# mt15_pla.net
KiCad netlist of a schematic drawn in EAGLE
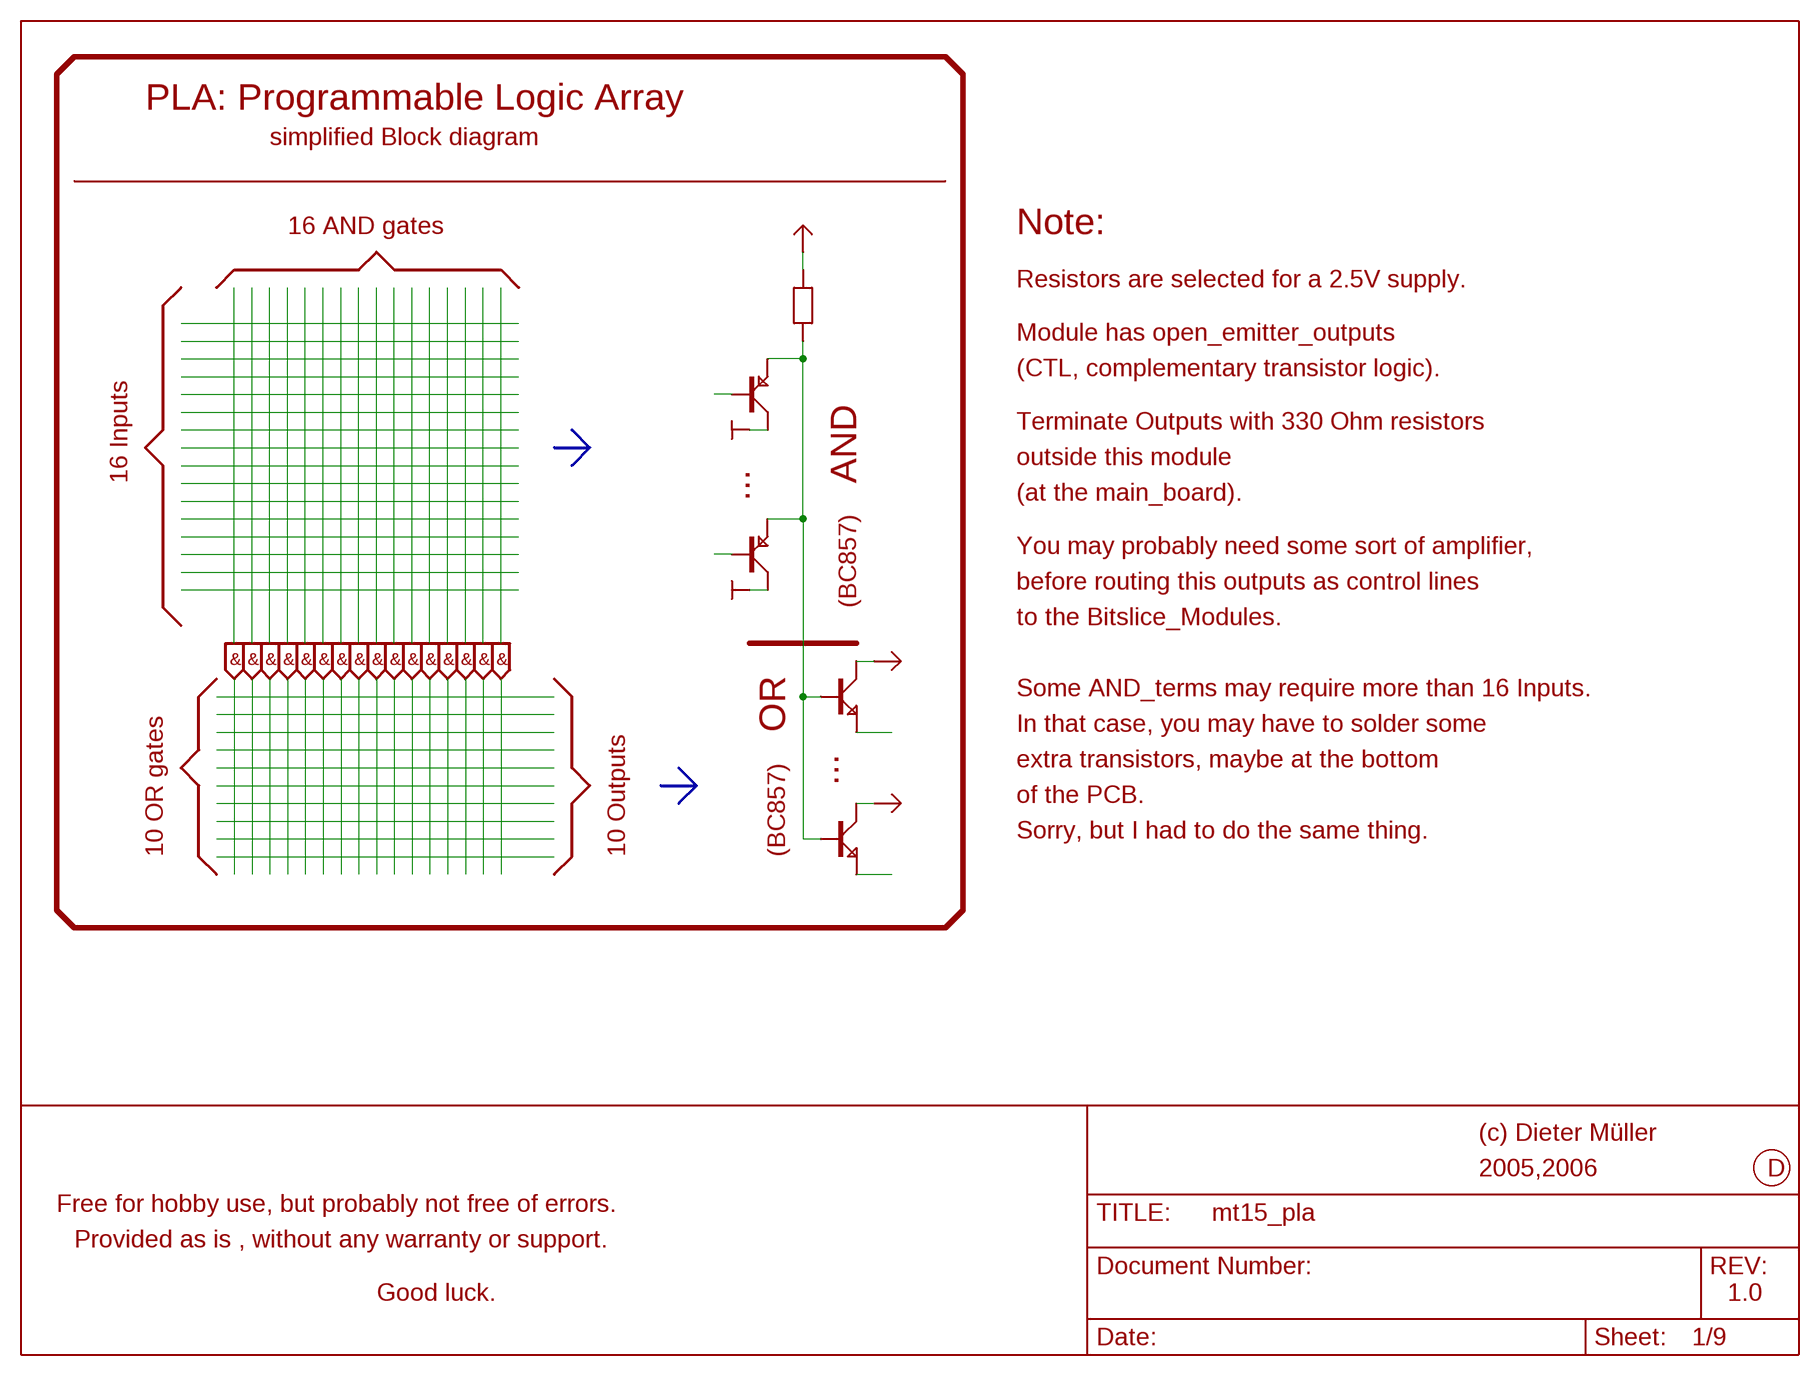
[diagram p0: schematic, sheet 1]
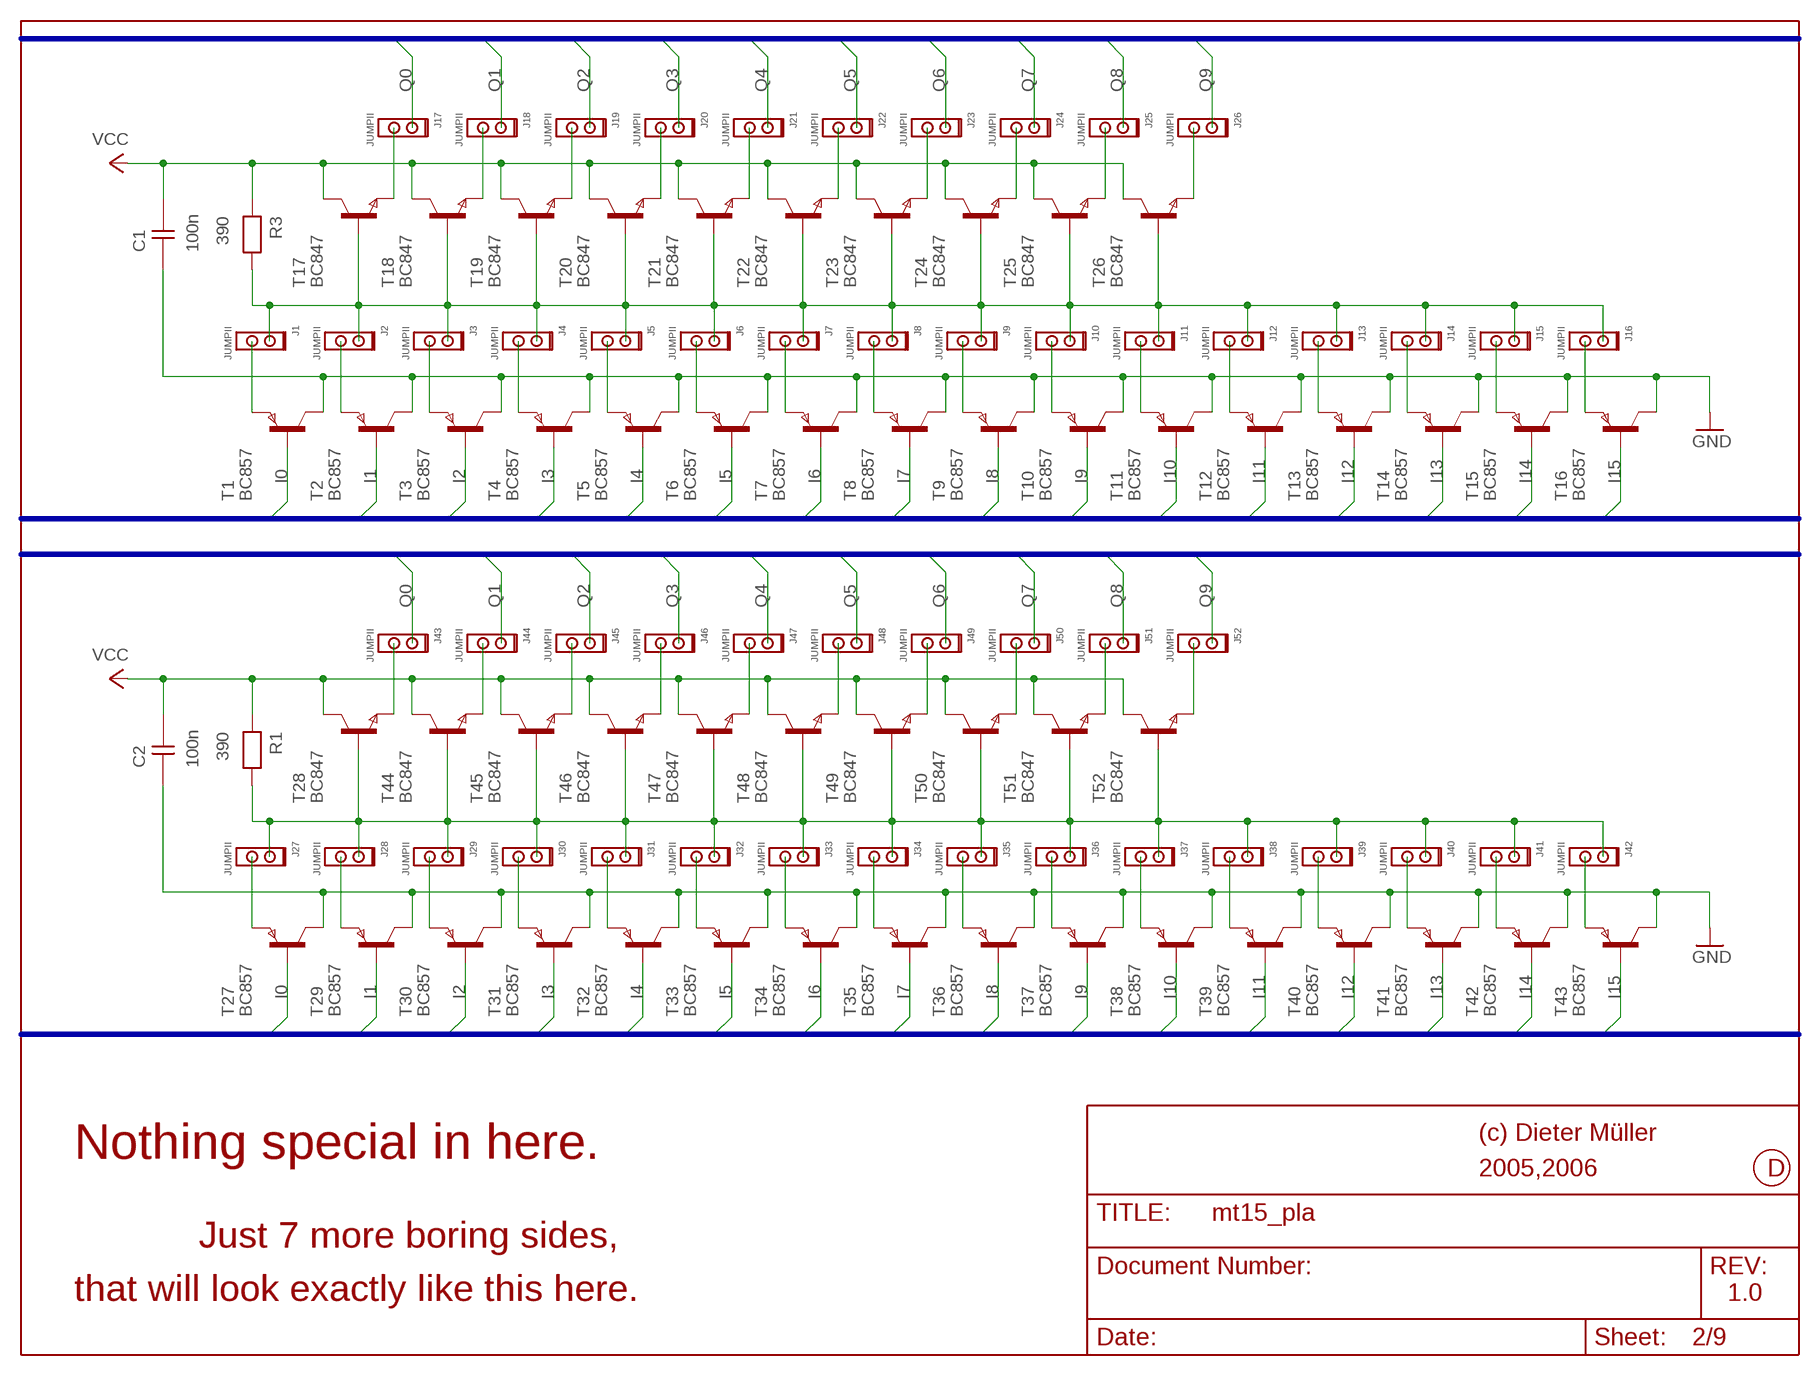
[diagram p1: schematic, sheet 2]
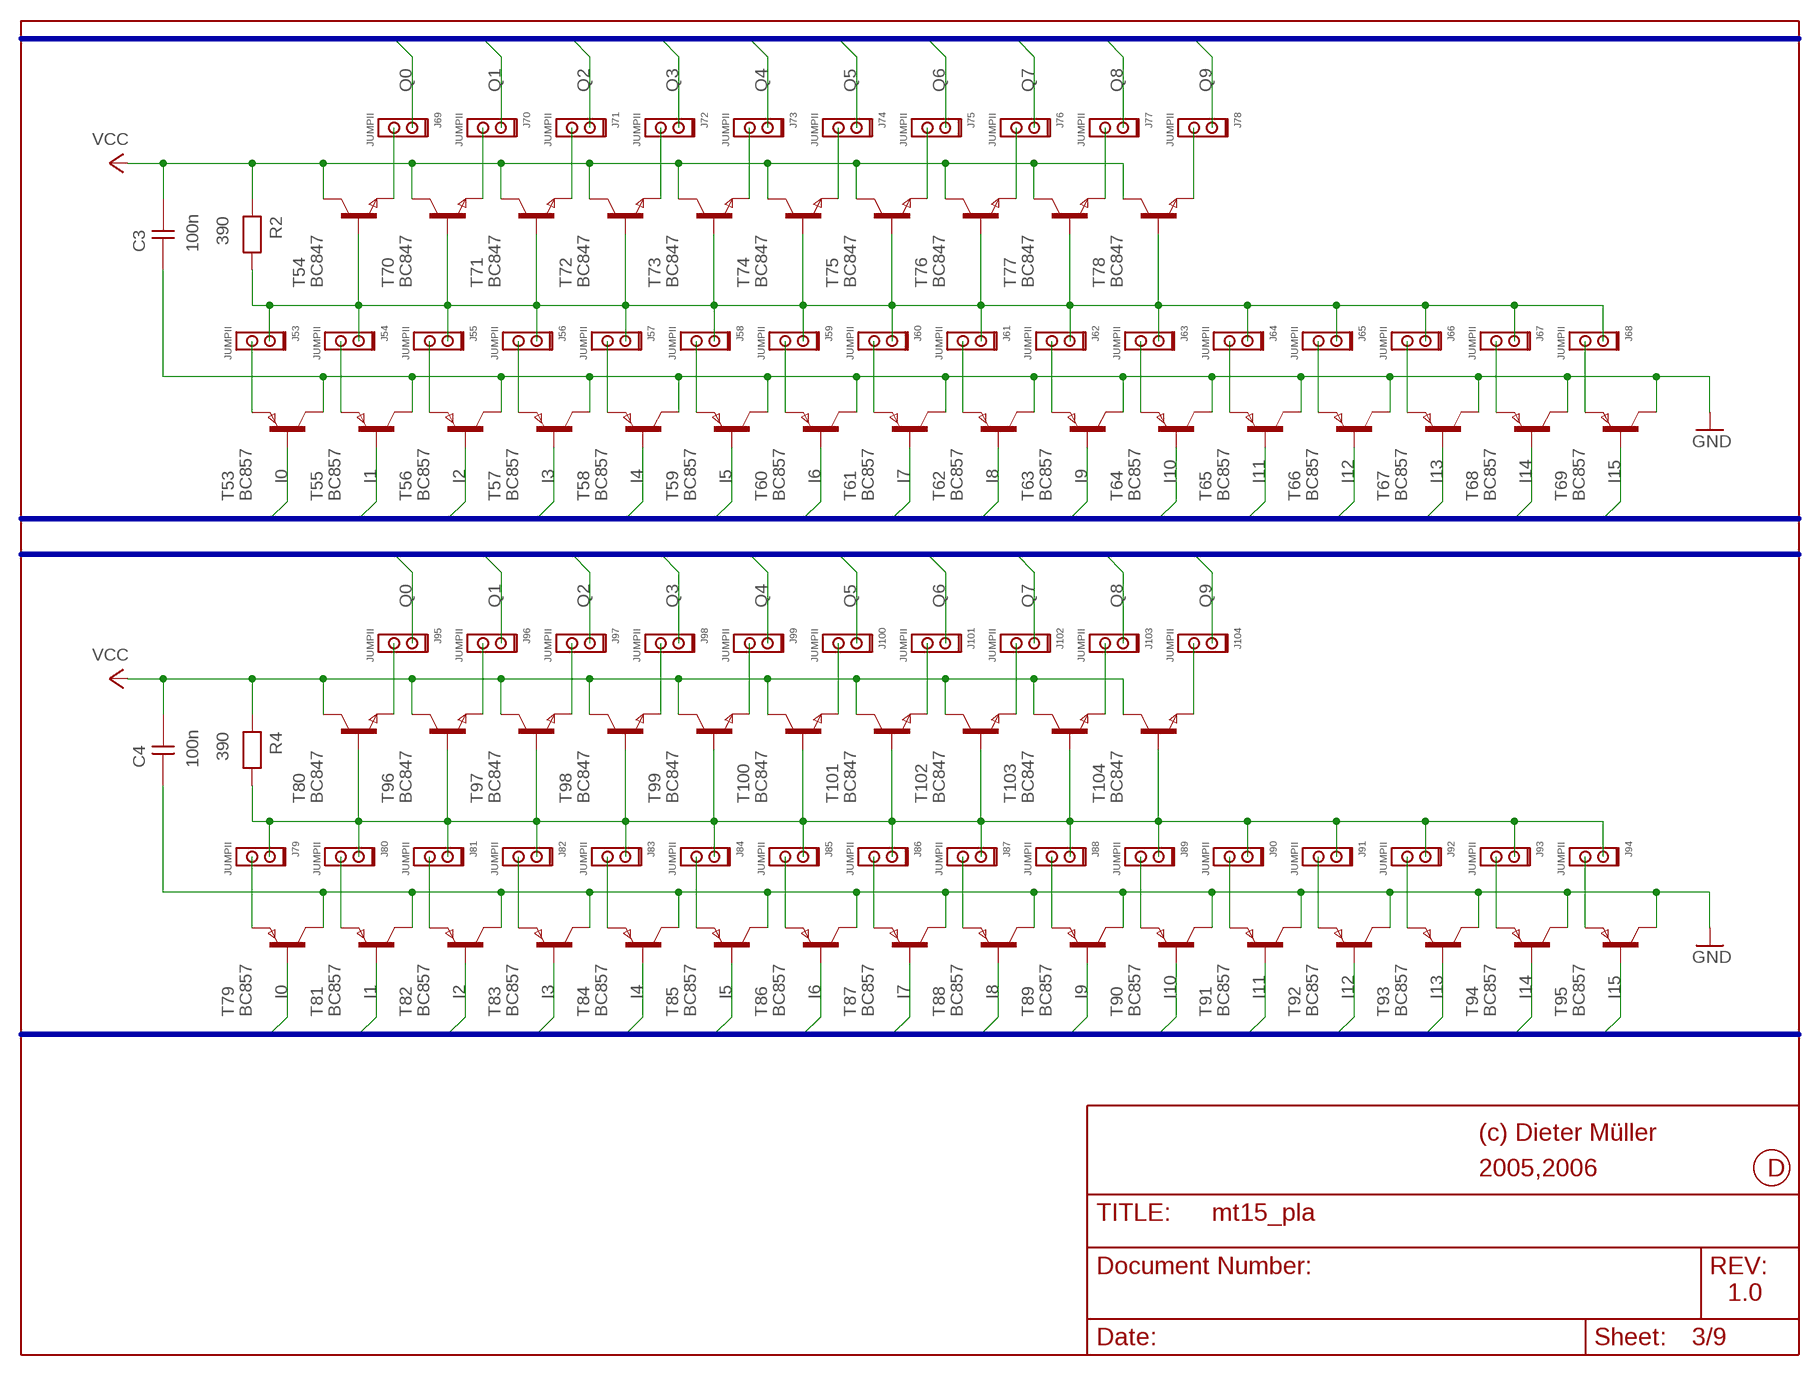
[diagram p2: schematic, sheet 3]
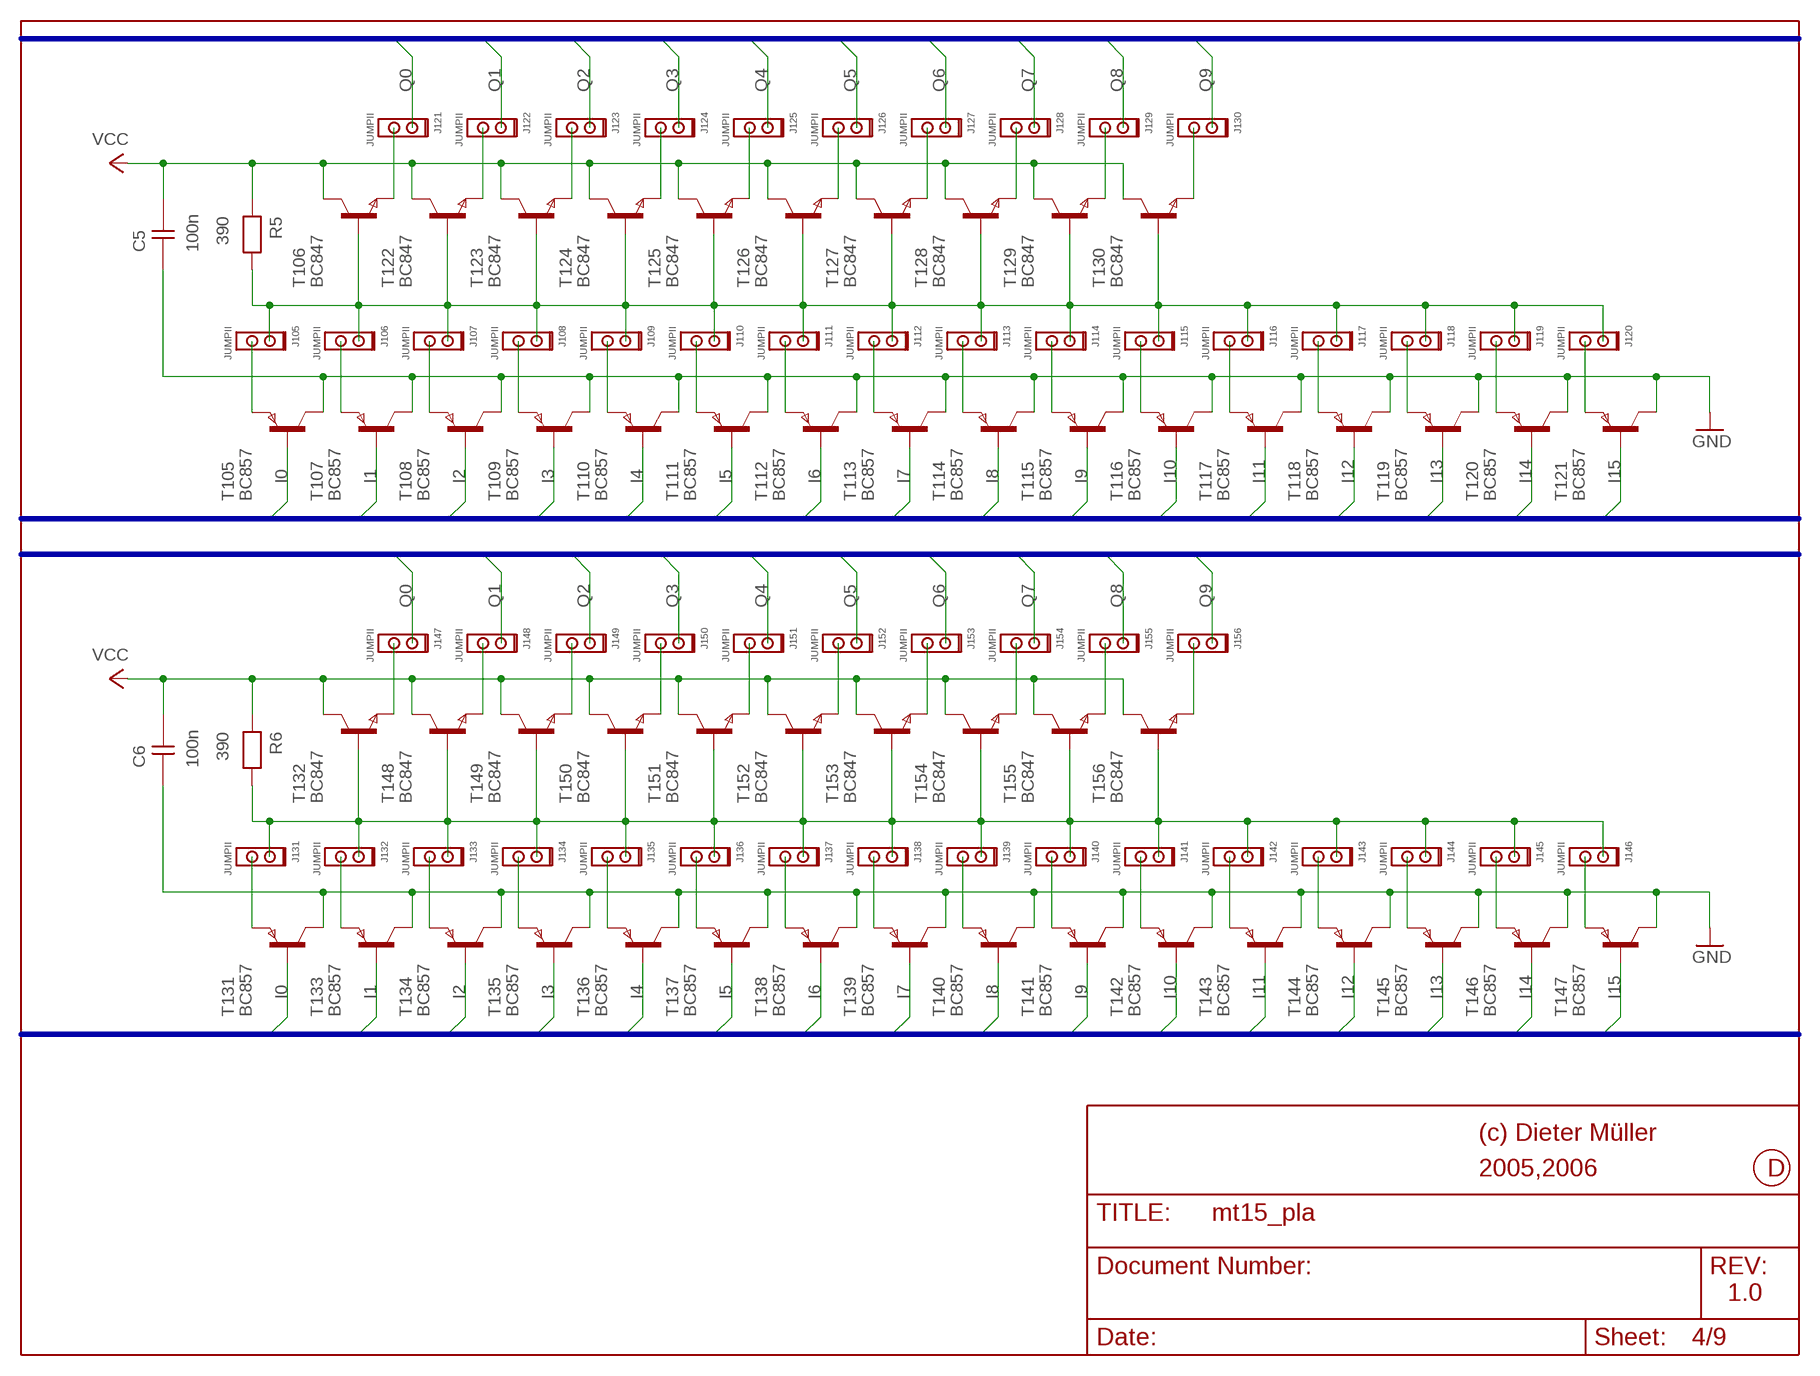
[diagram p3: schematic, sheet 4]
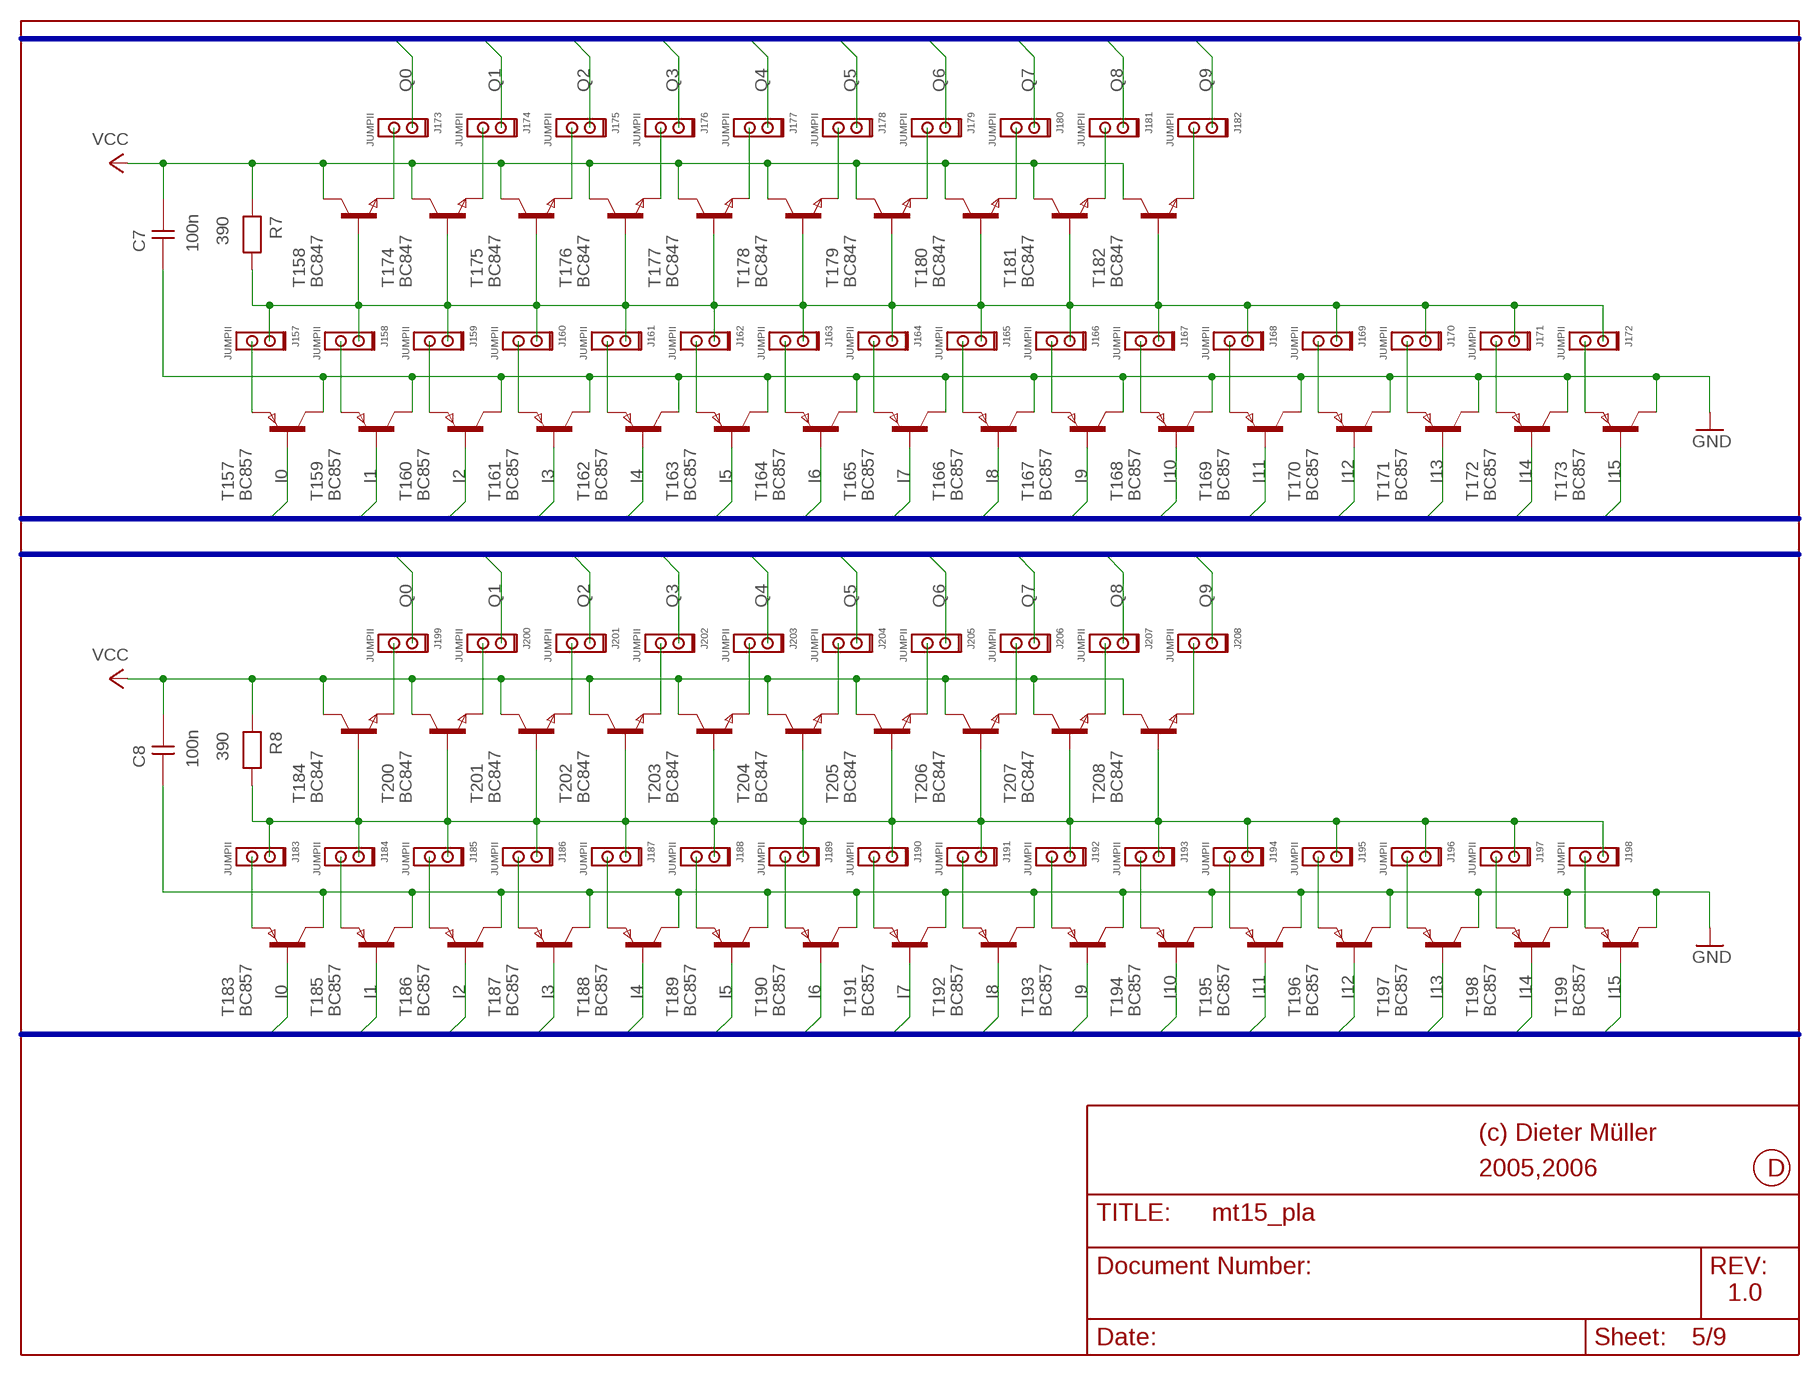
[diagram p4: schematic, sheet 5]
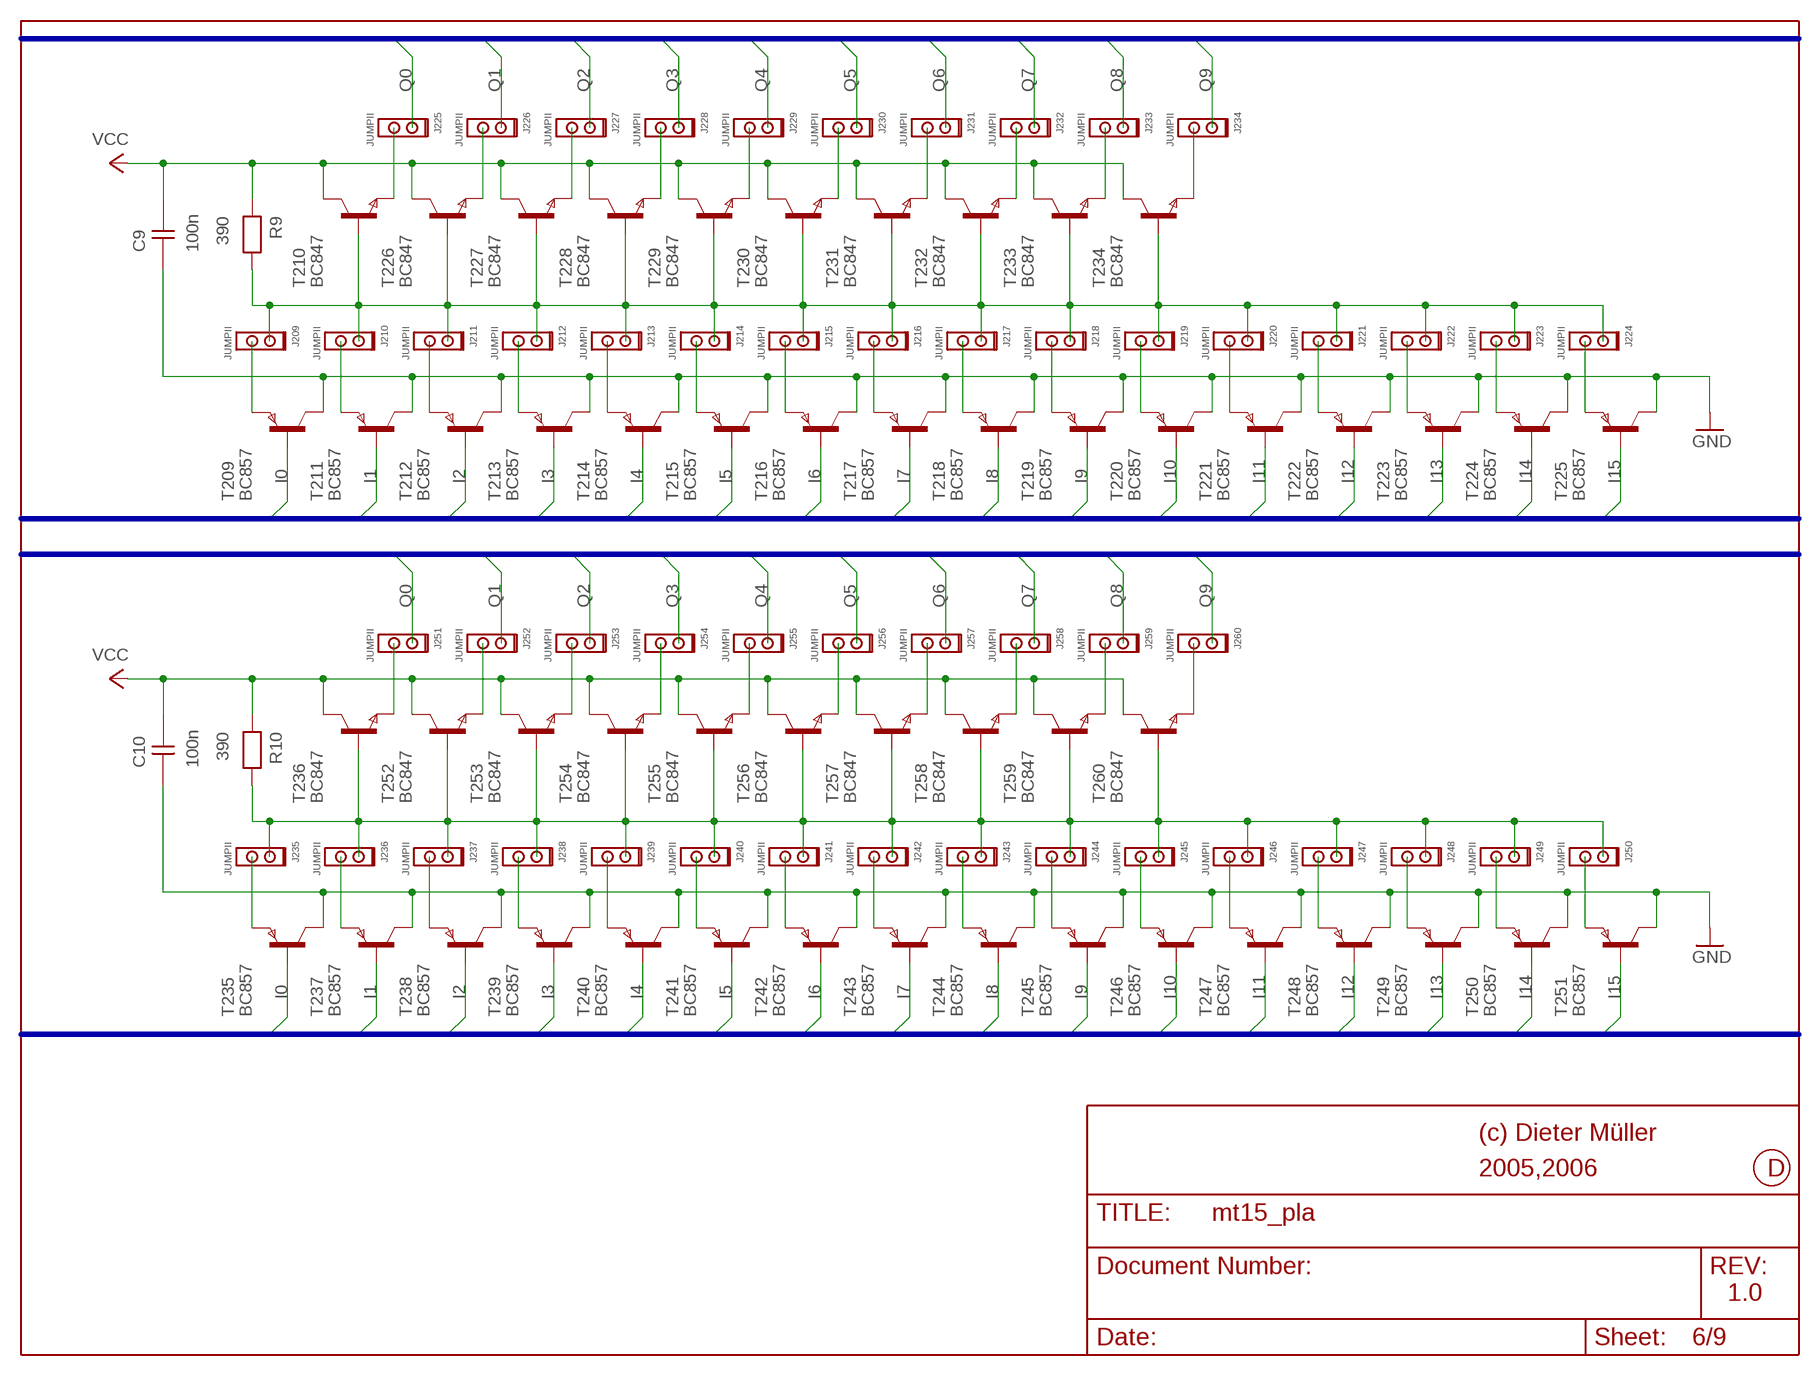
[diagram p5: schematic, sheet 6]
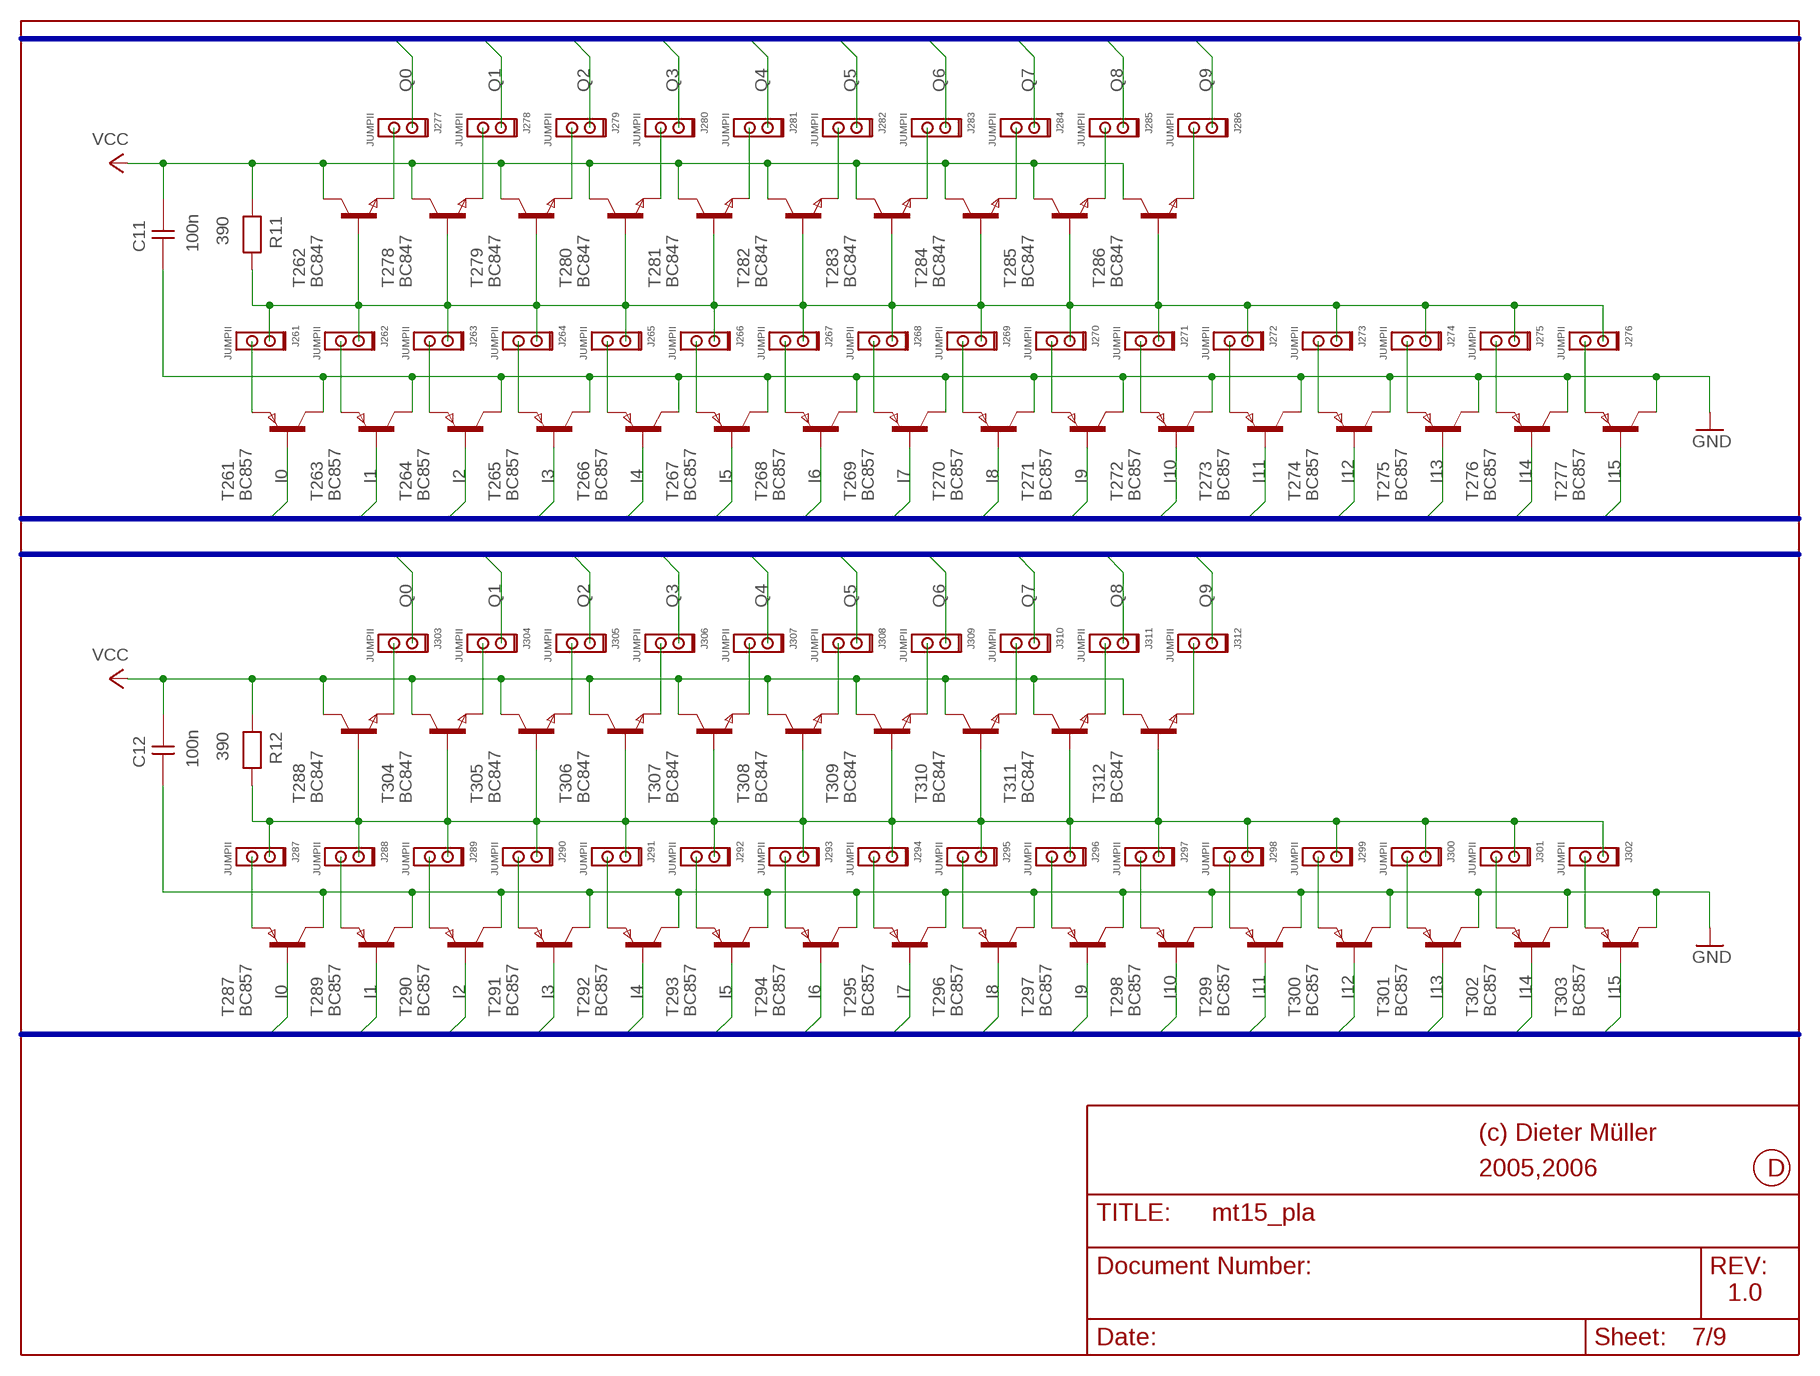
[diagram p6: schematic, sheet 7]
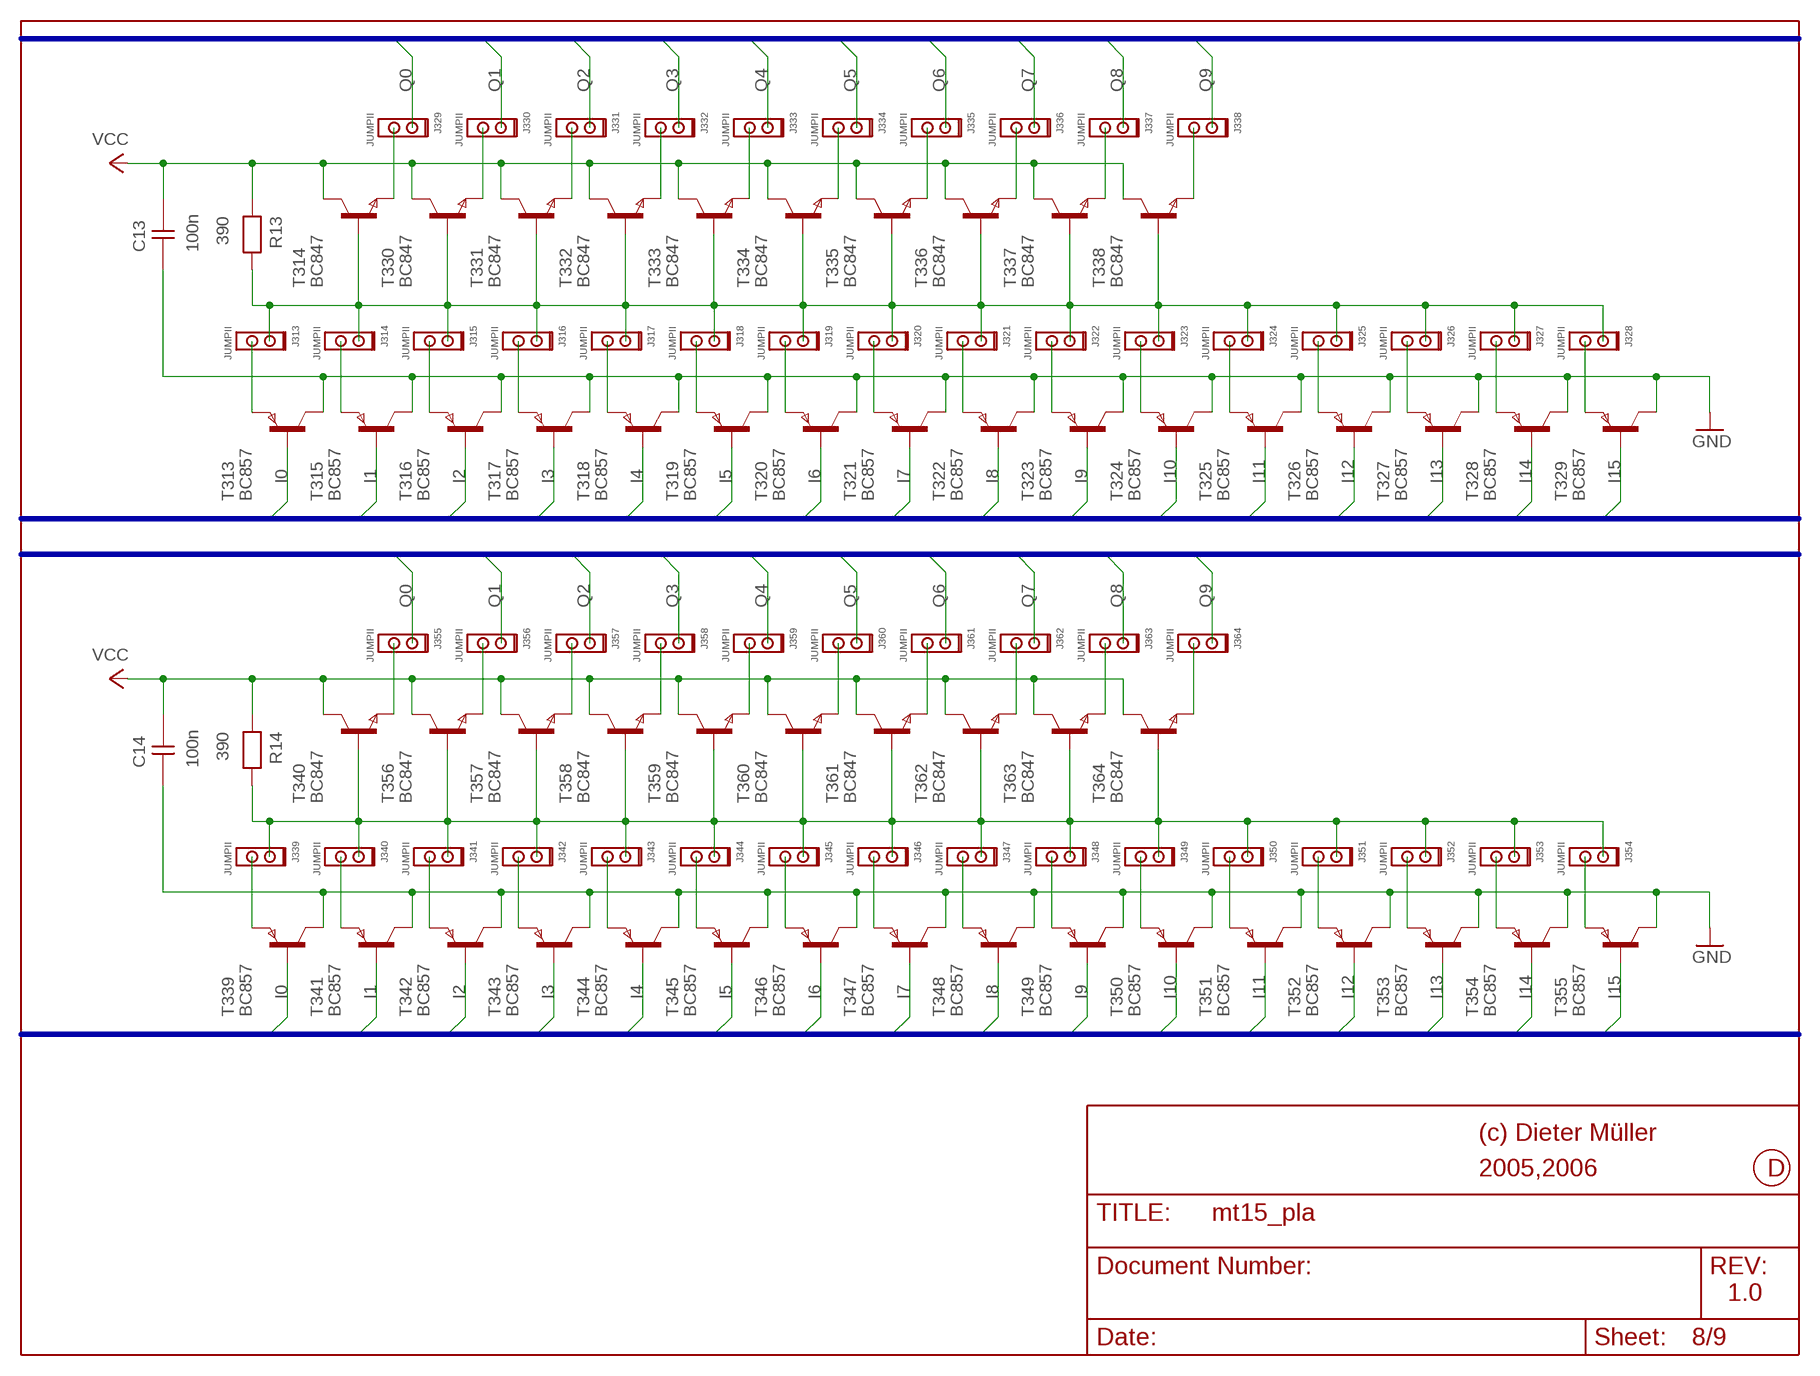
[diagram p7: schematic, sheet 8]
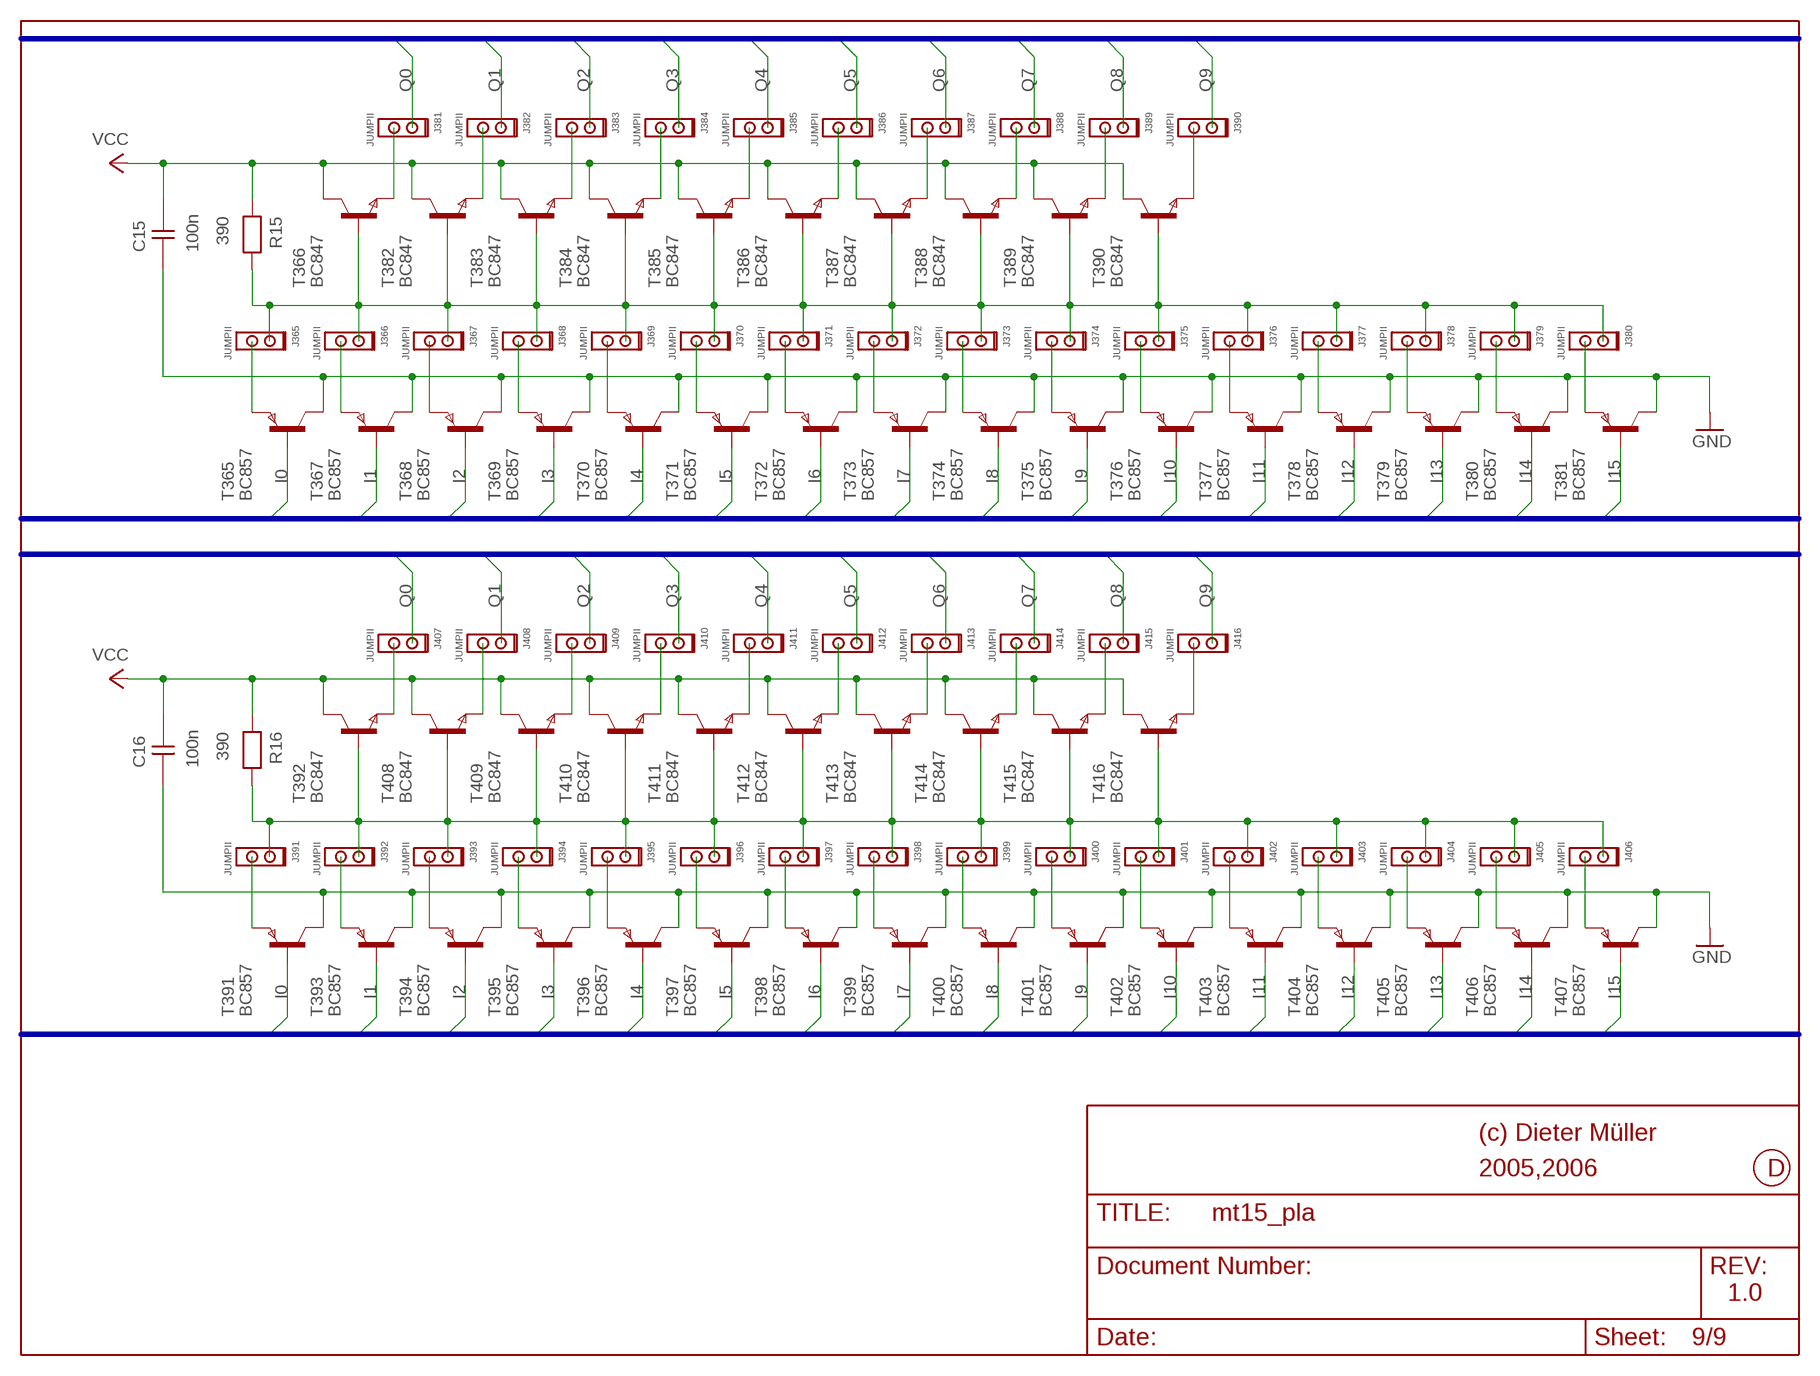
[diagram p8: schematic, sheet 9]

(export (version "E")
  (design (tool "Eeschema 10.0.6"))
  (components
    (comp (ref "C9")
      (value "100n")
      (footprint "eagle-import:0204")
      (libsource (lib "eagle-import") (part "CAPNP-5"))
    )
    (comp (ref "C10")
      (value "100n")
      (footprint "eagle-import:0204")
      (libsource (lib "eagle-import") (part "CAPNP-5"))
    )
    (comp (ref "J209")
      (value "JUMPII")
      (footprint "eagle-import:JUMPII")
      (libsource (lib "eagle-import") (part "JUMPII@2"))
    )
    (comp (ref "J210")
      (value "JUMPII")
      (footprint "eagle-import:JUMPII")
      (libsource (lib "eagle-import") (part "JUMPII@2"))
    )
    (comp (ref "J211")
      (value "JUMPII")
      (footprint "eagle-import:JUMPII")
      (libsource (lib "eagle-import") (part "JUMPII@2"))
    )
    (comp (ref "J212")
      (value "JUMPII")
      (footprint "eagle-import:JUMPII")
      (libsource (lib "eagle-import") (part "JUMPII@2"))
    )
    (comp (ref "J213")
      (value "JUMPII")
      (footprint "eagle-import:JUMPII")
      (libsource (lib "eagle-import") (part "JUMPII@2"))
    )
    (comp (ref "J214")
      (value "JUMPII")
      (footprint "eagle-import:JUMPII")
      (libsource (lib "eagle-import") (part "JUMPII@2"))
    )
    (comp (ref "J215")
      (value "JUMPII")
      (footprint "eagle-import:JUMPII")
      (libsource (lib "eagle-import") (part "JUMPII@2"))
    )
    (comp (ref "J216")
      (value "JUMPII")
      (footprint "eagle-import:JUMPII")
      (libsource (lib "eagle-import") (part "JUMPII@2"))
    )
    (comp (ref "J217")
      (value "JUMPII")
      (footprint "eagle-import:JUMPII")
      (libsource (lib "eagle-import") (part "JUMPII@2"))
    )
    (comp (ref "J218")
      (value "JUMPII")
      (footprint "eagle-import:JUMPII")
      (libsource (lib "eagle-import") (part "JUMPII@2"))
    )
    (comp (ref "J219")
      (value "JUMPII")
      (footprint "eagle-import:JUMPII")
      (libsource (lib "eagle-import") (part "JUMPII@2"))
    )
    (comp (ref "J220")
      (value "JUMPII")
      (footprint "eagle-import:JUMPII")
      (libsource (lib "eagle-import") (part "JUMPII@2"))
    )
    (comp (ref "J221")
      (value "JUMPII")
      (footprint "eagle-import:JUMPII")
      (libsource (lib "eagle-import") (part "JUMPII@2"))
    )
    (comp (ref "J222")
      (value "JUMPII")
      (footprint "eagle-import:JUMPII")
      (libsource (lib "eagle-import") (part "JUMPII@2"))
    )
    (comp (ref "J223")
      (value "JUMPII")
      (footprint "eagle-import:JUMPII")
      (libsource (lib "eagle-import") (part "JUMPII@2"))
    )
    (comp (ref "J224")
      (value "JUMPII")
      (footprint "eagle-import:JUMPII")
      (libsource (lib "eagle-import") (part "JUMPII@2"))
    )
    (comp (ref "J225")
      (value "JUMPII")
      (footprint "eagle-import:JUMPII")
      (libsource (lib "eagle-import") (part "JUMPII@2"))
    )
    (comp (ref "J226")
      (value "JUMPII")
      (footprint "eagle-import:JUMPII")
      (libsource (lib "eagle-import") (part "JUMPII@2"))
    )
    (comp (ref "J227")
      (value "JUMPII")
      (footprint "eagle-import:JUMPII")
      (libsource (lib "eagle-import") (part "JUMPII@2"))
    )
    (comp (ref "J228")
      (value "JUMPII")
      (footprint "eagle-import:JUMPII")
      (libsource (lib "eagle-import") (part "JUMPII@2"))
    )
    (comp (ref "J229")
      (value "JUMPII")
      (footprint "eagle-import:JUMPII")
      (libsource (lib "eagle-import") (part "JUMPII@2"))
    )
    (comp (ref "J230")
      (value "JUMPII")
      (footprint "eagle-import:JUMPII")
      (libsource (lib "eagle-import") (part "JUMPII@2"))
    )
    (comp (ref "J231")
      (value "JUMPII")
      (footprint "eagle-import:JUMPII")
      (libsource (lib "eagle-import") (part "JUMPII@2"))
    )
    (comp (ref "J232")
      (value "JUMPII")
      (footprint "eagle-import:JUMPII")
      (libsource (lib "eagle-import") (part "JUMPII@2"))
    )
    (comp (ref "J233")
      (value "JUMPII")
      (footprint "eagle-import:JUMPII")
      (libsource (lib "eagle-import") (part "JUMPII@2"))
    )
    (comp (ref "J234")
      (value "JUMPII")
      (footprint "eagle-import:JUMPII")
      (libsource (lib "eagle-import") (part "JUMPII@2"))
    )
    (comp (ref "J235")
      (value "JUMPII")
      (footprint "eagle-import:JUMPII")
      (libsource (lib "eagle-import") (part "JUMPII@2"))
    )
    (comp (ref "J236")
      (value "JUMPII")
      (footprint "eagle-import:JUMPII")
      (libsource (lib "eagle-import") (part "JUMPII@2"))
    )
    (comp (ref "J237")
      (value "JUMPII")
      (footprint "eagle-import:JUMPII")
      (libsource (lib "eagle-import") (part "JUMPII@2"))
    )
    (comp (ref "J238")
      (value "JUMPII")
      (footprint "eagle-import:JUMPII")
      (libsource (lib "eagle-import") (part "JUMPII@2"))
    )
    (comp (ref "J239")
      (value "JUMPII")
      (footprint "eagle-import:JUMPII")
      (libsource (lib "eagle-import") (part "JUMPII@2"))
    )
    (comp (ref "J240")
      (value "JUMPII")
      (footprint "eagle-import:JUMPII")
      (libsource (lib "eagle-import") (part "JUMPII@2"))
    )
    (comp (ref "J241")
      (value "JUMPII")
      (footprint "eagle-import:JUMPII")
      (libsource (lib "eagle-import") (part "JUMPII@2"))
    )
    (comp (ref "J242")
      (value "JUMPII")
      (footprint "eagle-import:JUMPII")
      (libsource (lib "eagle-import") (part "JUMPII@2"))
    )
    (comp (ref "J243")
      (value "JUMPII")
      (footprint "eagle-import:JUMPII")
      (libsource (lib "eagle-import") (part "JUMPII@2"))
    )
    (comp (ref "J244")
      (value "JUMPII")
      (footprint "eagle-import:JUMPII")
      (libsource (lib "eagle-import") (part "JUMPII@2"))
    )
    (comp (ref "J245")
      (value "JUMPII")
      (footprint "eagle-import:JUMPII")
      (libsource (lib "eagle-import") (part "JUMPII@2"))
    )
    (comp (ref "J246")
      (value "JUMPII")
      (footprint "eagle-import:JUMPII")
      (libsource (lib "eagle-import") (part "JUMPII@2"))
    )
    (comp (ref "J247")
      (value "JUMPII")
      (footprint "eagle-import:JUMPII")
      (libsource (lib "eagle-import") (part "JUMPII@2"))
    )
    (comp (ref "J248")
      (value "JUMPII")
      (footprint "eagle-import:JUMPII")
      (libsource (lib "eagle-import") (part "JUMPII@2"))
    )
    (comp (ref "J249")
      (value "JUMPII")
      (footprint "eagle-import:JUMPII")
      (libsource (lib "eagle-import") (part "JUMPII@2"))
    )
    (comp (ref "J250")
      (value "JUMPII")
      (footprint "eagle-import:JUMPII")
      (libsource (lib "eagle-import") (part "JUMPII@2"))
    )
    (comp (ref "J251")
      (value "JUMPII")
      (footprint "eagle-import:JUMPII")
      (libsource (lib "eagle-import") (part "JUMPII@2"))
    )
    (comp (ref "J252")
      (value "JUMPII")
      (footprint "eagle-import:JUMPII")
      (libsource (lib "eagle-import") (part "JUMPII@2"))
    )
    (comp (ref "J253")
      (value "JUMPII")
      (footprint "eagle-import:JUMPII")
      (libsource (lib "eagle-import") (part "JUMPII@2"))
    )
    (comp (ref "J254")
      (value "JUMPII")
      (footprint "eagle-import:JUMPII")
      (libsource (lib "eagle-import") (part "JUMPII@2"))
    )
    (comp (ref "J255")
      (value "JUMPII")
      (footprint "eagle-import:JUMPII")
      (libsource (lib "eagle-import") (part "JUMPII@2"))
    )
    (comp (ref "J256")
      (value "JUMPII")
      (footprint "eagle-import:JUMPII")
      (libsource (lib "eagle-import") (part "JUMPII@2"))
    )
    (comp (ref "J257")
      (value "JUMPII")
      (footprint "eagle-import:JUMPII")
      (libsource (lib "eagle-import") (part "JUMPII@2"))
    )
    (comp (ref "J258")
      (value "JUMPII")
      (footprint "eagle-import:JUMPII")
      (libsource (lib "eagle-import") (part "JUMPII@2"))
    )
    (comp (ref "J259")
      (value "JUMPII")
      (footprint "eagle-import:JUMPII")
      (libsource (lib "eagle-import") (part "JUMPII@2"))
    )
    (comp (ref "J260")
      (value "JUMPII")
      (footprint "eagle-import:JUMPII")
      (libsource (lib "eagle-import") (part "JUMPII@2"))
    )
    (comp (ref "R9")
      (value "390")
      (footprint "eagle-import:0204")
      (libsource (lib "eagle-import") (part "RESEU-7,5"))
    )
    (comp (ref "R10")
      (value "390")
      (footprint "eagle-import:0204")
      (libsource (lib "eagle-import") (part "RESEU-7,5"))
    )
    (comp (ref "T209")
      (value "BC857")
      (footprint "eagle-import:SOT-23")
      (libsource (lib "eagle-import") (part "BC557"))
    )
    (comp (ref "T210")
      (value "BC847")
      (footprint "eagle-import:SOT-23")
      (libsource (lib "eagle-import") (part "BC547"))
    )
    (comp (ref "T211")
      (value "BC857")
      (footprint "eagle-import:SOT-23")
      (libsource (lib "eagle-import") (part "BC557"))
    )
    (comp (ref "T212")
      (value "BC857")
      (footprint "eagle-import:SOT-23")
      (libsource (lib "eagle-import") (part "BC557"))
    )
    (comp (ref "T213")
      (value "BC857")
      (footprint "eagle-import:SOT-23")
      (libsource (lib "eagle-import") (part "BC557"))
    )
    (comp (ref "T214")
      (value "BC857")
      (footprint "eagle-import:SOT-23")
      (libsource (lib "eagle-import") (part "BC557"))
    )
    (comp (ref "T215")
      (value "BC857")
      (footprint "eagle-import:SOT-23")
      (libsource (lib "eagle-import") (part "BC557"))
    )
    (comp (ref "T216")
      (value "BC857")
      (footprint "eagle-import:SOT-23")
      (libsource (lib "eagle-import") (part "BC557"))
    )
    (comp (ref "T217")
      (value "BC857")
      (footprint "eagle-import:SOT-23")
      (libsource (lib "eagle-import") (part "BC557"))
    )
    (comp (ref "T218")
      (value "BC857")
      (footprint "eagle-import:SOT-23")
      (libsource (lib "eagle-import") (part "BC557"))
    )
    (comp (ref "T219")
      (value "BC857")
      (footprint "eagle-import:SOT-23")
      (libsource (lib "eagle-import") (part "BC557"))
    )
    (comp (ref "T220")
      (value "BC857")
      (footprint "eagle-import:SOT-23")
      (libsource (lib "eagle-import") (part "BC557"))
    )
    (comp (ref "T221")
      (value "BC857")
      (footprint "eagle-import:SOT-23")
      (libsource (lib "eagle-import") (part "BC557"))
    )
    (comp (ref "T222")
      (value "BC857")
      (footprint "eagle-import:SOT-23")
      (libsource (lib "eagle-import") (part "BC557"))
    )
    (comp (ref "T223")
      (value "BC857")
      (footprint "eagle-import:SOT-23")
      (libsource (lib "eagle-import") (part "BC557"))
    )
    (comp (ref "T224")
      (value "BC857")
      (footprint "eagle-import:SOT-23")
      (libsource (lib "eagle-import") (part "BC557"))
    )
    (comp (ref "T225")
      (value "BC857")
      (footprint "eagle-import:SOT-23")
      (libsource (lib "eagle-import") (part "BC557"))
    )
    (comp (ref "T226")
      (value "BC847")
      (footprint "eagle-import:SOT-23")
      (libsource (lib "eagle-import") (part "BC547"))
    )
    (comp (ref "T227")
      (value "BC847")
      (footprint "eagle-import:SOT-23")
      (libsource (lib "eagle-import") (part "BC547"))
    )
    (comp (ref "T228")
      (value "BC847")
      (footprint "eagle-import:SOT-23")
      (libsource (lib "eagle-import") (part "BC547"))
    )
    (comp (ref "T229")
      (value "BC847")
      (footprint "eagle-import:SOT-23")
      (libsource (lib "eagle-import") (part "BC547"))
    )
    (comp (ref "T230")
      (value "BC847")
      (footprint "eagle-import:SOT-23")
      (libsource (lib "eagle-import") (part "BC547"))
    )
    (comp (ref "T231")
      (value "BC847")
      (footprint "eagle-import:SOT-23")
      (libsource (lib "eagle-import") (part "BC547"))
    )
    (comp (ref "T232")
      (value "BC847")
      (footprint "eagle-import:SOT-23")
      (libsource (lib "eagle-import") (part "BC547"))
    )
    (comp (ref "T233")
      (value "BC847")
      (footprint "eagle-import:SOT-23")
      (libsource (lib "eagle-import") (part "BC547"))
    )
    (comp (ref "T234")
      (value "BC847")
      (footprint "eagle-import:SOT-23")
      (libsource (lib "eagle-import") (part "BC547"))
    )
    (comp (ref "T235")
      (value "BC857")
      (footprint "eagle-import:SOT-23")
      (libsource (lib "eagle-import") (part "BC557"))
    )
    (comp (ref "T236")
      (value "BC847")
      (footprint "eagle-import:SOT-23")
      (libsource (lib "eagle-import") (part "BC547"))
    )
    (comp (ref "T237")
      (value "BC857")
      (footprint "eagle-import:SOT-23")
      (libsource (lib "eagle-import") (part "BC557"))
    )
    (comp (ref "T238")
      (value "BC857")
      (footprint "eagle-import:SOT-23")
      (libsource (lib "eagle-import") (part "BC557"))
    )
    (comp (ref "T239")
      (value "BC857")
      (footprint "eagle-import:SOT-23")
      (libsource (lib "eagle-import") (part "BC557"))
    )
    (comp (ref "T240")
      (value "BC857")
      (footprint "eagle-import:SOT-23")
      (libsource (lib "eagle-import") (part "BC557"))
    )
    (comp (ref "T241")
      (value "BC857")
      (footprint "eagle-import:SOT-23")
      (libsource (lib "eagle-import") (part "BC557"))
    )
    (comp (ref "T242")
      (value "BC857")
      (footprint "eagle-import:SOT-23")
      (libsource (lib "eagle-import") (part "BC557"))
    )
    (comp (ref "T243")
      (value "BC857")
      (footprint "eagle-import:SOT-23")
      (libsource (lib "eagle-import") (part "BC557"))
    )
    (comp (ref "T244")
      (value "BC857")
      (footprint "eagle-import:SOT-23")
      (libsource (lib "eagle-import") (part "BC557"))
    )
    (comp (ref "T245")
      (value "BC857")
      (footprint "eagle-import:SOT-23")
      (libsource (lib "eagle-import") (part "BC557"))
    )
    (comp (ref "T246")
      (value "BC857")
      (footprint "eagle-import:SOT-23")
      (libsource (lib "eagle-import") (part "BC557"))
    )
    (comp (ref "T247")
      (value "BC857")
      (footprint "eagle-import:SOT-23")
      (libsource (lib "eagle-import") (part "BC557"))
    )
    (comp (ref "T248")
      (value "BC857")
      (footprint "eagle-import:SOT-23")
      (libsource (lib "eagle-import") (part "BC557"))
    )
    (comp (ref "T249")
      (value "BC857")
      (footprint "eagle-import:SOT-23")
      (libsource (lib "eagle-import") (part "BC557"))
    )
    (comp (ref "T250")
      (value "BC857")
      (footprint "eagle-import:SOT-23")
      (libsource (lib "eagle-import") (part "BC557"))
    )
    (comp (ref "T251")
      (value "BC857")
      (footprint "eagle-import:SOT-23")
      (libsource (lib "eagle-import") (part "BC557"))
    )
    (comp (ref "T252")
      (value "BC847")
      (footprint "eagle-import:SOT-23")
      (libsource (lib "eagle-import") (part "BC547"))
    )
    (comp (ref "T253")
      (value "BC847")
      (footprint "eagle-import:SOT-23")
      (libsource (lib "eagle-import") (part "BC547"))
    )
    (comp (ref "T254")
      (value "BC847")
      (footprint "eagle-import:SOT-23")
      (libsource (lib "eagle-import") (part "BC547"))
    )
    (comp (ref "T255")
      (value "BC847")
      (footprint "eagle-import:SOT-23")
      (libsource (lib "eagle-import") (part "BC547"))
    )
    (comp (ref "T256")
      (value "BC847")
      (footprint "eagle-import:SOT-23")
      (libsource (lib "eagle-import") (part "BC547"))
    )
    (comp (ref "T257")
      (value "BC847")
      (footprint "eagle-import:SOT-23")
      (libsource (lib "eagle-import") (part "BC547"))
    )
    (comp (ref "T258")
      (value "BC847")
      (footprint "eagle-import:SOT-23")
      (libsource (lib "eagle-import") (part "BC547"))
    )
    (comp (ref "T259")
      (value "BC847")
      (footprint "eagle-import:SOT-23")
      (libsource (lib "eagle-import") (part "BC547"))
    )
    (comp (ref "T260")
      (value "BC847")
      (footprint "eagle-import:SOT-23")
      (libsource (lib "eagle-import") (part "BC547"))
    )
    (comp (ref "C7")
      (value "100n")
      (footprint "eagle-import:0204")
      (libsource (lib "eagle-import") (part "CAPNP-5"))
    )
    (comp (ref "C8")
      (value "100n")
      (footprint "eagle-import:0204")
      (libsource (lib "eagle-import") (part "CAPNP-5"))
    )
    (comp (ref "J157")
      (value "JUMPII")
      (footprint "eagle-import:JUMPII")
      (libsource (lib "eagle-import") (part "JUMPII@2"))
    )
    (comp (ref "J158")
      (value "JUMPII")
      (footprint "eagle-import:JUMPII")
      (libsource (lib "eagle-import") (part "JUMPII@2"))
    )
    (comp (ref "J159")
      (value "JUMPII")
      (footprint "eagle-import:JUMPII")
      (libsource (lib "eagle-import") (part "JUMPII@2"))
    )
    (comp (ref "J160")
      (value "JUMPII")
      (footprint "eagle-import:JUMPII")
      (libsource (lib "eagle-import") (part "JUMPII@2"))
    )
    (comp (ref "J161")
      (value "JUMPII")
      (footprint "eagle-import:JUMPII")
      (libsource (lib "eagle-import") (part "JUMPII@2"))
    )
    (comp (ref "J162")
      (value "JUMPII")
      (footprint "eagle-import:JUMPII")
      (libsource (lib "eagle-import") (part "JUMPII@2"))
    )
    (comp (ref "J163")
      (value "JUMPII")
      (footprint "eagle-import:JUMPII")
      (libsource (lib "eagle-import") (part "JUMPII@2"))
    )
    (comp (ref "J164")
      (value "JUMPII")
      (footprint "eagle-import:JUMPII")
      (libsource (lib "eagle-import") (part "JUMPII@2"))
    )
    (comp (ref "J165")
      (value "JUMPII")
      (footprint "eagle-import:JUMPII")
      (libsource (lib "eagle-import") (part "JUMPII@2"))
    )
    (comp (ref "J166")
      (value "JUMPII")
      (footprint "eagle-import:JUMPII")
      (libsource (lib "eagle-import") (part "JUMPII@2"))
    )
    (comp (ref "J167")
      (value "JUMPII")
      (footprint "eagle-import:JUMPII")
      (libsource (lib "eagle-import") (part "JUMPII@2"))
    )
    (comp (ref "J168")
      (value "JUMPII")
      (footprint "eagle-import:JUMPII")
      (libsource (lib "eagle-import") (part "JUMPII@2"))
    )
    (comp (ref "J169")
      (value "JUMPII")
      (footprint "eagle-import:JUMPII")
      (libsource (lib "eagle-import") (part "JUMPII@2"))
    )
    (comp (ref "J170")
      (value "JUMPII")
      (footprint "eagle-import:JUMPII")
      (libsource (lib "eagle-import") (part "JUMPII@2"))
    )
    (comp (ref "J171")
      (value "JUMPII")
      (footprint "eagle-import:JUMPII")
      (libsource (lib "eagle-import") (part "JUMPII@2"))
    )
    (comp (ref "J172")
      (value "JUMPII")
      (footprint "eagle-import:JUMPII")
      (libsource (lib "eagle-import") (part "JUMPII@2"))
    )
    (comp (ref "J173")
      (value "JUMPII")
      (footprint "eagle-import:JUMPII")
      (libsource (lib "eagle-import") (part "JUMPII@2"))
    )
    (comp (ref "J174")
      (value "JUMPII")
      (footprint "eagle-import:JUMPII")
      (libsource (lib "eagle-import") (part "JUMPII@2"))
    )
    (comp (ref "J175")
      (value "JUMPII")
      (footprint "eagle-import:JUMPII")
      (libsource (lib "eagle-import") (part "JUMPII@2"))
    )
    (comp (ref "J176")
      (value "JUMPII")
      (footprint "eagle-import:JUMPII")
      (libsource (lib "eagle-import") (part "JUMPII@2"))
    )
    (comp (ref "J177")
      (value "JUMPII")
      (footprint "eagle-import:JUMPII")
      (libsource (lib "eagle-import") (part "JUMPII@2"))
    )
    (comp (ref "J178")
      (value "JUMPII")
      (footprint "eagle-import:JUMPII")
      (libsource (lib "eagle-import") (part "JUMPII@2"))
    )
    (comp (ref "J179")
      (value "JUMPII")
      (footprint "eagle-import:JUMPII")
      (libsource (lib "eagle-import") (part "JUMPII@2"))
    )
    (comp (ref "J180")
      (value "JUMPII")
      (footprint "eagle-import:JUMPII")
      (libsource (lib "eagle-import") (part "JUMPII@2"))
    )
    (comp (ref "J181")
      (value "JUMPII")
      (footprint "eagle-import:JUMPII")
      (libsource (lib "eagle-import") (part "JUMPII@2"))
    )
    (comp (ref "J182")
      (value "JUMPII")
      (footprint "eagle-import:JUMPII")
      (libsource (lib "eagle-import") (part "JUMPII@2"))
    )
    (comp (ref "J183")
      (value "JUMPII")
      (footprint "eagle-import:JUMPII")
      (libsource (lib "eagle-import") (part "JUMPII@2"))
    )
    (comp (ref "J184")
      (value "JUMPII")
      (footprint "eagle-import:JUMPII")
      (libsource (lib "eagle-import") (part "JUMPII@2"))
    )
    (comp (ref "J185")
      (value "JUMPII")
      (footprint "eagle-import:JUMPII")
      (libsource (lib "eagle-import") (part "JUMPII@2"))
    )
    (comp (ref "J186")
      (value "JUMPII")
      (footprint "eagle-import:JUMPII")
      (libsource (lib "eagle-import") (part "JUMPII@2"))
    )
    (comp (ref "J187")
      (value "JUMPII")
      (footprint "eagle-import:JUMPII")
      (libsource (lib "eagle-import") (part "JUMPII@2"))
    )
    (comp (ref "J188")
      (value "JUMPII")
      (footprint "eagle-import:JUMPII")
      (libsource (lib "eagle-import") (part "JUMPII@2"))
    )
    (comp (ref "J189")
      (value "JUMPII")
      (footprint "eagle-import:JUMPII")
      (libsource (lib "eagle-import") (part "JUMPII@2"))
    )
    (comp (ref "J190")
      (value "JUMPII")
      (footprint "eagle-import:JUMPII")
      (libsource (lib "eagle-import") (part "JUMPII@2"))
    )
    (comp (ref "J191")
      (value "JUMPII")
      (footprint "eagle-import:JUMPII")
      (libsource (lib "eagle-import") (part "JUMPII@2"))
    )
    (comp (ref "J192")
      (value "JUMPII")
      (footprint "eagle-import:JUMPII")
      (libsource (lib "eagle-import") (part "JUMPII@2"))
    )
    (comp (ref "J193")
      (value "JUMPII")
      (footprint "eagle-import:JUMPII")
      (libsource (lib "eagle-import") (part "JUMPII@2"))
    )
    (comp (ref "J194")
      (value "JUMPII")
      (footprint "eagle-import:JUMPII")
      (libsource (lib "eagle-import") (part "JUMPII@2"))
    )
    (comp (ref "J195")
      (value "JUMPII")
      (footprint "eagle-import:JUMPII")
      (libsource (lib "eagle-import") (part "JUMPII@2"))
    )
    (comp (ref "J196")
      (value "JUMPII")
      (footprint "eagle-import:JUMPII")
      (libsource (lib "eagle-import") (part "JUMPII@2"))
    )
    (comp (ref "J197")
      (value "JUMPII")
      (footprint "eagle-import:JUMPII")
      (libsource (lib "eagle-import") (part "JUMPII@2"))
    )
    (comp (ref "J198")
      (value "JUMPII")
      (footprint "eagle-import:JUMPII")
      (libsource (lib "eagle-import") (part "JUMPII@2"))
    )
    (comp (ref "J199")
      (value "JUMPII")
      (footprint "eagle-import:JUMPII")
      (libsource (lib "eagle-import") (part "JUMPII@2"))
    )
    (comp (ref "J200")
      (value "JUMPII")
      (footprint "eagle-import:JUMPII")
      (libsource (lib "eagle-import") (part "JUMPII@2"))
    )
    (comp (ref "J201")
      (value "JUMPII")
      (footprint "eagle-import:JUMPII")
      (libsource (lib "eagle-import") (part "JUMPII@2"))
    )
    (comp (ref "J202")
      (value "JUMPII")
      (footprint "eagle-import:JUMPII")
      (libsource (lib "eagle-import") (part "JUMPII@2"))
    )
    (comp (ref "J203")
      (value "JUMPII")
      (footprint "eagle-import:JUMPII")
      (libsource (lib "eagle-import") (part "JUMPII@2"))
    )
    (comp (ref "J204")
      (value "JUMPII")
      (footprint "eagle-import:JUMPII")
      (libsource (lib "eagle-import") (part "JUMPII@2"))
    )
    (comp (ref "J205")
      (value "JUMPII")
      (footprint "eagle-import:JUMPII")
      (libsource (lib "eagle-import") (part "JUMPII@2"))
    )
    (comp (ref "J206")
      (value "JUMPII")
      (footprint "eagle-import:JUMPII")
      (libsource (lib "eagle-import") (part "JUMPII@2"))
    )
    (comp (ref "J207")
      (value "JUMPII")
      (footprint "eagle-import:JUMPII")
      (libsource (lib "eagle-import") (part "JUMPII@2"))
    )
    (comp (ref "J208")
      (value "JUMPII")
      (footprint "eagle-import:JUMPII")
      (libsource (lib "eagle-import") (part "JUMPII@2"))
    )
    (comp (ref "R7")
      (value "390")
      (footprint "eagle-import:0204")
      (libsource (lib "eagle-import") (part "RESEU-7,5"))
    )
    (comp (ref "R8")
      (value "390")
      (footprint "eagle-import:0204")
      (libsource (lib "eagle-import") (part "RESEU-7,5"))
    )
    (comp (ref "T157")
      (value "BC857")
      (footprint "eagle-import:SOT-23")
      (libsource (lib "eagle-import") (part "BC557"))
    )
    (comp (ref "T158")
      (value "BC847")
      (footprint "eagle-import:SOT-23")
      (libsource (lib "eagle-import") (part "BC547"))
    )
    (comp (ref "T159")
      (value "BC857")
      (footprint "eagle-import:SOT-23")
      (libsource (lib "eagle-import") (part "BC557"))
    )
    (comp (ref "T160")
      (value "BC857")
      (footprint "eagle-import:SOT-23")
      (libsource (lib "eagle-import") (part "BC557"))
    )
    (comp (ref "T161")
      (value "BC857")
      (footprint "eagle-import:SOT-23")
      (libsource (lib "eagle-import") (part "BC557"))
    )
    (comp (ref "T162")
      (value "BC857")
      (footprint "eagle-import:SOT-23")
      (libsource (lib "eagle-import") (part "BC557"))
    )
    (comp (ref "T163")
      (value "BC857")
      (footprint "eagle-import:SOT-23")
      (libsource (lib "eagle-import") (part "BC557"))
    )
    (comp (ref "T164")
      (value "BC857")
      (footprint "eagle-import:SOT-23")
      (libsource (lib "eagle-import") (part "BC557"))
    )
    (comp (ref "T165")
      (value "BC857")
      (footprint "eagle-import:SOT-23")
      (libsource (lib "eagle-import") (part "BC557"))
    )
    (comp (ref "T166")
      (value "BC857")
      (footprint "eagle-import:SOT-23")
      (libsource (lib "eagle-import") (part "BC557"))
    )
    (comp (ref "T167")
      (value "BC857")
      (footprint "eagle-import:SOT-23")
      (libsource (lib "eagle-import") (part "BC557"))
    )
    (comp (ref "T168")
      (value "BC857")
      (footprint "eagle-import:SOT-23")
      (libsource (lib "eagle-import") (part "BC557"))
    )
    (comp (ref "T169")
      (value "BC857")
      (footprint "eagle-import:SOT-23")
      (libsource (lib "eagle-import") (part "BC557"))
    )
    (comp (ref "T170")
      (value "BC857")
      (footprint "eagle-import:SOT-23")
      (libsource (lib "eagle-import") (part "BC557"))
    )
    (comp (ref "T171")
      (value "BC857")
      (footprint "eagle-import:SOT-23")
      (libsource (lib "eagle-import") (part "BC557"))
    )
    (comp (ref "T172")
      (value "BC857")
      (footprint "eagle-import:SOT-23")
      (libsource (lib "eagle-import") (part "BC557"))
    )
    (comp (ref "T173")
      (value "BC857")
      (footprint "eagle-import:SOT-23")
      (libsource (lib "eagle-import") (part "BC557"))
    )
    (comp (ref "T174")
      (value "BC847")
      (footprint "eagle-import:SOT-23")
      (libsource (lib "eagle-import") (part "BC547"))
    )
    (comp (ref "T175")
      (value "BC847")
      (footprint "eagle-import:SOT-23")
      (libsource (lib "eagle-import") (part "BC547"))
    )
    (comp (ref "T176")
      (value "BC847")
      (footprint "eagle-import:SOT-23")
      (libsource (lib "eagle-import") (part "BC547"))
    )
    (comp (ref "T177")
      (value "BC847")
      (footprint "eagle-import:SOT-23")
      (libsource (lib "eagle-import") (part "BC547"))
    )
    (comp (ref "T178")
      (value "BC847")
      (footprint "eagle-import:SOT-23")
      (libsource (lib "eagle-import") (part "BC547"))
    )
    (comp (ref "T179")
      (value "BC847")
      (footprint "eagle-import:SOT-23")
      (libsource (lib "eagle-import") (part "BC547"))
    )
    (comp (ref "T180")
      (value "BC847")
      (footprint "eagle-import:SOT-23")
      (libsource (lib "eagle-import") (part "BC547"))
    )
    (comp (ref "T181")
      (value "BC847")
      (footprint "eagle-import:SOT-23")
      (libsource (lib "eagle-import") (part "BC547"))
    )
    (comp (ref "T182")
      (value "BC847")
      (footprint "eagle-import:SOT-23")
      (libsource (lib "eagle-import") (part "BC547"))
    )
    (comp (ref "T183")
      (value "BC857")
      (footprint "eagle-import:SOT-23")
      (libsource (lib "eagle-import") (part "BC557"))
    )
    (comp (ref "T184")
      (value "BC847")
      (footprint "eagle-import:SOT-23")
      (libsource (lib "eagle-import") (part "BC547"))
    )
    (comp (ref "T185")
      (value "BC857")
      (footprint "eagle-import:SOT-23")
      (libsource (lib "eagle-import") (part "BC557"))
    )
    (comp (ref "T186")
      (value "BC857")
      (footprint "eagle-import:SOT-23")
      (libsource (lib "eagle-import") (part "BC557"))
    )
    (comp (ref "T187")
      (value "BC857")
      (footprint "eagle-import:SOT-23")
      (libsource (lib "eagle-import") (part "BC557"))
    )
    (comp (ref "T188")
      (value "BC857")
      (footprint "eagle-import:SOT-23")
      (libsource (lib "eagle-import") (part "BC557"))
    )
    (comp (ref "T189")
      (value "BC857")
      (footprint "eagle-import:SOT-23")
      (libsource (lib "eagle-import") (part "BC557"))
    )
    (comp (ref "T190")
      (value "BC857")
      (footprint "eagle-import:SOT-23")
      (libsource (lib "eagle-import") (part "BC557"))
    )
    (comp (ref "T191")
      (value "BC857")
      (footprint "eagle-import:SOT-23")
      (libsource (lib "eagle-import") (part "BC557"))
    )
    (comp (ref "T192")
      (value "BC857")
      (footprint "eagle-import:SOT-23")
      (libsource (lib "eagle-import") (part "BC557"))
    )
    (comp (ref "T193")
      (value "BC857")
      (footprint "eagle-import:SOT-23")
      (libsource (lib "eagle-import") (part "BC557"))
    )
    (comp (ref "T194")
      (value "BC857")
      (footprint "eagle-import:SOT-23")
      (libsource (lib "eagle-import") (part "BC557"))
    )
    (comp (ref "T195")
      (value "BC857")
      (footprint "eagle-import:SOT-23")
      (libsource (lib "eagle-import") (part "BC557"))
    )
    (comp (ref "T196")
      (value "BC857")
      (footprint "eagle-import:SOT-23")
      (libsource (lib "eagle-import") (part "BC557"))
    )
    (comp (ref "T197")
      (value "BC857")
      (footprint "eagle-import:SOT-23")
      (libsource (lib "eagle-import") (part "BC557"))
    )
    (comp (ref "T198")
      (value "BC857")
      (footprint "eagle-import:SOT-23")
      (libsource (lib "eagle-import") (part "BC557"))
    )
    (comp (ref "T199")
      (value "BC857")
      (footprint "eagle-import:SOT-23")
      (libsource (lib "eagle-import") (part "BC557"))
    )
    (comp (ref "T200")
      (value "BC847")
      (footprint "eagle-import:SOT-23")
      (libsource (lib "eagle-import") (part "BC547"))
    )
    (comp (ref "T201")
      (value "BC847")
      (footprint "eagle-import:SOT-23")
      (libsource (lib "eagle-import") (part "BC547"))
    )
    (comp (ref "T202")
      (value "BC847")
      (footprint "eagle-import:SOT-23")
      (libsource (lib "eagle-import") (part "BC547"))
    )
    (comp (ref "T203")
      (value "BC847")
      (footprint "eagle-import:SOT-23")
      (libsource (lib "eagle-import") (part "BC547"))
    )
    (comp (ref "T204")
      (value "BC847")
      (footprint "eagle-import:SOT-23")
      (libsource (lib "eagle-import") (part "BC547"))
    )
    (comp (ref "T205")
      (value "BC847")
      (footprint "eagle-import:SOT-23")
      (libsource (lib "eagle-import") (part "BC547"))
    )
    (comp (ref "T206")
      (value "BC847")
      (footprint "eagle-import:SOT-23")
      (libsource (lib "eagle-import") (part "BC547"))
    )
    (comp (ref "T207")
      (value "BC847")
      (footprint "eagle-import:SOT-23")
      (libsource (lib "eagle-import") (part "BC547"))
    )
    (comp (ref "T208")
      (value "BC847")
      (footprint "eagle-import:SOT-23")
      (libsource (lib "eagle-import") (part "BC547"))
    )
    (comp (ref "C1")
      (value "100n")
      (footprint "eagle-import:0204")
      (libsource (lib "eagle-import") (part "CAPNP-5"))
    )
    (comp (ref "C2")
      (value "100n")
      (footprint "eagle-import:0204")
      (libsource (lib "eagle-import") (part "CAPNP-5"))
    )
    (comp (ref "J1")
      (value "JUMPII")
      (footprint "eagle-import:JUMPII")
      (libsource (lib "eagle-import") (part "JUMPII@2"))
    )
    (comp (ref "J2")
      (value "JUMPII")
      (footprint "eagle-import:JUMPII")
      (libsource (lib "eagle-import") (part "JUMPII@2"))
    )
    (comp (ref "J3")
      (value "JUMPII")
      (footprint "eagle-import:JUMPII")
      (libsource (lib "eagle-import") (part "JUMPII@2"))
    )
    (comp (ref "J4")
      (value "JUMPII")
      (footprint "eagle-import:JUMPII")
      (libsource (lib "eagle-import") (part "JUMPII@2"))
    )
    (comp (ref "J5")
      (value "JUMPII")
      (footprint "eagle-import:JUMPII")
      (libsource (lib "eagle-import") (part "JUMPII@2"))
    )
    (comp (ref "J6")
      (value "JUMPII")
      (footprint "eagle-import:JUMPII")
      (libsource (lib "eagle-import") (part "JUMPII@2"))
    )
    (comp (ref "J7")
      (value "JUMPII")
      (footprint "eagle-import:JUMPII")
      (libsource (lib "eagle-import") (part "JUMPII@2"))
    )
    (comp (ref "J8")
      (value "JUMPII")
      (footprint "eagle-import:JUMPII")
      (libsource (lib "eagle-import") (part "JUMPII@2"))
    )
    (comp (ref "J9")
      (value "JUMPII")
      (footprint "eagle-import:JUMPII")
      (libsource (lib "eagle-import") (part "JUMPII@2"))
    )
    (comp (ref "J10")
      (value "JUMPII")
      (footprint "eagle-import:JUMPII")
      (libsource (lib "eagle-import") (part "JUMPII@2"))
    )
    (comp (ref "J11")
      (value "JUMPII")
      (footprint "eagle-import:JUMPII")
      (libsource (lib "eagle-import") (part "JUMPII@2"))
    )
    (comp (ref "J12")
      (value "JUMPII")
      (footprint "eagle-import:JUMPII")
      (libsource (lib "eagle-import") (part "JUMPII@2"))
    )
    (comp (ref "J13")
      (value "JUMPII")
      (footprint "eagle-import:JUMPII")
      (libsource (lib "eagle-import") (part "JUMPII@2"))
    )
    (comp (ref "J14")
      (value "JUMPII")
      (footprint "eagle-import:JUMPII")
      (libsource (lib "eagle-import") (part "JUMPII@2"))
    )
    (comp (ref "J15")
      (value "JUMPII")
      (footprint "eagle-import:JUMPII")
      (libsource (lib "eagle-import") (part "JUMPII@2"))
    )
    (comp (ref "J16")
      (value "JUMPII")
      (footprint "eagle-import:JUMPII")
      (libsource (lib "eagle-import") (part "JUMPII@2"))
    )
    (comp (ref "J17")
      (value "JUMPII")
      (footprint "eagle-import:JUMPII")
      (libsource (lib "eagle-import") (part "JUMPII@2"))
    )
    (comp (ref "J18")
      (value "JUMPII")
      (footprint "eagle-import:JUMPII")
      (libsource (lib "eagle-import") (part "JUMPII@2"))
    )
    (comp (ref "J19")
      (value "JUMPII")
      (footprint "eagle-import:JUMPII")
      (libsource (lib "eagle-import") (part "JUMPII@2"))
    )
    (comp (ref "J20")
      (value "JUMPII")
      (footprint "eagle-import:JUMPII")
      (libsource (lib "eagle-import") (part "JUMPII@2"))
    )
    (comp (ref "J21")
      (value "JUMPII")
      (footprint "eagle-import:JUMPII")
      (libsource (lib "eagle-import") (part "JUMPII@2"))
    )
    (comp (ref "J22")
      (value "JUMPII")
      (footprint "eagle-import:JUMPII")
      (libsource (lib "eagle-import") (part "JUMPII@2"))
    )
    (comp (ref "J23")
      (value "JUMPII")
      (footprint "eagle-import:JUMPII")
      (libsource (lib "eagle-import") (part "JUMPII@2"))
    )
    (comp (ref "J24")
      (value "JUMPII")
      (footprint "eagle-import:JUMPII")
      (libsource (lib "eagle-import") (part "JUMPII@2"))
    )
    (comp (ref "J25")
      (value "JUMPII")
      (footprint "eagle-import:JUMPII")
      (libsource (lib "eagle-import") (part "JUMPII@2"))
    )
    (comp (ref "J26")
      (value "JUMPII")
      (footprint "eagle-import:JUMPII")
      (libsource (lib "eagle-import") (part "JUMPII@2"))
    )
    (comp (ref "J27")
      (value "JUMPII")
      (footprint "eagle-import:JUMPII")
      (libsource (lib "eagle-import") (part "JUMPII@2"))
    )
    (comp (ref "J28")
      (value "JUMPII")
      (footprint "eagle-import:JUMPII")
      (libsource (lib "eagle-import") (part "JUMPII@2"))
    )
    (comp (ref "J29")
      (value "JUMPII")
      (footprint "eagle-import:JUMPII")
      (libsource (lib "eagle-import") (part "JUMPII@2"))
    )
    (comp (ref "J30")
      (value "JUMPII")
      (footprint "eagle-import:JUMPII")
      (libsource (lib "eagle-import") (part "JUMPII@2"))
    )
    (comp (ref "J31")
      (value "JUMPII")
      (footprint "eagle-import:JUMPII")
      (libsource (lib "eagle-import") (part "JUMPII@2"))
    )
    (comp (ref "J32")
      (value "JUMPII")
      (footprint "eagle-import:JUMPII")
      (libsource (lib "eagle-import") (part "JUMPII@2"))
    )
    (comp (ref "J33")
      (value "JUMPII")
      (footprint "eagle-import:JUMPII")
      (libsource (lib "eagle-import") (part "JUMPII@2"))
    )
    (comp (ref "J34")
      (value "JUMPII")
      (footprint "eagle-import:JUMPII")
      (libsource (lib "eagle-import") (part "JUMPII@2"))
    )
    (comp (ref "J35")
      (value "JUMPII")
      (footprint "eagle-import:JUMPII")
      (libsource (lib "eagle-import") (part "JUMPII@2"))
    )
    (comp (ref "J36")
      (value "JUMPII")
      (footprint "eagle-import:JUMPII")
      (libsource (lib "eagle-import") (part "JUMPII@2"))
    )
    (comp (ref "J37")
      (value "JUMPII")
      (footprint "eagle-import:JUMPII")
      (libsource (lib "eagle-import") (part "JUMPII@2"))
    )
    (comp (ref "J38")
      (value "JUMPII")
      (footprint "eagle-import:JUMPII")
      (libsource (lib "eagle-import") (part "JUMPII@2"))
    )
    (comp (ref "J39")
      (value "JUMPII")
      (footprint "eagle-import:JUMPII")
      (libsource (lib "eagle-import") (part "JUMPII@2"))
    )
    (comp (ref "J40")
      (value "JUMPII")
      (footprint "eagle-import:JUMPII")
      (libsource (lib "eagle-import") (part "JUMPII@2"))
    )
    (comp (ref "J41")
      (value "JUMPII")
      (footprint "eagle-import:JUMPII")
      (libsource (lib "eagle-import") (part "JUMPII@2"))
    )
    (comp (ref "J42")
      (value "JUMPII")
      (footprint "eagle-import:JUMPII")
      (libsource (lib "eagle-import") (part "JUMPII@2"))
    )
    (comp (ref "J43")
      (value "JUMPII")
      (footprint "eagle-import:JUMPII")
      (libsource (lib "eagle-import") (part "JUMPII@2"))
    )
    (comp (ref "J44")
      (value "JUMPII")
      (footprint "eagle-import:JUMPII")
      (libsource (lib "eagle-import") (part "JUMPII@2"))
    )
    (comp (ref "J45")
      (value "JUMPII")
      (footprint "eagle-import:JUMPII")
      (libsource (lib "eagle-import") (part "JUMPII@2"))
    )
    (comp (ref "J46")
      (value "JUMPII")
      (footprint "eagle-import:JUMPII")
      (libsource (lib "eagle-import") (part "JUMPII@2"))
    )
    (comp (ref "J47")
      (value "JUMPII")
      (footprint "eagle-import:JUMPII")
      (libsource (lib "eagle-import") (part "JUMPII@2"))
    )
    (comp (ref "J48")
      (value "JUMPII")
      (footprint "eagle-import:JUMPII")
      (libsource (lib "eagle-import") (part "JUMPII@2"))
    )
    (comp (ref "J49")
      (value "JUMPII")
      (footprint "eagle-import:JUMPII")
      (libsource (lib "eagle-import") (part "JUMPII@2"))
    )
    (comp (ref "J50")
      (value "JUMPII")
      (footprint "eagle-import:JUMPII")
      (libsource (lib "eagle-import") (part "JUMPII@2"))
    )
    (comp (ref "J51")
      (value "JUMPII")
      (footprint "eagle-import:JUMPII")
      (libsource (lib "eagle-import") (part "JUMPII@2"))
    )
    (comp (ref "J52")
      (value "JUMPII")
      (footprint "eagle-import:JUMPII")
      (libsource (lib "eagle-import") (part "JUMPII@2"))
    )
    (comp (ref "R1")
      (value "390")
      (footprint "eagle-import:0204")
      (libsource (lib "eagle-import") (part "RESEU-7,5"))
    )
    (comp (ref "R3")
      (value "390")
      (footprint "eagle-import:0204")
      (libsource (lib "eagle-import") (part "RESEU-7,5"))
    )
    (comp (ref "T1")
      (value "BC857")
      (footprint "eagle-import:SOT-23")
      (libsource (lib "eagle-import") (part "BC557"))
    )
    (comp (ref "T2")
      (value "BC857")
      (footprint "eagle-import:SOT-23")
      (libsource (lib "eagle-import") (part "BC557"))
    )
    (comp (ref "T3")
      (value "BC857")
      (footprint "eagle-import:SOT-23")
      (libsource (lib "eagle-import") (part "BC557"))
    )
    (comp (ref "T4")
      (value "BC857")
      (footprint "eagle-import:SOT-23")
      (libsource (lib "eagle-import") (part "BC557"))
    )
    (comp (ref "T5")
      (value "BC857")
      (footprint "eagle-import:SOT-23")
      (libsource (lib "eagle-import") (part "BC557"))
    )
    (comp (ref "T6")
      (value "BC857")
      (footprint "eagle-import:SOT-23")
      (libsource (lib "eagle-import") (part "BC557"))
    )
    (comp (ref "T7")
      (value "BC857")
      (footprint "eagle-import:SOT-23")
      (libsource (lib "eagle-import") (part "BC557"))
    )
    (comp (ref "T8")
      (value "BC857")
      (footprint "eagle-import:SOT-23")
      (libsource (lib "eagle-import") (part "BC557"))
    )
    (comp (ref "T9")
      (value "BC857")
      (footprint "eagle-import:SOT-23")
      (libsource (lib "eagle-import") (part "BC557"))
    )
    (comp (ref "T10")
      (value "BC857")
      (footprint "eagle-import:SOT-23")
      (libsource (lib "eagle-import") (part "BC557"))
    )
    (comp (ref "T11")
      (value "BC857")
      (footprint "eagle-import:SOT-23")
      (libsource (lib "eagle-import") (part "BC557"))
    )
    (comp (ref "T12")
      (value "BC857")
      (footprint "eagle-import:SOT-23")
      (libsource (lib "eagle-import") (part "BC557"))
    )
    (comp (ref "T13")
      (value "BC857")
      (footprint "eagle-import:SOT-23")
      (libsource (lib "eagle-import") (part "BC557"))
    )
    (comp (ref "T14")
      (value "BC857")
      (footprint "eagle-import:SOT-23")
      (libsource (lib "eagle-import") (part "BC557"))
    )
    (comp (ref "T15")
      (value "BC857")
      (footprint "eagle-import:SOT-23")
      (libsource (lib "eagle-import") (part "BC557"))
    )
    (comp (ref "T16")
      (value "BC857")
      (footprint "eagle-import:SOT-23")
      (libsource (lib "eagle-import") (part "BC557"))
    )
    (comp (ref "T17")
      (value "BC847")
      (footprint "eagle-import:SOT-23")
      (libsource (lib "eagle-import") (part "BC547"))
    )
    (comp (ref "T18")
      (value "BC847")
      (footprint "eagle-import:SOT-23")
      (libsource (lib "eagle-import") (part "BC547"))
    )
    (comp (ref "T19")
      (value "BC847")
      (footprint "eagle-import:SOT-23")
      (libsource (lib "eagle-import") (part "BC547"))
    )
    (comp (ref "T20")
      (value "BC847")
      (footprint "eagle-import:SOT-23")
      (libsource (lib "eagle-import") (part "BC547"))
    )
    (comp (ref "T21")
      (value "BC847")
      (footprint "eagle-import:SOT-23")
      (libsource (lib "eagle-import") (part "BC547"))
    )
    (comp (ref "T22")
      (value "BC847")
      (footprint "eagle-import:SOT-23")
      (libsource (lib "eagle-import") (part "BC547"))
    )
    (comp (ref "T23")
      (value "BC847")
      (footprint "eagle-import:SOT-23")
      (libsource (lib "eagle-import") (part "BC547"))
    )
    (comp (ref "T24")
      (value "BC847")
      (footprint "eagle-import:SOT-23")
      (libsource (lib "eagle-import") (part "BC547"))
    )
    (comp (ref "T25")
      (value "BC847")
      (footprint "eagle-import:SOT-23")
      (libsource (lib "eagle-import") (part "BC547"))
    )
    (comp (ref "T26")
      (value "BC847")
      (footprint "eagle-import:SOT-23")
      (libsource (lib "eagle-import") (part "BC547"))
    )
    (comp (ref "T27")
      (value "BC857")
      (footprint "eagle-import:SOT-23")
      (libsource (lib "eagle-import") (part "BC557"))
    )
    (comp (ref "T28")
      (value "BC847")
      (footprint "eagle-import:SOT-23")
      (libsource (lib "eagle-import") (part "BC547"))
    )
    (comp (ref "T29")
      (value "BC857")
      (footprint "eagle-import:SOT-23")
      (libsource (lib "eagle-import") (part "BC557"))
    )
    (comp (ref "T30")
      (value "BC857")
      (footprint "eagle-import:SOT-23")
      (libsource (lib "eagle-import") (part "BC557"))
    )
    (comp (ref "T31")
      (value "BC857")
      (footprint "eagle-import:SOT-23")
      (libsource (lib "eagle-import") (part "BC557"))
    )
    (comp (ref "T32")
      (value "BC857")
      (footprint "eagle-import:SOT-23")
      (libsource (lib "eagle-import") (part "BC557"))
    )
    (comp (ref "T33")
      (value "BC857")
      (footprint "eagle-import:SOT-23")
      (libsource (lib "eagle-import") (part "BC557"))
    )
    (comp (ref "T34")
      (value "BC857")
      (footprint "eagle-import:SOT-23")
      (libsource (lib "eagle-import") (part "BC557"))
    )
    (comp (ref "T35")
      (value "BC857")
      (footprint "eagle-import:SOT-23")
      (libsource (lib "eagle-import") (part "BC557"))
    )
    (comp (ref "T36")
      (value "BC857")
      (footprint "eagle-import:SOT-23")
      (libsource (lib "eagle-import") (part "BC557"))
    )
    (comp (ref "T37")
      (value "BC857")
      (footprint "eagle-import:SOT-23")
      (libsource (lib "eagle-import") (part "BC557"))
    )
    (comp (ref "T38")
      (value "BC857")
      (footprint "eagle-import:SOT-23")
      (libsource (lib "eagle-import") (part "BC557"))
    )
    (comp (ref "T39")
      (value "BC857")
      (footprint "eagle-import:SOT-23")
      (libsource (lib "eagle-import") (part "BC557"))
    )
    (comp (ref "T40")
      (value "BC857")
      (footprint "eagle-import:SOT-23")
      (libsource (lib "eagle-import") (part "BC557"))
    )
    (comp (ref "T41")
      (value "BC857")
      (footprint "eagle-import:SOT-23")
      (libsource (lib "eagle-import") (part "BC557"))
    )
    (comp (ref "T42")
      (value "BC857")
      (footprint "eagle-import:SOT-23")
      (libsource (lib "eagle-import") (part "BC557"))
    )
    (comp (ref "T43")
      (value "BC857")
      (footprint "eagle-import:SOT-23")
      (libsource (lib "eagle-import") (part "BC557"))
    )
    (comp (ref "T44")
      (value "BC847")
      (footprint "eagle-import:SOT-23")
      (libsource (lib "eagle-import") (part "BC547"))
    )
    (comp (ref "T45")
      (value "BC847")
      (footprint "eagle-import:SOT-23")
      (libsource (lib "eagle-import") (part "BC547"))
    )
    (comp (ref "T46")
      (value "BC847")
      (footprint "eagle-import:SOT-23")
      (libsource (lib "eagle-import") (part "BC547"))
    )
    (comp (ref "T47")
      (value "BC847")
      (footprint "eagle-import:SOT-23")
      (libsource (lib "eagle-import") (part "BC547"))
    )
    (comp (ref "T48")
      (value "BC847")
      (footprint "eagle-import:SOT-23")
      (libsource (lib "eagle-import") (part "BC547"))
    )
    (comp (ref "T49")
      (value "BC847")
      (footprint "eagle-import:SOT-23")
      (libsource (lib "eagle-import") (part "BC547"))
    )
    (comp (ref "T50")
      (value "BC847")
      (footprint "eagle-import:SOT-23")
      (libsource (lib "eagle-import") (part "BC547"))
    )
    (comp (ref "T51")
      (value "BC847")
      (footprint "eagle-import:SOT-23")
      (libsource (lib "eagle-import") (part "BC547"))
    )
    (comp (ref "T52")
      (value "BC847")
      (footprint "eagle-import:SOT-23")
      (libsource (lib "eagle-import") (part "BC547"))
    )
    (comp (ref "C15")
      (value "100n")
      (footprint "eagle-import:0204")
      (libsource (lib "eagle-import") (part "CAPNP-5"))
    )
    (comp (ref "C16")
      (value "100n")
      (footprint "eagle-import:0204")
      (libsource (lib "eagle-import") (part "CAPNP-5"))
    )
    (comp (ref "J365")
      (value "JUMPII")
      (footprint "eagle-import:JUMPII")
      (libsource (lib "eagle-import") (part "JUMPII@2"))
    )
    (comp (ref "J366")
      (value "JUMPII")
      (footprint "eagle-import:JUMPII")
      (libsource (lib "eagle-import") (part "JUMPII@2"))
    )
    (comp (ref "J367")
      (value "JUMPII")
      (footprint "eagle-import:JUMPII")
      (libsource (lib "eagle-import") (part "JUMPII@2"))
    )
    (comp (ref "J368")
      (value "JUMPII")
      (footprint "eagle-import:JUMPII")
      (libsource (lib "eagle-import") (part "JUMPII@2"))
    )
    (comp (ref "J369")
      (value "JUMPII")
      (footprint "eagle-import:JUMPII")
      (libsource (lib "eagle-import") (part "JUMPII@2"))
    )
    (comp (ref "J370")
      (value "JUMPII")
      (footprint "eagle-import:JUMPII")
      (libsource (lib "eagle-import") (part "JUMPII@2"))
    )
    (comp (ref "J371")
      (value "JUMPII")
      (footprint "eagle-import:JUMPII")
      (libsource (lib "eagle-import") (part "JUMPII@2"))
    )
    (comp (ref "J372")
      (value "JUMPII")
      (footprint "eagle-import:JUMPII")
      (libsource (lib "eagle-import") (part "JUMPII@2"))
    )
    (comp (ref "J373")
      (value "JUMPII")
      (footprint "eagle-import:JUMPII")
      (libsource (lib "eagle-import") (part "JUMPII@2"))
    )
    (comp (ref "J374")
      (value "JUMPII")
      (footprint "eagle-import:JUMPII")
      (libsource (lib "eagle-import") (part "JUMPII@2"))
    )
    (comp (ref "J375")
      (value "JUMPII")
      (footprint "eagle-import:JUMPII")
      (libsource (lib "eagle-import") (part "JUMPII@2"))
    )
    (comp (ref "J376")
      (value "JUMPII")
      (footprint "eagle-import:JUMPII")
      (libsource (lib "eagle-import") (part "JUMPII@2"))
    )
    (comp (ref "J377")
      (value "JUMPII")
      (footprint "eagle-import:JUMPII")
      (libsource (lib "eagle-import") (part "JUMPII@2"))
    )
    (comp (ref "J378")
      (value "JUMPII")
      (footprint "eagle-import:JUMPII")
      (libsource (lib "eagle-import") (part "JUMPII@2"))
    )
    (comp (ref "J379")
      (value "JUMPII")
      (footprint "eagle-import:JUMPII")
      (libsource (lib "eagle-import") (part "JUMPII@2"))
    )
    (comp (ref "J380")
      (value "JUMPII")
      (footprint "eagle-import:JUMPII")
      (libsource (lib "eagle-import") (part "JUMPII@2"))
    )
    (comp (ref "J381")
      (value "JUMPII")
      (footprint "eagle-import:JUMPII")
      (libsource (lib "eagle-import") (part "JUMPII@2"))
    )
    (comp (ref "J382")
      (value "JUMPII")
      (footprint "eagle-import:JUMPII")
      (libsource (lib "eagle-import") (part "JUMPII@2"))
    )
    (comp (ref "J383")
      (value "JUMPII")
      (footprint "eagle-import:JUMPII")
      (libsource (lib "eagle-import") (part "JUMPII@2"))
    )
    (comp (ref "J384")
      (value "JUMPII")
      (footprint "eagle-import:JUMPII")
      (libsource (lib "eagle-import") (part "JUMPII@2"))
    )
    (comp (ref "J385")
      (value "JUMPII")
      (footprint "eagle-import:JUMPII")
      (libsource (lib "eagle-import") (part "JUMPII@2"))
    )
    (comp (ref "J386")
      (value "JUMPII")
      (footprint "eagle-import:JUMPII")
      (libsource (lib "eagle-import") (part "JUMPII@2"))
    )
    (comp (ref "J387")
      (value "JUMPII")
      (footprint "eagle-import:JUMPII")
      (libsource (lib "eagle-import") (part "JUMPII@2"))
    )
    (comp (ref "J388")
      (value "JUMPII")
      (footprint "eagle-import:JUMPII")
      (libsource (lib "eagle-import") (part "JUMPII@2"))
    )
    (comp (ref "J389")
      (value "JUMPII")
      (footprint "eagle-import:JUMPII")
      (libsource (lib "eagle-import") (part "JUMPII@2"))
    )
    (comp (ref "J390")
      (value "JUMPII")
      (footprint "eagle-import:JUMPII")
      (libsource (lib "eagle-import") (part "JUMPII@2"))
    )
    (comp (ref "J391")
      (value "JUMPII")
      (footprint "eagle-import:JUMPII")
      (libsource (lib "eagle-import") (part "JUMPII@2"))
    )
    (comp (ref "J392")
      (value "JUMPII")
      (footprint "eagle-import:JUMPII")
      (libsource (lib "eagle-import") (part "JUMPII@2"))
    )
    (comp (ref "J393")
      (value "JUMPII")
      (footprint "eagle-import:JUMPII")
      (libsource (lib "eagle-import") (part "JUMPII@2"))
    )
    (comp (ref "J394")
      (value "JUMPII")
      (footprint "eagle-import:JUMPII")
      (libsource (lib "eagle-import") (part "JUMPII@2"))
    )
    (comp (ref "J395")
      (value "JUMPII")
      (footprint "eagle-import:JUMPII")
      (libsource (lib "eagle-import") (part "JUMPII@2"))
    )
    (comp (ref "J396")
      (value "JUMPII")
      (footprint "eagle-import:JUMPII")
      (libsource (lib "eagle-import") (part "JUMPII@2"))
    )
    (comp (ref "J397")
      (value "JUMPII")
      (footprint "eagle-import:JUMPII")
      (libsource (lib "eagle-import") (part "JUMPII@2"))
    )
    (comp (ref "J398")
      (value "JUMPII")
      (footprint "eagle-import:JUMPII")
      (libsource (lib "eagle-import") (part "JUMPII@2"))
    )
    (comp (ref "J399")
      (value "JUMPII")
      (footprint "eagle-import:JUMPII")
      (libsource (lib "eagle-import") (part "JUMPII@2"))
    )
    (comp (ref "J400")
      (value "JUMPII")
      (footprint "eagle-import:JUMPII")
      (libsource (lib "eagle-import") (part "JUMPII@2"))
    )
    (comp (ref "J401")
      (value "JUMPII")
      (footprint "eagle-import:JUMPII")
      (libsource (lib "eagle-import") (part "JUMPII@2"))
    )
    (comp (ref "J402")
      (value "JUMPII")
      (footprint "eagle-import:JUMPII")
      (libsource (lib "eagle-import") (part "JUMPII@2"))
    )
    (comp (ref "J403")
      (value "JUMPII")
      (footprint "eagle-import:JUMPII")
      (libsource (lib "eagle-import") (part "JUMPII@2"))
    )
    (comp (ref "J404")
      (value "JUMPII")
      (footprint "eagle-import:JUMPII")
      (libsource (lib "eagle-import") (part "JUMPII@2"))
    )
    (comp (ref "J405")
      (value "JUMPII")
      (footprint "eagle-import:JUMPII")
      (libsource (lib "eagle-import") (part "JUMPII@2"))
    )
    (comp (ref "J406")
      (value "JUMPII")
      (footprint "eagle-import:JUMPII")
      (libsource (lib "eagle-import") (part "JUMPII@2"))
    )
    (comp (ref "J407")
      (value "JUMPII")
      (footprint "eagle-import:JUMPII")
      (libsource (lib "eagle-import") (part "JUMPII@2"))
    )
    (comp (ref "J408")
      (value "JUMPII")
      (footprint "eagle-import:JUMPII")
      (libsource (lib "eagle-import") (part "JUMPII@2"))
    )
    (comp (ref "J409")
      (value "JUMPII")
      (footprint "eagle-import:JUMPII")
      (libsource (lib "eagle-import") (part "JUMPII@2"))
    )
    (comp (ref "J410")
      (value "JUMPII")
      (footprint "eagle-import:JUMPII")
      (libsource (lib "eagle-import") (part "JUMPII@2"))
    )
    (comp (ref "J411")
      (value "JUMPII")
      (footprint "eagle-import:JUMPII")
      (libsource (lib "eagle-import") (part "JUMPII@2"))
    )
    (comp (ref "J412")
      (value "JUMPII")
      (footprint "eagle-import:JUMPII")
      (libsource (lib "eagle-import") (part "JUMPII@2"))
    )
    (comp (ref "J413")
      (value "JUMPII")
      (footprint "eagle-import:JUMPII")
      (libsource (lib "eagle-import") (part "JUMPII@2"))
    )
    (comp (ref "J414")
      (value "JUMPII")
      (footprint "eagle-import:JUMPII")
      (libsource (lib "eagle-import") (part "JUMPII@2"))
    )
    (comp (ref "J415")
      (value "JUMPII")
      (footprint "eagle-import:JUMPII")
      (libsource (lib "eagle-import") (part "JUMPII@2"))
    )
    (comp (ref "J416")
      (value "JUMPII")
      (footprint "eagle-import:JUMPII")
      (libsource (lib "eagle-import") (part "JUMPII@2"))
    )
    (comp (ref "R15")
      (value "390")
      (footprint "eagle-import:0204")
      (libsource (lib "eagle-import") (part "RESEU-7,5"))
    )
    (comp (ref "R16")
      (value "390")
      (footprint "eagle-import:0204")
      (libsource (lib "eagle-import") (part "RESEU-7,5"))
    )
    (comp (ref "T365")
      (value "BC857")
      (footprint "eagle-import:SOT-23")
      (libsource (lib "eagle-import") (part "BC557"))
    )
    (comp (ref "T366")
      (value "BC847")
      (footprint "eagle-import:SOT-23")
      (libsource (lib "eagle-import") (part "BC547"))
    )
    (comp (ref "T367")
      (value "BC857")
      (footprint "eagle-import:SOT-23")
      (libsource (lib "eagle-import") (part "BC557"))
    )
    (comp (ref "T368")
      (value "BC857")
      (footprint "eagle-import:SOT-23")
      (libsource (lib "eagle-import") (part "BC557"))
    )
    (comp (ref "T369")
      (value "BC857")
      (footprint "eagle-import:SOT-23")
      (libsource (lib "eagle-import") (part "BC557"))
    )
    (comp (ref "T370")
      (value "BC857")
      (footprint "eagle-import:SOT-23")
      (libsource (lib "eagle-import") (part "BC557"))
    )
    (comp (ref "T371")
      (value "BC857")
      (footprint "eagle-import:SOT-23")
      (libsource (lib "eagle-import") (part "BC557"))
    )
    (comp (ref "T372")
      (value "BC857")
      (footprint "eagle-import:SOT-23")
      (libsource (lib "eagle-import") (part "BC557"))
    )
    (comp (ref "T373")
      (value "BC857")
      (footprint "eagle-import:SOT-23")
      (libsource (lib "eagle-import") (part "BC557"))
    )
    (comp (ref "T374")
      (value "BC857")
      (footprint "eagle-import:SOT-23")
      (libsource (lib "eagle-import") (part "BC557"))
    )
    (comp (ref "T375")
      (value "BC857")
      (footprint "eagle-import:SOT-23")
      (libsource (lib "eagle-import") (part "BC557"))
    )
    (comp (ref "T376")
      (value "BC857")
      (footprint "eagle-import:SOT-23")
      (libsource (lib "eagle-import") (part "BC557"))
    )
    (comp (ref "T377")
      (value "BC857")
      (footprint "eagle-import:SOT-23")
      (libsource (lib "eagle-import") (part "BC557"))
    )
    (comp (ref "T378")
      (value "BC857")
      (footprint "eagle-import:SOT-23")
      (libsource (lib "eagle-import") (part "BC557"))
    )
    (comp (ref "T379")
      (value "BC857")
      (footprint "eagle-import:SOT-23")
      (libsource (lib "eagle-import") (part "BC557"))
    )
    (comp (ref "T380")
      (value "BC857")
      (footprint "eagle-import:SOT-23")
      (libsource (lib "eagle-import") (part "BC557"))
    )
    (comp (ref "T381")
      (value "BC857")
      (footprint "eagle-import:SOT-23")
      (libsource (lib "eagle-import") (part "BC557"))
    )
    (comp (ref "T382")
      (value "BC847")
      (footprint "eagle-import:SOT-23")
      (libsource (lib "eagle-import") (part "BC547"))
    )
    (comp (ref "T383")
      (value "BC847")
      (footprint "eagle-import:SOT-23")
      (libsource (lib "eagle-import") (part "BC547"))
    )
    (comp (ref "T384")
      (value "BC847")
      (footprint "eagle-import:SOT-23")
      (libsource (lib "eagle-import") (part "BC547"))
    )
    (comp (ref "T385")
      (value "BC847")
      (footprint "eagle-import:SOT-23")
      (libsource (lib "eagle-import") (part "BC547"))
    )
    (comp (ref "T386")
      (value "BC847")
      (footprint "eagle-import:SOT-23")
      (libsource (lib "eagle-import") (part "BC547"))
    )
    (comp (ref "T387")
      (value "BC847")
      (footprint "eagle-import:SOT-23")
      (libsource (lib "eagle-import") (part "BC547"))
    )
    (comp (ref "T388")
      (value "BC847")
      (footprint "eagle-import:SOT-23")
      (libsource (lib "eagle-import") (part "BC547"))
    )
    (comp (ref "T389")
      (value "BC847")
      (footprint "eagle-import:SOT-23")
      (libsource (lib "eagle-import") (part "BC547"))
    )
    (comp (ref "T390")
      (value "BC847")
      (footprint "eagle-import:SOT-23")
      (libsource (lib "eagle-import") (part "BC547"))
    )
    (comp (ref "T391")
      (value "BC857")
      (footprint "eagle-import:SOT-23")
      (libsource (lib "eagle-import") (part "BC557"))
    )
    (comp (ref "T392")
      (value "BC847")
      (footprint "eagle-import:SOT-23")
      (libsource (lib "eagle-import") (part "BC547"))
    )
    (comp (ref "T393")
      (value "BC857")
      (footprint "eagle-import:SOT-23")
      (libsource (lib "eagle-import") (part "BC557"))
    )
    (comp (ref "T394")
      (value "BC857")
      (footprint "eagle-import:SOT-23")
      (libsource (lib "eagle-import") (part "BC557"))
    )
    (comp (ref "T395")
      (value "BC857")
      (footprint "eagle-import:SOT-23")
      (libsource (lib "eagle-import") (part "BC557"))
    )
    (comp (ref "T396")
      (value "BC857")
      (footprint "eagle-import:SOT-23")
      (libsource (lib "eagle-import") (part "BC557"))
    )
    (comp (ref "T397")
      (value "BC857")
      (footprint "eagle-import:SOT-23")
      (libsource (lib "eagle-import") (part "BC557"))
    )
    (comp (ref "T398")
      (value "BC857")
      (footprint "eagle-import:SOT-23")
      (libsource (lib "eagle-import") (part "BC557"))
    )
    (comp (ref "T399")
      (value "BC857")
      (footprint "eagle-import:SOT-23")
      (libsource (lib "eagle-import") (part "BC557"))
    )
    (comp (ref "T400")
      (value "BC857")
      (footprint "eagle-import:SOT-23")
      (libsource (lib "eagle-import") (part "BC557"))
    )
    (comp (ref "T401")
      (value "BC857")
      (footprint "eagle-import:SOT-23")
      (libsource (lib "eagle-import") (part "BC557"))
    )
    (comp (ref "T402")
      (value "BC857")
      (footprint "eagle-import:SOT-23")
      (libsource (lib "eagle-import") (part "BC557"))
    )
    (comp (ref "T403")
      (value "BC857")
      (footprint "eagle-import:SOT-23")
      (libsource (lib "eagle-import") (part "BC557"))
    )
    (comp (ref "T404")
      (value "BC857")
      (footprint "eagle-import:SOT-23")
      (libsource (lib "eagle-import") (part "BC557"))
    )
    (comp (ref "T405")
      (value "BC857")
      (footprint "eagle-import:SOT-23")
      (libsource (lib "eagle-import") (part "BC557"))
    )
    (comp (ref "T406")
      (value "BC857")
      (footprint "eagle-import:SOT-23")
      (libsource (lib "eagle-import") (part "BC557"))
    )
    (comp (ref "T407")
      (value "BC857")
      (footprint "eagle-import:SOT-23")
      (libsource (lib "eagle-import") (part "BC557"))
    )
    (comp (ref "T408")
      (value "BC847")
      (footprint "eagle-import:SOT-23")
      (libsource (lib "eagle-import") (part "BC547"))
    )
    (comp (ref "T409")
      (value "BC847")
      (footprint "eagle-import:SOT-23")
      (libsource (lib "eagle-import") (part "BC547"))
    )
    (comp (ref "T410")
      (value "BC847")
      (footprint "eagle-import:SOT-23")
      (libsource (lib "eagle-import") (part "BC547"))
    )
    (comp (ref "T411")
      (value "BC847")
      (footprint "eagle-import:SOT-23")
      (libsource (lib "eagle-import") (part "BC547"))
    )
    (comp (ref "T412")
      (value "BC847")
      (footprint "eagle-import:SOT-23")
      (libsource (lib "eagle-import") (part "BC547"))
    )
    (comp (ref "T413")
      (value "BC847")
      (footprint "eagle-import:SOT-23")
      (libsource (lib "eagle-import") (part "BC547"))
    )
    (comp (ref "T414")
      (value "BC847")
      (footprint "eagle-import:SOT-23")
      (libsource (lib "eagle-import") (part "BC547"))
    )
    (comp (ref "T415")
      (value "BC847")
      (footprint "eagle-import:SOT-23")
      (libsource (lib "eagle-import") (part "BC547"))
    )
    (comp (ref "T416")
      (value "BC847")
      (footprint "eagle-import:SOT-23")
      (libsource (lib "eagle-import") (part "BC547"))
    )
    (comp (ref "C13")
      (value "100n")
      (footprint "eagle-import:0204")
      (libsource (lib "eagle-import") (part "CAPNP-5"))
    )
    (comp (ref "C14")
      (value "100n")
      (footprint "eagle-import:0204")
      (libsource (lib "eagle-import") (part "CAPNP-5"))
    )
    (comp (ref "J313")
      (value "JUMPII")
      (footprint "eagle-import:JUMPII")
      (libsource (lib "eagle-import") (part "JUMPII@2"))
    )
    (comp (ref "J314")
      (value "JUMPII")
      (footprint "eagle-import:JUMPII")
      (libsource (lib "eagle-import") (part "JUMPII@2"))
    )
    (comp (ref "J315")
      (value "JUMPII")
      (footprint "eagle-import:JUMPII")
      (libsource (lib "eagle-import") (part "JUMPII@2"))
    )
    (comp (ref "J316")
      (value "JUMPII")
      (footprint "eagle-import:JUMPII")
      (libsource (lib "eagle-import") (part "JUMPII@2"))
    )
    (comp (ref "J317")
      (value "JUMPII")
      (footprint "eagle-import:JUMPII")
      (libsource (lib "eagle-import") (part "JUMPII@2"))
    )
    (comp (ref "J318")
      (value "JUMPII")
      (footprint "eagle-import:JUMPII")
      (libsource (lib "eagle-import") (part "JUMPII@2"))
    )
    (comp (ref "J319")
      (value "JUMPII")
      (footprint "eagle-import:JUMPII")
      (libsource (lib "eagle-import") (part "JUMPII@2"))
    )
    (comp (ref "J320")
      (value "JUMPII")
      (footprint "eagle-import:JUMPII")
      (libsource (lib "eagle-import") (part "JUMPII@2"))
    )
    (comp (ref "J321")
      (value "JUMPII")
      (footprint "eagle-import:JUMPII")
      (libsource (lib "eagle-import") (part "JUMPII@2"))
    )
    (comp (ref "J322")
      (value "JUMPII")
      (footprint "eagle-import:JUMPII")
      (libsource (lib "eagle-import") (part "JUMPII@2"))
    )
    (comp (ref "J323")
      (value "JUMPII")
      (footprint "eagle-import:JUMPII")
      (libsource (lib "eagle-import") (part "JUMPII@2"))
    )
    (comp (ref "J324")
      (value "JUMPII")
      (footprint "eagle-import:JUMPII")
      (libsource (lib "eagle-import") (part "JUMPII@2"))
    )
    (comp (ref "J325")
      (value "JUMPII")
      (footprint "eagle-import:JUMPII")
      (libsource (lib "eagle-import") (part "JUMPII@2"))
    )
    (comp (ref "J326")
      (value "JUMPII")
      (footprint "eagle-import:JUMPII")
      (libsource (lib "eagle-import") (part "JUMPII@2"))
    )
    (comp (ref "J327")
      (value "JUMPII")
      (footprint "eagle-import:JUMPII")
      (libsource (lib "eagle-import") (part "JUMPII@2"))
    )
    (comp (ref "J328")
      (value "JUMPII")
      (footprint "eagle-import:JUMPII")
      (libsource (lib "eagle-import") (part "JUMPII@2"))
    )
    (comp (ref "J329")
      (value "JUMPII")
      (footprint "eagle-import:JUMPII")
      (libsource (lib "eagle-import") (part "JUMPII@2"))
    )
    (comp (ref "J330")
      (value "JUMPII")
      (footprint "eagle-import:JUMPII")
      (libsource (lib "eagle-import") (part "JUMPII@2"))
    )
    (comp (ref "J331")
      (value "JUMPII")
      (footprint "eagle-import:JUMPII")
      (libsource (lib "eagle-import") (part "JUMPII@2"))
    )
    (comp (ref "J332")
      (value "JUMPII")
      (footprint "eagle-import:JUMPII")
      (libsource (lib "eagle-import") (part "JUMPII@2"))
    )
    (comp (ref "J333")
      (value "JUMPII")
      (footprint "eagle-import:JUMPII")
      (libsource (lib "eagle-import") (part "JUMPII@2"))
    )
    (comp (ref "J334")
      (value "JUMPII")
      (footprint "eagle-import:JUMPII")
      (libsource (lib "eagle-import") (part "JUMPII@2"))
    )
    (comp (ref "J335")
      (value "JUMPII")
      (footprint "eagle-import:JUMPII")
      (libsource (lib "eagle-import") (part "JUMPII@2"))
    )
    (comp (ref "J336")
      (value "JUMPII")
      (footprint "eagle-import:JUMPII")
      (libsource (lib "eagle-import") (part "JUMPII@2"))
    )
    (comp (ref "J337")
      (value "JUMPII")
      (footprint "eagle-import:JUMPII")
      (libsource (lib "eagle-import") (part "JUMPII@2"))
    )
    (comp (ref "J338")
      (value "JUMPII")
      (footprint "eagle-import:JUMPII")
      (libsource (lib "eagle-import") (part "JUMPII@2"))
    )
    (comp (ref "J339")
      (value "JUMPII")
      (footprint "eagle-import:JUMPII")
      (libsource (lib "eagle-import") (part "JUMPII@2"))
    )
    (comp (ref "J340")
      (value "JUMPII")
      (footprint "eagle-import:JUMPII")
      (libsource (lib "eagle-import") (part "JUMPII@2"))
    )
    (comp (ref "J341")
      (value "JUMPII")
      (footprint "eagle-import:JUMPII")
      (libsource (lib "eagle-import") (part "JUMPII@2"))
    )
    (comp (ref "J342")
      (value "JUMPII")
      (footprint "eagle-import:JUMPII")
      (libsource (lib "eagle-import") (part "JUMPII@2"))
    )
    (comp (ref "J343")
      (value "JUMPII")
      (footprint "eagle-import:JUMPII")
      (libsource (lib "eagle-import") (part "JUMPII@2"))
    )
    (comp (ref "J344")
      (value "JUMPII")
      (footprint "eagle-import:JUMPII")
      (libsource (lib "eagle-import") (part "JUMPII@2"))
    )
    (comp (ref "J345")
      (value "JUMPII")
      (footprint "eagle-import:JUMPII")
      (libsource (lib "eagle-import") (part "JUMPII@2"))
    )
    (comp (ref "J346")
      (value "JUMPII")
      (footprint "eagle-import:JUMPII")
      (libsource (lib "eagle-import") (part "JUMPII@2"))
    )
    (comp (ref "J347")
      (value "JUMPII")
      (footprint "eagle-import:JUMPII")
      (libsource (lib "eagle-import") (part "JUMPII@2"))
    )
    (comp (ref "J348")
      (value "JUMPII")
      (footprint "eagle-import:JUMPII")
      (libsource (lib "eagle-import") (part "JUMPII@2"))
    )
    (comp (ref "J349")
      (value "JUMPII")
      (footprint "eagle-import:JUMPII")
      (libsource (lib "eagle-import") (part "JUMPII@2"))
    )
    (comp (ref "J350")
      (value "JUMPII")
      (footprint "eagle-import:JUMPII")
      (libsource (lib "eagle-import") (part "JUMPII@2"))
    )
    (comp (ref "J351")
      (value "JUMPII")
      (footprint "eagle-import:JUMPII")
      (libsource (lib "eagle-import") (part "JUMPII@2"))
    )
    (comp (ref "J352")
      (value "JUMPII")
      (footprint "eagle-import:JUMPII")
      (libsource (lib "eagle-import") (part "JUMPII@2"))
    )
    (comp (ref "J353")
      (value "JUMPII")
      (footprint "eagle-import:JUMPII")
      (libsource (lib "eagle-import") (part "JUMPII@2"))
    )
    (comp (ref "J354")
      (value "JUMPII")
      (footprint "eagle-import:JUMPII")
      (libsource (lib "eagle-import") (part "JUMPII@2"))
    )
    (comp (ref "J355")
      (value "JUMPII")
      (footprint "eagle-import:JUMPII")
      (libsource (lib "eagle-import") (part "JUMPII@2"))
    )
    (comp (ref "J356")
      (value "JUMPII")
      (footprint "eagle-import:JUMPII")
      (libsource (lib "eagle-import") (part "JUMPII@2"))
    )
    (comp (ref "J357")
      (value "JUMPII")
      (footprint "eagle-import:JUMPII")
      (libsource (lib "eagle-import") (part "JUMPII@2"))
    )
    (comp (ref "J358")
      (value "JUMPII")
      (footprint "eagle-import:JUMPII")
      (libsource (lib "eagle-import") (part "JUMPII@2"))
    )
    (comp (ref "J359")
      (value "JUMPII")
      (footprint "eagle-import:JUMPII")
      (libsource (lib "eagle-import") (part "JUMPII@2"))
    )
    (comp (ref "J360")
      (value "JUMPII")
      (footprint "eagle-import:JUMPII")
      (libsource (lib "eagle-import") (part "JUMPII@2"))
    )
    (comp (ref "J361")
      (value "JUMPII")
      (footprint "eagle-import:JUMPII")
      (libsource (lib "eagle-import") (part "JUMPII@2"))
    )
    (comp (ref "J362")
      (value "JUMPII")
      (footprint "eagle-import:JUMPII")
      (libsource (lib "eagle-import") (part "JUMPII@2"))
    )
    (comp (ref "J363")
      (value "JUMPII")
      (footprint "eagle-import:JUMPII")
      (libsource (lib "eagle-import") (part "JUMPII@2"))
    )
    (comp (ref "J364")
      (value "JUMPII")
      (footprint "eagle-import:JUMPII")
      (libsource (lib "eagle-import") (part "JUMPII@2"))
    )
    (comp (ref "R13")
      (value "390")
      (footprint "eagle-import:0204")
      (libsource (lib "eagle-import") (part "RESEU-7,5"))
    )
    (comp (ref "R14")
      (value "390")
      (footprint "eagle-import:0204")
      (libsource (lib "eagle-import") (part "RESEU-7,5"))
    )
    (comp (ref "T313")
      (value "BC857")
      (footprint "eagle-import:SOT-23")
      (libsource (lib "eagle-import") (part "BC557"))
    )
    (comp (ref "T314")
      (value "BC847")
      (footprint "eagle-import:SOT-23")
      (libsource (lib "eagle-import") (part "BC547"))
    )
    (comp (ref "T315")
      (value "BC857")
      (footprint "eagle-import:SOT-23")
      (libsource (lib "eagle-import") (part "BC557"))
    )
    (comp (ref "T316")
      (value "BC857")
      (footprint "eagle-import:SOT-23")
      (libsource (lib "eagle-import") (part "BC557"))
    )
    (comp (ref "T317")
      (value "BC857")
      (footprint "eagle-import:SOT-23")
      (libsource (lib "eagle-import") (part "BC557"))
    )
    (comp (ref "T318")
      (value "BC857")
      (footprint "eagle-import:SOT-23")
      (libsource (lib "eagle-import") (part "BC557"))
    )
    (comp (ref "T319")
      (value "BC857")
      (footprint "eagle-import:SOT-23")
      (libsource (lib "eagle-import") (part "BC557"))
    )
    (comp (ref "T320")
      (value "BC857")
      (footprint "eagle-import:SOT-23")
      (libsource (lib "eagle-import") (part "BC557"))
    )
    (comp (ref "T321")
      (value "BC857")
      (footprint "eagle-import:SOT-23")
      (libsource (lib "eagle-import") (part "BC557"))
    )
    (comp (ref "T322")
      (value "BC857")
      (footprint "eagle-import:SOT-23")
      (libsource (lib "eagle-import") (part "BC557"))
    )
    (comp (ref "T323")
      (value "BC857")
      (footprint "eagle-import:SOT-23")
      (libsource (lib "eagle-import") (part "BC557"))
    )
    (comp (ref "T324")
      (value "BC857")
      (footprint "eagle-import:SOT-23")
      (libsource (lib "eagle-import") (part "BC557"))
    )
    (comp (ref "T325")
      (value "BC857")
      (footprint "eagle-import:SOT-23")
      (libsource (lib "eagle-import") (part "BC557"))
    )
    (comp (ref "T326")
      (value "BC857")
      (footprint "eagle-import:SOT-23")
      (libsource (lib "eagle-import") (part "BC557"))
    )
    (comp (ref "T327")
      (value "BC857")
      (footprint "eagle-import:SOT-23")
      (libsource (lib "eagle-import") (part "BC557"))
    )
    (comp (ref "T328")
      (value "BC857")
      (footprint "eagle-import:SOT-23")
      (libsource (lib "eagle-import") (part "BC557"))
    )
    (comp (ref "T329")
      (value "BC857")
      (footprint "eagle-import:SOT-23")
      (libsource (lib "eagle-import") (part "BC557"))
    )
    (comp (ref "T330")
      (value "BC847")
      (footprint "eagle-import:SOT-23")
      (libsource (lib "eagle-import") (part "BC547"))
    )
    (comp (ref "T331")
      (value "BC847")
      (footprint "eagle-import:SOT-23")
      (libsource (lib "eagle-import") (part "BC547"))
    )
    (comp (ref "T332")
      (value "BC847")
      (footprint "eagle-import:SOT-23")
      (libsource (lib "eagle-import") (part "BC547"))
    )
    (comp (ref "T333")
      (value "BC847")
      (footprint "eagle-import:SOT-23")
      (libsource (lib "eagle-import") (part "BC547"))
    )
    (comp (ref "T334")
      (value "BC847")
      (footprint "eagle-import:SOT-23")
      (libsource (lib "eagle-import") (part "BC547"))
    )
    (comp (ref "T335")
      (value "BC847")
      (footprint "eagle-import:SOT-23")
      (libsource (lib "eagle-import") (part "BC547"))
    )
    (comp (ref "T336")
      (value "BC847")
      (footprint "eagle-import:SOT-23")
      (libsource (lib "eagle-import") (part "BC547"))
    )
    (comp (ref "T337")
      (value "BC847")
      (footprint "eagle-import:SOT-23")
      (libsource (lib "eagle-import") (part "BC547"))
    )
    (comp (ref "T338")
      (value "BC847")
      (footprint "eagle-import:SOT-23")
      (libsource (lib "eagle-import") (part "BC547"))
    )
    (comp (ref "T339")
      (value "BC857")
      (footprint "eagle-import:SOT-23")
      (libsource (lib "eagle-import") (part "BC557"))
    )
    (comp (ref "T340")
      (value "BC847")
      (footprint "eagle-import:SOT-23")
      (libsource (lib "eagle-import") (part "BC547"))
    )
    (comp (ref "T341")
      (value "BC857")
      (footprint "eagle-import:SOT-23")
      (libsource (lib "eagle-import") (part "BC557"))
    )
    (comp (ref "T342")
      (value "BC857")
      (footprint "eagle-import:SOT-23")
      (libsource (lib "eagle-import") (part "BC557"))
    )
    (comp (ref "T343")
      (value "BC857")
      (footprint "eagle-import:SOT-23")
      (libsource (lib "eagle-import") (part "BC557"))
    )
    (comp (ref "T344")
      (value "BC857")
      (footprint "eagle-import:SOT-23")
      (libsource (lib "eagle-import") (part "BC557"))
    )
    (comp (ref "T345")
      (value "BC857")
      (footprint "eagle-import:SOT-23")
      (libsource (lib "eagle-import") (part "BC557"))
    )
    (comp (ref "T346")
      (value "BC857")
      (footprint "eagle-import:SOT-23")
      (libsource (lib "eagle-import") (part "BC557"))
    )
    (comp (ref "T347")
      (value "BC857")
      (footprint "eagle-import:SOT-23")
      (libsource (lib "eagle-import") (part "BC557"))
    )
    (comp (ref "T348")
      (value "BC857")
      (footprint "eagle-import:SOT-23")
      (libsource (lib "eagle-import") (part "BC557"))
    )
    (comp (ref "T349")
      (value "BC857")
      (footprint "eagle-import:SOT-23")
      (libsource (lib "eagle-import") (part "BC557"))
    )
    (comp (ref "T350")
      (value "BC857")
      (footprint "eagle-import:SOT-23")
      (libsource (lib "eagle-import") (part "BC557"))
    )
    (comp (ref "T351")
      (value "BC857")
      (footprint "eagle-import:SOT-23")
      (libsource (lib "eagle-import") (part "BC557"))
    )
    (comp (ref "T352")
      (value "BC857")
      (footprint "eagle-import:SOT-23")
      (libsource (lib "eagle-import") (part "BC557"))
    )
    (comp (ref "T353")
      (value "BC857")
      (footprint "eagle-import:SOT-23")
      (libsource (lib "eagle-import") (part "BC557"))
    )
    (comp (ref "T354")
      (value "BC857")
      (footprint "eagle-import:SOT-23")
      (libsource (lib "eagle-import") (part "BC557"))
    )
    (comp (ref "T355")
      (value "BC857")
      (footprint "eagle-import:SOT-23")
      (libsource (lib "eagle-import") (part "BC557"))
    )
    (comp (ref "T356")
      (value "BC847")
      (footprint "eagle-import:SOT-23")
      (libsource (lib "eagle-import") (part "BC547"))
    )
    (comp (ref "T357")
      (value "BC847")
      (footprint "eagle-import:SOT-23")
      (libsource (lib "eagle-import") (part "BC547"))
    )
    (comp (ref "T358")
      (value "BC847")
      (footprint "eagle-import:SOT-23")
      (libsource (lib "eagle-import") (part "BC547"))
    )
    (comp (ref "T359")
      (value "BC847")
      (footprint "eagle-import:SOT-23")
      (libsource (lib "eagle-import") (part "BC547"))
    )
    (comp (ref "T360")
      (value "BC847")
      (footprint "eagle-import:SOT-23")
      (libsource (lib "eagle-import") (part "BC547"))
    )
    (comp (ref "T361")
      (value "BC847")
      (footprint "eagle-import:SOT-23")
      (libsource (lib "eagle-import") (part "BC547"))
    )
    (comp (ref "T362")
      (value "BC847")
      (footprint "eagle-import:SOT-23")
      (libsource (lib "eagle-import") (part "BC547"))
    )
    (comp (ref "T363")
      (value "BC847")
      (footprint "eagle-import:SOT-23")
      (libsource (lib "eagle-import") (part "BC547"))
    )
    (comp (ref "T364")
      (value "BC847")
      (footprint "eagle-import:SOT-23")
      (libsource (lib "eagle-import") (part "BC547"))
    )
    (comp (ref "C11")
      (value "100n")
      (footprint "eagle-import:0204")
      (libsource (lib "eagle-import") (part "CAPNP-5"))
    )
    (comp (ref "C12")
      (value "100n")
      (footprint "eagle-import:0204")
      (libsource (lib "eagle-import") (part "CAPNP-5"))
    )
    (comp (ref "J261")
      (value "JUMPII")
      (footprint "eagle-import:JUMPII")
      (libsource (lib "eagle-import") (part "JUMPII@2"))
    )
    (comp (ref "J262")
      (value "JUMPII")
      (footprint "eagle-import:JUMPII")
      (libsource (lib "eagle-import") (part "JUMPII@2"))
    )
    (comp (ref "J263")
      (value "JUMPII")
      (footprint "eagle-import:JUMPII")
      (libsource (lib "eagle-import") (part "JUMPII@2"))
    )
    (comp (ref "J264")
      (value "JUMPII")
      (footprint "eagle-import:JUMPII")
      (libsource (lib "eagle-import") (part "JUMPII@2"))
    )
    (comp (ref "J265")
      (value "JUMPII")
      (footprint "eagle-import:JUMPII")
      (libsource (lib "eagle-import") (part "JUMPII@2"))
    )
    (comp (ref "J266")
      (value "JUMPII")
      (footprint "eagle-import:JUMPII")
      (libsource (lib "eagle-import") (part "JUMPII@2"))
    )
    (comp (ref "J267")
      (value "JUMPII")
      (footprint "eagle-import:JUMPII")
      (libsource (lib "eagle-import") (part "JUMPII@2"))
    )
    (comp (ref "J268")
      (value "JUMPII")
      (footprint "eagle-import:JUMPII")
      (libsource (lib "eagle-import") (part "JUMPII@2"))
    )
    (comp (ref "J269")
      (value "JUMPII")
      (footprint "eagle-import:JUMPII")
      (libsource (lib "eagle-import") (part "JUMPII@2"))
    )
    (comp (ref "J270")
      (value "JUMPII")
      (footprint "eagle-import:JUMPII")
      (libsource (lib "eagle-import") (part "JUMPII@2"))
    )
    (comp (ref "J271")
      (value "JUMPII")
      (footprint "eagle-import:JUMPII")
      (libsource (lib "eagle-import") (part "JUMPII@2"))
    )
    (comp (ref "J272")
      (value "JUMPII")
      (footprint "eagle-import:JUMPII")
      (libsource (lib "eagle-import") (part "JUMPII@2"))
    )
    (comp (ref "J273")
      (value "JUMPII")
      (footprint "eagle-import:JUMPII")
      (libsource (lib "eagle-import") (part "JUMPII@2"))
    )
    (comp (ref "J274")
      (value "JUMPII")
      (footprint "eagle-import:JUMPII")
      (libsource (lib "eagle-import") (part "JUMPII@2"))
    )
    (comp (ref "J275")
      (value "JUMPII")
      (footprint "eagle-import:JUMPII")
      (libsource (lib "eagle-import") (part "JUMPII@2"))
    )
    (comp (ref "J276")
      (value "JUMPII")
      (footprint "eagle-import:JUMPII")
      (libsource (lib "eagle-import") (part "JUMPII@2"))
    )
    (comp (ref "J277")
      (value "JUMPII")
      (footprint "eagle-import:JUMPII")
      (libsource (lib "eagle-import") (part "JUMPII@2"))
    )
    (comp (ref "J278")
      (value "JUMPII")
      (footprint "eagle-import:JUMPII")
      (libsource (lib "eagle-import") (part "JUMPII@2"))
    )
    (comp (ref "J279")
      (value "JUMPII")
      (footprint "eagle-import:JUMPII")
      (libsource (lib "eagle-import") (part "JUMPII@2"))
    )
    (comp (ref "J280")
      (value "JUMPII")
      (footprint "eagle-import:JUMPII")
      (libsource (lib "eagle-import") (part "JUMPII@2"))
    )
    (comp (ref "J281")
      (value "JUMPII")
      (footprint "eagle-import:JUMPII")
      (libsource (lib "eagle-import") (part "JUMPII@2"))
    )
    (comp (ref "J282")
      (value "JUMPII")
      (footprint "eagle-import:JUMPII")
      (libsource (lib "eagle-import") (part "JUMPII@2"))
    )
    (comp (ref "J283")
      (value "JUMPII")
      (footprint "eagle-import:JUMPII")
      (libsource (lib "eagle-import") (part "JUMPII@2"))
    )
    (comp (ref "J284")
      (value "JUMPII")
      (footprint "eagle-import:JUMPII")
      (libsource (lib "eagle-import") (part "JUMPII@2"))
    )
    (comp (ref "J285")
      (value "JUMPII")
      (footprint "eagle-import:JUMPII")
      (libsource (lib "eagle-import") (part "JUMPII@2"))
    )
    (comp (ref "J286")
      (value "JUMPII")
      (footprint "eagle-import:JUMPII")
      (libsource (lib "eagle-import") (part "JUMPII@2"))
    )
    (comp (ref "J287")
      (value "JUMPII")
      (footprint "eagle-import:JUMPII")
      (libsource (lib "eagle-import") (part "JUMPII@2"))
    )
    (comp (ref "J288")
      (value "JUMPII")
      (footprint "eagle-import:JUMPII")
      (libsource (lib "eagle-import") (part "JUMPII@2"))
    )
    (comp (ref "J289")
      (value "JUMPII")
      (footprint "eagle-import:JUMPII")
      (libsource (lib "eagle-import") (part "JUMPII@2"))
    )
    (comp (ref "J290")
      (value "JUMPII")
      (footprint "eagle-import:JUMPII")
      (libsource (lib "eagle-import") (part "JUMPII@2"))
    )
    (comp (ref "J291")
      (value "JUMPII")
      (footprint "eagle-import:JUMPII")
      (libsource (lib "eagle-import") (part "JUMPII@2"))
    )
    (comp (ref "J292")
      (value "JUMPII")
      (footprint "eagle-import:JUMPII")
      (libsource (lib "eagle-import") (part "JUMPII@2"))
    )
    (comp (ref "J293")
      (value "JUMPII")
      (footprint "eagle-import:JUMPII")
      (libsource (lib "eagle-import") (part "JUMPII@2"))
    )
    (comp (ref "J294")
      (value "JUMPII")
      (footprint "eagle-import:JUMPII")
      (libsource (lib "eagle-import") (part "JUMPII@2"))
    )
    (comp (ref "J295")
      (value "JUMPII")
      (footprint "eagle-import:JUMPII")
      (libsource (lib "eagle-import") (part "JUMPII@2"))
    )
    (comp (ref "J296")
      (value "JUMPII")
      (footprint "eagle-import:JUMPII")
      (libsource (lib "eagle-import") (part "JUMPII@2"))
    )
    (comp (ref "J297")
      (value "JUMPII")
      (footprint "eagle-import:JUMPII")
      (libsource (lib "eagle-import") (part "JUMPII@2"))
    )
    (comp (ref "J298")
      (value "JUMPII")
      (footprint "eagle-import:JUMPII")
      (libsource (lib "eagle-import") (part "JUMPII@2"))
    )
    (comp (ref "J299")
      (value "JUMPII")
      (footprint "eagle-import:JUMPII")
      (libsource (lib "eagle-import") (part "JUMPII@2"))
    )
    (comp (ref "J300")
      (value "JUMPII")
      (footprint "eagle-import:JUMPII")
      (libsource (lib "eagle-import") (part "JUMPII@2"))
    )
    (comp (ref "J301")
      (value "JUMPII")
      (footprint "eagle-import:JUMPII")
      (libsource (lib "eagle-import") (part "JUMPII@2"))
    )
    (comp (ref "J302")
      (value "JUMPII")
      (footprint "eagle-import:JUMPII")
      (libsource (lib "eagle-import") (part "JUMPII@2"))
    )
    (comp (ref "J303")
      (value "JUMPII")
      (footprint "eagle-import:JUMPII")
      (libsource (lib "eagle-import") (part "JUMPII@2"))
    )
    (comp (ref "J304")
      (value "JUMPII")
      (footprint "eagle-import:JUMPII")
      (libsource (lib "eagle-import") (part "JUMPII@2"))
    )
    (comp (ref "J305")
      (value "JUMPII")
      (footprint "eagle-import:JUMPII")
      (libsource (lib "eagle-import") (part "JUMPII@2"))
    )
    (comp (ref "J306")
      (value "JUMPII")
      (footprint "eagle-import:JUMPII")
      (libsource (lib "eagle-import") (part "JUMPII@2"))
    )
    (comp (ref "J307")
      (value "JUMPII")
      (footprint "eagle-import:JUMPII")
      (libsource (lib "eagle-import") (part "JUMPII@2"))
    )
    (comp (ref "J308")
      (value "JUMPII")
      (footprint "eagle-import:JUMPII")
      (libsource (lib "eagle-import") (part "JUMPII@2"))
    )
    (comp (ref "J309")
      (value "JUMPII")
      (footprint "eagle-import:JUMPII")
      (libsource (lib "eagle-import") (part "JUMPII@2"))
    )
    (comp (ref "J310")
      (value "JUMPII")
      (footprint "eagle-import:JUMPII")
      (libsource (lib "eagle-import") (part "JUMPII@2"))
    )
    (comp (ref "J311")
      (value "JUMPII")
      (footprint "eagle-import:JUMPII")
      (libsource (lib "eagle-import") (part "JUMPII@2"))
    )
    (comp (ref "J312")
      (value "JUMPII")
      (footprint "eagle-import:JUMPII")
      (libsource (lib "eagle-import") (part "JUMPII@2"))
    )
    (comp (ref "R11")
      (value "390")
      (footprint "eagle-import:0204")
      (libsource (lib "eagle-import") (part "RESEU-7,5"))
    )
    (comp (ref "R12")
      (value "390")
      (footprint "eagle-import:0204")
      (libsource (lib "eagle-import") (part "RESEU-7,5"))
    )
    (comp (ref "T261")
      (value "BC857")
      (footprint "eagle-import:SOT-23")
      (libsource (lib "eagle-import") (part "BC557"))
    )
    (comp (ref "T262")
      (value "BC847")
      (footprint "eagle-import:SOT-23")
      (libsource (lib "eagle-import") (part "BC547"))
    )
    (comp (ref "T263")
      (value "BC857")
      (footprint "eagle-import:SOT-23")
      (libsource (lib "eagle-import") (part "BC557"))
    )
    (comp (ref "T264")
      (value "BC857")
      (footprint "eagle-import:SOT-23")
      (libsource (lib "eagle-import") (part "BC557"))
    )
    (comp (ref "T265")
      (value "BC857")
      (footprint "eagle-import:SOT-23")
      (libsource (lib "eagle-import") (part "BC557"))
    )
    (comp (ref "T266")
      (value "BC857")
      (footprint "eagle-import:SOT-23")
      (libsource (lib "eagle-import") (part "BC557"))
    )
    (comp (ref "T267")
      (value "BC857")
      (footprint "eagle-import:SOT-23")
      (libsource (lib "eagle-import") (part "BC557"))
    )
    (comp (ref "T268")
      (value "BC857")
      (footprint "eagle-import:SOT-23")
      (libsource (lib "eagle-import") (part "BC557"))
    )
    (comp (ref "T269")
      (value "BC857")
      (footprint "eagle-import:SOT-23")
      (libsource (lib "eagle-import") (part "BC557"))
    )
    (comp (ref "T270")
      (value "BC857")
      (footprint "eagle-import:SOT-23")
      (libsource (lib "eagle-import") (part "BC557"))
    )
    (comp (ref "T271")
      (value "BC857")
      (footprint "eagle-import:SOT-23")
      (libsource (lib "eagle-import") (part "BC557"))
    )
    (comp (ref "T272")
      (value "BC857")
      (footprint "eagle-import:SOT-23")
      (libsource (lib "eagle-import") (part "BC557"))
    )
    (comp (ref "T273")
      (value "BC857")
      (footprint "eagle-import:SOT-23")
      (libsource (lib "eagle-import") (part "BC557"))
    )
    (comp (ref "T274")
      (value "BC857")
      (footprint "eagle-import:SOT-23")
      (libsource (lib "eagle-import") (part "BC557"))
    )
    (comp (ref "T275")
      (value "BC857")
      (footprint "eagle-import:SOT-23")
      (libsource (lib "eagle-import") (part "BC557"))
    )
    (comp (ref "T276")
      (value "BC857")
      (footprint "eagle-import:SOT-23")
      (libsource (lib "eagle-import") (part "BC557"))
    )
    (comp (ref "T277")
      (value "BC857")
      (footprint "eagle-import:SOT-23")
      (libsource (lib "eagle-import") (part "BC557"))
    )
    (comp (ref "T278")
      (value "BC847")
      (footprint "eagle-import:SOT-23")
      (libsource (lib "eagle-import") (part "BC547"))
    )
    (comp (ref "T279")
      (value "BC847")
      (footprint "eagle-import:SOT-23")
      (libsource (lib "eagle-import") (part "BC547"))
    )
    (comp (ref "T280")
      (value "BC847")
      (footprint "eagle-import:SOT-23")
      (libsource (lib "eagle-import") (part "BC547"))
    )
    (comp (ref "T281")
      (value "BC847")
      (footprint "eagle-import:SOT-23")
      (libsource (lib "eagle-import") (part "BC547"))
    )
    (comp (ref "T282")
      (value "BC847")
      (footprint "eagle-import:SOT-23")
      (libsource (lib "eagle-import") (part "BC547"))
    )
    (comp (ref "T283")
      (value "BC847")
      (footprint "eagle-import:SOT-23")
      (libsource (lib "eagle-import") (part "BC547"))
    )
    (comp (ref "T284")
      (value "BC847")
      (footprint "eagle-import:SOT-23")
      (libsource (lib "eagle-import") (part "BC547"))
    )
    (comp (ref "T285")
      (value "BC847")
      (footprint "eagle-import:SOT-23")
      (libsource (lib "eagle-import") (part "BC547"))
    )
    (comp (ref "T286")
      (value "BC847")
      (footprint "eagle-import:SOT-23")
      (libsource (lib "eagle-import") (part "BC547"))
    )
    (comp (ref "T287")
      (value "BC857")
      (footprint "eagle-import:SOT-23")
      (libsource (lib "eagle-import") (part "BC557"))
    )
    (comp (ref "T288")
      (value "BC847")
      (footprint "eagle-import:SOT-23")
      (libsource (lib "eagle-import") (part "BC547"))
    )
    (comp (ref "T289")
      (value "BC857")
      (footprint "eagle-import:SOT-23")
      (libsource (lib "eagle-import") (part "BC557"))
    )
    (comp (ref "T290")
      (value "BC857")
      (footprint "eagle-import:SOT-23")
      (libsource (lib "eagle-import") (part "BC557"))
    )
    (comp (ref "T291")
      (value "BC857")
      (footprint "eagle-import:SOT-23")
      (libsource (lib "eagle-import") (part "BC557"))
    )
    (comp (ref "T292")
      (value "BC857")
      (footprint "eagle-import:SOT-23")
      (libsource (lib "eagle-import") (part "BC557"))
    )
    (comp (ref "T293")
      (value "BC857")
      (footprint "eagle-import:SOT-23")
      (libsource (lib "eagle-import") (part "BC557"))
    )
    (comp (ref "T294")
      (value "BC857")
      (footprint "eagle-import:SOT-23")
      (libsource (lib "eagle-import") (part "BC557"))
    )
    (comp (ref "T295")
      (value "BC857")
      (footprint "eagle-import:SOT-23")
      (libsource (lib "eagle-import") (part "BC557"))
    )
    (comp (ref "T296")
      (value "BC857")
      (footprint "eagle-import:SOT-23")
      (libsource (lib "eagle-import") (part "BC557"))
    )
    (comp (ref "T297")
      (value "BC857")
      (footprint "eagle-import:SOT-23")
      (libsource (lib "eagle-import") (part "BC557"))
    )
    (comp (ref "T298")
      (value "BC857")
      (footprint "eagle-import:SOT-23")
      (libsource (lib "eagle-import") (part "BC557"))
    )
    (comp (ref "T299")
      (value "BC857")
      (footprint "eagle-import:SOT-23")
      (libsource (lib "eagle-import") (part "BC557"))
    )
    (comp (ref "T300")
      (value "BC857")
      (footprint "eagle-import:SOT-23")
      (libsource (lib "eagle-import") (part "BC557"))
    )
    (comp (ref "T301")
      (value "BC857")
      (footprint "eagle-import:SOT-23")
      (libsource (lib "eagle-import") (part "BC557"))
    )
    (comp (ref "T302")
      (value "BC857")
      (footprint "eagle-import:SOT-23")
      (libsource (lib "eagle-import") (part "BC557"))
    )
    (comp (ref "T303")
      (value "BC857")
      (footprint "eagle-import:SOT-23")
      (libsource (lib "eagle-import") (part "BC557"))
    )
    (comp (ref "T304")
      (value "BC847")
      (footprint "eagle-import:SOT-23")
      (libsource (lib "eagle-import") (part "BC547"))
    )
    (comp (ref "T305")
      (value "BC847")
      (footprint "eagle-import:SOT-23")
      (libsource (lib "eagle-import") (part "BC547"))
    )
    (comp (ref "T306")
      (value "BC847")
      (footprint "eagle-import:SOT-23")
      (libsource (lib "eagle-import") (part "BC547"))
    )
    (comp (ref "T307")
      (value "BC847")
      (footprint "eagle-import:SOT-23")
      (libsource (lib "eagle-import") (part "BC547"))
    )
    (comp (ref "T308")
      (value "BC847")
      (footprint "eagle-import:SOT-23")
      (libsource (lib "eagle-import") (part "BC547"))
    )
    (comp (ref "T309")
      (value "BC847")
      (footprint "eagle-import:SOT-23")
      (libsource (lib "eagle-import") (part "BC547"))
    )
    (comp (ref "T310")
      (value "BC847")
      (footprint "eagle-import:SOT-23")
      (libsource (lib "eagle-import") (part "BC547"))
    )
    (comp (ref "T311")
      (value "BC847")
      (footprint "eagle-import:SOT-23")
      (libsource (lib "eagle-import") (part "BC547"))
    )
    (comp (ref "T312")
      (value "BC847")
      (footprint "eagle-import:SOT-23")
      (libsource (lib "eagle-import") (part "BC547"))
    )
    (comp (ref "C5")
      (value "100n")
      (footprint "eagle-import:0204")
      (libsource (lib "eagle-import") (part "CAPNP-5"))
    )
    (comp (ref "C6")
      (value "100n")
      (footprint "eagle-import:0204")
      (libsource (lib "eagle-import") (part "CAPNP-5"))
    )
    (comp (ref "J105")
      (value "JUMPII")
      (footprint "eagle-import:JUMPII")
      (libsource (lib "eagle-import") (part "JUMPII@2"))
    )
    (comp (ref "J106")
      (value "JUMPII")
      (footprint "eagle-import:JUMPII")
      (libsource (lib "eagle-import") (part "JUMPII@2"))
    )
    (comp (ref "J107")
      (value "JUMPII")
      (footprint "eagle-import:JUMPII")
      (libsource (lib "eagle-import") (part "JUMPII@2"))
    )
    (comp (ref "J108")
      (value "JUMPII")
      (footprint "eagle-import:JUMPII")
      (libsource (lib "eagle-import") (part "JUMPII@2"))
    )
    (comp (ref "J109")
      (value "JUMPII")
      (footprint "eagle-import:JUMPII")
      (libsource (lib "eagle-import") (part "JUMPII@2"))
    )
    (comp (ref "J110")
      (value "JUMPII")
      (footprint "eagle-import:JUMPII")
      (libsource (lib "eagle-import") (part "JUMPII@2"))
    )
    (comp (ref "J111")
      (value "JUMPII")
      (footprint "eagle-import:JUMPII")
      (libsource (lib "eagle-import") (part "JUMPII@2"))
    )
    (comp (ref "J112")
      (value "JUMPII")
      (footprint "eagle-import:JUMPII")
      (libsource (lib "eagle-import") (part "JUMPII@2"))
    )
    (comp (ref "J113")
      (value "JUMPII")
      (footprint "eagle-import:JUMPII")
      (libsource (lib "eagle-import") (part "JUMPII@2"))
    )
    (comp (ref "J114")
      (value "JUMPII")
      (footprint "eagle-import:JUMPII")
      (libsource (lib "eagle-import") (part "JUMPII@2"))
    )
    (comp (ref "J115")
      (value "JUMPII")
      (footprint "eagle-import:JUMPII")
      (libsource (lib "eagle-import") (part "JUMPII@2"))
    )
    (comp (ref "J116")
      (value "JUMPII")
      (footprint "eagle-import:JUMPII")
      (libsource (lib "eagle-import") (part "JUMPII@2"))
    )
    (comp (ref "J117")
      (value "JUMPII")
      (footprint "eagle-import:JUMPII")
      (libsource (lib "eagle-import") (part "JUMPII@2"))
    )
    (comp (ref "J118")
      (value "JUMPII")
      (footprint "eagle-import:JUMPII")
      (libsource (lib "eagle-import") (part "JUMPII@2"))
    )
    (comp (ref "J119")
      (value "JUMPII")
      (footprint "eagle-import:JUMPII")
      (libsource (lib "eagle-import") (part "JUMPII@2"))
    )
    (comp (ref "J120")
      (value "JUMPII")
      (footprint "eagle-import:JUMPII")
      (libsource (lib "eagle-import") (part "JUMPII@2"))
    )
    (comp (ref "J121")
      (value "JUMPII")
      (footprint "eagle-import:JUMPII")
      (libsource (lib "eagle-import") (part "JUMPII@2"))
    )
    (comp (ref "J122")
      (value "JUMPII")
      (footprint "eagle-import:JUMPII")
      (libsource (lib "eagle-import") (part "JUMPII@2"))
    )
    (comp (ref "J123")
      (value "JUMPII")
      (footprint "eagle-import:JUMPII")
      (libsource (lib "eagle-import") (part "JUMPII@2"))
    )
    (comp (ref "J124")
      (value "JUMPII")
      (footprint "eagle-import:JUMPII")
      (libsource (lib "eagle-import") (part "JUMPII@2"))
    )
    (comp (ref "J125")
      (value "JUMPII")
      (footprint "eagle-import:JUMPII")
      (libsource (lib "eagle-import") (part "JUMPII@2"))
    )
    (comp (ref "J126")
      (value "JUMPII")
      (footprint "eagle-import:JUMPII")
      (libsource (lib "eagle-import") (part "JUMPII@2"))
    )
    (comp (ref "J127")
      (value "JUMPII")
      (footprint "eagle-import:JUMPII")
      (libsource (lib "eagle-import") (part "JUMPII@2"))
    )
    (comp (ref "J128")
      (value "JUMPII")
      (footprint "eagle-import:JUMPII")
      (libsource (lib "eagle-import") (part "JUMPII@2"))
    )
    (comp (ref "J129")
      (value "JUMPII")
      (footprint "eagle-import:JUMPII")
      (libsource (lib "eagle-import") (part "JUMPII@2"))
    )
    (comp (ref "J130")
      (value "JUMPII")
      (footprint "eagle-import:JUMPII")
      (libsource (lib "eagle-import") (part "JUMPII@2"))
    )
    (comp (ref "J131")
      (value "JUMPII")
      (footprint "eagle-import:JUMPII")
      (libsource (lib "eagle-import") (part "JUMPII@2"))
    )
    (comp (ref "J132")
      (value "JUMPII")
      (footprint "eagle-import:JUMPII")
      (libsource (lib "eagle-import") (part "JUMPII@2"))
    )
    (comp (ref "J133")
      (value "JUMPII")
      (footprint "eagle-import:JUMPII")
      (libsource (lib "eagle-import") (part "JUMPII@2"))
    )
    (comp (ref "J134")
      (value "JUMPII")
      (footprint "eagle-import:JUMPII")
      (libsource (lib "eagle-import") (part "JUMPII@2"))
    )
    (comp (ref "J135")
      (value "JUMPII")
      (footprint "eagle-import:JUMPII")
      (libsource (lib "eagle-import") (part "JUMPII@2"))
    )
    (comp (ref "J136")
      (value "JUMPII")
      (footprint "eagle-import:JUMPII")
      (libsource (lib "eagle-import") (part "JUMPII@2"))
    )
    (comp (ref "J137")
      (value "JUMPII")
      (footprint "eagle-import:JUMPII")
      (libsource (lib "eagle-import") (part "JUMPII@2"))
    )
    (comp (ref "J138")
      (value "JUMPII")
      (footprint "eagle-import:JUMPII")
      (libsource (lib "eagle-import") (part "JUMPII@2"))
    )
    (comp (ref "J139")
      (value "JUMPII")
      (footprint "eagle-import:JUMPII")
      (libsource (lib "eagle-import") (part "JUMPII@2"))
    )
    (comp (ref "J140")
      (value "JUMPII")
      (footprint "eagle-import:JUMPII")
      (libsource (lib "eagle-import") (part "JUMPII@2"))
    )
    (comp (ref "J141")
      (value "JUMPII")
      (footprint "eagle-import:JUMPII")
      (libsource (lib "eagle-import") (part "JUMPII@2"))
    )
    (comp (ref "J142")
      (value "JUMPII")
      (footprint "eagle-import:JUMPII")
      (libsource (lib "eagle-import") (part "JUMPII@2"))
    )
    (comp (ref "J143")
      (value "JUMPII")
      (footprint "eagle-import:JUMPII")
      (libsource (lib "eagle-import") (part "JUMPII@2"))
    )
    (comp (ref "J144")
      (value "JUMPII")
      (footprint "eagle-import:JUMPII")
      (libsource (lib "eagle-import") (part "JUMPII@2"))
    )
    (comp (ref "J145")
      (value "JUMPII")
      (footprint "eagle-import:JUMPII")
      (libsource (lib "eagle-import") (part "JUMPII@2"))
    )
    (comp (ref "J146")
      (value "JUMPII")
      (footprint "eagle-import:JUMPII")
      (libsource (lib "eagle-import") (part "JUMPII@2"))
    )
    (comp (ref "J147")
      (value "JUMPII")
      (footprint "eagle-import:JUMPII")
      (libsource (lib "eagle-import") (part "JUMPII@2"))
    )
    (comp (ref "J148")
      (value "JUMPII")
      (footprint "eagle-import:JUMPII")
      (libsource (lib "eagle-import") (part "JUMPII@2"))
    )
    (comp (ref "J149")
      (value "JUMPII")
      (footprint "eagle-import:JUMPII")
      (libsource (lib "eagle-import") (part "JUMPII@2"))
    )
    (comp (ref "J150")
      (value "JUMPII")
      (footprint "eagle-import:JUMPII")
      (libsource (lib "eagle-import") (part "JUMPII@2"))
    )
    (comp (ref "J151")
      (value "JUMPII")
      (footprint "eagle-import:JUMPII")
      (libsource (lib "eagle-import") (part "JUMPII@2"))
    )
    (comp (ref "J152")
      (value "JUMPII")
      (footprint "eagle-import:JUMPII")
      (libsource (lib "eagle-import") (part "JUMPII@2"))
    )
    (comp (ref "J153")
      (value "JUMPII")
      (footprint "eagle-import:JUMPII")
      (libsource (lib "eagle-import") (part "JUMPII@2"))
    )
    (comp (ref "J154")
      (value "JUMPII")
      (footprint "eagle-import:JUMPII")
      (libsource (lib "eagle-import") (part "JUMPII@2"))
    )
    (comp (ref "J155")
      (value "JUMPII")
      (footprint "eagle-import:JUMPII")
      (libsource (lib "eagle-import") (part "JUMPII@2"))
    )
    (comp (ref "J156")
      (value "JUMPII")
      (footprint "eagle-import:JUMPII")
      (libsource (lib "eagle-import") (part "JUMPII@2"))
    )
    (comp (ref "R5")
      (value "390")
      (footprint "eagle-import:0204")
      (libsource (lib "eagle-import") (part "RESEU-7,5"))
    )
    (comp (ref "R6")
      (value "390")
      (footprint "eagle-import:0204")
      (libsource (lib "eagle-import") (part "RESEU-7,5"))
    )
    (comp (ref "T105")
      (value "BC857")
      (footprint "eagle-import:SOT-23")
      (libsource (lib "eagle-import") (part "BC557"))
    )
    (comp (ref "T106")
      (value "BC847")
      (footprint "eagle-import:SOT-23")
      (libsource (lib "eagle-import") (part "BC547"))
    )
    (comp (ref "T107")
      (value "BC857")
      (footprint "eagle-import:SOT-23")
      (libsource (lib "eagle-import") (part "BC557"))
    )
    (comp (ref "T108")
      (value "BC857")
      (footprint "eagle-import:SOT-23")
      (libsource (lib "eagle-import") (part "BC557"))
    )
    (comp (ref "T109")
      (value "BC857")
      (footprint "eagle-import:SOT-23")
      (libsource (lib "eagle-import") (part "BC557"))
    )
    (comp (ref "T110")
      (value "BC857")
      (footprint "eagle-import:SOT-23")
      (libsource (lib "eagle-import") (part "BC557"))
    )
    (comp (ref "T111")
      (value "BC857")
      (footprint "eagle-import:SOT-23")
      (libsource (lib "eagle-import") (part "BC557"))
    )
    (comp (ref "T112")
      (value "BC857")
      (footprint "eagle-import:SOT-23")
      (libsource (lib "eagle-import") (part "BC557"))
    )
    (comp (ref "T113")
      (value "BC857")
      (footprint "eagle-import:SOT-23")
      (libsource (lib "eagle-import") (part "BC557"))
    )
    (comp (ref "T114")
      (value "BC857")
      (footprint "eagle-import:SOT-23")
      (libsource (lib "eagle-import") (part "BC557"))
    )
    (comp (ref "T115")
      (value "BC857")
      (footprint "eagle-import:SOT-23")
      (libsource (lib "eagle-import") (part "BC557"))
    )
    (comp (ref "T116")
      (value "BC857")
      (footprint "eagle-import:SOT-23")
      (libsource (lib "eagle-import") (part "BC557"))
    )
    (comp (ref "T117")
      (value "BC857")
      (footprint "eagle-import:SOT-23")
      (libsource (lib "eagle-import") (part "BC557"))
    )
    (comp (ref "T118")
      (value "BC857")
      (footprint "eagle-import:SOT-23")
      (libsource (lib "eagle-import") (part "BC557"))
    )
    (comp (ref "T119")
      (value "BC857")
      (footprint "eagle-import:SOT-23")
      (libsource (lib "eagle-import") (part "BC557"))
    )
    (comp (ref "T120")
      (value "BC857")
      (footprint "eagle-import:SOT-23")
      (libsource (lib "eagle-import") (part "BC557"))
    )
    (comp (ref "T121")
      (value "BC857")
      (footprint "eagle-import:SOT-23")
      (libsource (lib "eagle-import") (part "BC557"))
    )
    (comp (ref "T122")
      (value "BC847")
      (footprint "eagle-import:SOT-23")
      (libsource (lib "eagle-import") (part "BC547"))
    )
    (comp (ref "T123")
      (value "BC847")
      (footprint "eagle-import:SOT-23")
      (libsource (lib "eagle-import") (part "BC547"))
    )
    (comp (ref "T124")
      (value "BC847")
      (footprint "eagle-import:SOT-23")
      (libsource (lib "eagle-import") (part "BC547"))
    )
    (comp (ref "T125")
      (value "BC847")
      (footprint "eagle-import:SOT-23")
      (libsource (lib "eagle-import") (part "BC547"))
    )
    (comp (ref "T126")
      (value "BC847")
      (footprint "eagle-import:SOT-23")
      (libsource (lib "eagle-import") (part "BC547"))
    )
    (comp (ref "T127")
      (value "BC847")
      (footprint "eagle-import:SOT-23")
      (libsource (lib "eagle-import") (part "BC547"))
    )
    (comp (ref "T128")
      (value "BC847")
      (footprint "eagle-import:SOT-23")
      (libsource (lib "eagle-import") (part "BC547"))
    )
    (comp (ref "T129")
      (value "BC847")
      (footprint "eagle-import:SOT-23")
      (libsource (lib "eagle-import") (part "BC547"))
    )
    (comp (ref "T130")
      (value "BC847")
      (footprint "eagle-import:SOT-23")
      (libsource (lib "eagle-import") (part "BC547"))
    )
    (comp (ref "T131")
      (value "BC857")
      (footprint "eagle-import:SOT-23")
      (libsource (lib "eagle-import") (part "BC557"))
    )
    (comp (ref "T132")
      (value "BC847")
      (footprint "eagle-import:SOT-23")
      (libsource (lib "eagle-import") (part "BC547"))
    )
    (comp (ref "T133")
      (value "BC857")
      (footprint "eagle-import:SOT-23")
      (libsource (lib "eagle-import") (part "BC557"))
    )
    (comp (ref "T134")
      (value "BC857")
      (footprint "eagle-import:SOT-23")
      (libsource (lib "eagle-import") (part "BC557"))
    )
    (comp (ref "T135")
      (value "BC857")
      (footprint "eagle-import:SOT-23")
      (libsource (lib "eagle-import") (part "BC557"))
    )
    (comp (ref "T136")
      (value "BC857")
      (footprint "eagle-import:SOT-23")
      (libsource (lib "eagle-import") (part "BC557"))
    )
    (comp (ref "T137")
      (value "BC857")
      (footprint "eagle-import:SOT-23")
      (libsource (lib "eagle-import") (part "BC557"))
    )
    (comp (ref "T138")
      (value "BC857")
      (footprint "eagle-import:SOT-23")
      (libsource (lib "eagle-import") (part "BC557"))
    )
    (comp (ref "T139")
      (value "BC857")
      (footprint "eagle-import:SOT-23")
      (libsource (lib "eagle-import") (part "BC557"))
    )
    (comp (ref "T140")
      (value "BC857")
      (footprint "eagle-import:SOT-23")
      (libsource (lib "eagle-import") (part "BC557"))
    )
    (comp (ref "T141")
      (value "BC857")
      (footprint "eagle-import:SOT-23")
      (libsource (lib "eagle-import") (part "BC557"))
    )
    (comp (ref "T142")
      (value "BC857")
      (footprint "eagle-import:SOT-23")
      (libsource (lib "eagle-import") (part "BC557"))
    )
    (comp (ref "T143")
      (value "BC857")
      (footprint "eagle-import:SOT-23")
      (libsource (lib "eagle-import") (part "BC557"))
    )
    (comp (ref "T144")
      (value "BC857")
      (footprint "eagle-import:SOT-23")
      (libsource (lib "eagle-import") (part "BC557"))
    )
    (comp (ref "T145")
      (value "BC857")
      (footprint "eagle-import:SOT-23")
      (libsource (lib "eagle-import") (part "BC557"))
    )
    (comp (ref "T146")
      (value "BC857")
      (footprint "eagle-import:SOT-23")
      (libsource (lib "eagle-import") (part "BC557"))
    )
    (comp (ref "T147")
      (value "BC857")
      (footprint "eagle-import:SOT-23")
      (libsource (lib "eagle-import") (part "BC557"))
    )
    (comp (ref "T148")
      (value "BC847")
      (footprint "eagle-import:SOT-23")
      (libsource (lib "eagle-import") (part "BC547"))
    )
    (comp (ref "T149")
      (value "BC847")
      (footprint "eagle-import:SOT-23")
      (libsource (lib "eagle-import") (part "BC547"))
    )
    (comp (ref "T150")
      (value "BC847")
      (footprint "eagle-import:SOT-23")
      (libsource (lib "eagle-import") (part "BC547"))
    )
    (comp (ref "T151")
      (value "BC847")
      (footprint "eagle-import:SOT-23")
      (libsource (lib "eagle-import") (part "BC547"))
    )
    (comp (ref "T152")
      (value "BC847")
      (footprint "eagle-import:SOT-23")
      (libsource (lib "eagle-import") (part "BC547"))
    )
    (comp (ref "T153")
      (value "BC847")
      (footprint "eagle-import:SOT-23")
      (libsource (lib "eagle-import") (part "BC547"))
    )
    (comp (ref "T154")
      (value "BC847")
      (footprint "eagle-import:SOT-23")
      (libsource (lib "eagle-import") (part "BC547"))
    )
    (comp (ref "T155")
      (value "BC847")
      (footprint "eagle-import:SOT-23")
      (libsource (lib "eagle-import") (part "BC547"))
    )
    (comp (ref "T156")
      (value "BC847")
      (footprint "eagle-import:SOT-23")
      (libsource (lib "eagle-import") (part "BC547"))
    )
    (comp (ref "C3")
      (value "100n")
      (footprint "eagle-import:0204")
      (libsource (lib "eagle-import") (part "CAPNP-5"))
    )
    (comp (ref "C4")
      (value "100n")
      (footprint "eagle-import:0204")
      (libsource (lib "eagle-import") (part "CAPNP-5"))
    )
    (comp (ref "J53")
      (value "JUMPII")
      (footprint "eagle-import:JUMPII")
      (libsource (lib "eagle-import") (part "JUMPII@2"))
    )
    (comp (ref "J54")
      (value "JUMPII")
      (footprint "eagle-import:JUMPII")
      (libsource (lib "eagle-import") (part "JUMPII@2"))
    )
    (comp (ref "J55")
      (value "JUMPII")
      (footprint "eagle-import:JUMPII")
      (libsource (lib "eagle-import") (part "JUMPII@2"))
    )
    (comp (ref "J56")
      (value "JUMPII")
      (footprint "eagle-import:JUMPII")
      (libsource (lib "eagle-import") (part "JUMPII@2"))
    )
    (comp (ref "J57")
      (value "JUMPII")
      (footprint "eagle-import:JUMPII")
      (libsource (lib "eagle-import") (part "JUMPII@2"))
    )
    (comp (ref "J58")
      (value "JUMPII")
      (footprint "eagle-import:JUMPII")
      (libsource (lib "eagle-import") (part "JUMPII@2"))
    )
    (comp (ref "J59")
      (value "JUMPII")
      (footprint "eagle-import:JUMPII")
      (libsource (lib "eagle-import") (part "JUMPII@2"))
    )
    (comp (ref "J60")
      (value "JUMPII")
      (footprint "eagle-import:JUMPII")
      (libsource (lib "eagle-import") (part "JUMPII@2"))
    )
    (comp (ref "J61")
      (value "JUMPII")
      (footprint "eagle-import:JUMPII")
      (libsource (lib "eagle-import") (part "JUMPII@2"))
    )
    (comp (ref "J62")
      (value "JUMPII")
      (footprint "eagle-import:JUMPII")
      (libsource (lib "eagle-import") (part "JUMPII@2"))
    )
    (comp (ref "J63")
      (value "JUMPII")
      (footprint "eagle-import:JUMPII")
      (libsource (lib "eagle-import") (part "JUMPII@2"))
    )
    (comp (ref "J64")
      (value "JUMPII")
      (footprint "eagle-import:JUMPII")
      (libsource (lib "eagle-import") (part "JUMPII@2"))
    )
    (comp (ref "J65")
      (value "JUMPII")
      (footprint "eagle-import:JUMPII")
      (libsource (lib "eagle-import") (part "JUMPII@2"))
    )
    (comp (ref "J66")
      (value "JUMPII")
      (footprint "eagle-import:JUMPII")
      (libsource (lib "eagle-import") (part "JUMPII@2"))
    )
    (comp (ref "J67")
      (value "JUMPII")
      (footprint "eagle-import:JUMPII")
      (libsource (lib "eagle-import") (part "JUMPII@2"))
    )
    (comp (ref "J68")
      (value "JUMPII")
      (footprint "eagle-import:JUMPII")
      (libsource (lib "eagle-import") (part "JUMPII@2"))
    )
    (comp (ref "J69")
      (value "JUMPII")
      (footprint "eagle-import:JUMPII")
      (libsource (lib "eagle-import") (part "JUMPII@2"))
    )
    (comp (ref "J70")
      (value "JUMPII")
      (footprint "eagle-import:JUMPII")
      (libsource (lib "eagle-import") (part "JUMPII@2"))
    )
    (comp (ref "J71")
      (value "JUMPII")
      (footprint "eagle-import:JUMPII")
      (libsource (lib "eagle-import") (part "JUMPII@2"))
    )
    (comp (ref "J72")
      (value "JUMPII")
      (footprint "eagle-import:JUMPII")
      (libsource (lib "eagle-import") (part "JUMPII@2"))
    )
    (comp (ref "J73")
      (value "JUMPII")
      (footprint "eagle-import:JUMPII")
      (libsource (lib "eagle-import") (part "JUMPII@2"))
    )
    (comp (ref "J74")
      (value "JUMPII")
      (footprint "eagle-import:JUMPII")
      (libsource (lib "eagle-import") (part "JUMPII@2"))
    )
    (comp (ref "J75")
      (value "JUMPII")
      (footprint "eagle-import:JUMPII")
      (libsource (lib "eagle-import") (part "JUMPII@2"))
    )
    (comp (ref "J76")
      (value "JUMPII")
      (footprint "eagle-import:JUMPII")
      (libsource (lib "eagle-import") (part "JUMPII@2"))
    )
    (comp (ref "J77")
      (value "JUMPII")
      (footprint "eagle-import:JUMPII")
      (libsource (lib "eagle-import") (part "JUMPII@2"))
    )
    (comp (ref "J78")
      (value "JUMPII")
      (footprint "eagle-import:JUMPII")
      (libsource (lib "eagle-import") (part "JUMPII@2"))
    )
    (comp (ref "J79")
      (value "JUMPII")
      (footprint "eagle-import:JUMPII")
      (libsource (lib "eagle-import") (part "JUMPII@2"))
    )
    (comp (ref "J80")
      (value "JUMPII")
      (footprint "eagle-import:JUMPII")
      (libsource (lib "eagle-import") (part "JUMPII@2"))
    )
    (comp (ref "J81")
      (value "JUMPII")
      (footprint "eagle-import:JUMPII")
      (libsource (lib "eagle-import") (part "JUMPII@2"))
    )
    (comp (ref "J82")
      (value "JUMPII")
      (footprint "eagle-import:JUMPII")
      (libsource (lib "eagle-import") (part "JUMPII@2"))
    )
    (comp (ref "J83")
      (value "JUMPII")
      (footprint "eagle-import:JUMPII")
      (libsource (lib "eagle-import") (part "JUMPII@2"))
    )
    (comp (ref "J84")
      (value "JUMPII")
      (footprint "eagle-import:JUMPII")
      (libsource (lib "eagle-import") (part "JUMPII@2"))
    )
    (comp (ref "J85")
      (value "JUMPII")
      (footprint "eagle-import:JUMPII")
      (libsource (lib "eagle-import") (part "JUMPII@2"))
    )
    (comp (ref "J86")
      (value "JUMPII")
      (footprint "eagle-import:JUMPII")
      (libsource (lib "eagle-import") (part "JUMPII@2"))
    )
    (comp (ref "J87")
      (value "JUMPII")
      (footprint "eagle-import:JUMPII")
      (libsource (lib "eagle-import") (part "JUMPII@2"))
    )
    (comp (ref "J88")
      (value "JUMPII")
      (footprint "eagle-import:JUMPII")
      (libsource (lib "eagle-import") (part "JUMPII@2"))
    )
    (comp (ref "J89")
      (value "JUMPII")
      (footprint "eagle-import:JUMPII")
      (libsource (lib "eagle-import") (part "JUMPII@2"))
    )
    (comp (ref "J90")
      (value "JUMPII")
      (footprint "eagle-import:JUMPII")
      (libsource (lib "eagle-import") (part "JUMPII@2"))
    )
    (comp (ref "J91")
      (value "JUMPII")
      (footprint "eagle-import:JUMPII")
      (libsource (lib "eagle-import") (part "JUMPII@2"))
    )
    (comp (ref "J92")
      (value "JUMPII")
      (footprint "eagle-import:JUMPII")
      (libsource (lib "eagle-import") (part "JUMPII@2"))
    )
    (comp (ref "J93")
      (value "JUMPII")
      (footprint "eagle-import:JUMPII")
      (libsource (lib "eagle-import") (part "JUMPII@2"))
    )
    (comp (ref "J94")
      (value "JUMPII")
      (footprint "eagle-import:JUMPII")
      (libsource (lib "eagle-import") (part "JUMPII@2"))
    )
    (comp (ref "J95")
      (value "JUMPII")
      (footprint "eagle-import:JUMPII")
      (libsource (lib "eagle-import") (part "JUMPII@2"))
    )
    (comp (ref "J96")
      (value "JUMPII")
      (footprint "eagle-import:JUMPII")
      (libsource (lib "eagle-import") (part "JUMPII@2"))
    )
    (comp (ref "J97")
      (value "JUMPII")
      (footprint "eagle-import:JUMPII")
      (libsource (lib "eagle-import") (part "JUMPII@2"))
    )
    (comp (ref "J98")
      (value "JUMPII")
      (footprint "eagle-import:JUMPII")
      (libsource (lib "eagle-import") (part "JUMPII@2"))
    )
    (comp (ref "J99")
      (value "JUMPII")
      (footprint "eagle-import:JUMPII")
      (libsource (lib "eagle-import") (part "JUMPII@2"))
    )
    (comp (ref "J100")
      (value "JUMPII")
      (footprint "eagle-import:JUMPII")
      (libsource (lib "eagle-import") (part "JUMPII@2"))
    )
    (comp (ref "J101")
      (value "JUMPII")
      (footprint "eagle-import:JUMPII")
      (libsource (lib "eagle-import") (part "JUMPII@2"))
    )
    (comp (ref "J102")
      (value "JUMPII")
      (footprint "eagle-import:JUMPII")
      (libsource (lib "eagle-import") (part "JUMPII@2"))
    )
    (comp (ref "J103")
      (value "JUMPII")
      (footprint "eagle-import:JUMPII")
      (libsource (lib "eagle-import") (part "JUMPII@2"))
    )
    (comp (ref "J104")
      (value "JUMPII")
      (footprint "eagle-import:JUMPII")
      (libsource (lib "eagle-import") (part "JUMPII@2"))
    )
    (comp (ref "R2")
      (value "390")
      (footprint "eagle-import:0204")
      (libsource (lib "eagle-import") (part "RESEU-7,5"))
    )
    (comp (ref "R4")
      (value "390")
      (footprint "eagle-import:0204")
      (libsource (lib "eagle-import") (part "RESEU-7,5"))
    )
    (comp (ref "T53")
      (value "BC857")
      (footprint "eagle-import:SOT-23")
      (libsource (lib "eagle-import") (part "BC557"))
    )
    (comp (ref "T54")
      (value "BC847")
      (footprint "eagle-import:SOT-23")
      (libsource (lib "eagle-import") (part "BC547"))
    )
    (comp (ref "T55")
      (value "BC857")
      (footprint "eagle-import:SOT-23")
      (libsource (lib "eagle-import") (part "BC557"))
    )
    (comp (ref "T56")
      (value "BC857")
      (footprint "eagle-import:SOT-23")
      (libsource (lib "eagle-import") (part "BC557"))
    )
    (comp (ref "T57")
      (value "BC857")
      (footprint "eagle-import:SOT-23")
      (libsource (lib "eagle-import") (part "BC557"))
    )
    (comp (ref "T58")
      (value "BC857")
      (footprint "eagle-import:SOT-23")
      (libsource (lib "eagle-import") (part "BC557"))
    )
    (comp (ref "T59")
      (value "BC857")
      (footprint "eagle-import:SOT-23")
      (libsource (lib "eagle-import") (part "BC557"))
    )
    (comp (ref "T60")
      (value "BC857")
      (footprint "eagle-import:SOT-23")
      (libsource (lib "eagle-import") (part "BC557"))
    )
    (comp (ref "T61")
      (value "BC857")
      (footprint "eagle-import:SOT-23")
      (libsource (lib "eagle-import") (part "BC557"))
    )
    (comp (ref "T62")
      (value "BC857")
      (footprint "eagle-import:SOT-23")
      (libsource (lib "eagle-import") (part "BC557"))
    )
    (comp (ref "T63")
      (value "BC857")
      (footprint "eagle-import:SOT-23")
      (libsource (lib "eagle-import") (part "BC557"))
    )
    (comp (ref "T64")
      (value "BC857")
      (footprint "eagle-import:SOT-23")
      (libsource (lib "eagle-import") (part "BC557"))
    )
    (comp (ref "T65")
      (value "BC857")
      (footprint "eagle-import:SOT-23")
      (libsource (lib "eagle-import") (part "BC557"))
    )
    (comp (ref "T66")
      (value "BC857")
      (footprint "eagle-import:SOT-23")
      (libsource (lib "eagle-import") (part "BC557"))
    )
    (comp (ref "T67")
      (value "BC857")
      (footprint "eagle-import:SOT-23")
      (libsource (lib "eagle-import") (part "BC557"))
    )
    (comp (ref "T68")
      (value "BC857")
      (footprint "eagle-import:SOT-23")
      (libsource (lib "eagle-import") (part "BC557"))
    )
    (comp (ref "T69")
      (value "BC857")
      (footprint "eagle-import:SOT-23")
      (libsource (lib "eagle-import") (part "BC557"))
    )
    (comp (ref "T70")
      (value "BC847")
      (footprint "eagle-import:SOT-23")
      (libsource (lib "eagle-import") (part "BC547"))
    )
    (comp (ref "T71")
      (value "BC847")
      (footprint "eagle-import:SOT-23")
      (libsource (lib "eagle-import") (part "BC547"))
    )
    (comp (ref "T72")
      (value "BC847")
      (footprint "eagle-import:SOT-23")
      (libsource (lib "eagle-import") (part "BC547"))
    )
    (comp (ref "T73")
      (value "BC847")
      (footprint "eagle-import:SOT-23")
      (libsource (lib "eagle-import") (part "BC547"))
    )
    (comp (ref "T74")
      (value "BC847")
      (footprint "eagle-import:SOT-23")
      (libsource (lib "eagle-import") (part "BC547"))
    )
    (comp (ref "T75")
      (value "BC847")
      (footprint "eagle-import:SOT-23")
      (libsource (lib "eagle-import") (part "BC547"))
    )
    (comp (ref "T76")
      (value "BC847")
      (footprint "eagle-import:SOT-23")
      (libsource (lib "eagle-import") (part "BC547"))
    )
    (comp (ref "T77")
      (value "BC847")
      (footprint "eagle-import:SOT-23")
      (libsource (lib "eagle-import") (part "BC547"))
    )
    (comp (ref "T78")
      (value "BC847")
      (footprint "eagle-import:SOT-23")
      (libsource (lib "eagle-import") (part "BC547"))
    )
    (comp (ref "T79")
      (value "BC857")
      (footprint "eagle-import:SOT-23")
      (libsource (lib "eagle-import") (part "BC557"))
    )
    (comp (ref "T80")
      (value "BC847")
      (footprint "eagle-import:SOT-23")
      (libsource (lib "eagle-import") (part "BC547"))
    )
    (comp (ref "T81")
      (value "BC857")
      (footprint "eagle-import:SOT-23")
      (libsource (lib "eagle-import") (part "BC557"))
    )
    (comp (ref "T82")
      (value "BC857")
      (footprint "eagle-import:SOT-23")
      (libsource (lib "eagle-import") (part "BC557"))
    )
    (comp (ref "T83")
      (value "BC857")
      (footprint "eagle-import:SOT-23")
      (libsource (lib "eagle-import") (part "BC557"))
    )
    (comp (ref "T84")
      (value "BC857")
      (footprint "eagle-import:SOT-23")
      (libsource (lib "eagle-import") (part "BC557"))
    )
    (comp (ref "T85")
      (value "BC857")
      (footprint "eagle-import:SOT-23")
      (libsource (lib "eagle-import") (part "BC557"))
    )
    (comp (ref "T86")
      (value "BC857")
      (footprint "eagle-import:SOT-23")
      (libsource (lib "eagle-import") (part "BC557"))
    )
    (comp (ref "T87")
      (value "BC857")
      (footprint "eagle-import:SOT-23")
      (libsource (lib "eagle-import") (part "BC557"))
    )
    (comp (ref "T88")
      (value "BC857")
      (footprint "eagle-import:SOT-23")
      (libsource (lib "eagle-import") (part "BC557"))
    )
    (comp (ref "T89")
      (value "BC857")
      (footprint "eagle-import:SOT-23")
      (libsource (lib "eagle-import") (part "BC557"))
    )
    (comp (ref "T90")
      (value "BC857")
      (footprint "eagle-import:SOT-23")
      (libsource (lib "eagle-import") (part "BC557"))
    )
    (comp (ref "T91")
      (value "BC857")
      (footprint "eagle-import:SOT-23")
      (libsource (lib "eagle-import") (part "BC557"))
    )
    (comp (ref "T92")
      (value "BC857")
      (footprint "eagle-import:SOT-23")
      (libsource (lib "eagle-import") (part "BC557"))
    )
    (comp (ref "T93")
      (value "BC857")
      (footprint "eagle-import:SOT-23")
      (libsource (lib "eagle-import") (part "BC557"))
    )
    (comp (ref "T94")
      (value "BC857")
      (footprint "eagle-import:SOT-23")
      (libsource (lib "eagle-import") (part "BC557"))
    )
    (comp (ref "T95")
      (value "BC857")
      (footprint "eagle-import:SOT-23")
      (libsource (lib "eagle-import") (part "BC557"))
    )
    (comp (ref "T96")
      (value "BC847")
      (footprint "eagle-import:SOT-23")
      (libsource (lib "eagle-import") (part "BC547"))
    )
    (comp (ref "T97")
      (value "BC847")
      (footprint "eagle-import:SOT-23")
      (libsource (lib "eagle-import") (part "BC547"))
    )
    (comp (ref "T98")
      (value "BC847")
      (footprint "eagle-import:SOT-23")
      (libsource (lib "eagle-import") (part "BC547"))
    )
    (comp (ref "T99")
      (value "BC847")
      (footprint "eagle-import:SOT-23")
      (libsource (lib "eagle-import") (part "BC547"))
    )
    (comp (ref "T100")
      (value "BC847")
      (footprint "eagle-import:SOT-23")
      (libsource (lib "eagle-import") (part "BC547"))
    )
    (comp (ref "T101")
      (value "BC847")
      (footprint "eagle-import:SOT-23")
      (libsource (lib "eagle-import") (part "BC547"))
    )
    (comp (ref "T102")
      (value "BC847")
      (footprint "eagle-import:SOT-23")
      (libsource (lib "eagle-import") (part "BC547"))
    )
    (comp (ref "T103")
      (value "BC847")
      (footprint "eagle-import:SOT-23")
      (libsource (lib "eagle-import") (part "BC547"))
    )
    (comp (ref "T104")
      (value "BC847")
      (footprint "eagle-import:SOT-23")
      (libsource (lib "eagle-import") (part "BC547"))
    )
  )
  (nets
    (net (code "33") (name "GND") (class "Default")
      (node (ref "C1") (pin "1") (pinfunction "1_1") (pintype "passive"))
      (node (ref "C10") (pin "1") (pinfunction "1_1") (pintype "passive"))
      (node (ref "C11") (pin "1") (pinfunction "1_1") (pintype "passive"))
      (node (ref "C12") (pin "1") (pinfunction "1_1") (pintype "passive"))
      (node (ref "C13") (pin "1") (pinfunction "1_1") (pintype "passive"))
      (node (ref "C14") (pin "1") (pinfunction "1_1") (pintype "passive"))
      (node (ref "C15") (pin "1") (pinfunction "1_1") (pintype "passive"))
      (node (ref "C16") (pin "1") (pinfunction "1_1") (pintype "passive"))
      (node (ref "C2") (pin "1") (pinfunction "1_1") (pintype "passive"))
      (node (ref "C3") (pin "1") (pinfunction "1_1") (pintype "passive"))
      (node (ref "C4") (pin "1") (pinfunction "1_1") (pintype "passive"))
      (node (ref "C5") (pin "1") (pinfunction "1_1") (pintype "passive"))
      (node (ref "C6") (pin "1") (pinfunction "1_1") (pintype "passive"))
      (node (ref "C7") (pin "1") (pinfunction "1_1") (pintype "passive"))
      (node (ref "C8") (pin "1") (pinfunction "1_1") (pintype "passive"))
      (node (ref "C9") (pin "1") (pinfunction "1_1") (pintype "passive"))
      (node (ref "T1") (pin "3") (pinfunction "C_3") (pintype "passive"))
      (node (ref "T10") (pin "3") (pinfunction "C_3") (pintype "passive"))
      (node (ref "T105") (pin "3") (pinfunction "C_3") (pintype "passive"))
      (node (ref "T107") (pin "3") (pinfunction "C_3") (pintype "passive"))
      (node (ref "T108") (pin "3") (pinfunction "C_3") (pintype "passive"))
      (node (ref "T109") (pin "3") (pinfunction "C_3") (pintype "passive"))
      (node (ref "T11") (pin "3") (pinfunction "C_3") (pintype "passive"))
      (node (ref "T110") (pin "3") (pinfunction "C_3") (pintype "passive"))
      (node (ref "T111") (pin "3") (pinfunction "C_3") (pintype "passive"))
      (node (ref "T112") (pin "3") (pinfunction "C_3") (pintype "passive"))
      (node (ref "T113") (pin "3") (pinfunction "C_3") (pintype "passive"))
      (node (ref "T114") (pin "3") (pinfunction "C_3") (pintype "passive"))
      (node (ref "T115") (pin "3") (pinfunction "C_3") (pintype "passive"))
      (node (ref "T116") (pin "3") (pinfunction "C_3") (pintype "passive"))
      (node (ref "T117") (pin "3") (pinfunction "C_3") (pintype "passive"))
      (node (ref "T118") (pin "3") (pinfunction "C_3") (pintype "passive"))
      (node (ref "T119") (pin "3") (pinfunction "C_3") (pintype "passive"))
      (node (ref "T12") (pin "3") (pinfunction "C_3") (pintype "passive"))
      (node (ref "T120") (pin "3") (pinfunction "C_3") (pintype "passive"))
      (node (ref "T121") (pin "3") (pinfunction "C_3") (pintype "passive"))
      (node (ref "T13") (pin "3") (pinfunction "C_3") (pintype "passive"))
      (node (ref "T131") (pin "3") (pinfunction "C_3") (pintype "passive"))
      (node (ref "T133") (pin "3") (pinfunction "C_3") (pintype "passive"))
      (node (ref "T134") (pin "3") (pinfunction "C_3") (pintype "passive"))
      (node (ref "T135") (pin "3") (pinfunction "C_3") (pintype "passive"))
      (node (ref "T136") (pin "3") (pinfunction "C_3") (pintype "passive"))
      (node (ref "T137") (pin "3") (pinfunction "C_3") (pintype "passive"))
      (node (ref "T138") (pin "3") (pinfunction "C_3") (pintype "passive"))
      (node (ref "T139") (pin "3") (pinfunction "C_3") (pintype "passive"))
      (node (ref "T14") (pin "3") (pinfunction "C_3") (pintype "passive"))
      (node (ref "T140") (pin "3") (pinfunction "C_3") (pintype "passive"))
      (node (ref "T141") (pin "3") (pinfunction "C_3") (pintype "passive"))
      (node (ref "T142") (pin "3") (pinfunction "C_3") (pintype "passive"))
      (node (ref "T143") (pin "3") (pinfunction "C_3") (pintype "passive"))
      (node (ref "T144") (pin "3") (pinfunction "C_3") (pintype "passive"))
      (node (ref "T145") (pin "3") (pinfunction "C_3") (pintype "passive"))
      (node (ref "T146") (pin "3") (pinfunction "C_3") (pintype "passive"))
      (node (ref "T147") (pin "3") (pinfunction "C_3") (pintype "passive"))
      (node (ref "T15") (pin "3") (pinfunction "C_3") (pintype "passive"))
      (node (ref "T157") (pin "3") (pinfunction "C_3") (pintype "passive"))
      (node (ref "T159") (pin "3") (pinfunction "C_3") (pintype "passive"))
      (node (ref "T16") (pin "3") (pinfunction "C_3") (pintype "passive"))
      (node (ref "T160") (pin "3") (pinfunction "C_3") (pintype "passive"))
      (node (ref "T161") (pin "3") (pinfunction "C_3") (pintype "passive"))
      (node (ref "T162") (pin "3") (pinfunction "C_3") (pintype "passive"))
      (node (ref "T163") (pin "3") (pinfunction "C_3") (pintype "passive"))
      (node (ref "T164") (pin "3") (pinfunction "C_3") (pintype "passive"))
      (node (ref "T165") (pin "3") (pinfunction "C_3") (pintype "passive"))
      (node (ref "T166") (pin "3") (pinfunction "C_3") (pintype "passive"))
      (node (ref "T167") (pin "3") (pinfunction "C_3") (pintype "passive"))
      (node (ref "T168") (pin "3") (pinfunction "C_3") (pintype "passive"))
      (node (ref "T169") (pin "3") (pinfunction "C_3") (pintype "passive"))
      (node (ref "T170") (pin "3") (pinfunction "C_3") (pintype "passive"))
      (node (ref "T171") (pin "3") (pinfunction "C_3") (pintype "passive"))
      (node (ref "T172") (pin "3") (pinfunction "C_3") (pintype "passive"))
      (node (ref "T173") (pin "3") (pinfunction "C_3") (pintype "passive"))
      (node (ref "T183") (pin "3") (pinfunction "C_3") (pintype "passive"))
      (node (ref "T185") (pin "3") (pinfunction "C_3") (pintype "passive"))
      (node (ref "T186") (pin "3") (pinfunction "C_3") (pintype "passive"))
      (node (ref "T187") (pin "3") (pinfunction "C_3") (pintype "passive"))
      (node (ref "T188") (pin "3") (pinfunction "C_3") (pintype "passive"))
      (node (ref "T189") (pin "3") (pinfunction "C_3") (pintype "passive"))
      (node (ref "T190") (pin "3") (pinfunction "C_3") (pintype "passive"))
      (node (ref "T191") (pin "3") (pinfunction "C_3") (pintype "passive"))
      (node (ref "T192") (pin "3") (pinfunction "C_3") (pintype "passive"))
      (node (ref "T193") (pin "3") (pinfunction "C_3") (pintype "passive"))
      (node (ref "T194") (pin "3") (pinfunction "C_3") (pintype "passive"))
      (node (ref "T195") (pin "3") (pinfunction "C_3") (pintype "passive"))
      (node (ref "T196") (pin "3") (pinfunction "C_3") (pintype "passive"))
      (node (ref "T197") (pin "3") (pinfunction "C_3") (pintype "passive"))
      (node (ref "T198") (pin "3") (pinfunction "C_3") (pintype "passive"))
      (node (ref "T199") (pin "3") (pinfunction "C_3") (pintype "passive"))
      (node (ref "T2") (pin "3") (pinfunction "C_3") (pintype "passive"))
      (node (ref "T209") (pin "3") (pinfunction "C_3") (pintype "passive"))
      (node (ref "T211") (pin "3") (pinfunction "C_3") (pintype "passive"))
      (node (ref "T212") (pin "3") (pinfunction "C_3") (pintype "passive"))
      (node (ref "T213") (pin "3") (pinfunction "C_3") (pintype "passive"))
      (node (ref "T214") (pin "3") (pinfunction "C_3") (pintype "passive"))
      (node (ref "T215") (pin "3") (pinfunction "C_3") (pintype "passive"))
      (node (ref "T216") (pin "3") (pinfunction "C_3") (pintype "passive"))
      (node (ref "T217") (pin "3") (pinfunction "C_3") (pintype "passive"))
      (node (ref "T218") (pin "3") (pinfunction "C_3") (pintype "passive"))
      (node (ref "T219") (pin "3") (pinfunction "C_3") (pintype "passive"))
      (node (ref "T220") (pin "3") (pinfunction "C_3") (pintype "passive"))
      (node (ref "T221") (pin "3") (pinfunction "C_3") (pintype "passive"))
      (node (ref "T222") (pin "3") (pinfunction "C_3") (pintype "passive"))
      (node (ref "T223") (pin "3") (pinfunction "C_3") (pintype "passive"))
      (node (ref "T224") (pin "3") (pinfunction "C_3") (pintype "passive"))
      (node (ref "T225") (pin "3") (pinfunction "C_3") (pintype "passive"))
      (node (ref "T235") (pin "3") (pinfunction "C_3") (pintype "passive"))
      (node (ref "T237") (pin "3") (pinfunction "C_3") (pintype "passive"))
      (node (ref "T238") (pin "3") (pinfunction "C_3") (pintype "passive"))
      (node (ref "T239") (pin "3") (pinfunction "C_3") (pintype "passive"))
      (node (ref "T240") (pin "3") (pinfunction "C_3") (pintype "passive"))
      (node (ref "T241") (pin "3") (pinfunction "C_3") (pintype "passive"))
      (node (ref "T242") (pin "3") (pinfunction "C_3") (pintype "passive"))
      (node (ref "T243") (pin "3") (pinfunction "C_3") (pintype "passive"))
      (node (ref "T244") (pin "3") (pinfunction "C_3") (pintype "passive"))
      (node (ref "T245") (pin "3") (pinfunction "C_3") (pintype "passive"))
      (node (ref "T246") (pin "3") (pinfunction "C_3") (pintype "passive"))
      (node (ref "T247") (pin "3") (pinfunction "C_3") (pintype "passive"))
      (node (ref "T248") (pin "3") (pinfunction "C_3") (pintype "passive"))
      (node (ref "T249") (pin "3") (pinfunction "C_3") (pintype "passive"))
      (node (ref "T250") (pin "3") (pinfunction "C_3") (pintype "passive"))
      (node (ref "T251") (pin "3") (pinfunction "C_3") (pintype "passive"))
      (node (ref "T261") (pin "3") (pinfunction "C_3") (pintype "passive"))
      (node (ref "T263") (pin "3") (pinfunction "C_3") (pintype "passive"))
      (node (ref "T264") (pin "3") (pinfunction "C_3") (pintype "passive"))
      (node (ref "T265") (pin "3") (pinfunction "C_3") (pintype "passive"))
      (node (ref "T266") (pin "3") (pinfunction "C_3") (pintype "passive"))
      (node (ref "T267") (pin "3") (pinfunction "C_3") (pintype "passive"))
      (node (ref "T268") (pin "3") (pinfunction "C_3") (pintype "passive"))
      (node (ref "T269") (pin "3") (pinfunction "C_3") (pintype "passive"))
      (node (ref "T27") (pin "3") (pinfunction "C_3") (pintype "passive"))
      (node (ref "T270") (pin "3") (pinfunction "C_3") (pintype "passive"))
      (node (ref "T271") (pin "3") (pinfunction "C_3") (pintype "passive"))
      (node (ref "T272") (pin "3") (pinfunction "C_3") (pintype "passive"))
      (node (ref "T273") (pin "3") (pinfunction "C_3") (pintype "passive"))
      (node (ref "T274") (pin "3") (pinfunction "C_3") (pintype "passive"))
      (node (ref "T275") (pin "3") (pinfunction "C_3") (pintype "passive"))
      (node (ref "T276") (pin "3") (pinfunction "C_3") (pintype "passive"))
      (node (ref "T277") (pin "3") (pinfunction "C_3") (pintype "passive"))
      (node (ref "T287") (pin "3") (pinfunction "C_3") (pintype "passive"))
      (node (ref "T289") (pin "3") (pinfunction "C_3") (pintype "passive"))
      (node (ref "T29") (pin "3") (pinfunction "C_3") (pintype "passive"))
      (node (ref "T290") (pin "3") (pinfunction "C_3") (pintype "passive"))
      (node (ref "T291") (pin "3") (pinfunction "C_3") (pintype "passive"))
      (node (ref "T292") (pin "3") (pinfunction "C_3") (pintype "passive"))
      (node (ref "T293") (pin "3") (pinfunction "C_3") (pintype "passive"))
      (node (ref "T294") (pin "3") (pinfunction "C_3") (pintype "passive"))
      (node (ref "T295") (pin "3") (pinfunction "C_3") (pintype "passive"))
      (node (ref "T296") (pin "3") (pinfunction "C_3") (pintype "passive"))
      (node (ref "T297") (pin "3") (pinfunction "C_3") (pintype "passive"))
      (node (ref "T298") (pin "3") (pinfunction "C_3") (pintype "passive"))
      (node (ref "T299") (pin "3") (pinfunction "C_3") (pintype "passive"))
      (node (ref "T3") (pin "3") (pinfunction "C_3") (pintype "passive"))
      (node (ref "T30") (pin "3") (pinfunction "C_3") (pintype "passive"))
      (node (ref "T300") (pin "3") (pinfunction "C_3") (pintype "passive"))
      (node (ref "T301") (pin "3") (pinfunction "C_3") (pintype "passive"))
      (node (ref "T302") (pin "3") (pinfunction "C_3") (pintype "passive"))
      (node (ref "T303") (pin "3") (pinfunction "C_3") (pintype "passive"))
      (node (ref "T31") (pin "3") (pinfunction "C_3") (pintype "passive"))
      (node (ref "T313") (pin "3") (pinfunction "C_3") (pintype "passive"))
      (node (ref "T315") (pin "3") (pinfunction "C_3") (pintype "passive"))
      (node (ref "T316") (pin "3") (pinfunction "C_3") (pintype "passive"))
      (node (ref "T317") (pin "3") (pinfunction "C_3") (pintype "passive"))
      (node (ref "T318") (pin "3") (pinfunction "C_3") (pintype "passive"))
      (node (ref "T319") (pin "3") (pinfunction "C_3") (pintype "passive"))
      (node (ref "T32") (pin "3") (pinfunction "C_3") (pintype "passive"))
      (node (ref "T320") (pin "3") (pinfunction "C_3") (pintype "passive"))
      (node (ref "T321") (pin "3") (pinfunction "C_3") (pintype "passive"))
      (node (ref "T322") (pin "3") (pinfunction "C_3") (pintype "passive"))
      (node (ref "T323") (pin "3") (pinfunction "C_3") (pintype "passive"))
      (node (ref "T324") (pin "3") (pinfunction "C_3") (pintype "passive"))
      (node (ref "T325") (pin "3") (pinfunction "C_3") (pintype "passive"))
      (node (ref "T326") (pin "3") (pinfunction "C_3") (pintype "passive"))
      (node (ref "T327") (pin "3") (pinfunction "C_3") (pintype "passive"))
      (node (ref "T328") (pin "3") (pinfunction "C_3") (pintype "passive"))
      (node (ref "T329") (pin "3") (pinfunction "C_3") (pintype "passive"))
      (node (ref "T33") (pin "3") (pinfunction "C_3") (pintype "passive"))
      (node (ref "T339") (pin "3") (pinfunction "C_3") (pintype "passive"))
      (node (ref "T34") (pin "3") (pinfunction "C_3") (pintype "passive"))
      (node (ref "T341") (pin "3") (pinfunction "C_3") (pintype "passive"))
      (node (ref "T342") (pin "3") (pinfunction "C_3") (pintype "passive"))
      (node (ref "T343") (pin "3") (pinfunction "C_3") (pintype "passive"))
      (node (ref "T344") (pin "3") (pinfunction "C_3") (pintype "passive"))
      (node (ref "T345") (pin "3") (pinfunction "C_3") (pintype "passive"))
      (node (ref "T346") (pin "3") (pinfunction "C_3") (pintype "passive"))
      (node (ref "T347") (pin "3") (pinfunction "C_3") (pintype "passive"))
      (node (ref "T348") (pin "3") (pinfunction "C_3") (pintype "passive"))
      (node (ref "T349") (pin "3") (pinfunction "C_3") (pintype "passive"))
      (node (ref "T35") (pin "3") (pinfunction "C_3") (pintype "passive"))
      (node (ref "T350") (pin "3") (pinfunction "C_3") (pintype "passive"))
      (node (ref "T351") (pin "3") (pinfunction "C_3") (pintype "passive"))
      (node (ref "T352") (pin "3") (pinfunction "C_3") (pintype "passive"))
      (node (ref "T353") (pin "3") (pinfunction "C_3") (pintype "passive"))
      (node (ref "T354") (pin "3") (pinfunction "C_3") (pintype "passive"))
      (node (ref "T355") (pin "3") (pinfunction "C_3") (pintype "passive"))
      (node (ref "T36") (pin "3") (pinfunction "C_3") (pintype "passive"))
      (node (ref "T365") (pin "3") (pinfunction "C_3") (pintype "passive"))
      (node (ref "T367") (pin "3") (pinfunction "C_3") (pintype "passive"))
      (node (ref "T368") (pin "3") (pinfunction "C_3") (pintype "passive"))
      (node (ref "T369") (pin "3") (pinfunction "C_3") (pintype "passive"))
      (node (ref "T37") (pin "3") (pinfunction "C_3") (pintype "passive"))
      (node (ref "T370") (pin "3") (pinfunction "C_3") (pintype "passive"))
      (node (ref "T371") (pin "3") (pinfunction "C_3") (pintype "passive"))
      (node (ref "T372") (pin "3") (pinfunction "C_3") (pintype "passive"))
      (node (ref "T373") (pin "3") (pinfunction "C_3") (pintype "passive"))
      (node (ref "T374") (pin "3") (pinfunction "C_3") (pintype "passive"))
      (node (ref "T375") (pin "3") (pinfunction "C_3") (pintype "passive"))
      (node (ref "T376") (pin "3") (pinfunction "C_3") (pintype "passive"))
      (node (ref "T377") (pin "3") (pinfunction "C_3") (pintype "passive"))
      (node (ref "T378") (pin "3") (pinfunction "C_3") (pintype "passive"))
      (node (ref "T379") (pin "3") (pinfunction "C_3") (pintype "passive"))
      (node (ref "T38") (pin "3") (pinfunction "C_3") (pintype "passive"))
      (node (ref "T380") (pin "3") (pinfunction "C_3") (pintype "passive"))
      (node (ref "T381") (pin "3") (pinfunction "C_3") (pintype "passive"))
      (node (ref "T39") (pin "3") (pinfunction "C_3") (pintype "passive"))
      (node (ref "T391") (pin "3") (pinfunction "C_3") (pintype "passive"))
      (node (ref "T393") (pin "3") (pinfunction "C_3") (pintype "passive"))
      (node (ref "T394") (pin "3") (pinfunction "C_3") (pintype "passive"))
      (node (ref "T395") (pin "3") (pinfunction "C_3") (pintype "passive"))
      (node (ref "T396") (pin "3") (pinfunction "C_3") (pintype "passive"))
      (node (ref "T397") (pin "3") (pinfunction "C_3") (pintype "passive"))
      (node (ref "T398") (pin "3") (pinfunction "C_3") (pintype "passive"))
      (node (ref "T399") (pin "3") (pinfunction "C_3") (pintype "passive"))
      (node (ref "T4") (pin "3") (pinfunction "C_3") (pintype "passive"))
      (node (ref "T40") (pin "3") (pinfunction "C_3") (pintype "passive"))
      (node (ref "T400") (pin "3") (pinfunction "C_3") (pintype "passive"))
      (node (ref "T401") (pin "3") (pinfunction "C_3") (pintype "passive"))
      (node (ref "T402") (pin "3") (pinfunction "C_3") (pintype "passive"))
      (node (ref "T403") (pin "3") (pinfunction "C_3") (pintype "passive"))
      (node (ref "T404") (pin "3") (pinfunction "C_3") (pintype "passive"))
      (node (ref "T405") (pin "3") (pinfunction "C_3") (pintype "passive"))
      (node (ref "T406") (pin "3") (pinfunction "C_3") (pintype "passive"))
      (node (ref "T407") (pin "3") (pinfunction "C_3") (pintype "passive"))
      (node (ref "T41") (pin "3") (pinfunction "C_3") (pintype "passive"))
      (node (ref "T42") (pin "3") (pinfunction "C_3") (pintype "passive"))
      (node (ref "T43") (pin "3") (pinfunction "C_3") (pintype "passive"))
      (node (ref "T5") (pin "3") (pinfunction "C_3") (pintype "passive"))
      (node (ref "T53") (pin "3") (pinfunction "C_3") (pintype "passive"))
      (node (ref "T55") (pin "3") (pinfunction "C_3") (pintype "passive"))
      (node (ref "T56") (pin "3") (pinfunction "C_3") (pintype "passive"))
      (node (ref "T57") (pin "3") (pinfunction "C_3") (pintype "passive"))
      (node (ref "T58") (pin "3") (pinfunction "C_3") (pintype "passive"))
      (node (ref "T59") (pin "3") (pinfunction "C_3") (pintype "passive"))
      (node (ref "T6") (pin "3") (pinfunction "C_3") (pintype "passive"))
      (node (ref "T60") (pin "3") (pinfunction "C_3") (pintype "passive"))
      (node (ref "T61") (pin "3") (pinfunction "C_3") (pintype "passive"))
      (node (ref "T62") (pin "3") (pinfunction "C_3") (pintype "passive"))
      (node (ref "T63") (pin "3") (pinfunction "C_3") (pintype "passive"))
      (node (ref "T64") (pin "3") (pinfunction "C_3") (pintype "passive"))
      (node (ref "T65") (pin "3") (pinfunction "C_3") (pintype "passive"))
      (node (ref "T66") (pin "3") (pinfunction "C_3") (pintype "passive"))
      (node (ref "T67") (pin "3") (pinfunction "C_3") (pintype "passive"))
      (node (ref "T68") (pin "3") (pinfunction "C_3") (pintype "passive"))
      (node (ref "T69") (pin "3") (pinfunction "C_3") (pintype "passive"))
      (node (ref "T7") (pin "3") (pinfunction "C_3") (pintype "passive"))
      (node (ref "T79") (pin "3") (pinfunction "C_3") (pintype "passive"))
      (node (ref "T8") (pin "3") (pinfunction "C_3") (pintype "passive"))
      (node (ref "T81") (pin "3") (pinfunction "C_3") (pintype "passive"))
      (node (ref "T82") (pin "3") (pinfunction "C_3") (pintype "passive"))
      (node (ref "T83") (pin "3") (pinfunction "C_3") (pintype "passive"))
      (node (ref "T84") (pin "3") (pinfunction "C_3") (pintype "passive"))
      (node (ref "T85") (pin "3") (pinfunction "C_3") (pintype "passive"))
      (node (ref "T86") (pin "3") (pinfunction "C_3") (pintype "passive"))
      (node (ref "T87") (pin "3") (pinfunction "C_3") (pintype "passive"))
      (node (ref "T88") (pin "3") (pinfunction "C_3") (pintype "passive"))
      (node (ref "T89") (pin "3") (pinfunction "C_3") (pintype "passive"))
      (node (ref "T9") (pin "3") (pinfunction "C_3") (pintype "passive"))
      (node (ref "T90") (pin "3") (pinfunction "C_3") (pintype "passive"))
      (node (ref "T91") (pin "3") (pinfunction "C_3") (pintype "passive"))
      (node (ref "T92") (pin "3") (pinfunction "C_3") (pintype "passive"))
      (node (ref "T93") (pin "3") (pinfunction "C_3") (pintype "passive"))
      (node (ref "T94") (pin "3") (pinfunction "C_3") (pintype "passive"))
      (node (ref "T95") (pin "3") (pinfunction "C_3") (pintype "passive"))
    )
    (net (code "34") (name "I0") (class "Default")
      (node (ref "T1") (pin "2") (pinfunction "B_2") (pintype "passive"))
      (node (ref "T105") (pin "2") (pinfunction "B_2") (pintype "passive"))
      (node (ref "T131") (pin "2") (pinfunction "B_2") (pintype "passive"))
      (node (ref "T157") (pin "2") (pinfunction "B_2") (pintype "passive"))
      (node (ref "T183") (pin "2") (pinfunction "B_2") (pintype "passive"))
      (node (ref "T209") (pin "2") (pinfunction "B_2") (pintype "passive"))
      (node (ref "T235") (pin "2") (pinfunction "B_2") (pintype "passive"))
      (node (ref "T261") (pin "2") (pinfunction "B_2") (pintype "passive"))
      (node (ref "T27") (pin "2") (pinfunction "B_2") (pintype "passive"))
      (node (ref "T287") (pin "2") (pinfunction "B_2") (pintype "passive"))
      (node (ref "T313") (pin "2") (pinfunction "B_2") (pintype "passive"))
      (node (ref "T339") (pin "2") (pinfunction "B_2") (pintype "passive"))
      (node (ref "T365") (pin "2") (pinfunction "B_2") (pintype "passive"))
      (node (ref "T391") (pin "2") (pinfunction "B_2") (pintype "passive"))
      (node (ref "T53") (pin "2") (pinfunction "B_2") (pintype "passive"))
      (node (ref "T79") (pin "2") (pinfunction "B_2") (pintype "passive"))
    )
    (net (code "35") (name "I1") (class "Default")
      (node (ref "T107") (pin "2") (pinfunction "B_2") (pintype "passive"))
      (node (ref "T133") (pin "2") (pinfunction "B_2") (pintype "passive"))
      (node (ref "T159") (pin "2") (pinfunction "B_2") (pintype "passive"))
      (node (ref "T185") (pin "2") (pinfunction "B_2") (pintype "passive"))
      (node (ref "T2") (pin "2") (pinfunction "B_2") (pintype "passive"))
      (node (ref "T211") (pin "2") (pinfunction "B_2") (pintype "passive"))
      (node (ref "T237") (pin "2") (pinfunction "B_2") (pintype "passive"))
      (node (ref "T263") (pin "2") (pinfunction "B_2") (pintype "passive"))
      (node (ref "T289") (pin "2") (pinfunction "B_2") (pintype "passive"))
      (node (ref "T29") (pin "2") (pinfunction "B_2") (pintype "passive"))
      (node (ref "T315") (pin "2") (pinfunction "B_2") (pintype "passive"))
      (node (ref "T341") (pin "2") (pinfunction "B_2") (pintype "passive"))
      (node (ref "T367") (pin "2") (pinfunction "B_2") (pintype "passive"))
      (node (ref "T393") (pin "2") (pinfunction "B_2") (pintype "passive"))
      (node (ref "T55") (pin "2") (pinfunction "B_2") (pintype "passive"))
      (node (ref "T81") (pin "2") (pinfunction "B_2") (pintype "passive"))
    )
    (net (code "36") (name "I2") (class "Default")
      (node (ref "T108") (pin "2") (pinfunction "B_2") (pintype "passive"))
      (node (ref "T134") (pin "2") (pinfunction "B_2") (pintype "passive"))
      (node (ref "T160") (pin "2") (pinfunction "B_2") (pintype "passive"))
      (node (ref "T186") (pin "2") (pinfunction "B_2") (pintype "passive"))
      (node (ref "T212") (pin "2") (pinfunction "B_2") (pintype "passive"))
      (node (ref "T238") (pin "2") (pinfunction "B_2") (pintype "passive"))
      (node (ref "T264") (pin "2") (pinfunction "B_2") (pintype "passive"))
      (node (ref "T290") (pin "2") (pinfunction "B_2") (pintype "passive"))
      (node (ref "T3") (pin "2") (pinfunction "B_2") (pintype "passive"))
      (node (ref "T30") (pin "2") (pinfunction "B_2") (pintype "passive"))
      (node (ref "T316") (pin "2") (pinfunction "B_2") (pintype "passive"))
      (node (ref "T342") (pin "2") (pinfunction "B_2") (pintype "passive"))
      (node (ref "T368") (pin "2") (pinfunction "B_2") (pintype "passive"))
      (node (ref "T394") (pin "2") (pinfunction "B_2") (pintype "passive"))
      (node (ref "T56") (pin "2") (pinfunction "B_2") (pintype "passive"))
      (node (ref "T82") (pin "2") (pinfunction "B_2") (pintype "passive"))
    )
    (net (code "37") (name "I3") (class "Default")
      (node (ref "T109") (pin "2") (pinfunction "B_2") (pintype "passive"))
      (node (ref "T135") (pin "2") (pinfunction "B_2") (pintype "passive"))
      (node (ref "T161") (pin "2") (pinfunction "B_2") (pintype "passive"))
      (node (ref "T187") (pin "2") (pinfunction "B_2") (pintype "passive"))
      (node (ref "T213") (pin "2") (pinfunction "B_2") (pintype "passive"))
      (node (ref "T239") (pin "2") (pinfunction "B_2") (pintype "passive"))
      (node (ref "T265") (pin "2") (pinfunction "B_2") (pintype "passive"))
      (node (ref "T291") (pin "2") (pinfunction "B_2") (pintype "passive"))
      (node (ref "T31") (pin "2") (pinfunction "B_2") (pintype "passive"))
      (node (ref "T317") (pin "2") (pinfunction "B_2") (pintype "passive"))
      (node (ref "T343") (pin "2") (pinfunction "B_2") (pintype "passive"))
      (node (ref "T369") (pin "2") (pinfunction "B_2") (pintype "passive"))
      (node (ref "T395") (pin "2") (pinfunction "B_2") (pintype "passive"))
      (node (ref "T4") (pin "2") (pinfunction "B_2") (pintype "passive"))
      (node (ref "T57") (pin "2") (pinfunction "B_2") (pintype "passive"))
      (node (ref "T83") (pin "2") (pinfunction "B_2") (pintype "passive"))
    )
    (net (code "38") (name "I4") (class "Default")
      (node (ref "T110") (pin "2") (pinfunction "B_2") (pintype "passive"))
      (node (ref "T136") (pin "2") (pinfunction "B_2") (pintype "passive"))
      (node (ref "T162") (pin "2") (pinfunction "B_2") (pintype "passive"))
      (node (ref "T188") (pin "2") (pinfunction "B_2") (pintype "passive"))
      (node (ref "T214") (pin "2") (pinfunction "B_2") (pintype "passive"))
      (node (ref "T240") (pin "2") (pinfunction "B_2") (pintype "passive"))
      (node (ref "T266") (pin "2") (pinfunction "B_2") (pintype "passive"))
      (node (ref "T292") (pin "2") (pinfunction "B_2") (pintype "passive"))
      (node (ref "T318") (pin "2") (pinfunction "B_2") (pintype "passive"))
      (node (ref "T32") (pin "2") (pinfunction "B_2") (pintype "passive"))
      (node (ref "T344") (pin "2") (pinfunction "B_2") (pintype "passive"))
      (node (ref "T370") (pin "2") (pinfunction "B_2") (pintype "passive"))
      (node (ref "T396") (pin "2") (pinfunction "B_2") (pintype "passive"))
      (node (ref "T5") (pin "2") (pinfunction "B_2") (pintype "passive"))
      (node (ref "T58") (pin "2") (pinfunction "B_2") (pintype "passive"))
      (node (ref "T84") (pin "2") (pinfunction "B_2") (pintype "passive"))
    )
    (net (code "39") (name "I5") (class "Default")
      (node (ref "T111") (pin "2") (pinfunction "B_2") (pintype "passive"))
      (node (ref "T137") (pin "2") (pinfunction "B_2") (pintype "passive"))
      (node (ref "T163") (pin "2") (pinfunction "B_2") (pintype "passive"))
      (node (ref "T189") (pin "2") (pinfunction "B_2") (pintype "passive"))
      (node (ref "T215") (pin "2") (pinfunction "B_2") (pintype "passive"))
      (node (ref "T241") (pin "2") (pinfunction "B_2") (pintype "passive"))
      (node (ref "T267") (pin "2") (pinfunction "B_2") (pintype "passive"))
      (node (ref "T293") (pin "2") (pinfunction "B_2") (pintype "passive"))
      (node (ref "T319") (pin "2") (pinfunction "B_2") (pintype "passive"))
      (node (ref "T33") (pin "2") (pinfunction "B_2") (pintype "passive"))
      (node (ref "T345") (pin "2") (pinfunction "B_2") (pintype "passive"))
      (node (ref "T371") (pin "2") (pinfunction "B_2") (pintype "passive"))
      (node (ref "T397") (pin "2") (pinfunction "B_2") (pintype "passive"))
      (node (ref "T59") (pin "2") (pinfunction "B_2") (pintype "passive"))
      (node (ref "T6") (pin "2") (pinfunction "B_2") (pintype "passive"))
      (node (ref "T85") (pin "2") (pinfunction "B_2") (pintype "passive"))
    )
    (net (code "40") (name "I6") (class "Default")
      (node (ref "T112") (pin "2") (pinfunction "B_2") (pintype "passive"))
      (node (ref "T138") (pin "2") (pinfunction "B_2") (pintype "passive"))
      (node (ref "T164") (pin "2") (pinfunction "B_2") (pintype "passive"))
      (node (ref "T190") (pin "2") (pinfunction "B_2") (pintype "passive"))
      (node (ref "T216") (pin "2") (pinfunction "B_2") (pintype "passive"))
      (node (ref "T242") (pin "2") (pinfunction "B_2") (pintype "passive"))
      (node (ref "T268") (pin "2") (pinfunction "B_2") (pintype "passive"))
      (node (ref "T294") (pin "2") (pinfunction "B_2") (pintype "passive"))
      (node (ref "T320") (pin "2") (pinfunction "B_2") (pintype "passive"))
      (node (ref "T34") (pin "2") (pinfunction "B_2") (pintype "passive"))
      (node (ref "T346") (pin "2") (pinfunction "B_2") (pintype "passive"))
      (node (ref "T372") (pin "2") (pinfunction "B_2") (pintype "passive"))
      (node (ref "T398") (pin "2") (pinfunction "B_2") (pintype "passive"))
      (node (ref "T60") (pin "2") (pinfunction "B_2") (pintype "passive"))
      (node (ref "T7") (pin "2") (pinfunction "B_2") (pintype "passive"))
      (node (ref "T86") (pin "2") (pinfunction "B_2") (pintype "passive"))
    )
    (net (code "41") (name "I7") (class "Default")
      (node (ref "T113") (pin "2") (pinfunction "B_2") (pintype "passive"))
      (node (ref "T139") (pin "2") (pinfunction "B_2") (pintype "passive"))
      (node (ref "T165") (pin "2") (pinfunction "B_2") (pintype "passive"))
      (node (ref "T191") (pin "2") (pinfunction "B_2") (pintype "passive"))
      (node (ref "T217") (pin "2") (pinfunction "B_2") (pintype "passive"))
      (node (ref "T243") (pin "2") (pinfunction "B_2") (pintype "passive"))
      (node (ref "T269") (pin "2") (pinfunction "B_2") (pintype "passive"))
      (node (ref "T295") (pin "2") (pinfunction "B_2") (pintype "passive"))
      (node (ref "T321") (pin "2") (pinfunction "B_2") (pintype "passive"))
      (node (ref "T347") (pin "2") (pinfunction "B_2") (pintype "passive"))
      (node (ref "T35") (pin "2") (pinfunction "B_2") (pintype "passive"))
      (node (ref "T373") (pin "2") (pinfunction "B_2") (pintype "passive"))
      (node (ref "T399") (pin "2") (pinfunction "B_2") (pintype "passive"))
      (node (ref "T61") (pin "2") (pinfunction "B_2") (pintype "passive"))
      (node (ref "T8") (pin "2") (pinfunction "B_2") (pintype "passive"))
      (node (ref "T87") (pin "2") (pinfunction "B_2") (pintype "passive"))
    )
    (net (code "42") (name "I8") (class "Default")
      (node (ref "T114") (pin "2") (pinfunction "B_2") (pintype "passive"))
      (node (ref "T140") (pin "2") (pinfunction "B_2") (pintype "passive"))
      (node (ref "T166") (pin "2") (pinfunction "B_2") (pintype "passive"))
      (node (ref "T192") (pin "2") (pinfunction "B_2") (pintype "passive"))
      (node (ref "T218") (pin "2") (pinfunction "B_2") (pintype "passive"))
      (node (ref "T244") (pin "2") (pinfunction "B_2") (pintype "passive"))
      (node (ref "T270") (pin "2") (pinfunction "B_2") (pintype "passive"))
      (node (ref "T296") (pin "2") (pinfunction "B_2") (pintype "passive"))
      (node (ref "T322") (pin "2") (pinfunction "B_2") (pintype "passive"))
      (node (ref "T348") (pin "2") (pinfunction "B_2") (pintype "passive"))
      (node (ref "T36") (pin "2") (pinfunction "B_2") (pintype "passive"))
      (node (ref "T374") (pin "2") (pinfunction "B_2") (pintype "passive"))
      (node (ref "T400") (pin "2") (pinfunction "B_2") (pintype "passive"))
      (node (ref "T62") (pin "2") (pinfunction "B_2") (pintype "passive"))
      (node (ref "T88") (pin "2") (pinfunction "B_2") (pintype "passive"))
      (node (ref "T9") (pin "2") (pinfunction "B_2") (pintype "passive"))
    )
    (net (code "43") (name "I9") (class "Default")
      (node (ref "T10") (pin "2") (pinfunction "B_2") (pintype "passive"))
      (node (ref "T115") (pin "2") (pinfunction "B_2") (pintype "passive"))
      (node (ref "T141") (pin "2") (pinfunction "B_2") (pintype "passive"))
      (node (ref "T167") (pin "2") (pinfunction "B_2") (pintype "passive"))
      (node (ref "T193") (pin "2") (pinfunction "B_2") (pintype "passive"))
      (node (ref "T219") (pin "2") (pinfunction "B_2") (pintype "passive"))
      (node (ref "T245") (pin "2") (pinfunction "B_2") (pintype "passive"))
      (node (ref "T271") (pin "2") (pinfunction "B_2") (pintype "passive"))
      (node (ref "T297") (pin "2") (pinfunction "B_2") (pintype "passive"))
      (node (ref "T323") (pin "2") (pinfunction "B_2") (pintype "passive"))
      (node (ref "T349") (pin "2") (pinfunction "B_2") (pintype "passive"))
      (node (ref "T37") (pin "2") (pinfunction "B_2") (pintype "passive"))
      (node (ref "T375") (pin "2") (pinfunction "B_2") (pintype "passive"))
      (node (ref "T401") (pin "2") (pinfunction "B_2") (pintype "passive"))
      (node (ref "T63") (pin "2") (pinfunction "B_2") (pintype "passive"))
      (node (ref "T89") (pin "2") (pinfunction "B_2") (pintype "passive"))
    )
    (net (code "44") (name "I10") (class "Default")
      (node (ref "T11") (pin "2") (pinfunction "B_2") (pintype "passive"))
      (node (ref "T116") (pin "2") (pinfunction "B_2") (pintype "passive"))
      (node (ref "T142") (pin "2") (pinfunction "B_2") (pintype "passive"))
      (node (ref "T168") (pin "2") (pinfunction "B_2") (pintype "passive"))
      (node (ref "T194") (pin "2") (pinfunction "B_2") (pintype "passive"))
      (node (ref "T220") (pin "2") (pinfunction "B_2") (pintype "passive"))
      (node (ref "T246") (pin "2") (pinfunction "B_2") (pintype "passive"))
      (node (ref "T272") (pin "2") (pinfunction "B_2") (pintype "passive"))
      (node (ref "T298") (pin "2") (pinfunction "B_2") (pintype "passive"))
      (node (ref "T324") (pin "2") (pinfunction "B_2") (pintype "passive"))
      (node (ref "T350") (pin "2") (pinfunction "B_2") (pintype "passive"))
      (node (ref "T376") (pin "2") (pinfunction "B_2") (pintype "passive"))
      (node (ref "T38") (pin "2") (pinfunction "B_2") (pintype "passive"))
      (node (ref "T402") (pin "2") (pinfunction "B_2") (pintype "passive"))
      (node (ref "T64") (pin "2") (pinfunction "B_2") (pintype "passive"))
      (node (ref "T90") (pin "2") (pinfunction "B_2") (pintype "passive"))
    )
    (net (code "45") (name "I11") (class "Default")
      (node (ref "T117") (pin "2") (pinfunction "B_2") (pintype "passive"))
      (node (ref "T12") (pin "2") (pinfunction "B_2") (pintype "passive"))
      (node (ref "T143") (pin "2") (pinfunction "B_2") (pintype "passive"))
      (node (ref "T169") (pin "2") (pinfunction "B_2") (pintype "passive"))
      (node (ref "T195") (pin "2") (pinfunction "B_2") (pintype "passive"))
      (node (ref "T221") (pin "2") (pinfunction "B_2") (pintype "passive"))
      (node (ref "T247") (pin "2") (pinfunction "B_2") (pintype "passive"))
      (node (ref "T273") (pin "2") (pinfunction "B_2") (pintype "passive"))
      (node (ref "T299") (pin "2") (pinfunction "B_2") (pintype "passive"))
      (node (ref "T325") (pin "2") (pinfunction "B_2") (pintype "passive"))
      (node (ref "T351") (pin "2") (pinfunction "B_2") (pintype "passive"))
      (node (ref "T377") (pin "2") (pinfunction "B_2") (pintype "passive"))
      (node (ref "T39") (pin "2") (pinfunction "B_2") (pintype "passive"))
      (node (ref "T403") (pin "2") (pinfunction "B_2") (pintype "passive"))
      (node (ref "T65") (pin "2") (pinfunction "B_2") (pintype "passive"))
      (node (ref "T91") (pin "2") (pinfunction "B_2") (pintype "passive"))
    )
    (net (code "46") (name "I12") (class "Default")
      (node (ref "T118") (pin "2") (pinfunction "B_2") (pintype "passive"))
      (node (ref "T13") (pin "2") (pinfunction "B_2") (pintype "passive"))
      (node (ref "T144") (pin "2") (pinfunction "B_2") (pintype "passive"))
      (node (ref "T170") (pin "2") (pinfunction "B_2") (pintype "passive"))
      (node (ref "T196") (pin "2") (pinfunction "B_2") (pintype "passive"))
      (node (ref "T222") (pin "2") (pinfunction "B_2") (pintype "passive"))
      (node (ref "T248") (pin "2") (pinfunction "B_2") (pintype "passive"))
      (node (ref "T274") (pin "2") (pinfunction "B_2") (pintype "passive"))
      (node (ref "T300") (pin "2") (pinfunction "B_2") (pintype "passive"))
      (node (ref "T326") (pin "2") (pinfunction "B_2") (pintype "passive"))
      (node (ref "T352") (pin "2") (pinfunction "B_2") (pintype "passive"))
      (node (ref "T378") (pin "2") (pinfunction "B_2") (pintype "passive"))
      (node (ref "T40") (pin "2") (pinfunction "B_2") (pintype "passive"))
      (node (ref "T404") (pin "2") (pinfunction "B_2") (pintype "passive"))
      (node (ref "T66") (pin "2") (pinfunction "B_2") (pintype "passive"))
      (node (ref "T92") (pin "2") (pinfunction "B_2") (pintype "passive"))
    )
    (net (code "47") (name "I13") (class "Default")
      (node (ref "T119") (pin "2") (pinfunction "B_2") (pintype "passive"))
      (node (ref "T14") (pin "2") (pinfunction "B_2") (pintype "passive"))
      (node (ref "T145") (pin "2") (pinfunction "B_2") (pintype "passive"))
      (node (ref "T171") (pin "2") (pinfunction "B_2") (pintype "passive"))
      (node (ref "T197") (pin "2") (pinfunction "B_2") (pintype "passive"))
      (node (ref "T223") (pin "2") (pinfunction "B_2") (pintype "passive"))
      (node (ref "T249") (pin "2") (pinfunction "B_2") (pintype "passive"))
      (node (ref "T275") (pin "2") (pinfunction "B_2") (pintype "passive"))
      (node (ref "T301") (pin "2") (pinfunction "B_2") (pintype "passive"))
      (node (ref "T327") (pin "2") (pinfunction "B_2") (pintype "passive"))
      (node (ref "T353") (pin "2") (pinfunction "B_2") (pintype "passive"))
      (node (ref "T379") (pin "2") (pinfunction "B_2") (pintype "passive"))
      (node (ref "T405") (pin "2") (pinfunction "B_2") (pintype "passive"))
      (node (ref "T41") (pin "2") (pinfunction "B_2") (pintype "passive"))
      (node (ref "T67") (pin "2") (pinfunction "B_2") (pintype "passive"))
      (node (ref "T93") (pin "2") (pinfunction "B_2") (pintype "passive"))
    )
    (net (code "48") (name "I14") (class "Default")
      (node (ref "T120") (pin "2") (pinfunction "B_2") (pintype "passive"))
      (node (ref "T146") (pin "2") (pinfunction "B_2") (pintype "passive"))
      (node (ref "T15") (pin "2") (pinfunction "B_2") (pintype "passive"))
      (node (ref "T172") (pin "2") (pinfunction "B_2") (pintype "passive"))
      (node (ref "T198") (pin "2") (pinfunction "B_2") (pintype "passive"))
      (node (ref "T224") (pin "2") (pinfunction "B_2") (pintype "passive"))
      (node (ref "T250") (pin "2") (pinfunction "B_2") (pintype "passive"))
      (node (ref "T276") (pin "2") (pinfunction "B_2") (pintype "passive"))
      (node (ref "T302") (pin "2") (pinfunction "B_2") (pintype "passive"))
      (node (ref "T328") (pin "2") (pinfunction "B_2") (pintype "passive"))
      (node (ref "T354") (pin "2") (pinfunction "B_2") (pintype "passive"))
      (node (ref "T380") (pin "2") (pinfunction "B_2") (pintype "passive"))
      (node (ref "T406") (pin "2") (pinfunction "B_2") (pintype "passive"))
      (node (ref "T42") (pin "2") (pinfunction "B_2") (pintype "passive"))
      (node (ref "T68") (pin "2") (pinfunction "B_2") (pintype "passive"))
      (node (ref "T94") (pin "2") (pinfunction "B_2") (pintype "passive"))
    )
    (net (code "49") (name "I15") (class "Default")
      (node (ref "T121") (pin "2") (pinfunction "B_2") (pintype "passive"))
      (node (ref "T147") (pin "2") (pinfunction "B_2") (pintype "passive"))
      (node (ref "T16") (pin "2") (pinfunction "B_2") (pintype "passive"))
      (node (ref "T173") (pin "2") (pinfunction "B_2") (pintype "passive"))
      (node (ref "T199") (pin "2") (pinfunction "B_2") (pintype "passive"))
      (node (ref "T225") (pin "2") (pinfunction "B_2") (pintype "passive"))
      (node (ref "T251") (pin "2") (pinfunction "B_2") (pintype "passive"))
      (node (ref "T277") (pin "2") (pinfunction "B_2") (pintype "passive"))
      (node (ref "T303") (pin "2") (pinfunction "B_2") (pintype "passive"))
      (node (ref "T329") (pin "2") (pinfunction "B_2") (pintype "passive"))
      (node (ref "T355") (pin "2") (pinfunction "B_2") (pintype "passive"))
      (node (ref "T381") (pin "2") (pinfunction "B_2") (pintype "passive"))
      (node (ref "T407") (pin "2") (pinfunction "B_2") (pintype "passive"))
      (node (ref "T43") (pin "2") (pinfunction "B_2") (pintype "passive"))
      (node (ref "T69") (pin "2") (pinfunction "B_2") (pintype "passive"))
      (node (ref "T95") (pin "2") (pinfunction "B_2") (pintype "passive"))
    )
    (net (code "50") (name "Net-(T1-E)") (class "Default")
      (node (ref "J1") (pin "2") (pinfunction "2_2") (pintype "passive"))
      (node (ref "T1") (pin "1") (pinfunction "E_1") (pintype "passive"))
    )
    (net (code "51") (name "Net-(T2-E)") (class "Default")
      (node (ref "J2") (pin "2") (pinfunction "2_2") (pintype "passive"))
      (node (ref "T2") (pin "1") (pinfunction "E_1") (pintype "passive"))
    )
    (net (code "52") (name "Net-(T3-E)") (class "Default")
      (node (ref "J3") (pin "2") (pinfunction "2_2") (pintype "passive"))
      (node (ref "T3") (pin "1") (pinfunction "E_1") (pintype "passive"))
    )
    (net (code "53") (name "Net-(T4-E)") (class "Default")
      (node (ref "J4") (pin "2") (pinfunction "2_2") (pintype "passive"))
      (node (ref "T4") (pin "1") (pinfunction "E_1") (pintype "passive"))
    )
    (net (code "54") (name "Net-(T5-E)") (class "Default")
      (node (ref "J5") (pin "2") (pinfunction "2_2") (pintype "passive"))
      (node (ref "T5") (pin "1") (pinfunction "E_1") (pintype "passive"))
    )
    (net (code "55") (name "Net-(T6-E)") (class "Default")
      (node (ref "J6") (pin "2") (pinfunction "2_2") (pintype "passive"))
      (node (ref "T6") (pin "1") (pinfunction "E_1") (pintype "passive"))
    )
    (net (code "56") (name "Net-(T7-E)") (class "Default")
      (node (ref "J7") (pin "2") (pinfunction "2_2") (pintype "passive"))
      (node (ref "T7") (pin "1") (pinfunction "E_1") (pintype "passive"))
    )
    (net (code "57") (name "Net-(T8-E)") (class "Default")
      (node (ref "J8") (pin "2") (pinfunction "2_2") (pintype "passive"))
      (node (ref "T8") (pin "1") (pinfunction "E_1") (pintype "passive"))
    )
    (net (code "58") (name "Net-(T9-E)") (class "Default")
      (node (ref "J9") (pin "2") (pinfunction "2_2") (pintype "passive"))
      (node (ref "T9") (pin "1") (pinfunction "E_1") (pintype "passive"))
    )
    (net (code "59") (name "Net-(T10-E)") (class "Default")
      (node (ref "J10") (pin "2") (pinfunction "2_2") (pintype "passive"))
      (node (ref "T10") (pin "1") (pinfunction "E_1") (pintype "passive"))
    )
    (net (code "60") (name "Net-(T11-E)") (class "Default")
      (node (ref "J11") (pin "2") (pinfunction "2_2") (pintype "passive"))
      (node (ref "T11") (pin "1") (pinfunction "E_1") (pintype "passive"))
    )
    (net (code "61") (name "Net-(T12-E)") (class "Default")
      (node (ref "J12") (pin "2") (pinfunction "2_2") (pintype "passive"))
      (node (ref "T12") (pin "1") (pinfunction "E_1") (pintype "passive"))
    )
    (net (code "62") (name "Net-(T13-E)") (class "Default")
      (node (ref "J13") (pin "2") (pinfunction "2_2") (pintype "passive"))
      (node (ref "T13") (pin "1") (pinfunction "E_1") (pintype "passive"))
    )
    (net (code "63") (name "Net-(T14-E)") (class "Default")
      (node (ref "J14") (pin "2") (pinfunction "2_2") (pintype "passive"))
      (node (ref "T14") (pin "1") (pinfunction "E_1") (pintype "passive"))
    )
    (net (code "64") (name "Net-(T15-E)") (class "Default")
      (node (ref "J15") (pin "2") (pinfunction "2_2") (pintype "passive"))
      (node (ref "T15") (pin "1") (pinfunction "E_1") (pintype "passive"))
    )
    (net (code "65") (name "Net-(T16-E)") (class "Default")
      (node (ref "J16") (pin "2") (pinfunction "2_2") (pintype "passive"))
      (node (ref "T16") (pin "1") (pinfunction "E_1") (pintype "passive"))
    )
    (net (code "66") (name "Net-(T17-B)") (class "Default")
      (node (ref "J1") (pin "1") (pinfunction "1_1") (pintype "passive"))
      (node (ref "J10") (pin "1") (pinfunction "1_1") (pintype "passive"))
      (node (ref "J11") (pin "1") (pinfunction "1_1") (pintype "passive"))
      (node (ref "J12") (pin "1") (pinfunction "1_1") (pintype "passive"))
      (node (ref "J13") (pin "1") (pinfunction "1_1") (pintype "passive"))
      (node (ref "J14") (pin "1") (pinfunction "1_1") (pintype "passive"))
      (node (ref "J15") (pin "1") (pinfunction "1_1") (pintype "passive"))
      (node (ref "J16") (pin "1") (pinfunction "1_1") (pintype "passive"))
      (node (ref "J2") (pin "1") (pinfunction "1_1") (pintype "passive"))
      (node (ref "J3") (pin "1") (pinfunction "1_1") (pintype "passive"))
      (node (ref "J4") (pin "1") (pinfunction "1_1") (pintype "passive"))
      (node (ref "J5") (pin "1") (pinfunction "1_1") (pintype "passive"))
      (node (ref "J6") (pin "1") (pinfunction "1_1") (pintype "passive"))
      (node (ref "J7") (pin "1") (pinfunction "1_1") (pintype "passive"))
      (node (ref "J8") (pin "1") (pinfunction "1_1") (pintype "passive"))
      (node (ref "J9") (pin "1") (pinfunction "1_1") (pintype "passive"))
      (node (ref "R3") (pin "2") (pinfunction "2_2") (pintype "passive"))
      (node (ref "T17") (pin "2") (pinfunction "B_2") (pintype "passive"))
      (node (ref "T18") (pin "2") (pinfunction "B_2") (pintype "passive"))
      (node (ref "T19") (pin "2") (pinfunction "B_2") (pintype "passive"))
      (node (ref "T20") (pin "2") (pinfunction "B_2") (pintype "passive"))
      (node (ref "T21") (pin "2") (pinfunction "B_2") (pintype "passive"))
      (node (ref "T22") (pin "2") (pinfunction "B_2") (pintype "passive"))
      (node (ref "T23") (pin "2") (pinfunction "B_2") (pintype "passive"))
      (node (ref "T24") (pin "2") (pinfunction "B_2") (pintype "passive"))
      (node (ref "T25") (pin "2") (pinfunction "B_2") (pintype "passive"))
      (node (ref "T26") (pin "2") (pinfunction "B_2") (pintype "passive"))
    )
    (net (code "67") (name "Net-(T17-E)") (class "Default")
      (node (ref "J17") (pin "2") (pinfunction "2_2") (pintype "passive"))
      (node (ref "T17") (pin "1") (pinfunction "E_1") (pintype "passive"))
    )
    (net (code "68") (name "Net-(T18-E)") (class "Default")
      (node (ref "J18") (pin "2") (pinfunction "2_2") (pintype "passive"))
      (node (ref "T18") (pin "1") (pinfunction "E_1") (pintype "passive"))
    )
    (net (code "69") (name "Net-(T19-E)") (class "Default")
      (node (ref "J19") (pin "2") (pinfunction "2_2") (pintype "passive"))
      (node (ref "T19") (pin "1") (pinfunction "E_1") (pintype "passive"))
    )
    (net (code "70") (name "Net-(T20-E)") (class "Default")
      (node (ref "J20") (pin "2") (pinfunction "2_2") (pintype "passive"))
      (node (ref "T20") (pin "1") (pinfunction "E_1") (pintype "passive"))
    )
    (net (code "71") (name "Net-(T21-E)") (class "Default")
      (node (ref "J21") (pin "2") (pinfunction "2_2") (pintype "passive"))
      (node (ref "T21") (pin "1") (pinfunction "E_1") (pintype "passive"))
    )
    (net (code "72") (name "Net-(T22-E)") (class "Default")
      (node (ref "J22") (pin "2") (pinfunction "2_2") (pintype "passive"))
      (node (ref "T22") (pin "1") (pinfunction "E_1") (pintype "passive"))
    )
    (net (code "73") (name "Net-(T23-E)") (class "Default")
      (node (ref "J23") (pin "2") (pinfunction "2_2") (pintype "passive"))
      (node (ref "T23") (pin "1") (pinfunction "E_1") (pintype "passive"))
    )
    (net (code "74") (name "Net-(T24-E)") (class "Default")
      (node (ref "J24") (pin "2") (pinfunction "2_2") (pintype "passive"))
      (node (ref "T24") (pin "1") (pinfunction "E_1") (pintype "passive"))
    )
    (net (code "75") (name "Net-(T25-E)") (class "Default")
      (node (ref "J25") (pin "2") (pinfunction "2_2") (pintype "passive"))
      (node (ref "T25") (pin "1") (pinfunction "E_1") (pintype "passive"))
    )
    (net (code "76") (name "Net-(T26-E)") (class "Default")
      (node (ref "J26") (pin "2") (pinfunction "2_2") (pintype "passive"))
      (node (ref "T26") (pin "1") (pinfunction "E_1") (pintype "passive"))
    )
    (net (code "77") (name "Net-(T27-E)") (class "Default")
      (node (ref "J27") (pin "2") (pinfunction "2_2") (pintype "passive"))
      (node (ref "T27") (pin "1") (pinfunction "E_1") (pintype "passive"))
    )
    (net (code "78") (name "Net-(T28-B)") (class "Default")
      (node (ref "J27") (pin "1") (pinfunction "1_1") (pintype "passive"))
      (node (ref "J28") (pin "1") (pinfunction "1_1") (pintype "passive"))
      (node (ref "J29") (pin "1") (pinfunction "1_1") (pintype "passive"))
      (node (ref "J30") (pin "1") (pinfunction "1_1") (pintype "passive"))
      (node (ref "J31") (pin "1") (pinfunction "1_1") (pintype "passive"))
      (node (ref "J32") (pin "1") (pinfunction "1_1") (pintype "passive"))
      (node (ref "J33") (pin "1") (pinfunction "1_1") (pintype "passive"))
      (node (ref "J34") (pin "1") (pinfunction "1_1") (pintype "passive"))
      (node (ref "J35") (pin "1") (pinfunction "1_1") (pintype "passive"))
      (node (ref "J36") (pin "1") (pinfunction "1_1") (pintype "passive"))
      (node (ref "J37") (pin "1") (pinfunction "1_1") (pintype "passive"))
      (node (ref "J38") (pin "1") (pinfunction "1_1") (pintype "passive"))
      (node (ref "J39") (pin "1") (pinfunction "1_1") (pintype "passive"))
      (node (ref "J40") (pin "1") (pinfunction "1_1") (pintype "passive"))
      (node (ref "J41") (pin "1") (pinfunction "1_1") (pintype "passive"))
      (node (ref "J42") (pin "1") (pinfunction "1_1") (pintype "passive"))
      (node (ref "R1") (pin "2") (pinfunction "2_2") (pintype "passive"))
      (node (ref "T28") (pin "2") (pinfunction "B_2") (pintype "passive"))
      (node (ref "T44") (pin "2") (pinfunction "B_2") (pintype "passive"))
      (node (ref "T45") (pin "2") (pinfunction "B_2") (pintype "passive"))
      (node (ref "T46") (pin "2") (pinfunction "B_2") (pintype "passive"))
      (node (ref "T47") (pin "2") (pinfunction "B_2") (pintype "passive"))
      (node (ref "T48") (pin "2") (pinfunction "B_2") (pintype "passive"))
      (node (ref "T49") (pin "2") (pinfunction "B_2") (pintype "passive"))
      (node (ref "T50") (pin "2") (pinfunction "B_2") (pintype "passive"))
      (node (ref "T51") (pin "2") (pinfunction "B_2") (pintype "passive"))
      (node (ref "T52") (pin "2") (pinfunction "B_2") (pintype "passive"))
    )
    (net (code "79") (name "Net-(T28-E)") (class "Default")
      (node (ref "J43") (pin "2") (pinfunction "2_2") (pintype "passive"))
      (node (ref "T28") (pin "1") (pinfunction "E_1") (pintype "passive"))
    )
    (net (code "80") (name "Net-(T29-E)") (class "Default")
      (node (ref "J28") (pin "2") (pinfunction "2_2") (pintype "passive"))
      (node (ref "T29") (pin "1") (pinfunction "E_1") (pintype "passive"))
    )
    (net (code "81") (name "Net-(T30-E)") (class "Default")
      (node (ref "J29") (pin "2") (pinfunction "2_2") (pintype "passive"))
      (node (ref "T30") (pin "1") (pinfunction "E_1") (pintype "passive"))
    )
    (net (code "82") (name "Net-(T31-E)") (class "Default")
      (node (ref "J30") (pin "2") (pinfunction "2_2") (pintype "passive"))
      (node (ref "T31") (pin "1") (pinfunction "E_1") (pintype "passive"))
    )
    (net (code "83") (name "Net-(T32-E)") (class "Default")
      (node (ref "J31") (pin "2") (pinfunction "2_2") (pintype "passive"))
      (node (ref "T32") (pin "1") (pinfunction "E_1") (pintype "passive"))
    )
    (net (code "84") (name "Net-(T33-E)") (class "Default")
      (node (ref "J32") (pin "2") (pinfunction "2_2") (pintype "passive"))
      (node (ref "T33") (pin "1") (pinfunction "E_1") (pintype "passive"))
    )
    (net (code "85") (name "Net-(T34-E)") (class "Default")
      (node (ref "J33") (pin "2") (pinfunction "2_2") (pintype "passive"))
      (node (ref "T34") (pin "1") (pinfunction "E_1") (pintype "passive"))
    )
    (net (code "86") (name "Net-(T35-E)") (class "Default")
      (node (ref "J34") (pin "2") (pinfunction "2_2") (pintype "passive"))
      (node (ref "T35") (pin "1") (pinfunction "E_1") (pintype "passive"))
    )
    (net (code "87") (name "Net-(T36-E)") (class "Default")
      (node (ref "J35") (pin "2") (pinfunction "2_2") (pintype "passive"))
      (node (ref "T36") (pin "1") (pinfunction "E_1") (pintype "passive"))
    )
    (net (code "88") (name "Net-(T37-E)") (class "Default")
      (node (ref "J36") (pin "2") (pinfunction "2_2") (pintype "passive"))
      (node (ref "T37") (pin "1") (pinfunction "E_1") (pintype "passive"))
    )
    (net (code "89") (name "Net-(T38-E)") (class "Default")
      (node (ref "J37") (pin "2") (pinfunction "2_2") (pintype "passive"))
      (node (ref "T38") (pin "1") (pinfunction "E_1") (pintype "passive"))
    )
    (net (code "90") (name "Net-(T39-E)") (class "Default")
      (node (ref "J38") (pin "2") (pinfunction "2_2") (pintype "passive"))
      (node (ref "T39") (pin "1") (pinfunction "E_1") (pintype "passive"))
    )
    (net (code "91") (name "Net-(T40-E)") (class "Default")
      (node (ref "J39") (pin "2") (pinfunction "2_2") (pintype "passive"))
      (node (ref "T40") (pin "1") (pinfunction "E_1") (pintype "passive"))
    )
    (net (code "92") (name "Net-(T41-E)") (class "Default")
      (node (ref "J40") (pin "2") (pinfunction "2_2") (pintype "passive"))
      (node (ref "T41") (pin "1") (pinfunction "E_1") (pintype "passive"))
    )
    (net (code "93") (name "Net-(T42-E)") (class "Default")
      (node (ref "J41") (pin "2") (pinfunction "2_2") (pintype "passive"))
      (node (ref "T42") (pin "1") (pinfunction "E_1") (pintype "passive"))
    )
    (net (code "94") (name "Net-(T43-E)") (class "Default")
      (node (ref "J42") (pin "2") (pinfunction "2_2") (pintype "passive"))
      (node (ref "T43") (pin "1") (pinfunction "E_1") (pintype "passive"))
    )
    (net (code "95") (name "Net-(T44-E)") (class "Default")
      (node (ref "J44") (pin "2") (pinfunction "2_2") (pintype "passive"))
      (node (ref "T44") (pin "1") (pinfunction "E_1") (pintype "passive"))
    )
    (net (code "96") (name "Net-(T45-E)") (class "Default")
      (node (ref "J45") (pin "2") (pinfunction "2_2") (pintype "passive"))
      (node (ref "T45") (pin "1") (pinfunction "E_1") (pintype "passive"))
    )
    (net (code "97") (name "Net-(T46-E)") (class "Default")
      (node (ref "J46") (pin "2") (pinfunction "2_2") (pintype "passive"))
      (node (ref "T46") (pin "1") (pinfunction "E_1") (pintype "passive"))
    )
    (net (code "98") (name "Net-(T47-E)") (class "Default")
      (node (ref "J47") (pin "2") (pinfunction "2_2") (pintype "passive"))
      (node (ref "T47") (pin "1") (pinfunction "E_1") (pintype "passive"))
    )
    (net (code "99") (name "Net-(T48-E)") (class "Default")
      (node (ref "J48") (pin "2") (pinfunction "2_2") (pintype "passive"))
      (node (ref "T48") (pin "1") (pinfunction "E_1") (pintype "passive"))
    )
    (net (code "100") (name "Net-(T49-E)") (class "Default")
      (node (ref "J49") (pin "2") (pinfunction "2_2") (pintype "passive"))
      (node (ref "T49") (pin "1") (pinfunction "E_1") (pintype "passive"))
    )
    (net (code "101") (name "Net-(T50-E)") (class "Default")
      (node (ref "J50") (pin "2") (pinfunction "2_2") (pintype "passive"))
      (node (ref "T50") (pin "1") (pinfunction "E_1") (pintype "passive"))
    )
    (net (code "102") (name "Net-(T51-E)") (class "Default")
      (node (ref "J51") (pin "2") (pinfunction "2_2") (pintype "passive"))
      (node (ref "T51") (pin "1") (pinfunction "E_1") (pintype "passive"))
    )
    (net (code "103") (name "Net-(T52-E)") (class "Default")
      (node (ref "J52") (pin "2") (pinfunction "2_2") (pintype "passive"))
      (node (ref "T52") (pin "1") (pinfunction "E_1") (pintype "passive"))
    )
    (net (code "104") (name "Net-(T53-E)") (class "Default")
      (node (ref "J53") (pin "2") (pinfunction "2_2") (pintype "passive"))
      (node (ref "T53") (pin "1") (pinfunction "E_1") (pintype "passive"))
    )
    (net (code "105") (name "Net-(T54-B)") (class "Default")
      (node (ref "J53") (pin "1") (pinfunction "1_1") (pintype "passive"))
      (node (ref "J54") (pin "1") (pinfunction "1_1") (pintype "passive"))
      (node (ref "J55") (pin "1") (pinfunction "1_1") (pintype "passive"))
      (node (ref "J56") (pin "1") (pinfunction "1_1") (pintype "passive"))
      (node (ref "J57") (pin "1") (pinfunction "1_1") (pintype "passive"))
      (node (ref "J58") (pin "1") (pinfunction "1_1") (pintype "passive"))
      (node (ref "J59") (pin "1") (pinfunction "1_1") (pintype "passive"))
      (node (ref "J60") (pin "1") (pinfunction "1_1") (pintype "passive"))
      (node (ref "J61") (pin "1") (pinfunction "1_1") (pintype "passive"))
      (node (ref "J62") (pin "1") (pinfunction "1_1") (pintype "passive"))
      (node (ref "J63") (pin "1") (pinfunction "1_1") (pintype "passive"))
      (node (ref "J64") (pin "1") (pinfunction "1_1") (pintype "passive"))
      (node (ref "J65") (pin "1") (pinfunction "1_1") (pintype "passive"))
      (node (ref "J66") (pin "1") (pinfunction "1_1") (pintype "passive"))
      (node (ref "J67") (pin "1") (pinfunction "1_1") (pintype "passive"))
      (node (ref "J68") (pin "1") (pinfunction "1_1") (pintype "passive"))
      (node (ref "R2") (pin "2") (pinfunction "2_2") (pintype "passive"))
      (node (ref "T54") (pin "2") (pinfunction "B_2") (pintype "passive"))
      (node (ref "T70") (pin "2") (pinfunction "B_2") (pintype "passive"))
      (node (ref "T71") (pin "2") (pinfunction "B_2") (pintype "passive"))
      (node (ref "T72") (pin "2") (pinfunction "B_2") (pintype "passive"))
      (node (ref "T73") (pin "2") (pinfunction "B_2") (pintype "passive"))
      (node (ref "T74") (pin "2") (pinfunction "B_2") (pintype "passive"))
      (node (ref "T75") (pin "2") (pinfunction "B_2") (pintype "passive"))
      (node (ref "T76") (pin "2") (pinfunction "B_2") (pintype "passive"))
      (node (ref "T77") (pin "2") (pinfunction "B_2") (pintype "passive"))
      (node (ref "T78") (pin "2") (pinfunction "B_2") (pintype "passive"))
    )
    (net (code "106") (name "Net-(T54-E)") (class "Default")
      (node (ref "J69") (pin "2") (pinfunction "2_2") (pintype "passive"))
      (node (ref "T54") (pin "1") (pinfunction "E_1") (pintype "passive"))
    )
    (net (code "107") (name "Net-(T55-E)") (class "Default")
      (node (ref "J54") (pin "2") (pinfunction "2_2") (pintype "passive"))
      (node (ref "T55") (pin "1") (pinfunction "E_1") (pintype "passive"))
    )
    (net (code "108") (name "Net-(T56-E)") (class "Default")
      (node (ref "J55") (pin "2") (pinfunction "2_2") (pintype "passive"))
      (node (ref "T56") (pin "1") (pinfunction "E_1") (pintype "passive"))
    )
    (net (code "109") (name "Net-(T57-E)") (class "Default")
      (node (ref "J56") (pin "2") (pinfunction "2_2") (pintype "passive"))
      (node (ref "T57") (pin "1") (pinfunction "E_1") (pintype "passive"))
    )
    (net (code "110") (name "Net-(T58-E)") (class "Default")
      (node (ref "J57") (pin "2") (pinfunction "2_2") (pintype "passive"))
      (node (ref "T58") (pin "1") (pinfunction "E_1") (pintype "passive"))
    )
    (net (code "111") (name "Net-(T59-E)") (class "Default")
      (node (ref "J58") (pin "2") (pinfunction "2_2") (pintype "passive"))
      (node (ref "T59") (pin "1") (pinfunction "E_1") (pintype "passive"))
    )
    (net (code "112") (name "Net-(T60-E)") (class "Default")
      (node (ref "J59") (pin "2") (pinfunction "2_2") (pintype "passive"))
      (node (ref "T60") (pin "1") (pinfunction "E_1") (pintype "passive"))
    )
    (net (code "113") (name "Net-(T61-E)") (class "Default")
      (node (ref "J60") (pin "2") (pinfunction "2_2") (pintype "passive"))
      (node (ref "T61") (pin "1") (pinfunction "E_1") (pintype "passive"))
    )
    (net (code "114") (name "Net-(T62-E)") (class "Default")
      (node (ref "J61") (pin "2") (pinfunction "2_2") (pintype "passive"))
      (node (ref "T62") (pin "1") (pinfunction "E_1") (pintype "passive"))
    )
    (net (code "115") (name "Net-(T63-E)") (class "Default")
      (node (ref "J62") (pin "2") (pinfunction "2_2") (pintype "passive"))
      (node (ref "T63") (pin "1") (pinfunction "E_1") (pintype "passive"))
    )
    (net (code "116") (name "Net-(T64-E)") (class "Default")
      (node (ref "J63") (pin "2") (pinfunction "2_2") (pintype "passive"))
      (node (ref "T64") (pin "1") (pinfunction "E_1") (pintype "passive"))
    )
    (net (code "117") (name "Net-(T65-E)") (class "Default")
      (node (ref "J64") (pin "2") (pinfunction "2_2") (pintype "passive"))
      (node (ref "T65") (pin "1") (pinfunction "E_1") (pintype "passive"))
    )
    (net (code "118") (name "Net-(T66-E)") (class "Default")
      (node (ref "J65") (pin "2") (pinfunction "2_2") (pintype "passive"))
      (node (ref "T66") (pin "1") (pinfunction "E_1") (pintype "passive"))
    )
    (net (code "119") (name "Net-(T67-E)") (class "Default")
      (node (ref "J66") (pin "2") (pinfunction "2_2") (pintype "passive"))
      (node (ref "T67") (pin "1") (pinfunction "E_1") (pintype "passive"))
    )
    (net (code "120") (name "Net-(T68-E)") (class "Default")
      (node (ref "J67") (pin "2") (pinfunction "2_2") (pintype "passive"))
      (node (ref "T68") (pin "1") (pinfunction "E_1") (pintype "passive"))
    )
    (net (code "121") (name "Net-(T69-E)") (class "Default")
      (node (ref "J68") (pin "2") (pinfunction "2_2") (pintype "passive"))
      (node (ref "T69") (pin "1") (pinfunction "E_1") (pintype "passive"))
    )
    (net (code "122") (name "Net-(T70-E)") (class "Default")
      (node (ref "J70") (pin "2") (pinfunction "2_2") (pintype "passive"))
      (node (ref "T70") (pin "1") (pinfunction "E_1") (pintype "passive"))
    )
    (net (code "123") (name "Net-(T71-E)") (class "Default")
      (node (ref "J71") (pin "2") (pinfunction "2_2") (pintype "passive"))
      (node (ref "T71") (pin "1") (pinfunction "E_1") (pintype "passive"))
    )
    (net (code "124") (name "Net-(T72-E)") (class "Default")
      (node (ref "J72") (pin "2") (pinfunction "2_2") (pintype "passive"))
      (node (ref "T72") (pin "1") (pinfunction "E_1") (pintype "passive"))
    )
    (net (code "125") (name "Net-(T73-E)") (class "Default")
      (node (ref "J73") (pin "2") (pinfunction "2_2") (pintype "passive"))
      (node (ref "T73") (pin "1") (pinfunction "E_1") (pintype "passive"))
    )
    (net (code "126") (name "Net-(T74-E)") (class "Default")
      (node (ref "J74") (pin "2") (pinfunction "2_2") (pintype "passive"))
      (node (ref "T74") (pin "1") (pinfunction "E_1") (pintype "passive"))
    )
    (net (code "127") (name "Net-(T75-E)") (class "Default")
      (node (ref "J75") (pin "2") (pinfunction "2_2") (pintype "passive"))
      (node (ref "T75") (pin "1") (pinfunction "E_1") (pintype "passive"))
    )
    (net (code "128") (name "Net-(T76-E)") (class "Default")
      (node (ref "J76") (pin "2") (pinfunction "2_2") (pintype "passive"))
      (node (ref "T76") (pin "1") (pinfunction "E_1") (pintype "passive"))
    )
    (net (code "129") (name "Net-(T77-E)") (class "Default")
      (node (ref "J77") (pin "2") (pinfunction "2_2") (pintype "passive"))
      (node (ref "T77") (pin "1") (pinfunction "E_1") (pintype "passive"))
    )
    (net (code "130") (name "Net-(T78-E)") (class "Default")
      (node (ref "J78") (pin "2") (pinfunction "2_2") (pintype "passive"))
      (node (ref "T78") (pin "1") (pinfunction "E_1") (pintype "passive"))
    )
    (net (code "131") (name "Net-(T79-E)") (class "Default")
      (node (ref "J79") (pin "2") (pinfunction "2_2") (pintype "passive"))
      (node (ref "T79") (pin "1") (pinfunction "E_1") (pintype "passive"))
    )
    (net (code "132") (name "Net-(T80-E)") (class "Default")
      (node (ref "J95") (pin "2") (pinfunction "2_2") (pintype "passive"))
      (node (ref "T80") (pin "1") (pinfunction "E_1") (pintype "passive"))
    )
    (net (code "133") (name "Net-(T81-E)") (class "Default")
      (node (ref "J80") (pin "2") (pinfunction "2_2") (pintype "passive"))
      (node (ref "T81") (pin "1") (pinfunction "E_1") (pintype "passive"))
    )
    (net (code "134") (name "Net-(T82-E)") (class "Default")
      (node (ref "J81") (pin "2") (pinfunction "2_2") (pintype "passive"))
      (node (ref "T82") (pin "1") (pinfunction "E_1") (pintype "passive"))
    )
    (net (code "135") (name "Net-(T83-E)") (class "Default")
      (node (ref "J82") (pin "2") (pinfunction "2_2") (pintype "passive"))
      (node (ref "T83") (pin "1") (pinfunction "E_1") (pintype "passive"))
    )
    (net (code "136") (name "Net-(T84-E)") (class "Default")
      (node (ref "J83") (pin "2") (pinfunction "2_2") (pintype "passive"))
      (node (ref "T84") (pin "1") (pinfunction "E_1") (pintype "passive"))
    )
    (net (code "137") (name "Net-(T85-E)") (class "Default")
      (node (ref "J84") (pin "2") (pinfunction "2_2") (pintype "passive"))
      (node (ref "T85") (pin "1") (pinfunction "E_1") (pintype "passive"))
    )
    (net (code "138") (name "Net-(T86-E)") (class "Default")
      (node (ref "J85") (pin "2") (pinfunction "2_2") (pintype "passive"))
      (node (ref "T86") (pin "1") (pinfunction "E_1") (pintype "passive"))
    )
    (net (code "139") (name "Net-(T87-E)") (class "Default")
      (node (ref "J86") (pin "2") (pinfunction "2_2") (pintype "passive"))
      (node (ref "T87") (pin "1") (pinfunction "E_1") (pintype "passive"))
    )
    (net (code "140") (name "Net-(T88-E)") (class "Default")
      (node (ref "J87") (pin "2") (pinfunction "2_2") (pintype "passive"))
      (node (ref "T88") (pin "1") (pinfunction "E_1") (pintype "passive"))
    )
    (net (code "141") (name "Net-(T89-E)") (class "Default")
      (node (ref "J88") (pin "2") (pinfunction "2_2") (pintype "passive"))
      (node (ref "T89") (pin "1") (pinfunction "E_1") (pintype "passive"))
    )
    (net (code "142") (name "Net-(T90-E)") (class "Default")
      (node (ref "J89") (pin "2") (pinfunction "2_2") (pintype "passive"))
      (node (ref "T90") (pin "1") (pinfunction "E_1") (pintype "passive"))
    )
    (net (code "143") (name "Net-(T91-E)") (class "Default")
      (node (ref "J90") (pin "2") (pinfunction "2_2") (pintype "passive"))
      (node (ref "T91") (pin "1") (pinfunction "E_1") (pintype "passive"))
    )
    (net (code "144") (name "Net-(T92-E)") (class "Default")
      (node (ref "J91") (pin "2") (pinfunction "2_2") (pintype "passive"))
      (node (ref "T92") (pin "1") (pinfunction "E_1") (pintype "passive"))
    )
    (net (code "145") (name "Net-(T93-E)") (class "Default")
      (node (ref "J92") (pin "2") (pinfunction "2_2") (pintype "passive"))
      (node (ref "T93") (pin "1") (pinfunction "E_1") (pintype "passive"))
    )
    (net (code "146") (name "Net-(T94-E)") (class "Default")
      (node (ref "J93") (pin "2") (pinfunction "2_2") (pintype "passive"))
      (node (ref "T94") (pin "1") (pinfunction "E_1") (pintype "passive"))
    )
    (net (code "147") (name "Net-(T95-E)") (class "Default")
      (node (ref "J94") (pin "2") (pinfunction "2_2") (pintype "passive"))
      (node (ref "T95") (pin "1") (pinfunction "E_1") (pintype "passive"))
    )
    (net (code "148") (name "Net-(T96-E)") (class "Default")
      (node (ref "J96") (pin "2") (pinfunction "2_2") (pintype "passive"))
      (node (ref "T96") (pin "1") (pinfunction "E_1") (pintype "passive"))
    )
    (net (code "149") (name "Net-(T97-E)") (class "Default")
      (node (ref "J97") (pin "2") (pinfunction "2_2") (pintype "passive"))
      (node (ref "T97") (pin "1") (pinfunction "E_1") (pintype "passive"))
    )
    (net (code "150") (name "Net-(T98-E)") (class "Default")
      (node (ref "J98") (pin "2") (pinfunction "2_2") (pintype "passive"))
      (node (ref "T98") (pin "1") (pinfunction "E_1") (pintype "passive"))
    )
    (net (code "151") (name "Net-(T99-E)") (class "Default")
      (node (ref "J99") (pin "2") (pinfunction "2_2") (pintype "passive"))
      (node (ref "T99") (pin "1") (pinfunction "E_1") (pintype "passive"))
    )
    (net (code "152") (name "Net-(T100-B)") (class "Default")
      (node (ref "J79") (pin "1") (pinfunction "1_1") (pintype "passive"))
      (node (ref "J80") (pin "1") (pinfunction "1_1") (pintype "passive"))
      (node (ref "J81") (pin "1") (pinfunction "1_1") (pintype "passive"))
      (node (ref "J82") (pin "1") (pinfunction "1_1") (pintype "passive"))
      (node (ref "J83") (pin "1") (pinfunction "1_1") (pintype "passive"))
      (node (ref "J84") (pin "1") (pinfunction "1_1") (pintype "passive"))
      (node (ref "J85") (pin "1") (pinfunction "1_1") (pintype "passive"))
      (node (ref "J86") (pin "1") (pinfunction "1_1") (pintype "passive"))
      (node (ref "J87") (pin "1") (pinfunction "1_1") (pintype "passive"))
      (node (ref "J88") (pin "1") (pinfunction "1_1") (pintype "passive"))
      (node (ref "J89") (pin "1") (pinfunction "1_1") (pintype "passive"))
      (node (ref "J90") (pin "1") (pinfunction "1_1") (pintype "passive"))
      (node (ref "J91") (pin "1") (pinfunction "1_1") (pintype "passive"))
      (node (ref "J92") (pin "1") (pinfunction "1_1") (pintype "passive"))
      (node (ref "J93") (pin "1") (pinfunction "1_1") (pintype "passive"))
      (node (ref "J94") (pin "1") (pinfunction "1_1") (pintype "passive"))
      (node (ref "R4") (pin "2") (pinfunction "2_2") (pintype "passive"))
      (node (ref "T100") (pin "2") (pinfunction "B_2") (pintype "passive"))
      (node (ref "T101") (pin "2") (pinfunction "B_2") (pintype "passive"))
      (node (ref "T102") (pin "2") (pinfunction "B_2") (pintype "passive"))
      (node (ref "T103") (pin "2") (pinfunction "B_2") (pintype "passive"))
      (node (ref "T104") (pin "2") (pinfunction "B_2") (pintype "passive"))
      (node (ref "T80") (pin "2") (pinfunction "B_2") (pintype "passive"))
      (node (ref "T96") (pin "2") (pinfunction "B_2") (pintype "passive"))
      (node (ref "T97") (pin "2") (pinfunction "B_2") (pintype "passive"))
      (node (ref "T98") (pin "2") (pinfunction "B_2") (pintype "passive"))
      (node (ref "T99") (pin "2") (pinfunction "B_2") (pintype "passive"))
    )
    (net (code "153") (name "Net-(T100-E)") (class "Default")
      (node (ref "J100") (pin "2") (pinfunction "2_2") (pintype "passive"))
      (node (ref "T100") (pin "1") (pinfunction "E_1") (pintype "passive"))
    )
    (net (code "154") (name "Net-(T101-E)") (class "Default")
      (node (ref "J101") (pin "2") (pinfunction "2_2") (pintype "passive"))
      (node (ref "T101") (pin "1") (pinfunction "E_1") (pintype "passive"))
    )
    (net (code "155") (name "Net-(T102-E)") (class "Default")
      (node (ref "J102") (pin "2") (pinfunction "2_2") (pintype "passive"))
      (node (ref "T102") (pin "1") (pinfunction "E_1") (pintype "passive"))
    )
    (net (code "156") (name "Net-(T103-E)") (class "Default")
      (node (ref "J103") (pin "2") (pinfunction "2_2") (pintype "passive"))
      (node (ref "T103") (pin "1") (pinfunction "E_1") (pintype "passive"))
    )
    (net (code "157") (name "Net-(T104-E)") (class "Default")
      (node (ref "J104") (pin "2") (pinfunction "2_2") (pintype "passive"))
      (node (ref "T104") (pin "1") (pinfunction "E_1") (pintype "passive"))
    )
    (net (code "158") (name "Net-(T105-E)") (class "Default")
      (node (ref "J105") (pin "2") (pinfunction "2_2") (pintype "passive"))
      (node (ref "T105") (pin "1") (pinfunction "E_1") (pintype "passive"))
    )
    (net (code "159") (name "Net-(T106-B)") (class "Default")
      (node (ref "J105") (pin "1") (pinfunction "1_1") (pintype "passive"))
      (node (ref "J106") (pin "1") (pinfunction "1_1") (pintype "passive"))
      (node (ref "J107") (pin "1") (pinfunction "1_1") (pintype "passive"))
      (node (ref "J108") (pin "1") (pinfunction "1_1") (pintype "passive"))
      (node (ref "J109") (pin "1") (pinfunction "1_1") (pintype "passive"))
      (node (ref "J110") (pin "1") (pinfunction "1_1") (pintype "passive"))
      (node (ref "J111") (pin "1") (pinfunction "1_1") (pintype "passive"))
      (node (ref "J112") (pin "1") (pinfunction "1_1") (pintype "passive"))
      (node (ref "J113") (pin "1") (pinfunction "1_1") (pintype "passive"))
      (node (ref "J114") (pin "1") (pinfunction "1_1") (pintype "passive"))
      (node (ref "J115") (pin "1") (pinfunction "1_1") (pintype "passive"))
      (node (ref "J116") (pin "1") (pinfunction "1_1") (pintype "passive"))
      (node (ref "J117") (pin "1") (pinfunction "1_1") (pintype "passive"))
      (node (ref "J118") (pin "1") (pinfunction "1_1") (pintype "passive"))
      (node (ref "J119") (pin "1") (pinfunction "1_1") (pintype "passive"))
      (node (ref "J120") (pin "1") (pinfunction "1_1") (pintype "passive"))
      (node (ref "R5") (pin "2") (pinfunction "2_2") (pintype "passive"))
      (node (ref "T106") (pin "2") (pinfunction "B_2") (pintype "passive"))
      (node (ref "T122") (pin "2") (pinfunction "B_2") (pintype "passive"))
      (node (ref "T123") (pin "2") (pinfunction "B_2") (pintype "passive"))
      (node (ref "T124") (pin "2") (pinfunction "B_2") (pintype "passive"))
      (node (ref "T125") (pin "2") (pinfunction "B_2") (pintype "passive"))
      (node (ref "T126") (pin "2") (pinfunction "B_2") (pintype "passive"))
      (node (ref "T127") (pin "2") (pinfunction "B_2") (pintype "passive"))
      (node (ref "T128") (pin "2") (pinfunction "B_2") (pintype "passive"))
      (node (ref "T129") (pin "2") (pinfunction "B_2") (pintype "passive"))
      (node (ref "T130") (pin "2") (pinfunction "B_2") (pintype "passive"))
    )
    (net (code "160") (name "Net-(T106-E)") (class "Default")
      (node (ref "J121") (pin "2") (pinfunction "2_2") (pintype "passive"))
      (node (ref "T106") (pin "1") (pinfunction "E_1") (pintype "passive"))
    )
    (net (code "161") (name "Net-(T107-E)") (class "Default")
      (node (ref "J106") (pin "2") (pinfunction "2_2") (pintype "passive"))
      (node (ref "T107") (pin "1") (pinfunction "E_1") (pintype "passive"))
    )
    (net (code "162") (name "Net-(T108-E)") (class "Default")
      (node (ref "J107") (pin "2") (pinfunction "2_2") (pintype "passive"))
      (node (ref "T108") (pin "1") (pinfunction "E_1") (pintype "passive"))
    )
    (net (code "163") (name "Net-(T109-E)") (class "Default")
      (node (ref "J108") (pin "2") (pinfunction "2_2") (pintype "passive"))
      (node (ref "T109") (pin "1") (pinfunction "E_1") (pintype "passive"))
    )
    (net (code "164") (name "Net-(T110-E)") (class "Default")
      (node (ref "J109") (pin "2") (pinfunction "2_2") (pintype "passive"))
      (node (ref "T110") (pin "1") (pinfunction "E_1") (pintype "passive"))
    )
    (net (code "165") (name "Net-(T111-E)") (class "Default")
      (node (ref "J110") (pin "2") (pinfunction "2_2") (pintype "passive"))
      (node (ref "T111") (pin "1") (pinfunction "E_1") (pintype "passive"))
    )
    (net (code "166") (name "Net-(T112-E)") (class "Default")
      (node (ref "J111") (pin "2") (pinfunction "2_2") (pintype "passive"))
      (node (ref "T112") (pin "1") (pinfunction "E_1") (pintype "passive"))
    )
    (net (code "167") (name "Net-(T113-E)") (class "Default")
      (node (ref "J112") (pin "2") (pinfunction "2_2") (pintype "passive"))
      (node (ref "T113") (pin "1") (pinfunction "E_1") (pintype "passive"))
    )
    (net (code "168") (name "Net-(T114-E)") (class "Default")
      (node (ref "J113") (pin "2") (pinfunction "2_2") (pintype "passive"))
      (node (ref "T114") (pin "1") (pinfunction "E_1") (pintype "passive"))
    )
    (net (code "169") (name "Net-(T115-E)") (class "Default")
      (node (ref "J114") (pin "2") (pinfunction "2_2") (pintype "passive"))
      (node (ref "T115") (pin "1") (pinfunction "E_1") (pintype "passive"))
    )
    (net (code "170") (name "Net-(T116-E)") (class "Default")
      (node (ref "J115") (pin "2") (pinfunction "2_2") (pintype "passive"))
      (node (ref "T116") (pin "1") (pinfunction "E_1") (pintype "passive"))
    )
    (net (code "171") (name "Net-(T117-E)") (class "Default")
      (node (ref "J116") (pin "2") (pinfunction "2_2") (pintype "passive"))
      (node (ref "T117") (pin "1") (pinfunction "E_1") (pintype "passive"))
    )
    (net (code "172") (name "Net-(T118-E)") (class "Default")
      (node (ref "J117") (pin "2") (pinfunction "2_2") (pintype "passive"))
      (node (ref "T118") (pin "1") (pinfunction "E_1") (pintype "passive"))
    )
    (net (code "173") (name "Net-(T119-E)") (class "Default")
      (node (ref "J118") (pin "2") (pinfunction "2_2") (pintype "passive"))
      (node (ref "T119") (pin "1") (pinfunction "E_1") (pintype "passive"))
    )
    (net (code "174") (name "Net-(T120-E)") (class "Default")
      (node (ref "J119") (pin "2") (pinfunction "2_2") (pintype "passive"))
      (node (ref "T120") (pin "1") (pinfunction "E_1") (pintype "passive"))
    )
    (net (code "175") (name "Net-(T121-E)") (class "Default")
      (node (ref "J120") (pin "2") (pinfunction "2_2") (pintype "passive"))
      (node (ref "T121") (pin "1") (pinfunction "E_1") (pintype "passive"))
    )
    (net (code "176") (name "Net-(T122-E)") (class "Default")
      (node (ref "J122") (pin "2") (pinfunction "2_2") (pintype "passive"))
      (node (ref "T122") (pin "1") (pinfunction "E_1") (pintype "passive"))
    )
    (net (code "177") (name "Net-(T123-E)") (class "Default")
      (node (ref "J123") (pin "2") (pinfunction "2_2") (pintype "passive"))
      (node (ref "T123") (pin "1") (pinfunction "E_1") (pintype "passive"))
    )
    (net (code "178") (name "Net-(T124-E)") (class "Default")
      (node (ref "J124") (pin "2") (pinfunction "2_2") (pintype "passive"))
      (node (ref "T124") (pin "1") (pinfunction "E_1") (pintype "passive"))
    )
    (net (code "179") (name "Net-(T125-E)") (class "Default")
      (node (ref "J125") (pin "2") (pinfunction "2_2") (pintype "passive"))
      (node (ref "T125") (pin "1") (pinfunction "E_1") (pintype "passive"))
    )
    (net (code "180") (name "Net-(T126-E)") (class "Default")
      (node (ref "J126") (pin "2") (pinfunction "2_2") (pintype "passive"))
      (node (ref "T126") (pin "1") (pinfunction "E_1") (pintype "passive"))
    )
    (net (code "181") (name "Net-(T127-E)") (class "Default")
      (node (ref "J127") (pin "2") (pinfunction "2_2") (pintype "passive"))
      (node (ref "T127") (pin "1") (pinfunction "E_1") (pintype "passive"))
    )
    (net (code "182") (name "Net-(T128-E)") (class "Default")
      (node (ref "J128") (pin "2") (pinfunction "2_2") (pintype "passive"))
      (node (ref "T128") (pin "1") (pinfunction "E_1") (pintype "passive"))
    )
    (net (code "183") (name "Net-(T129-E)") (class "Default")
      (node (ref "J129") (pin "2") (pinfunction "2_2") (pintype "passive"))
      (node (ref "T129") (pin "1") (pinfunction "E_1") (pintype "passive"))
    )
    (net (code "184") (name "Net-(T130-E)") (class "Default")
      (node (ref "J130") (pin "2") (pinfunction "2_2") (pintype "passive"))
      (node (ref "T130") (pin "1") (pinfunction "E_1") (pintype "passive"))
    )
    (net (code "185") (name "Net-(T131-E)") (class "Default")
      (node (ref "J131") (pin "2") (pinfunction "2_2") (pintype "passive"))
      (node (ref "T131") (pin "1") (pinfunction "E_1") (pintype "passive"))
    )
    (net (code "186") (name "Net-(T132-B)") (class "Default")
      (node (ref "J131") (pin "1") (pinfunction "1_1") (pintype "passive"))
      (node (ref "J132") (pin "1") (pinfunction "1_1") (pintype "passive"))
      (node (ref "J133") (pin "1") (pinfunction "1_1") (pintype "passive"))
      (node (ref "J134") (pin "1") (pinfunction "1_1") (pintype "passive"))
      (node (ref "J135") (pin "1") (pinfunction "1_1") (pintype "passive"))
      (node (ref "J136") (pin "1") (pinfunction "1_1") (pintype "passive"))
      (node (ref "J137") (pin "1") (pinfunction "1_1") (pintype "passive"))
      (node (ref "J138") (pin "1") (pinfunction "1_1") (pintype "passive"))
      (node (ref "J139") (pin "1") (pinfunction "1_1") (pintype "passive"))
      (node (ref "J140") (pin "1") (pinfunction "1_1") (pintype "passive"))
      (node (ref "J141") (pin "1") (pinfunction "1_1") (pintype "passive"))
      (node (ref "J142") (pin "1") (pinfunction "1_1") (pintype "passive"))
      (node (ref "J143") (pin "1") (pinfunction "1_1") (pintype "passive"))
      (node (ref "J144") (pin "1") (pinfunction "1_1") (pintype "passive"))
      (node (ref "J145") (pin "1") (pinfunction "1_1") (pintype "passive"))
      (node (ref "J146") (pin "1") (pinfunction "1_1") (pintype "passive"))
      (node (ref "R6") (pin "2") (pinfunction "2_2") (pintype "passive"))
      (node (ref "T132") (pin "2") (pinfunction "B_2") (pintype "passive"))
      (node (ref "T148") (pin "2") (pinfunction "B_2") (pintype "passive"))
      (node (ref "T149") (pin "2") (pinfunction "B_2") (pintype "passive"))
      (node (ref "T150") (pin "2") (pinfunction "B_2") (pintype "passive"))
      (node (ref "T151") (pin "2") (pinfunction "B_2") (pintype "passive"))
      (node (ref "T152") (pin "2") (pinfunction "B_2") (pintype "passive"))
      (node (ref "T153") (pin "2") (pinfunction "B_2") (pintype "passive"))
      (node (ref "T154") (pin "2") (pinfunction "B_2") (pintype "passive"))
      (node (ref "T155") (pin "2") (pinfunction "B_2") (pintype "passive"))
      (node (ref "T156") (pin "2") (pinfunction "B_2") (pintype "passive"))
    )
    (net (code "187") (name "Net-(T132-E)") (class "Default")
      (node (ref "J147") (pin "2") (pinfunction "2_2") (pintype "passive"))
      (node (ref "T132") (pin "1") (pinfunction "E_1") (pintype "passive"))
    )
    (net (code "188") (name "Net-(T133-E)") (class "Default")
      (node (ref "J132") (pin "2") (pinfunction "2_2") (pintype "passive"))
      (node (ref "T133") (pin "1") (pinfunction "E_1") (pintype "passive"))
    )
    (net (code "189") (name "Net-(T134-E)") (class "Default")
      (node (ref "J133") (pin "2") (pinfunction "2_2") (pintype "passive"))
      (node (ref "T134") (pin "1") (pinfunction "E_1") (pintype "passive"))
    )
    (net (code "190") (name "Net-(T135-E)") (class "Default")
      (node (ref "J134") (pin "2") (pinfunction "2_2") (pintype "passive"))
      (node (ref "T135") (pin "1") (pinfunction "E_1") (pintype "passive"))
    )
    (net (code "191") (name "Net-(T136-E)") (class "Default")
      (node (ref "J135") (pin "2") (pinfunction "2_2") (pintype "passive"))
      (node (ref "T136") (pin "1") (pinfunction "E_1") (pintype "passive"))
    )
    (net (code "192") (name "Net-(T137-E)") (class "Default")
      (node (ref "J136") (pin "2") (pinfunction "2_2") (pintype "passive"))
      (node (ref "T137") (pin "1") (pinfunction "E_1") (pintype "passive"))
    )
    (net (code "193") (name "Net-(T138-E)") (class "Default")
      (node (ref "J137") (pin "2") (pinfunction "2_2") (pintype "passive"))
      (node (ref "T138") (pin "1") (pinfunction "E_1") (pintype "passive"))
    )
    (net (code "194") (name "Net-(T139-E)") (class "Default")
      (node (ref "J138") (pin "2") (pinfunction "2_2") (pintype "passive"))
      (node (ref "T139") (pin "1") (pinfunction "E_1") (pintype "passive"))
    )
    (net (code "195") (name "Net-(T140-E)") (class "Default")
      (node (ref "J139") (pin "2") (pinfunction "2_2") (pintype "passive"))
      (node (ref "T140") (pin "1") (pinfunction "E_1") (pintype "passive"))
    )
    (net (code "196") (name "Net-(T141-E)") (class "Default")
      (node (ref "J140") (pin "2") (pinfunction "2_2") (pintype "passive"))
      (node (ref "T141") (pin "1") (pinfunction "E_1") (pintype "passive"))
    )
    (net (code "197") (name "Net-(T142-E)") (class "Default")
      (node (ref "J141") (pin "2") (pinfunction "2_2") (pintype "passive"))
      (node (ref "T142") (pin "1") (pinfunction "E_1") (pintype "passive"))
    )
    (net (code "198") (name "Net-(T143-E)") (class "Default")
      (node (ref "J142") (pin "2") (pinfunction "2_2") (pintype "passive"))
      (node (ref "T143") (pin "1") (pinfunction "E_1") (pintype "passive"))
    )
    (net (code "199") (name "Net-(T144-E)") (class "Default")
      (node (ref "J143") (pin "2") (pinfunction "2_2") (pintype "passive"))
      (node (ref "T144") (pin "1") (pinfunction "E_1") (pintype "passive"))
    )
    (net (code "200") (name "Net-(T145-E)") (class "Default")
      (node (ref "J144") (pin "2") (pinfunction "2_2") (pintype "passive"))
      (node (ref "T145") (pin "1") (pinfunction "E_1") (pintype "passive"))
    )
    (net (code "201") (name "Net-(T146-E)") (class "Default")
      (node (ref "J145") (pin "2") (pinfunction "2_2") (pintype "passive"))
      (node (ref "T146") (pin "1") (pinfunction "E_1") (pintype "passive"))
    )
    (net (code "202") (name "Net-(T147-E)") (class "Default")
      (node (ref "J146") (pin "2") (pinfunction "2_2") (pintype "passive"))
      (node (ref "T147") (pin "1") (pinfunction "E_1") (pintype "passive"))
    )
    (net (code "203") (name "Net-(T148-E)") (class "Default")
      (node (ref "J148") (pin "2") (pinfunction "2_2") (pintype "passive"))
      (node (ref "T148") (pin "1") (pinfunction "E_1") (pintype "passive"))
    )
    (net (code "204") (name "Net-(T149-E)") (class "Default")
      (node (ref "J149") (pin "2") (pinfunction "2_2") (pintype "passive"))
      (node (ref "T149") (pin "1") (pinfunction "E_1") (pintype "passive"))
    )
    (net (code "205") (name "Net-(T150-E)") (class "Default")
      (node (ref "J150") (pin "2") (pinfunction "2_2") (pintype "passive"))
      (node (ref "T150") (pin "1") (pinfunction "E_1") (pintype "passive"))
    )
    (net (code "206") (name "Net-(T151-E)") (class "Default")
      (node (ref "J151") (pin "2") (pinfunction "2_2") (pintype "passive"))
      (node (ref "T151") (pin "1") (pinfunction "E_1") (pintype "passive"))
    )
    (net (code "207") (name "Net-(T152-E)") (class "Default")
      (node (ref "J152") (pin "2") (pinfunction "2_2") (pintype "passive"))
      (node (ref "T152") (pin "1") (pinfunction "E_1") (pintype "passive"))
    )
    (net (code "208") (name "Net-(T153-E)") (class "Default")
      (node (ref "J153") (pin "2") (pinfunction "2_2") (pintype "passive"))
      (node (ref "T153") (pin "1") (pinfunction "E_1") (pintype "passive"))
    )
    (net (code "209") (name "Net-(T154-E)") (class "Default")
      (node (ref "J154") (pin "2") (pinfunction "2_2") (pintype "passive"))
      (node (ref "T154") (pin "1") (pinfunction "E_1") (pintype "passive"))
    )
    (net (code "210") (name "Net-(T155-E)") (class "Default")
      (node (ref "J155") (pin "2") (pinfunction "2_2") (pintype "passive"))
      (node (ref "T155") (pin "1") (pinfunction "E_1") (pintype "passive"))
    )
    (net (code "211") (name "Net-(T156-E)") (class "Default")
      (node (ref "J156") (pin "2") (pinfunction "2_2") (pintype "passive"))
      (node (ref "T156") (pin "1") (pinfunction "E_1") (pintype "passive"))
    )
    (net (code "212") (name "Net-(T157-E)") (class "Default")
      (node (ref "J157") (pin "2") (pinfunction "2_2") (pintype "passive"))
      (node (ref "T157") (pin "1") (pinfunction "E_1") (pintype "passive"))
    )
    (net (code "213") (name "Net-(T158-B)") (class "Default")
      (node (ref "J157") (pin "1") (pinfunction "1_1") (pintype "passive"))
      (node (ref "J158") (pin "1") (pinfunction "1_1") (pintype "passive"))
      (node (ref "J159") (pin "1") (pinfunction "1_1") (pintype "passive"))
      (node (ref "J160") (pin "1") (pinfunction "1_1") (pintype "passive"))
      (node (ref "J161") (pin "1") (pinfunction "1_1") (pintype "passive"))
      (node (ref "J162") (pin "1") (pinfunction "1_1") (pintype "passive"))
      (node (ref "J163") (pin "1") (pinfunction "1_1") (pintype "passive"))
      (node (ref "J164") (pin "1") (pinfunction "1_1") (pintype "passive"))
      (node (ref "J165") (pin "1") (pinfunction "1_1") (pintype "passive"))
      (node (ref "J166") (pin "1") (pinfunction "1_1") (pintype "passive"))
      (node (ref "J167") (pin "1") (pinfunction "1_1") (pintype "passive"))
      (node (ref "J168") (pin "1") (pinfunction "1_1") (pintype "passive"))
      (node (ref "J169") (pin "1") (pinfunction "1_1") (pintype "passive"))
      (node (ref "J170") (pin "1") (pinfunction "1_1") (pintype "passive"))
      (node (ref "J171") (pin "1") (pinfunction "1_1") (pintype "passive"))
      (node (ref "J172") (pin "1") (pinfunction "1_1") (pintype "passive"))
      (node (ref "R7") (pin "2") (pinfunction "2_2") (pintype "passive"))
      (node (ref "T158") (pin "2") (pinfunction "B_2") (pintype "passive"))
      (node (ref "T174") (pin "2") (pinfunction "B_2") (pintype "passive"))
      (node (ref "T175") (pin "2") (pinfunction "B_2") (pintype "passive"))
      (node (ref "T176") (pin "2") (pinfunction "B_2") (pintype "passive"))
      (node (ref "T177") (pin "2") (pinfunction "B_2") (pintype "passive"))
      (node (ref "T178") (pin "2") (pinfunction "B_2") (pintype "passive"))
      (node (ref "T179") (pin "2") (pinfunction "B_2") (pintype "passive"))
      (node (ref "T180") (pin "2") (pinfunction "B_2") (pintype "passive"))
      (node (ref "T181") (pin "2") (pinfunction "B_2") (pintype "passive"))
      (node (ref "T182") (pin "2") (pinfunction "B_2") (pintype "passive"))
    )
    (net (code "214") (name "Net-(T158-E)") (class "Default")
      (node (ref "J173") (pin "2") (pinfunction "2_2") (pintype "passive"))
      (node (ref "T158") (pin "1") (pinfunction "E_1") (pintype "passive"))
    )
    (net (code "215") (name "Net-(T159-E)") (class "Default")
      (node (ref "J158") (pin "2") (pinfunction "2_2") (pintype "passive"))
      (node (ref "T159") (pin "1") (pinfunction "E_1") (pintype "passive"))
    )
    (net (code "216") (name "Net-(T160-E)") (class "Default")
      (node (ref "J159") (pin "2") (pinfunction "2_2") (pintype "passive"))
      (node (ref "T160") (pin "1") (pinfunction "E_1") (pintype "passive"))
    )
    (net (code "217") (name "Net-(T161-E)") (class "Default")
      (node (ref "J160") (pin "2") (pinfunction "2_2") (pintype "passive"))
      (node (ref "T161") (pin "1") (pinfunction "E_1") (pintype "passive"))
    )
    (net (code "218") (name "Net-(T162-E)") (class "Default")
      (node (ref "J161") (pin "2") (pinfunction "2_2") (pintype "passive"))
      (node (ref "T162") (pin "1") (pinfunction "E_1") (pintype "passive"))
    )
    (net (code "219") (name "Net-(T163-E)") (class "Default")
      (node (ref "J162") (pin "2") (pinfunction "2_2") (pintype "passive"))
      (node (ref "T163") (pin "1") (pinfunction "E_1") (pintype "passive"))
    )
    (net (code "220") (name "Net-(T164-E)") (class "Default")
      (node (ref "J163") (pin "2") (pinfunction "2_2") (pintype "passive"))
      (node (ref "T164") (pin "1") (pinfunction "E_1") (pintype "passive"))
    )
    (net (code "221") (name "Net-(T165-E)") (class "Default")
      (node (ref "J164") (pin "2") (pinfunction "2_2") (pintype "passive"))
      (node (ref "T165") (pin "1") (pinfunction "E_1") (pintype "passive"))
    )
    (net (code "222") (name "Net-(T166-E)") (class "Default")
      (node (ref "J165") (pin "2") (pinfunction "2_2") (pintype "passive"))
      (node (ref "T166") (pin "1") (pinfunction "E_1") (pintype "passive"))
    )
    (net (code "223") (name "Net-(T167-E)") (class "Default")
      (node (ref "J166") (pin "2") (pinfunction "2_2") (pintype "passive"))
      (node (ref "T167") (pin "1") (pinfunction "E_1") (pintype "passive"))
    )
    (net (code "224") (name "Net-(T168-E)") (class "Default")
      (node (ref "J167") (pin "2") (pinfunction "2_2") (pintype "passive"))
      (node (ref "T168") (pin "1") (pinfunction "E_1") (pintype "passive"))
    )
    (net (code "225") (name "Net-(T169-E)") (class "Default")
      (node (ref "J168") (pin "2") (pinfunction "2_2") (pintype "passive"))
      (node (ref "T169") (pin "1") (pinfunction "E_1") (pintype "passive"))
    )
    (net (code "226") (name "Net-(T170-E)") (class "Default")
      (node (ref "J169") (pin "2") (pinfunction "2_2") (pintype "passive"))
      (node (ref "T170") (pin "1") (pinfunction "E_1") (pintype "passive"))
    )
    (net (code "227") (name "Net-(T171-E)") (class "Default")
      (node (ref "J170") (pin "2") (pinfunction "2_2") (pintype "passive"))
      (node (ref "T171") (pin "1") (pinfunction "E_1") (pintype "passive"))
    )
    (net (code "228") (name "Net-(T172-E)") (class "Default")
      (node (ref "J171") (pin "2") (pinfunction "2_2") (pintype "passive"))
      (node (ref "T172") (pin "1") (pinfunction "E_1") (pintype "passive"))
    )
    (net (code "229") (name "Net-(T173-E)") (class "Default")
      (node (ref "J172") (pin "2") (pinfunction "2_2") (pintype "passive"))
      (node (ref "T173") (pin "1") (pinfunction "E_1") (pintype "passive"))
    )
    (net (code "230") (name "Net-(T174-E)") (class "Default")
      (node (ref "J174") (pin "2") (pinfunction "2_2") (pintype "passive"))
      (node (ref "T174") (pin "1") (pinfunction "E_1") (pintype "passive"))
    )
    (net (code "231") (name "Net-(T175-E)") (class "Default")
      (node (ref "J175") (pin "2") (pinfunction "2_2") (pintype "passive"))
      (node (ref "T175") (pin "1") (pinfunction "E_1") (pintype "passive"))
    )
    (net (code "232") (name "Net-(T176-E)") (class "Default")
      (node (ref "J176") (pin "2") (pinfunction "2_2") (pintype "passive"))
      (node (ref "T176") (pin "1") (pinfunction "E_1") (pintype "passive"))
    )
    (net (code "233") (name "Net-(T177-E)") (class "Default")
      (node (ref "J177") (pin "2") (pinfunction "2_2") (pintype "passive"))
      (node (ref "T177") (pin "1") (pinfunction "E_1") (pintype "passive"))
    )
    (net (code "234") (name "Net-(T178-E)") (class "Default")
      (node (ref "J178") (pin "2") (pinfunction "2_2") (pintype "passive"))
      (node (ref "T178") (pin "1") (pinfunction "E_1") (pintype "passive"))
    )
    (net (code "235") (name "Net-(T179-E)") (class "Default")
      (node (ref "J179") (pin "2") (pinfunction "2_2") (pintype "passive"))
      (node (ref "T179") (pin "1") (pinfunction "E_1") (pintype "passive"))
    )
    (net (code "236") (name "Net-(T180-E)") (class "Default")
      (node (ref "J180") (pin "2") (pinfunction "2_2") (pintype "passive"))
      (node (ref "T180") (pin "1") (pinfunction "E_1") (pintype "passive"))
    )
    (net (code "237") (name "Net-(T181-E)") (class "Default")
      (node (ref "J181") (pin "2") (pinfunction "2_2") (pintype "passive"))
      (node (ref "T181") (pin "1") (pinfunction "E_1") (pintype "passive"))
    )
    (net (code "238") (name "Net-(T182-E)") (class "Default")
      (node (ref "J182") (pin "2") (pinfunction "2_2") (pintype "passive"))
      (node (ref "T182") (pin "1") (pinfunction "E_1") (pintype "passive"))
    )
    (net (code "239") (name "Net-(T183-E)") (class "Default")
      (node (ref "J183") (pin "2") (pinfunction "2_2") (pintype "passive"))
      (node (ref "T183") (pin "1") (pinfunction "E_1") (pintype "passive"))
    )
    (net (code "240") (name "Net-(T184-B)") (class "Default")
      (node (ref "J183") (pin "1") (pinfunction "1_1") (pintype "passive"))
      (node (ref "J184") (pin "1") (pinfunction "1_1") (pintype "passive"))
      (node (ref "J185") (pin "1") (pinfunction "1_1") (pintype "passive"))
      (node (ref "J186") (pin "1") (pinfunction "1_1") (pintype "passive"))
      (node (ref "J187") (pin "1") (pinfunction "1_1") (pintype "passive"))
      (node (ref "J188") (pin "1") (pinfunction "1_1") (pintype "passive"))
      (node (ref "J189") (pin "1") (pinfunction "1_1") (pintype "passive"))
      (node (ref "J190") (pin "1") (pinfunction "1_1") (pintype "passive"))
      (node (ref "J191") (pin "1") (pinfunction "1_1") (pintype "passive"))
      (node (ref "J192") (pin "1") (pinfunction "1_1") (pintype "passive"))
      (node (ref "J193") (pin "1") (pinfunction "1_1") (pintype "passive"))
      (node (ref "J194") (pin "1") (pinfunction "1_1") (pintype "passive"))
      (node (ref "J195") (pin "1") (pinfunction "1_1") (pintype "passive"))
      (node (ref "J196") (pin "1") (pinfunction "1_1") (pintype "passive"))
      (node (ref "J197") (pin "1") (pinfunction "1_1") (pintype "passive"))
      (node (ref "J198") (pin "1") (pinfunction "1_1") (pintype "passive"))
      (node (ref "R8") (pin "2") (pinfunction "2_2") (pintype "passive"))
      (node (ref "T184") (pin "2") (pinfunction "B_2") (pintype "passive"))
      (node (ref "T200") (pin "2") (pinfunction "B_2") (pintype "passive"))
      (node (ref "T201") (pin "2") (pinfunction "B_2") (pintype "passive"))
      (node (ref "T202") (pin "2") (pinfunction "B_2") (pintype "passive"))
      (node (ref "T203") (pin "2") (pinfunction "B_2") (pintype "passive"))
      (node (ref "T204") (pin "2") (pinfunction "B_2") (pintype "passive"))
      (node (ref "T205") (pin "2") (pinfunction "B_2") (pintype "passive"))
      (node (ref "T206") (pin "2") (pinfunction "B_2") (pintype "passive"))
      (node (ref "T207") (pin "2") (pinfunction "B_2") (pintype "passive"))
      (node (ref "T208") (pin "2") (pinfunction "B_2") (pintype "passive"))
    )
    (net (code "241") (name "Net-(T184-E)") (class "Default")
      (node (ref "J199") (pin "2") (pinfunction "2_2") (pintype "passive"))
      (node (ref "T184") (pin "1") (pinfunction "E_1") (pintype "passive"))
    )
    (net (code "242") (name "Net-(T185-E)") (class "Default")
      (node (ref "J184") (pin "2") (pinfunction "2_2") (pintype "passive"))
      (node (ref "T185") (pin "1") (pinfunction "E_1") (pintype "passive"))
    )
    (net (code "243") (name "Net-(T186-E)") (class "Default")
      (node (ref "J185") (pin "2") (pinfunction "2_2") (pintype "passive"))
      (node (ref "T186") (pin "1") (pinfunction "E_1") (pintype "passive"))
    )
    (net (code "244") (name "Net-(T187-E)") (class "Default")
      (node (ref "J186") (pin "2") (pinfunction "2_2") (pintype "passive"))
      (node (ref "T187") (pin "1") (pinfunction "E_1") (pintype "passive"))
    )
    (net (code "245") (name "Net-(T188-E)") (class "Default")
      (node (ref "J187") (pin "2") (pinfunction "2_2") (pintype "passive"))
      (node (ref "T188") (pin "1") (pinfunction "E_1") (pintype "passive"))
    )
    (net (code "246") (name "Net-(T189-E)") (class "Default")
      (node (ref "J188") (pin "2") (pinfunction "2_2") (pintype "passive"))
      (node (ref "T189") (pin "1") (pinfunction "E_1") (pintype "passive"))
    )
    (net (code "247") (name "Net-(T190-E)") (class "Default")
      (node (ref "J189") (pin "2") (pinfunction "2_2") (pintype "passive"))
      (node (ref "T190") (pin "1") (pinfunction "E_1") (pintype "passive"))
    )
    (net (code "248") (name "Net-(T191-E)") (class "Default")
      (node (ref "J190") (pin "2") (pinfunction "2_2") (pintype "passive"))
      (node (ref "T191") (pin "1") (pinfunction "E_1") (pintype "passive"))
    )
    (net (code "249") (name "Net-(T192-E)") (class "Default")
      (node (ref "J191") (pin "2") (pinfunction "2_2") (pintype "passive"))
      (node (ref "T192") (pin "1") (pinfunction "E_1") (pintype "passive"))
    )
    (net (code "250") (name "Net-(T193-E)") (class "Default")
      (node (ref "J192") (pin "2") (pinfunction "2_2") (pintype "passive"))
      (node (ref "T193") (pin "1") (pinfunction "E_1") (pintype "passive"))
    )
    (net (code "251") (name "Net-(T194-E)") (class "Default")
      (node (ref "J193") (pin "2") (pinfunction "2_2") (pintype "passive"))
      (node (ref "T194") (pin "1") (pinfunction "E_1") (pintype "passive"))
    )
    (net (code "252") (name "Net-(T195-E)") (class "Default")
      (node (ref "J194") (pin "2") (pinfunction "2_2") (pintype "passive"))
      (node (ref "T195") (pin "1") (pinfunction "E_1") (pintype "passive"))
    )
    (net (code "253") (name "Net-(T196-E)") (class "Default")
      (node (ref "J195") (pin "2") (pinfunction "2_2") (pintype "passive"))
      (node (ref "T196") (pin "1") (pinfunction "E_1") (pintype "passive"))
    )
    (net (code "254") (name "Net-(T197-E)") (class "Default")
      (node (ref "J196") (pin "2") (pinfunction "2_2") (pintype "passive"))
      (node (ref "T197") (pin "1") (pinfunction "E_1") (pintype "passive"))
    )
    (net (code "255") (name "Net-(T198-E)") (class "Default")
      (node (ref "J197") (pin "2") (pinfunction "2_2") (pintype "passive"))
      (node (ref "T198") (pin "1") (pinfunction "E_1") (pintype "passive"))
    )
    (net (code "256") (name "Net-(T199-E)") (class "Default")
      (node (ref "J198") (pin "2") (pinfunction "2_2") (pintype "passive"))
      (node (ref "T199") (pin "1") (pinfunction "E_1") (pintype "passive"))
    )
    (net (code "257") (name "Net-(T200-E)") (class "Default")
      (node (ref "J200") (pin "2") (pinfunction "2_2") (pintype "passive"))
      (node (ref "T200") (pin "1") (pinfunction "E_1") (pintype "passive"))
    )
    (net (code "258") (name "Net-(T201-E)") (class "Default")
      (node (ref "J201") (pin "2") (pinfunction "2_2") (pintype "passive"))
      (node (ref "T201") (pin "1") (pinfunction "E_1") (pintype "passive"))
    )
    (net (code "259") (name "Net-(T202-E)") (class "Default")
      (node (ref "J202") (pin "2") (pinfunction "2_2") (pintype "passive"))
      (node (ref "T202") (pin "1") (pinfunction "E_1") (pintype "passive"))
    )
    (net (code "260") (name "Net-(T203-E)") (class "Default")
      (node (ref "J203") (pin "2") (pinfunction "2_2") (pintype "passive"))
      (node (ref "T203") (pin "1") (pinfunction "E_1") (pintype "passive"))
    )
    (net (code "261") (name "Net-(T204-E)") (class "Default")
      (node (ref "J204") (pin "2") (pinfunction "2_2") (pintype "passive"))
      (node (ref "T204") (pin "1") (pinfunction "E_1") (pintype "passive"))
    )
    (net (code "262") (name "Net-(T205-E)") (class "Default")
      (node (ref "J205") (pin "2") (pinfunction "2_2") (pintype "passive"))
      (node (ref "T205") (pin "1") (pinfunction "E_1") (pintype "passive"))
    )
    (net (code "263") (name "Net-(T206-E)") (class "Default")
      (node (ref "J206") (pin "2") (pinfunction "2_2") (pintype "passive"))
      (node (ref "T206") (pin "1") (pinfunction "E_1") (pintype "passive"))
    )
    (net (code "264") (name "Net-(T207-E)") (class "Default")
      (node (ref "J207") (pin "2") (pinfunction "2_2") (pintype "passive"))
      (node (ref "T207") (pin "1") (pinfunction "E_1") (pintype "passive"))
    )
    (net (code "265") (name "Net-(T208-E)") (class "Default")
      (node (ref "J208") (pin "2") (pinfunction "2_2") (pintype "passive"))
      (node (ref "T208") (pin "1") (pinfunction "E_1") (pintype "passive"))
    )
    (net (code "266") (name "Net-(T209-E)") (class "Default")
      (node (ref "J209") (pin "2") (pinfunction "2_2") (pintype "passive"))
      (node (ref "T209") (pin "1") (pinfunction "E_1") (pintype "passive"))
    )
    (net (code "267") (name "Net-(T210-B)") (class "Default")
      (node (ref "J209") (pin "1") (pinfunction "1_1") (pintype "passive"))
      (node (ref "J210") (pin "1") (pinfunction "1_1") (pintype "passive"))
      (node (ref "J211") (pin "1") (pinfunction "1_1") (pintype "passive"))
      (node (ref "J212") (pin "1") (pinfunction "1_1") (pintype "passive"))
      (node (ref "J213") (pin "1") (pinfunction "1_1") (pintype "passive"))
      (node (ref "J214") (pin "1") (pinfunction "1_1") (pintype "passive"))
      (node (ref "J215") (pin "1") (pinfunction "1_1") (pintype "passive"))
      (node (ref "J216") (pin "1") (pinfunction "1_1") (pintype "passive"))
      (node (ref "J217") (pin "1") (pinfunction "1_1") (pintype "passive"))
      (node (ref "J218") (pin "1") (pinfunction "1_1") (pintype "passive"))
      (node (ref "J219") (pin "1") (pinfunction "1_1") (pintype "passive"))
      (node (ref "J220") (pin "1") (pinfunction "1_1") (pintype "passive"))
      (node (ref "J221") (pin "1") (pinfunction "1_1") (pintype "passive"))
      (node (ref "J222") (pin "1") (pinfunction "1_1") (pintype "passive"))
      (node (ref "J223") (pin "1") (pinfunction "1_1") (pintype "passive"))
      (node (ref "J224") (pin "1") (pinfunction "1_1") (pintype "passive"))
      (node (ref "R9") (pin "2") (pinfunction "2_2") (pintype "passive"))
      (node (ref "T210") (pin "2") (pinfunction "B_2") (pintype "passive"))
      (node (ref "T226") (pin "2") (pinfunction "B_2") (pintype "passive"))
      (node (ref "T227") (pin "2") (pinfunction "B_2") (pintype "passive"))
      (node (ref "T228") (pin "2") (pinfunction "B_2") (pintype "passive"))
      (node (ref "T229") (pin "2") (pinfunction "B_2") (pintype "passive"))
      (node (ref "T230") (pin "2") (pinfunction "B_2") (pintype "passive"))
      (node (ref "T231") (pin "2") (pinfunction "B_2") (pintype "passive"))
      (node (ref "T232") (pin "2") (pinfunction "B_2") (pintype "passive"))
      (node (ref "T233") (pin "2") (pinfunction "B_2") (pintype "passive"))
      (node (ref "T234") (pin "2") (pinfunction "B_2") (pintype "passive"))
    )
    (net (code "268") (name "Net-(T210-E)") (class "Default")
      (node (ref "J225") (pin "2") (pinfunction "2_2") (pintype "passive"))
      (node (ref "T210") (pin "1") (pinfunction "E_1") (pintype "passive"))
    )
    (net (code "269") (name "Net-(T211-E)") (class "Default")
      (node (ref "J210") (pin "2") (pinfunction "2_2") (pintype "passive"))
      (node (ref "T211") (pin "1") (pinfunction "E_1") (pintype "passive"))
    )
    (net (code "270") (name "Net-(T212-E)") (class "Default")
      (node (ref "J211") (pin "2") (pinfunction "2_2") (pintype "passive"))
      (node (ref "T212") (pin "1") (pinfunction "E_1") (pintype "passive"))
    )
    (net (code "271") (name "Net-(T213-E)") (class "Default")
      (node (ref "J212") (pin "2") (pinfunction "2_2") (pintype "passive"))
      (node (ref "T213") (pin "1") (pinfunction "E_1") (pintype "passive"))
    )
    (net (code "272") (name "Net-(T214-E)") (class "Default")
      (node (ref "J213") (pin "2") (pinfunction "2_2") (pintype "passive"))
      (node (ref "T214") (pin "1") (pinfunction "E_1") (pintype "passive"))
    )
    (net (code "273") (name "Net-(T215-E)") (class "Default")
      (node (ref "J214") (pin "2") (pinfunction "2_2") (pintype "passive"))
      (node (ref "T215") (pin "1") (pinfunction "E_1") (pintype "passive"))
    )
    (net (code "274") (name "Net-(T216-E)") (class "Default")
      (node (ref "J215") (pin "2") (pinfunction "2_2") (pintype "passive"))
      (node (ref "T216") (pin "1") (pinfunction "E_1") (pintype "passive"))
    )
    (net (code "275") (name "Net-(T217-E)") (class "Default")
      (node (ref "J216") (pin "2") (pinfunction "2_2") (pintype "passive"))
      (node (ref "T217") (pin "1") (pinfunction "E_1") (pintype "passive"))
    )
    (net (code "276") (name "Net-(T218-E)") (class "Default")
      (node (ref "J217") (pin "2") (pinfunction "2_2") (pintype "passive"))
      (node (ref "T218") (pin "1") (pinfunction "E_1") (pintype "passive"))
    )
    (net (code "277") (name "Net-(T219-E)") (class "Default")
      (node (ref "J218") (pin "2") (pinfunction "2_2") (pintype "passive"))
      (node (ref "T219") (pin "1") (pinfunction "E_1") (pintype "passive"))
    )
    (net (code "278") (name "Net-(T220-E)") (class "Default")
      (node (ref "J219") (pin "2") (pinfunction "2_2") (pintype "passive"))
      (node (ref "T220") (pin "1") (pinfunction "E_1") (pintype "passive"))
    )
    (net (code "279") (name "Net-(T221-E)") (class "Default")
      (node (ref "J220") (pin "2") (pinfunction "2_2") (pintype "passive"))
      (node (ref "T221") (pin "1") (pinfunction "E_1") (pintype "passive"))
    )
    (net (code "280") (name "Net-(T222-E)") (class "Default")
      (node (ref "J221") (pin "2") (pinfunction "2_2") (pintype "passive"))
      (node (ref "T222") (pin "1") (pinfunction "E_1") (pintype "passive"))
    )
    (net (code "281") (name "Net-(T223-E)") (class "Default")
      (node (ref "J222") (pin "2") (pinfunction "2_2") (pintype "passive"))
      (node (ref "T223") (pin "1") (pinfunction "E_1") (pintype "passive"))
    )
    (net (code "282") (name "Net-(T224-E)") (class "Default")
      (node (ref "J223") (pin "2") (pinfunction "2_2") (pintype "passive"))
      (node (ref "T224") (pin "1") (pinfunction "E_1") (pintype "passive"))
    )
    (net (code "283") (name "Net-(T225-E)") (class "Default")
      (node (ref "J224") (pin "2") (pinfunction "2_2") (pintype "passive"))
      (node (ref "T225") (pin "1") (pinfunction "E_1") (pintype "passive"))
    )
    (net (code "284") (name "Net-(T226-E)") (class "Default")
      (node (ref "J226") (pin "2") (pinfunction "2_2") (pintype "passive"))
      (node (ref "T226") (pin "1") (pinfunction "E_1") (pintype "passive"))
    )
    (net (code "285") (name "Net-(T227-E)") (class "Default")
      (node (ref "J227") (pin "2") (pinfunction "2_2") (pintype "passive"))
      (node (ref "T227") (pin "1") (pinfunction "E_1") (pintype "passive"))
    )
    (net (code "286") (name "Net-(T228-E)") (class "Default")
      (node (ref "J228") (pin "2") (pinfunction "2_2") (pintype "passive"))
      (node (ref "T228") (pin "1") (pinfunction "E_1") (pintype "passive"))
    )
    (net (code "287") (name "Net-(T229-E)") (class "Default")
      (node (ref "J229") (pin "2") (pinfunction "2_2") (pintype "passive"))
      (node (ref "T229") (pin "1") (pinfunction "E_1") (pintype "passive"))
    )
    (net (code "288") (name "Net-(T230-E)") (class "Default")
      (node (ref "J230") (pin "2") (pinfunction "2_2") (pintype "passive"))
      (node (ref "T230") (pin "1") (pinfunction "E_1") (pintype "passive"))
    )
    (net (code "289") (name "Net-(T231-E)") (class "Default")
      (node (ref "J231") (pin "2") (pinfunction "2_2") (pintype "passive"))
      (node (ref "T231") (pin "1") (pinfunction "E_1") (pintype "passive"))
    )
    (net (code "290") (name "Net-(T232-E)") (class "Default")
      (node (ref "J232") (pin "2") (pinfunction "2_2") (pintype "passive"))
      (node (ref "T232") (pin "1") (pinfunction "E_1") (pintype "passive"))
    )
    (net (code "291") (name "Net-(T233-E)") (class "Default")
      (node (ref "J233") (pin "2") (pinfunction "2_2") (pintype "passive"))
      (node (ref "T233") (pin "1") (pinfunction "E_1") (pintype "passive"))
    )
    (net (code "292") (name "Net-(T234-E)") (class "Default")
      (node (ref "J234") (pin "2") (pinfunction "2_2") (pintype "passive"))
      (node (ref "T234") (pin "1") (pinfunction "E_1") (pintype "passive"))
    )
    (net (code "293") (name "Net-(T235-E)") (class "Default")
      (node (ref "J235") (pin "2") (pinfunction "2_2") (pintype "passive"))
      (node (ref "T235") (pin "1") (pinfunction "E_1") (pintype "passive"))
    )
    (net (code "294") (name "Net-(T236-B)") (class "Default")
      (node (ref "J235") (pin "1") (pinfunction "1_1") (pintype "passive"))
      (node (ref "J236") (pin "1") (pinfunction "1_1") (pintype "passive"))
      (node (ref "J237") (pin "1") (pinfunction "1_1") (pintype "passive"))
      (node (ref "J238") (pin "1") (pinfunction "1_1") (pintype "passive"))
      (node (ref "J239") (pin "1") (pinfunction "1_1") (pintype "passive"))
      (node (ref "J240") (pin "1") (pinfunction "1_1") (pintype "passive"))
      (node (ref "J241") (pin "1") (pinfunction "1_1") (pintype "passive"))
      (node (ref "J242") (pin "1") (pinfunction "1_1") (pintype "passive"))
      (node (ref "J243") (pin "1") (pinfunction "1_1") (pintype "passive"))
      (node (ref "J244") (pin "1") (pinfunction "1_1") (pintype "passive"))
      (node (ref "J245") (pin "1") (pinfunction "1_1") (pintype "passive"))
      (node (ref "J246") (pin "1") (pinfunction "1_1") (pintype "passive"))
      (node (ref "J247") (pin "1") (pinfunction "1_1") (pintype "passive"))
      (node (ref "J248") (pin "1") (pinfunction "1_1") (pintype "passive"))
      (node (ref "J249") (pin "1") (pinfunction "1_1") (pintype "passive"))
      (node (ref "J250") (pin "1") (pinfunction "1_1") (pintype "passive"))
      (node (ref "R10") (pin "2") (pinfunction "2_2") (pintype "passive"))
      (node (ref "T236") (pin "2") (pinfunction "B_2") (pintype "passive"))
      (node (ref "T252") (pin "2") (pinfunction "B_2") (pintype "passive"))
      (node (ref "T253") (pin "2") (pinfunction "B_2") (pintype "passive"))
      (node (ref "T254") (pin "2") (pinfunction "B_2") (pintype "passive"))
      (node (ref "T255") (pin "2") (pinfunction "B_2") (pintype "passive"))
      (node (ref "T256") (pin "2") (pinfunction "B_2") (pintype "passive"))
      (node (ref "T257") (pin "2") (pinfunction "B_2") (pintype "passive"))
      (node (ref "T258") (pin "2") (pinfunction "B_2") (pintype "passive"))
      (node (ref "T259") (pin "2") (pinfunction "B_2") (pintype "passive"))
      (node (ref "T260") (pin "2") (pinfunction "B_2") (pintype "passive"))
    )
    (net (code "295") (name "Net-(T236-E)") (class "Default")
      (node (ref "J251") (pin "2") (pinfunction "2_2") (pintype "passive"))
      (node (ref "T236") (pin "1") (pinfunction "E_1") (pintype "passive"))
    )
    (net (code "296") (name "Net-(T237-E)") (class "Default")
      (node (ref "J236") (pin "2") (pinfunction "2_2") (pintype "passive"))
      (node (ref "T237") (pin "1") (pinfunction "E_1") (pintype "passive"))
    )
    (net (code "297") (name "Net-(T238-E)") (class "Default")
      (node (ref "J237") (pin "2") (pinfunction "2_2") (pintype "passive"))
      (node (ref "T238") (pin "1") (pinfunction "E_1") (pintype "passive"))
    )
    (net (code "298") (name "Net-(T239-E)") (class "Default")
      (node (ref "J238") (pin "2") (pinfunction "2_2") (pintype "passive"))
      (node (ref "T239") (pin "1") (pinfunction "E_1") (pintype "passive"))
    )
    (net (code "299") (name "Net-(T240-E)") (class "Default")
      (node (ref "J239") (pin "2") (pinfunction "2_2") (pintype "passive"))
      (node (ref "T240") (pin "1") (pinfunction "E_1") (pintype "passive"))
    )
    (net (code "300") (name "Net-(T241-E)") (class "Default")
      (node (ref "J240") (pin "2") (pinfunction "2_2") (pintype "passive"))
      (node (ref "T241") (pin "1") (pinfunction "E_1") (pintype "passive"))
    )
    (net (code "301") (name "Net-(T242-E)") (class "Default")
      (node (ref "J241") (pin "2") (pinfunction "2_2") (pintype "passive"))
      (node (ref "T242") (pin "1") (pinfunction "E_1") (pintype "passive"))
    )
    (net (code "302") (name "Net-(T243-E)") (class "Default")
      (node (ref "J242") (pin "2") (pinfunction "2_2") (pintype "passive"))
      (node (ref "T243") (pin "1") (pinfunction "E_1") (pintype "passive"))
    )
    (net (code "303") (name "Net-(T244-E)") (class "Default")
      (node (ref "J243") (pin "2") (pinfunction "2_2") (pintype "passive"))
      (node (ref "T244") (pin "1") (pinfunction "E_1") (pintype "passive"))
    )
    (net (code "304") (name "Net-(T245-E)") (class "Default")
      (node (ref "J244") (pin "2") (pinfunction "2_2") (pintype "passive"))
      (node (ref "T245") (pin "1") (pinfunction "E_1") (pintype "passive"))
    )
    (net (code "305") (name "Net-(T246-E)") (class "Default")
      (node (ref "J245") (pin "2") (pinfunction "2_2") (pintype "passive"))
      (node (ref "T246") (pin "1") (pinfunction "E_1") (pintype "passive"))
    )
    (net (code "306") (name "Net-(T247-E)") (class "Default")
      (node (ref "J246") (pin "2") (pinfunction "2_2") (pintype "passive"))
      (node (ref "T247") (pin "1") (pinfunction "E_1") (pintype "passive"))
    )
    (net (code "307") (name "Net-(T248-E)") (class "Default")
      (node (ref "J247") (pin "2") (pinfunction "2_2") (pintype "passive"))
      (node (ref "T248") (pin "1") (pinfunction "E_1") (pintype "passive"))
    )
    (net (code "308") (name "Net-(T249-E)") (class "Default")
      (node (ref "J248") (pin "2") (pinfunction "2_2") (pintype "passive"))
      (node (ref "T249") (pin "1") (pinfunction "E_1") (pintype "passive"))
    )
    (net (code "309") (name "Net-(T250-E)") (class "Default")
      (node (ref "J249") (pin "2") (pinfunction "2_2") (pintype "passive"))
      (node (ref "T250") (pin "1") (pinfunction "E_1") (pintype "passive"))
    )
    (net (code "310") (name "Net-(T251-E)") (class "Default")
      (node (ref "J250") (pin "2") (pinfunction "2_2") (pintype "passive"))
      (node (ref "T251") (pin "1") (pinfunction "E_1") (pintype "passive"))
    )
    (net (code "311") (name "Net-(T252-E)") (class "Default")
      (node (ref "J252") (pin "2") (pinfunction "2_2") (pintype "passive"))
      (node (ref "T252") (pin "1") (pinfunction "E_1") (pintype "passive"))
    )
    (net (code "312") (name "Net-(T253-E)") (class "Default")
      (node (ref "J253") (pin "2") (pinfunction "2_2") (pintype "passive"))
      (node (ref "T253") (pin "1") (pinfunction "E_1") (pintype "passive"))
    )
    (net (code "313") (name "Net-(T254-E)") (class "Default")
      (node (ref "J254") (pin "2") (pinfunction "2_2") (pintype "passive"))
      (node (ref "T254") (pin "1") (pinfunction "E_1") (pintype "passive"))
    )
    (net (code "314") (name "Net-(T255-E)") (class "Default")
      (node (ref "J255") (pin "2") (pinfunction "2_2") (pintype "passive"))
      (node (ref "T255") (pin "1") (pinfunction "E_1") (pintype "passive"))
    )
    (net (code "315") (name "Net-(T256-E)") (class "Default")
      (node (ref "J256") (pin "2") (pinfunction "2_2") (pintype "passive"))
      (node (ref "T256") (pin "1") (pinfunction "E_1") (pintype "passive"))
    )
    (net (code "316") (name "Net-(T257-E)") (class "Default")
      (node (ref "J257") (pin "2") (pinfunction "2_2") (pintype "passive"))
      (node (ref "T257") (pin "1") (pinfunction "E_1") (pintype "passive"))
    )
    (net (code "317") (name "Net-(T258-E)") (class "Default")
      (node (ref "J258") (pin "2") (pinfunction "2_2") (pintype "passive"))
      (node (ref "T258") (pin "1") (pinfunction "E_1") (pintype "passive"))
    )
    (net (code "318") (name "Net-(T259-E)") (class "Default")
      (node (ref "J259") (pin "2") (pinfunction "2_2") (pintype "passive"))
      (node (ref "T259") (pin "1") (pinfunction "E_1") (pintype "passive"))
    )
    (net (code "319") (name "Net-(T260-E)") (class "Default")
      (node (ref "J260") (pin "2") (pinfunction "2_2") (pintype "passive"))
      (node (ref "T260") (pin "1") (pinfunction "E_1") (pintype "passive"))
    )
    (net (code "320") (name "Net-(T261-E)") (class "Default")
      (node (ref "J261") (pin "2") (pinfunction "2_2") (pintype "passive"))
      (node (ref "T261") (pin "1") (pinfunction "E_1") (pintype "passive"))
    )
    (net (code "321") (name "Net-(T262-B)") (class "Default")
      (node (ref "J261") (pin "1") (pinfunction "1_1") (pintype "passive"))
      (node (ref "J262") (pin "1") (pinfunction "1_1") (pintype "passive"))
      (node (ref "J263") (pin "1") (pinfunction "1_1") (pintype "passive"))
      (node (ref "J264") (pin "1") (pinfunction "1_1") (pintype "passive"))
      (node (ref "J265") (pin "1") (pinfunction "1_1") (pintype "passive"))
      (node (ref "J266") (pin "1") (pinfunction "1_1") (pintype "passive"))
      (node (ref "J267") (pin "1") (pinfunction "1_1") (pintype "passive"))
      (node (ref "J268") (pin "1") (pinfunction "1_1") (pintype "passive"))
      (node (ref "J269") (pin "1") (pinfunction "1_1") (pintype "passive"))
      (node (ref "J270") (pin "1") (pinfunction "1_1") (pintype "passive"))
      (node (ref "J271") (pin "1") (pinfunction "1_1") (pintype "passive"))
      (node (ref "J272") (pin "1") (pinfunction "1_1") (pintype "passive"))
      (node (ref "J273") (pin "1") (pinfunction "1_1") (pintype "passive"))
      (node (ref "J274") (pin "1") (pinfunction "1_1") (pintype "passive"))
      (node (ref "J275") (pin "1") (pinfunction "1_1") (pintype "passive"))
      (node (ref "J276") (pin "1") (pinfunction "1_1") (pintype "passive"))
      (node (ref "R11") (pin "2") (pinfunction "2_2") (pintype "passive"))
      (node (ref "T262") (pin "2") (pinfunction "B_2") (pintype "passive"))
      (node (ref "T278") (pin "2") (pinfunction "B_2") (pintype "passive"))
      (node (ref "T279") (pin "2") (pinfunction "B_2") (pintype "passive"))
      (node (ref "T280") (pin "2") (pinfunction "B_2") (pintype "passive"))
      (node (ref "T281") (pin "2") (pinfunction "B_2") (pintype "passive"))
      (node (ref "T282") (pin "2") (pinfunction "B_2") (pintype "passive"))
      (node (ref "T283") (pin "2") (pinfunction "B_2") (pintype "passive"))
      (node (ref "T284") (pin "2") (pinfunction "B_2") (pintype "passive"))
      (node (ref "T285") (pin "2") (pinfunction "B_2") (pintype "passive"))
      (node (ref "T286") (pin "2") (pinfunction "B_2") (pintype "passive"))
    )
    (net (code "322") (name "Net-(T262-E)") (class "Default")
      (node (ref "J277") (pin "2") (pinfunction "2_2") (pintype "passive"))
      (node (ref "T262") (pin "1") (pinfunction "E_1") (pintype "passive"))
    )
    (net (code "323") (name "Net-(T263-E)") (class "Default")
      (node (ref "J262") (pin "2") (pinfunction "2_2") (pintype "passive"))
      (node (ref "T263") (pin "1") (pinfunction "E_1") (pintype "passive"))
    )
    (net (code "324") (name "Net-(T264-E)") (class "Default")
      (node (ref "J263") (pin "2") (pinfunction "2_2") (pintype "passive"))
      (node (ref "T264") (pin "1") (pinfunction "E_1") (pintype "passive"))
    )
    (net (code "325") (name "Net-(T265-E)") (class "Default")
      (node (ref "J264") (pin "2") (pinfunction "2_2") (pintype "passive"))
      (node (ref "T265") (pin "1") (pinfunction "E_1") (pintype "passive"))
    )
    (net (code "326") (name "Net-(T266-E)") (class "Default")
      (node (ref "J265") (pin "2") (pinfunction "2_2") (pintype "passive"))
      (node (ref "T266") (pin "1") (pinfunction "E_1") (pintype "passive"))
    )
    (net (code "327") (name "Net-(T267-E)") (class "Default")
      (node (ref "J266") (pin "2") (pinfunction "2_2") (pintype "passive"))
      (node (ref "T267") (pin "1") (pinfunction "E_1") (pintype "passive"))
    )
    (net (code "328") (name "Net-(T268-E)") (class "Default")
      (node (ref "J267") (pin "2") (pinfunction "2_2") (pintype "passive"))
      (node (ref "T268") (pin "1") (pinfunction "E_1") (pintype "passive"))
    )
    (net (code "329") (name "Net-(T269-E)") (class "Default")
      (node (ref "J268") (pin "2") (pinfunction "2_2") (pintype "passive"))
      (node (ref "T269") (pin "1") (pinfunction "E_1") (pintype "passive"))
    )
    (net (code "330") (name "Net-(T270-E)") (class "Default")
      (node (ref "J269") (pin "2") (pinfunction "2_2") (pintype "passive"))
      (node (ref "T270") (pin "1") (pinfunction "E_1") (pintype "passive"))
    )
    (net (code "331") (name "Net-(T271-E)") (class "Default")
      (node (ref "J270") (pin "2") (pinfunction "2_2") (pintype "passive"))
      (node (ref "T271") (pin "1") (pinfunction "E_1") (pintype "passive"))
    )
    (net (code "332") (name "Net-(T272-E)") (class "Default")
      (node (ref "J271") (pin "2") (pinfunction "2_2") (pintype "passive"))
      (node (ref "T272") (pin "1") (pinfunction "E_1") (pintype "passive"))
    )
    (net (code "333") (name "Net-(T273-E)") (class "Default")
      (node (ref "J272") (pin "2") (pinfunction "2_2") (pintype "passive"))
      (node (ref "T273") (pin "1") (pinfunction "E_1") (pintype "passive"))
    )
    (net (code "334") (name "Net-(T274-E)") (class "Default")
      (node (ref "J273") (pin "2") (pinfunction "2_2") (pintype "passive"))
      (node (ref "T274") (pin "1") (pinfunction "E_1") (pintype "passive"))
    )
    (net (code "335") (name "Net-(T275-E)") (class "Default")
      (node (ref "J274") (pin "2") (pinfunction "2_2") (pintype "passive"))
      (node (ref "T275") (pin "1") (pinfunction "E_1") (pintype "passive"))
    )
    (net (code "336") (name "Net-(T276-E)") (class "Default")
      (node (ref "J275") (pin "2") (pinfunction "2_2") (pintype "passive"))
      (node (ref "T276") (pin "1") (pinfunction "E_1") (pintype "passive"))
    )
    (net (code "337") (name "Net-(T277-E)") (class "Default")
      (node (ref "J276") (pin "2") (pinfunction "2_2") (pintype "passive"))
      (node (ref "T277") (pin "1") (pinfunction "E_1") (pintype "passive"))
    )
    (net (code "338") (name "Net-(T278-E)") (class "Default")
      (node (ref "J278") (pin "2") (pinfunction "2_2") (pintype "passive"))
      (node (ref "T278") (pin "1") (pinfunction "E_1") (pintype "passive"))
    )
    (net (code "339") (name "Net-(T279-E)") (class "Default")
      (node (ref "J279") (pin "2") (pinfunction "2_2") (pintype "passive"))
      (node (ref "T279") (pin "1") (pinfunction "E_1") (pintype "passive"))
    )
    (net (code "340") (name "Net-(T280-E)") (class "Default")
      (node (ref "J280") (pin "2") (pinfunction "2_2") (pintype "passive"))
      (node (ref "T280") (pin "1") (pinfunction "E_1") (pintype "passive"))
    )
    (net (code "341") (name "Net-(T281-E)") (class "Default")
      (node (ref "J281") (pin "2") (pinfunction "2_2") (pintype "passive"))
      (node (ref "T281") (pin "1") (pinfunction "E_1") (pintype "passive"))
    )
    (net (code "342") (name "Net-(T282-E)") (class "Default")
      (node (ref "J282") (pin "2") (pinfunction "2_2") (pintype "passive"))
      (node (ref "T282") (pin "1") (pinfunction "E_1") (pintype "passive"))
    )
    (net (code "343") (name "Net-(T283-E)") (class "Default")
      (node (ref "J283") (pin "2") (pinfunction "2_2") (pintype "passive"))
      (node (ref "T283") (pin "1") (pinfunction "E_1") (pintype "passive"))
    )
    (net (code "344") (name "Net-(T284-E)") (class "Default")
      (node (ref "J284") (pin "2") (pinfunction "2_2") (pintype "passive"))
      (node (ref "T284") (pin "1") (pinfunction "E_1") (pintype "passive"))
    )
    (net (code "345") (name "Net-(T285-E)") (class "Default")
      (node (ref "J285") (pin "2") (pinfunction "2_2") (pintype "passive"))
      (node (ref "T285") (pin "1") (pinfunction "E_1") (pintype "passive"))
    )
    (net (code "346") (name "Net-(T286-E)") (class "Default")
      (node (ref "J286") (pin "2") (pinfunction "2_2") (pintype "passive"))
      (node (ref "T286") (pin "1") (pinfunction "E_1") (pintype "passive"))
    )
    (net (code "347") (name "Net-(T287-E)") (class "Default")
      (node (ref "J287") (pin "2") (pinfunction "2_2") (pintype "passive"))
      (node (ref "T287") (pin "1") (pinfunction "E_1") (pintype "passive"))
    )
    (net (code "348") (name "Net-(T288-B)") (class "Default")
      (node (ref "J287") (pin "1") (pinfunction "1_1") (pintype "passive"))
      (node (ref "J288") (pin "1") (pinfunction "1_1") (pintype "passive"))
      (node (ref "J289") (pin "1") (pinfunction "1_1") (pintype "passive"))
      (node (ref "J290") (pin "1") (pinfunction "1_1") (pintype "passive"))
      (node (ref "J291") (pin "1") (pinfunction "1_1") (pintype "passive"))
      (node (ref "J292") (pin "1") (pinfunction "1_1") (pintype "passive"))
      (node (ref "J293") (pin "1") (pinfunction "1_1") (pintype "passive"))
      (node (ref "J294") (pin "1") (pinfunction "1_1") (pintype "passive"))
      (node (ref "J295") (pin "1") (pinfunction "1_1") (pintype "passive"))
      (node (ref "J296") (pin "1") (pinfunction "1_1") (pintype "passive"))
      (node (ref "J297") (pin "1") (pinfunction "1_1") (pintype "passive"))
      (node (ref "J298") (pin "1") (pinfunction "1_1") (pintype "passive"))
      (node (ref "J299") (pin "1") (pinfunction "1_1") (pintype "passive"))
      (node (ref "J300") (pin "1") (pinfunction "1_1") (pintype "passive"))
      (node (ref "J301") (pin "1") (pinfunction "1_1") (pintype "passive"))
      (node (ref "J302") (pin "1") (pinfunction "1_1") (pintype "passive"))
      (node (ref "R12") (pin "2") (pinfunction "2_2") (pintype "passive"))
      (node (ref "T288") (pin "2") (pinfunction "B_2") (pintype "passive"))
      (node (ref "T304") (pin "2") (pinfunction "B_2") (pintype "passive"))
      (node (ref "T305") (pin "2") (pinfunction "B_2") (pintype "passive"))
      (node (ref "T306") (pin "2") (pinfunction "B_2") (pintype "passive"))
      (node (ref "T307") (pin "2") (pinfunction "B_2") (pintype "passive"))
      (node (ref "T308") (pin "2") (pinfunction "B_2") (pintype "passive"))
      (node (ref "T309") (pin "2") (pinfunction "B_2") (pintype "passive"))
      (node (ref "T310") (pin "2") (pinfunction "B_2") (pintype "passive"))
      (node (ref "T311") (pin "2") (pinfunction "B_2") (pintype "passive"))
      (node (ref "T312") (pin "2") (pinfunction "B_2") (pintype "passive"))
    )
    (net (code "349") (name "Net-(T288-E)") (class "Default")
      (node (ref "J303") (pin "2") (pinfunction "2_2") (pintype "passive"))
      (node (ref "T288") (pin "1") (pinfunction "E_1") (pintype "passive"))
    )
    (net (code "350") (name "Net-(T289-E)") (class "Default")
      (node (ref "J288") (pin "2") (pinfunction "2_2") (pintype "passive"))
      (node (ref "T289") (pin "1") (pinfunction "E_1") (pintype "passive"))
    )
    (net (code "351") (name "Net-(T290-E)") (class "Default")
      (node (ref "J289") (pin "2") (pinfunction "2_2") (pintype "passive"))
      (node (ref "T290") (pin "1") (pinfunction "E_1") (pintype "passive"))
    )
    (net (code "352") (name "Net-(T291-E)") (class "Default")
      (node (ref "J290") (pin "2") (pinfunction "2_2") (pintype "passive"))
      (node (ref "T291") (pin "1") (pinfunction "E_1") (pintype "passive"))
    )
    (net (code "353") (name "Net-(T292-E)") (class "Default")
      (node (ref "J291") (pin "2") (pinfunction "2_2") (pintype "passive"))
      (node (ref "T292") (pin "1") (pinfunction "E_1") (pintype "passive"))
    )
    (net (code "354") (name "Net-(T293-E)") (class "Default")
      (node (ref "J292") (pin "2") (pinfunction "2_2") (pintype "passive"))
      (node (ref "T293") (pin "1") (pinfunction "E_1") (pintype "passive"))
    )
    (net (code "355") (name "Net-(T294-E)") (class "Default")
      (node (ref "J293") (pin "2") (pinfunction "2_2") (pintype "passive"))
      (node (ref "T294") (pin "1") (pinfunction "E_1") (pintype "passive"))
    )
    (net (code "356") (name "Net-(T295-E)") (class "Default")
      (node (ref "J294") (pin "2") (pinfunction "2_2") (pintype "passive"))
      (node (ref "T295") (pin "1") (pinfunction "E_1") (pintype "passive"))
    )
    (net (code "357") (name "Net-(T296-E)") (class "Default")
      (node (ref "J295") (pin "2") (pinfunction "2_2") (pintype "passive"))
      (node (ref "T296") (pin "1") (pinfunction "E_1") (pintype "passive"))
    )
    (net (code "358") (name "Net-(T297-E)") (class "Default")
      (node (ref "J296") (pin "2") (pinfunction "2_2") (pintype "passive"))
      (node (ref "T297") (pin "1") (pinfunction "E_1") (pintype "passive"))
    )
    (net (code "359") (name "Net-(T298-E)") (class "Default")
      (node (ref "J297") (pin "2") (pinfunction "2_2") (pintype "passive"))
      (node (ref "T298") (pin "1") (pinfunction "E_1") (pintype "passive"))
    )
    (net (code "360") (name "Net-(T299-E)") (class "Default")
      (node (ref "J298") (pin "2") (pinfunction "2_2") (pintype "passive"))
      (node (ref "T299") (pin "1") (pinfunction "E_1") (pintype "passive"))
    )
    (net (code "361") (name "Net-(T300-E)") (class "Default")
      (node (ref "J299") (pin "2") (pinfunction "2_2") (pintype "passive"))
      (node (ref "T300") (pin "1") (pinfunction "E_1") (pintype "passive"))
    )
    (net (code "362") (name "Net-(T301-E)") (class "Default")
      (node (ref "J300") (pin "2") (pinfunction "2_2") (pintype "passive"))
      (node (ref "T301") (pin "1") (pinfunction "E_1") (pintype "passive"))
    )
    (net (code "363") (name "Net-(T302-E)") (class "Default")
      (node (ref "J301") (pin "2") (pinfunction "2_2") (pintype "passive"))
      (node (ref "T302") (pin "1") (pinfunction "E_1") (pintype "passive"))
    )
    (net (code "364") (name "Net-(T303-E)") (class "Default")
      (node (ref "J302") (pin "2") (pinfunction "2_2") (pintype "passive"))
      (node (ref "T303") (pin "1") (pinfunction "E_1") (pintype "passive"))
    )
    (net (code "365") (name "Net-(T304-E)") (class "Default")
      (node (ref "J304") (pin "2") (pinfunction "2_2") (pintype "passive"))
      (node (ref "T304") (pin "1") (pinfunction "E_1") (pintype "passive"))
    )
    (net (code "366") (name "Net-(T305-E)") (class "Default")
      (node (ref "J305") (pin "2") (pinfunction "2_2") (pintype "passive"))
      (node (ref "T305") (pin "1") (pinfunction "E_1") (pintype "passive"))
    )
    (net (code "367") (name "Net-(T306-E)") (class "Default")
      (node (ref "J306") (pin "2") (pinfunction "2_2") (pintype "passive"))
      (node (ref "T306") (pin "1") (pinfunction "E_1") (pintype "passive"))
    )
    (net (code "368") (name "Net-(T307-E)") (class "Default")
      (node (ref "J307") (pin "2") (pinfunction "2_2") (pintype "passive"))
      (node (ref "T307") (pin "1") (pinfunction "E_1") (pintype "passive"))
    )
    (net (code "369") (name "Net-(T308-E)") (class "Default")
      (node (ref "J308") (pin "2") (pinfunction "2_2") (pintype "passive"))
      (node (ref "T308") (pin "1") (pinfunction "E_1") (pintype "passive"))
    )
    (net (code "370") (name "Net-(T309-E)") (class "Default")
      (node (ref "J309") (pin "2") (pinfunction "2_2") (pintype "passive"))
      (node (ref "T309") (pin "1") (pinfunction "E_1") (pintype "passive"))
    )
    (net (code "371") (name "Net-(T310-E)") (class "Default")
      (node (ref "J310") (pin "2") (pinfunction "2_2") (pintype "passive"))
      (node (ref "T310") (pin "1") (pinfunction "E_1") (pintype "passive"))
    )
    (net (code "372") (name "Net-(T311-E)") (class "Default")
      (node (ref "J311") (pin "2") (pinfunction "2_2") (pintype "passive"))
      (node (ref "T311") (pin "1") (pinfunction "E_1") (pintype "passive"))
    )
    (net (code "373") (name "Net-(T312-E)") (class "Default")
      (node (ref "J312") (pin "2") (pinfunction "2_2") (pintype "passive"))
      (node (ref "T312") (pin "1") (pinfunction "E_1") (pintype "passive"))
    )
    (net (code "374") (name "Net-(T313-E)") (class "Default")
      (node (ref "J313") (pin "2") (pinfunction "2_2") (pintype "passive"))
      (node (ref "T313") (pin "1") (pinfunction "E_1") (pintype "passive"))
    )
    (net (code "375") (name "Net-(T314-B)") (class "Default")
      (node (ref "J313") (pin "1") (pinfunction "1_1") (pintype "passive"))
      (node (ref "J314") (pin "1") (pinfunction "1_1") (pintype "passive"))
      (node (ref "J315") (pin "1") (pinfunction "1_1") (pintype "passive"))
      (node (ref "J316") (pin "1") (pinfunction "1_1") (pintype "passive"))
      (node (ref "J317") (pin "1") (pinfunction "1_1") (pintype "passive"))
      (node (ref "J318") (pin "1") (pinfunction "1_1") (pintype "passive"))
      (node (ref "J319") (pin "1") (pinfunction "1_1") (pintype "passive"))
      (node (ref "J320") (pin "1") (pinfunction "1_1") (pintype "passive"))
      (node (ref "J321") (pin "1") (pinfunction "1_1") (pintype "passive"))
      (node (ref "J322") (pin "1") (pinfunction "1_1") (pintype "passive"))
      (node (ref "J323") (pin "1") (pinfunction "1_1") (pintype "passive"))
      (node (ref "J324") (pin "1") (pinfunction "1_1") (pintype "passive"))
      (node (ref "J325") (pin "1") (pinfunction "1_1") (pintype "passive"))
      (node (ref "J326") (pin "1") (pinfunction "1_1") (pintype "passive"))
      (node (ref "J327") (pin "1") (pinfunction "1_1") (pintype "passive"))
      (node (ref "J328") (pin "1") (pinfunction "1_1") (pintype "passive"))
      (node (ref "R13") (pin "2") (pinfunction "2_2") (pintype "passive"))
      (node (ref "T314") (pin "2") (pinfunction "B_2") (pintype "passive"))
      (node (ref "T330") (pin "2") (pinfunction "B_2") (pintype "passive"))
      (node (ref "T331") (pin "2") (pinfunction "B_2") (pintype "passive"))
      (node (ref "T332") (pin "2") (pinfunction "B_2") (pintype "passive"))
      (node (ref "T333") (pin "2") (pinfunction "B_2") (pintype "passive"))
      (node (ref "T334") (pin "2") (pinfunction "B_2") (pintype "passive"))
      (node (ref "T335") (pin "2") (pinfunction "B_2") (pintype "passive"))
      (node (ref "T336") (pin "2") (pinfunction "B_2") (pintype "passive"))
      (node (ref "T337") (pin "2") (pinfunction "B_2") (pintype "passive"))
      (node (ref "T338") (pin "2") (pinfunction "B_2") (pintype "passive"))
    )
    (net (code "376") (name "Net-(T314-E)") (class "Default")
      (node (ref "J329") (pin "2") (pinfunction "2_2") (pintype "passive"))
      (node (ref "T314") (pin "1") (pinfunction "E_1") (pintype "passive"))
    )
    (net (code "377") (name "Net-(T315-E)") (class "Default")
      (node (ref "J314") (pin "2") (pinfunction "2_2") (pintype "passive"))
      (node (ref "T315") (pin "1") (pinfunction "E_1") (pintype "passive"))
    )
    (net (code "378") (name "Net-(T316-E)") (class "Default")
      (node (ref "J315") (pin "2") (pinfunction "2_2") (pintype "passive"))
      (node (ref "T316") (pin "1") (pinfunction "E_1") (pintype "passive"))
    )
    (net (code "379") (name "Net-(T317-E)") (class "Default")
      (node (ref "J316") (pin "2") (pinfunction "2_2") (pintype "passive"))
      (node (ref "T317") (pin "1") (pinfunction "E_1") (pintype "passive"))
    )
    (net (code "380") (name "Net-(T318-E)") (class "Default")
      (node (ref "J317") (pin "2") (pinfunction "2_2") (pintype "passive"))
      (node (ref "T318") (pin "1") (pinfunction "E_1") (pintype "passive"))
    )
    (net (code "381") (name "Net-(T319-E)") (class "Default")
      (node (ref "J318") (pin "2") (pinfunction "2_2") (pintype "passive"))
      (node (ref "T319") (pin "1") (pinfunction "E_1") (pintype "passive"))
    )
    (net (code "382") (name "Net-(T320-E)") (class "Default")
      (node (ref "J319") (pin "2") (pinfunction "2_2") (pintype "passive"))
      (node (ref "T320") (pin "1") (pinfunction "E_1") (pintype "passive"))
    )
    (net (code "383") (name "Net-(T321-E)") (class "Default")
      (node (ref "J320") (pin "2") (pinfunction "2_2") (pintype "passive"))
      (node (ref "T321") (pin "1") (pinfunction "E_1") (pintype "passive"))
    )
    (net (code "384") (name "Net-(T322-E)") (class "Default")
      (node (ref "J321") (pin "2") (pinfunction "2_2") (pintype "passive"))
      (node (ref "T322") (pin "1") (pinfunction "E_1") (pintype "passive"))
    )
    (net (code "385") (name "Net-(T323-E)") (class "Default")
      (node (ref "J322") (pin "2") (pinfunction "2_2") (pintype "passive"))
      (node (ref "T323") (pin "1") (pinfunction "E_1") (pintype "passive"))
    )
    (net (code "386") (name "Net-(T324-E)") (class "Default")
      (node (ref "J323") (pin "2") (pinfunction "2_2") (pintype "passive"))
      (node (ref "T324") (pin "1") (pinfunction "E_1") (pintype "passive"))
    )
    (net (code "387") (name "Net-(T325-E)") (class "Default")
      (node (ref "J324") (pin "2") (pinfunction "2_2") (pintype "passive"))
      (node (ref "T325") (pin "1") (pinfunction "E_1") (pintype "passive"))
    )
    (net (code "388") (name "Net-(T326-E)") (class "Default")
      (node (ref "J325") (pin "2") (pinfunction "2_2") (pintype "passive"))
      (node (ref "T326") (pin "1") (pinfunction "E_1") (pintype "passive"))
    )
    (net (code "389") (name "Net-(T327-E)") (class "Default")
      (node (ref "J326") (pin "2") (pinfunction "2_2") (pintype "passive"))
      (node (ref "T327") (pin "1") (pinfunction "E_1") (pintype "passive"))
    )
    (net (code "390") (name "Net-(T328-E)") (class "Default")
      (node (ref "J327") (pin "2") (pinfunction "2_2") (pintype "passive"))
      (node (ref "T328") (pin "1") (pinfunction "E_1") (pintype "passive"))
    )
    (net (code "391") (name "Net-(T329-E)") (class "Default")
      (node (ref "J328") (pin "2") (pinfunction "2_2") (pintype "passive"))
      (node (ref "T329") (pin "1") (pinfunction "E_1") (pintype "passive"))
    )
    (net (code "392") (name "Net-(T330-E)") (class "Default")
      (node (ref "J330") (pin "2") (pinfunction "2_2") (pintype "passive"))
      (node (ref "T330") (pin "1") (pinfunction "E_1") (pintype "passive"))
    )
    (net (code "393") (name "Net-(T331-E)") (class "Default")
      (node (ref "J331") (pin "2") (pinfunction "2_2") (pintype "passive"))
      (node (ref "T331") (pin "1") (pinfunction "E_1") (pintype "passive"))
    )
    (net (code "394") (name "Net-(T332-E)") (class "Default")
      (node (ref "J332") (pin "2") (pinfunction "2_2") (pintype "passive"))
      (node (ref "T332") (pin "1") (pinfunction "E_1") (pintype "passive"))
    )
    (net (code "395") (name "Net-(T333-E)") (class "Default")
      (node (ref "J333") (pin "2") (pinfunction "2_2") (pintype "passive"))
      (node (ref "T333") (pin "1") (pinfunction "E_1") (pintype "passive"))
    )
    (net (code "396") (name "Net-(T334-E)") (class "Default")
      (node (ref "J334") (pin "2") (pinfunction "2_2") (pintype "passive"))
      (node (ref "T334") (pin "1") (pinfunction "E_1") (pintype "passive"))
    )
    (net (code "397") (name "Net-(T335-E)") (class "Default")
      (node (ref "J335") (pin "2") (pinfunction "2_2") (pintype "passive"))
      (node (ref "T335") (pin "1") (pinfunction "E_1") (pintype "passive"))
    )
    (net (code "398") (name "Net-(T336-E)") (class "Default")
      (node (ref "J336") (pin "2") (pinfunction "2_2") (pintype "passive"))
      (node (ref "T336") (pin "1") (pinfunction "E_1") (pintype "passive"))
    )
    (net (code "399") (name "Net-(T337-E)") (class "Default")
      (node (ref "J337") (pin "2") (pinfunction "2_2") (pintype "passive"))
      (node (ref "T337") (pin "1") (pinfunction "E_1") (pintype "passive"))
    )
    (net (code "400") (name "Net-(T338-E)") (class "Default")
      (node (ref "J338") (pin "2") (pinfunction "2_2") (pintype "passive"))
      (node (ref "T338") (pin "1") (pinfunction "E_1") (pintype "passive"))
    )
    (net (code "401") (name "Net-(T339-E)") (class "Default")
      (node (ref "J339") (pin "2") (pinfunction "2_2") (pintype "passive"))
      (node (ref "T339") (pin "1") (pinfunction "E_1") (pintype "passive"))
    )
    (net (code "402") (name "Net-(T340-B)") (class "Default")
      (node (ref "J339") (pin "1") (pinfunction "1_1") (pintype "passive"))
      (node (ref "J340") (pin "1") (pinfunction "1_1") (pintype "passive"))
      (node (ref "J341") (pin "1") (pinfunction "1_1") (pintype "passive"))
      (node (ref "J342") (pin "1") (pinfunction "1_1") (pintype "passive"))
      (node (ref "J343") (pin "1") (pinfunction "1_1") (pintype "passive"))
      (node (ref "J344") (pin "1") (pinfunction "1_1") (pintype "passive"))
      (node (ref "J345") (pin "1") (pinfunction "1_1") (pintype "passive"))
      (node (ref "J346") (pin "1") (pinfunction "1_1") (pintype "passive"))
      (node (ref "J347") (pin "1") (pinfunction "1_1") (pintype "passive"))
      (node (ref "J348") (pin "1") (pinfunction "1_1") (pintype "passive"))
      (node (ref "J349") (pin "1") (pinfunction "1_1") (pintype "passive"))
      (node (ref "J350") (pin "1") (pinfunction "1_1") (pintype "passive"))
      (node (ref "J351") (pin "1") (pinfunction "1_1") (pintype "passive"))
      (node (ref "J352") (pin "1") (pinfunction "1_1") (pintype "passive"))
      (node (ref "J353") (pin "1") (pinfunction "1_1") (pintype "passive"))
      (node (ref "J354") (pin "1") (pinfunction "1_1") (pintype "passive"))
      (node (ref "R14") (pin "2") (pinfunction "2_2") (pintype "passive"))
      (node (ref "T340") (pin "2") (pinfunction "B_2") (pintype "passive"))
      (node (ref "T356") (pin "2") (pinfunction "B_2") (pintype "passive"))
      (node (ref "T357") (pin "2") (pinfunction "B_2") (pintype "passive"))
      (node (ref "T358") (pin "2") (pinfunction "B_2") (pintype "passive"))
      (node (ref "T359") (pin "2") (pinfunction "B_2") (pintype "passive"))
      (node (ref "T360") (pin "2") (pinfunction "B_2") (pintype "passive"))
      (node (ref "T361") (pin "2") (pinfunction "B_2") (pintype "passive"))
      (node (ref "T362") (pin "2") (pinfunction "B_2") (pintype "passive"))
      (node (ref "T363") (pin "2") (pinfunction "B_2") (pintype "passive"))
      (node (ref "T364") (pin "2") (pinfunction "B_2") (pintype "passive"))
    )
    (net (code "403") (name "Net-(T340-E)") (class "Default")
      (node (ref "J355") (pin "2") (pinfunction "2_2") (pintype "passive"))
      (node (ref "T340") (pin "1") (pinfunction "E_1") (pintype "passive"))
    )
    (net (code "404") (name "Net-(T341-E)") (class "Default")
      (node (ref "J340") (pin "2") (pinfunction "2_2") (pintype "passive"))
      (node (ref "T341") (pin "1") (pinfunction "E_1") (pintype "passive"))
    )
    (net (code "405") (name "Net-(T342-E)") (class "Default")
      (node (ref "J341") (pin "2") (pinfunction "2_2") (pintype "passive"))
      (node (ref "T342") (pin "1") (pinfunction "E_1") (pintype "passive"))
    )
    (net (code "406") (name "Net-(T343-E)") (class "Default")
      (node (ref "J342") (pin "2") (pinfunction "2_2") (pintype "passive"))
      (node (ref "T343") (pin "1") (pinfunction "E_1") (pintype "passive"))
    )
    (net (code "407") (name "Net-(T344-E)") (class "Default")
      (node (ref "J343") (pin "2") (pinfunction "2_2") (pintype "passive"))
      (node (ref "T344") (pin "1") (pinfunction "E_1") (pintype "passive"))
    )
    (net (code "408") (name "Net-(T345-E)") (class "Default")
      (node (ref "J344") (pin "2") (pinfunction "2_2") (pintype "passive"))
      (node (ref "T345") (pin "1") (pinfunction "E_1") (pintype "passive"))
    )
    (net (code "409") (name "Net-(T346-E)") (class "Default")
      (node (ref "J345") (pin "2") (pinfunction "2_2") (pintype "passive"))
      (node (ref "T346") (pin "1") (pinfunction "E_1") (pintype "passive"))
    )
    (net (code "410") (name "Net-(T347-E)") (class "Default")
      (node (ref "J346") (pin "2") (pinfunction "2_2") (pintype "passive"))
      (node (ref "T347") (pin "1") (pinfunction "E_1") (pintype "passive"))
    )
    (net (code "411") (name "Net-(T348-E)") (class "Default")
      (node (ref "J347") (pin "2") (pinfunction "2_2") (pintype "passive"))
      (node (ref "T348") (pin "1") (pinfunction "E_1") (pintype "passive"))
    )
    (net (code "412") (name "Net-(T349-E)") (class "Default")
      (node (ref "J348") (pin "2") (pinfunction "2_2") (pintype "passive"))
      (node (ref "T349") (pin "1") (pinfunction "E_1") (pintype "passive"))
    )
    (net (code "413") (name "Net-(T350-E)") (class "Default")
      (node (ref "J349") (pin "2") (pinfunction "2_2") (pintype "passive"))
      (node (ref "T350") (pin "1") (pinfunction "E_1") (pintype "passive"))
    )
    (net (code "414") (name "Net-(T351-E)") (class "Default")
      (node (ref "J350") (pin "2") (pinfunction "2_2") (pintype "passive"))
      (node (ref "T351") (pin "1") (pinfunction "E_1") (pintype "passive"))
    )
    (net (code "415") (name "Net-(T352-E)") (class "Default")
      (node (ref "J351") (pin "2") (pinfunction "2_2") (pintype "passive"))
      (node (ref "T352") (pin "1") (pinfunction "E_1") (pintype "passive"))
    )
    (net (code "416") (name "Net-(T353-E)") (class "Default")
      (node (ref "J352") (pin "2") (pinfunction "2_2") (pintype "passive"))
      (node (ref "T353") (pin "1") (pinfunction "E_1") (pintype "passive"))
    )
    (net (code "417") (name "Net-(T354-E)") (class "Default")
      (node (ref "J353") (pin "2") (pinfunction "2_2") (pintype "passive"))
      (node (ref "T354") (pin "1") (pinfunction "E_1") (pintype "passive"))
    )
    (net (code "418") (name "Net-(T355-E)") (class "Default")
      (node (ref "J354") (pin "2") (pinfunction "2_2") (pintype "passive"))
      (node (ref "T355") (pin "1") (pinfunction "E_1") (pintype "passive"))
    )
    (net (code "419") (name "Net-(T356-E)") (class "Default")
      (node (ref "J356") (pin "2") (pinfunction "2_2") (pintype "passive"))
      (node (ref "T356") (pin "1") (pinfunction "E_1") (pintype "passive"))
    )
    (net (code "420") (name "Net-(T357-E)") (class "Default")
      (node (ref "J357") (pin "2") (pinfunction "2_2") (pintype "passive"))
      (node (ref "T357") (pin "1") (pinfunction "E_1") (pintype "passive"))
    )
    (net (code "421") (name "Net-(T358-E)") (class "Default")
      (node (ref "J358") (pin "2") (pinfunction "2_2") (pintype "passive"))
      (node (ref "T358") (pin "1") (pinfunction "E_1") (pintype "passive"))
    )
    (net (code "422") (name "Net-(T359-E)") (class "Default")
      (node (ref "J359") (pin "2") (pinfunction "2_2") (pintype "passive"))
      (node (ref "T359") (pin "1") (pinfunction "E_1") (pintype "passive"))
    )
    (net (code "423") (name "Net-(T360-E)") (class "Default")
      (node (ref "J360") (pin "2") (pinfunction "2_2") (pintype "passive"))
      (node (ref "T360") (pin "1") (pinfunction "E_1") (pintype "passive"))
    )
    (net (code "424") (name "Net-(T361-E)") (class "Default")
      (node (ref "J361") (pin "2") (pinfunction "2_2") (pintype "passive"))
      (node (ref "T361") (pin "1") (pinfunction "E_1") (pintype "passive"))
    )
    (net (code "425") (name "Net-(T362-E)") (class "Default")
      (node (ref "J362") (pin "2") (pinfunction "2_2") (pintype "passive"))
      (node (ref "T362") (pin "1") (pinfunction "E_1") (pintype "passive"))
    )
    (net (code "426") (name "Net-(T363-E)") (class "Default")
      (node (ref "J363") (pin "2") (pinfunction "2_2") (pintype "passive"))
      (node (ref "T363") (pin "1") (pinfunction "E_1") (pintype "passive"))
    )
    (net (code "427") (name "Net-(T364-E)") (class "Default")
      (node (ref "J364") (pin "2") (pinfunction "2_2") (pintype "passive"))
      (node (ref "T364") (pin "1") (pinfunction "E_1") (pintype "passive"))
    )
    (net (code "428") (name "Net-(T365-E)") (class "Default")
      (node (ref "J365") (pin "2") (pinfunction "2_2") (pintype "passive"))
      (node (ref "T365") (pin "1") (pinfunction "E_1") (pintype "passive"))
    )
    (net (code "429") (name "Net-(T366-B)") (class "Default")
      (node (ref "J365") (pin "1") (pinfunction "1_1") (pintype "passive"))
      (node (ref "J366") (pin "1") (pinfunction "1_1") (pintype "passive"))
      (node (ref "J367") (pin "1") (pinfunction "1_1") (pintype "passive"))
      (node (ref "J368") (pin "1") (pinfunction "1_1") (pintype "passive"))
      (node (ref "J369") (pin "1") (pinfunction "1_1") (pintype "passive"))
      (node (ref "J370") (pin "1") (pinfunction "1_1") (pintype "passive"))
      (node (ref "J371") (pin "1") (pinfunction "1_1") (pintype "passive"))
      (node (ref "J372") (pin "1") (pinfunction "1_1") (pintype "passive"))
      (node (ref "J373") (pin "1") (pinfunction "1_1") (pintype "passive"))
      (node (ref "J374") (pin "1") (pinfunction "1_1") (pintype "passive"))
      (node (ref "J375") (pin "1") (pinfunction "1_1") (pintype "passive"))
      (node (ref "J376") (pin "1") (pinfunction "1_1") (pintype "passive"))
      (node (ref "J377") (pin "1") (pinfunction "1_1") (pintype "passive"))
      (node (ref "J378") (pin "1") (pinfunction "1_1") (pintype "passive"))
      (node (ref "J379") (pin "1") (pinfunction "1_1") (pintype "passive"))
      (node (ref "J380") (pin "1") (pinfunction "1_1") (pintype "passive"))
      (node (ref "R15") (pin "2") (pinfunction "2_2") (pintype "passive"))
      (node (ref "T366") (pin "2") (pinfunction "B_2") (pintype "passive"))
      (node (ref "T382") (pin "2") (pinfunction "B_2") (pintype "passive"))
      (node (ref "T383") (pin "2") (pinfunction "B_2") (pintype "passive"))
      (node (ref "T384") (pin "2") (pinfunction "B_2") (pintype "passive"))
      (node (ref "T385") (pin "2") (pinfunction "B_2") (pintype "passive"))
      (node (ref "T386") (pin "2") (pinfunction "B_2") (pintype "passive"))
      (node (ref "T387") (pin "2") (pinfunction "B_2") (pintype "passive"))
      (node (ref "T388") (pin "2") (pinfunction "B_2") (pintype "passive"))
      (node (ref "T389") (pin "2") (pinfunction "B_2") (pintype "passive"))
      (node (ref "T390") (pin "2") (pinfunction "B_2") (pintype "passive"))
    )
    (net (code "430") (name "Net-(T366-E)") (class "Default")
      (node (ref "J381") (pin "2") (pinfunction "2_2") (pintype "passive"))
      (node (ref "T366") (pin "1") (pinfunction "E_1") (pintype "passive"))
    )
    (net (code "431") (name "Net-(T367-E)") (class "Default")
      (node (ref "J366") (pin "2") (pinfunction "2_2") (pintype "passive"))
      (node (ref "T367") (pin "1") (pinfunction "E_1") (pintype "passive"))
    )
    (net (code "432") (name "Net-(T368-E)") (class "Default")
      (node (ref "J367") (pin "2") (pinfunction "2_2") (pintype "passive"))
      (node (ref "T368") (pin "1") (pinfunction "E_1") (pintype "passive"))
    )
    (net (code "433") (name "Net-(T369-E)") (class "Default")
      (node (ref "J368") (pin "2") (pinfunction "2_2") (pintype "passive"))
      (node (ref "T369") (pin "1") (pinfunction "E_1") (pintype "passive"))
    )
    (net (code "434") (name "Net-(T370-E)") (class "Default")
      (node (ref "J369") (pin "2") (pinfunction "2_2") (pintype "passive"))
      (node (ref "T370") (pin "1") (pinfunction "E_1") (pintype "passive"))
    )
    (net (code "435") (name "Net-(T371-E)") (class "Default")
      (node (ref "J370") (pin "2") (pinfunction "2_2") (pintype "passive"))
      (node (ref "T371") (pin "1") (pinfunction "E_1") (pintype "passive"))
    )
    (net (code "436") (name "Net-(T372-E)") (class "Default")
      (node (ref "J371") (pin "2") (pinfunction "2_2") (pintype "passive"))
      (node (ref "T372") (pin "1") (pinfunction "E_1") (pintype "passive"))
    )
    (net (code "437") (name "Net-(T373-E)") (class "Default")
      (node (ref "J372") (pin "2") (pinfunction "2_2") (pintype "passive"))
      (node (ref "T373") (pin "1") (pinfunction "E_1") (pintype "passive"))
    )
    (net (code "438") (name "Net-(T374-E)") (class "Default")
      (node (ref "J373") (pin "2") (pinfunction "2_2") (pintype "passive"))
      (node (ref "T374") (pin "1") (pinfunction "E_1") (pintype "passive"))
    )
    (net (code "439") (name "Net-(T375-E)") (class "Default")
      (node (ref "J374") (pin "2") (pinfunction "2_2") (pintype "passive"))
      (node (ref "T375") (pin "1") (pinfunction "E_1") (pintype "passive"))
    )
    (net (code "440") (name "Net-(T376-E)") (class "Default")
      (node (ref "J375") (pin "2") (pinfunction "2_2") (pintype "passive"))
      (node (ref "T376") (pin "1") (pinfunction "E_1") (pintype "passive"))
    )
    (net (code "441") (name "Net-(T377-E)") (class "Default")
      (node (ref "J376") (pin "2") (pinfunction "2_2") (pintype "passive"))
      (node (ref "T377") (pin "1") (pinfunction "E_1") (pintype "passive"))
    )
    (net (code "442") (name "Net-(T378-E)") (class "Default")
      (node (ref "J377") (pin "2") (pinfunction "2_2") (pintype "passive"))
      (node (ref "T378") (pin "1") (pinfunction "E_1") (pintype "passive"))
    )
    (net (code "443") (name "Net-(T379-E)") (class "Default")
      (node (ref "J378") (pin "2") (pinfunction "2_2") (pintype "passive"))
      (node (ref "T379") (pin "1") (pinfunction "E_1") (pintype "passive"))
    )
    (net (code "444") (name "Net-(T380-E)") (class "Default")
      (node (ref "J379") (pin "2") (pinfunction "2_2") (pintype "passive"))
      (node (ref "T380") (pin "1") (pinfunction "E_1") (pintype "passive"))
    )
    (net (code "445") (name "Net-(T381-E)") (class "Default")
      (node (ref "J380") (pin "2") (pinfunction "2_2") (pintype "passive"))
      (node (ref "T381") (pin "1") (pinfunction "E_1") (pintype "passive"))
    )
    (net (code "446") (name "Net-(T382-E)") (class "Default")
      (node (ref "J382") (pin "2") (pinfunction "2_2") (pintype "passive"))
      (node (ref "T382") (pin "1") (pinfunction "E_1") (pintype "passive"))
    )
    (net (code "447") (name "Net-(T383-E)") (class "Default")
      (node (ref "J383") (pin "2") (pinfunction "2_2") (pintype "passive"))
      (node (ref "T383") (pin "1") (pinfunction "E_1") (pintype "passive"))
    )
    (net (code "448") (name "Net-(T384-E)") (class "Default")
      (node (ref "J384") (pin "2") (pinfunction "2_2") (pintype "passive"))
      (node (ref "T384") (pin "1") (pinfunction "E_1") (pintype "passive"))
    )
    (net (code "449") (name "Net-(T385-E)") (class "Default")
      (node (ref "J385") (pin "2") (pinfunction "2_2") (pintype "passive"))
      (node (ref "T385") (pin "1") (pinfunction "E_1") (pintype "passive"))
    )
    (net (code "450") (name "Net-(T386-E)") (class "Default")
      (node (ref "J386") (pin "2") (pinfunction "2_2") (pintype "passive"))
      (node (ref "T386") (pin "1") (pinfunction "E_1") (pintype "passive"))
    )
    (net (code "451") (name "Net-(T387-E)") (class "Default")
      (node (ref "J387") (pin "2") (pinfunction "2_2") (pintype "passive"))
      (node (ref "T387") (pin "1") (pinfunction "E_1") (pintype "passive"))
    )
    (net (code "452") (name "Net-(T388-E)") (class "Default")
      (node (ref "J388") (pin "2") (pinfunction "2_2") (pintype "passive"))
      (node (ref "T388") (pin "1") (pinfunction "E_1") (pintype "passive"))
    )
    (net (code "453") (name "Net-(T389-E)") (class "Default")
      (node (ref "J389") (pin "2") (pinfunction "2_2") (pintype "passive"))
      (node (ref "T389") (pin "1") (pinfunction "E_1") (pintype "passive"))
    )
    (net (code "454") (name "Net-(T390-E)") (class "Default")
      (node (ref "J390") (pin "2") (pinfunction "2_2") (pintype "passive"))
      (node (ref "T390") (pin "1") (pinfunction "E_1") (pintype "passive"))
    )
    (net (code "455") (name "Net-(T391-E)") (class "Default")
      (node (ref "J391") (pin "2") (pinfunction "2_2") (pintype "passive"))
      (node (ref "T391") (pin "1") (pinfunction "E_1") (pintype "passive"))
    )
    (net (code "456") (name "Net-(T392-B)") (class "Default")
      (node (ref "J391") (pin "1") (pinfunction "1_1") (pintype "passive"))
      (node (ref "J392") (pin "1") (pinfunction "1_1") (pintype "passive"))
      (node (ref "J393") (pin "1") (pinfunction "1_1") (pintype "passive"))
      (node (ref "J394") (pin "1") (pinfunction "1_1") (pintype "passive"))
      (node (ref "J395") (pin "1") (pinfunction "1_1") (pintype "passive"))
      (node (ref "J396") (pin "1") (pinfunction "1_1") (pintype "passive"))
      (node (ref "J397") (pin "1") (pinfunction "1_1") (pintype "passive"))
      (node (ref "J398") (pin "1") (pinfunction "1_1") (pintype "passive"))
      (node (ref "J399") (pin "1") (pinfunction "1_1") (pintype "passive"))
      (node (ref "J400") (pin "1") (pinfunction "1_1") (pintype "passive"))
      (node (ref "J401") (pin "1") (pinfunction "1_1") (pintype "passive"))
      (node (ref "J402") (pin "1") (pinfunction "1_1") (pintype "passive"))
      (node (ref "J403") (pin "1") (pinfunction "1_1") (pintype "passive"))
      (node (ref "J404") (pin "1") (pinfunction "1_1") (pintype "passive"))
      (node (ref "J405") (pin "1") (pinfunction "1_1") (pintype "passive"))
      (node (ref "J406") (pin "1") (pinfunction "1_1") (pintype "passive"))
      (node (ref "R16") (pin "2") (pinfunction "2_2") (pintype "passive"))
      (node (ref "T392") (pin "2") (pinfunction "B_2") (pintype "passive"))
      (node (ref "T408") (pin "2") (pinfunction "B_2") (pintype "passive"))
      (node (ref "T409") (pin "2") (pinfunction "B_2") (pintype "passive"))
      (node (ref "T410") (pin "2") (pinfunction "B_2") (pintype "passive"))
      (node (ref "T411") (pin "2") (pinfunction "B_2") (pintype "passive"))
      (node (ref "T412") (pin "2") (pinfunction "B_2") (pintype "passive"))
      (node (ref "T413") (pin "2") (pinfunction "B_2") (pintype "passive"))
      (node (ref "T414") (pin "2") (pinfunction "B_2") (pintype "passive"))
      (node (ref "T415") (pin "2") (pinfunction "B_2") (pintype "passive"))
      (node (ref "T416") (pin "2") (pinfunction "B_2") (pintype "passive"))
    )
    (net (code "457") (name "Net-(T392-E)") (class "Default")
      (node (ref "J407") (pin "2") (pinfunction "2_2") (pintype "passive"))
      (node (ref "T392") (pin "1") (pinfunction "E_1") (pintype "passive"))
    )
    (net (code "458") (name "Net-(T393-E)") (class "Default")
      (node (ref "J392") (pin "2") (pinfunction "2_2") (pintype "passive"))
      (node (ref "T393") (pin "1") (pinfunction "E_1") (pintype "passive"))
    )
    (net (code "459") (name "Net-(T394-E)") (class "Default")
      (node (ref "J393") (pin "2") (pinfunction "2_2") (pintype "passive"))
      (node (ref "T394") (pin "1") (pinfunction "E_1") (pintype "passive"))
    )
    (net (code "460") (name "Net-(T395-E)") (class "Default")
      (node (ref "J394") (pin "2") (pinfunction "2_2") (pintype "passive"))
      (node (ref "T395") (pin "1") (pinfunction "E_1") (pintype "passive"))
    )
    (net (code "461") (name "Net-(T396-E)") (class "Default")
      (node (ref "J395") (pin "2") (pinfunction "2_2") (pintype "passive"))
      (node (ref "T396") (pin "1") (pinfunction "E_1") (pintype "passive"))
    )
    (net (code "462") (name "Net-(T397-E)") (class "Default")
      (node (ref "J396") (pin "2") (pinfunction "2_2") (pintype "passive"))
      (node (ref "T397") (pin "1") (pinfunction "E_1") (pintype "passive"))
    )
    (net (code "463") (name "Net-(T398-E)") (class "Default")
      (node (ref "J397") (pin "2") (pinfunction "2_2") (pintype "passive"))
      (node (ref "T398") (pin "1") (pinfunction "E_1") (pintype "passive"))
    )
    (net (code "464") (name "Net-(T399-E)") (class "Default")
      (node (ref "J398") (pin "2") (pinfunction "2_2") (pintype "passive"))
      (node (ref "T399") (pin "1") (pinfunction "E_1") (pintype "passive"))
    )
    (net (code "465") (name "Net-(T400-E)") (class "Default")
      (node (ref "J399") (pin "2") (pinfunction "2_2") (pintype "passive"))
      (node (ref "T400") (pin "1") (pinfunction "E_1") (pintype "passive"))
    )
    (net (code "466") (name "Net-(T401-E)") (class "Default")
      (node (ref "J400") (pin "2") (pinfunction "2_2") (pintype "passive"))
      (node (ref "T401") (pin "1") (pinfunction "E_1") (pintype "passive"))
    )
    (net (code "467") (name "Net-(T402-E)") (class "Default")
      (node (ref "J401") (pin "2") (pinfunction "2_2") (pintype "passive"))
      (node (ref "T402") (pin "1") (pinfunction "E_1") (pintype "passive"))
    )
    (net (code "468") (name "Net-(T403-E)") (class "Default")
      (node (ref "J402") (pin "2") (pinfunction "2_2") (pintype "passive"))
      (node (ref "T403") (pin "1") (pinfunction "E_1") (pintype "passive"))
    )
    (net (code "469") (name "Net-(T404-E)") (class "Default")
      (node (ref "J403") (pin "2") (pinfunction "2_2") (pintype "passive"))
      (node (ref "T404") (pin "1") (pinfunction "E_1") (pintype "passive"))
    )
    (net (code "470") (name "Net-(T405-E)") (class "Default")
      (node (ref "J404") (pin "2") (pinfunction "2_2") (pintype "passive"))
      (node (ref "T405") (pin "1") (pinfunction "E_1") (pintype "passive"))
    )
    (net (code "471") (name "Net-(T406-E)") (class "Default")
      (node (ref "J405") (pin "2") (pinfunction "2_2") (pintype "passive"))
      (node (ref "T406") (pin "1") (pinfunction "E_1") (pintype "passive"))
    )
    (net (code "472") (name "Net-(T407-E)") (class "Default")
      (node (ref "J406") (pin "2") (pinfunction "2_2") (pintype "passive"))
      (node (ref "T407") (pin "1") (pinfunction "E_1") (pintype "passive"))
    )
    (net (code "473") (name "Net-(T408-E)") (class "Default")
      (node (ref "J408") (pin "2") (pinfunction "2_2") (pintype "passive"))
      (node (ref "T408") (pin "1") (pinfunction "E_1") (pintype "passive"))
    )
    (net (code "474") (name "Net-(T409-E)") (class "Default")
      (node (ref "J409") (pin "2") (pinfunction "2_2") (pintype "passive"))
      (node (ref "T409") (pin "1") (pinfunction "E_1") (pintype "passive"))
    )
    (net (code "475") (name "Net-(T410-E)") (class "Default")
      (node (ref "J410") (pin "2") (pinfunction "2_2") (pintype "passive"))
      (node (ref "T410") (pin "1") (pinfunction "E_1") (pintype "passive"))
    )
    (net (code "476") (name "Net-(T411-E)") (class "Default")
      (node (ref "J411") (pin "2") (pinfunction "2_2") (pintype "passive"))
      (node (ref "T411") (pin "1") (pinfunction "E_1") (pintype "passive"))
    )
    (net (code "477") (name "Net-(T412-E)") (class "Default")
      (node (ref "J412") (pin "2") (pinfunction "2_2") (pintype "passive"))
      (node (ref "T412") (pin "1") (pinfunction "E_1") (pintype "passive"))
    )
    (net (code "478") (name "Net-(T413-E)") (class "Default")
      (node (ref "J413") (pin "2") (pinfunction "2_2") (pintype "passive"))
      (node (ref "T413") (pin "1") (pinfunction "E_1") (pintype "passive"))
    )
    (net (code "479") (name "Net-(T414-E)") (class "Default")
      (node (ref "J414") (pin "2") (pinfunction "2_2") (pintype "passive"))
      (node (ref "T414") (pin "1") (pinfunction "E_1") (pintype "passive"))
    )
    (net (code "480") (name "Net-(T415-E)") (class "Default")
      (node (ref "J415") (pin "2") (pinfunction "2_2") (pintype "passive"))
      (node (ref "T415") (pin "1") (pinfunction "E_1") (pintype "passive"))
    )
    (net (code "481") (name "Net-(T416-E)") (class "Default")
      (node (ref "J416") (pin "2") (pinfunction "2_2") (pintype "passive"))
      (node (ref "T416") (pin "1") (pinfunction "E_1") (pintype "passive"))
    )
    (net (code "482") (name "Q0") (class "Default")
      (node (ref "J121") (pin "1") (pinfunction "1_1") (pintype "passive"))
      (node (ref "J147") (pin "1") (pinfunction "1_1") (pintype "passive"))
      (node (ref "J17") (pin "1") (pinfunction "1_1") (pintype "passive"))
      (node (ref "J173") (pin "1") (pinfunction "1_1") (pintype "passive"))
      (node (ref "J199") (pin "1") (pinfunction "1_1") (pintype "passive"))
      (node (ref "J225") (pin "1") (pinfunction "1_1") (pintype "passive"))
      (node (ref "J251") (pin "1") (pinfunction "1_1") (pintype "passive"))
      (node (ref "J277") (pin "1") (pinfunction "1_1") (pintype "passive"))
      (node (ref "J303") (pin "1") (pinfunction "1_1") (pintype "passive"))
      (node (ref "J329") (pin "1") (pinfunction "1_1") (pintype "passive"))
      (node (ref "J355") (pin "1") (pinfunction "1_1") (pintype "passive"))
      (node (ref "J381") (pin "1") (pinfunction "1_1") (pintype "passive"))
      (node (ref "J407") (pin "1") (pinfunction "1_1") (pintype "passive"))
      (node (ref "J43") (pin "1") (pinfunction "1_1") (pintype "passive"))
      (node (ref "J69") (pin "1") (pinfunction "1_1") (pintype "passive"))
      (node (ref "J95") (pin "1") (pinfunction "1_1") (pintype "passive"))
    )
    (net (code "483") (name "Q1") (class "Default")
      (node (ref "J122") (pin "1") (pinfunction "1_1") (pintype "passive"))
      (node (ref "J148") (pin "1") (pinfunction "1_1") (pintype "passive"))
      (node (ref "J174") (pin "1") (pinfunction "1_1") (pintype "passive"))
      (node (ref "J18") (pin "1") (pinfunction "1_1") (pintype "passive"))
      (node (ref "J200") (pin "1") (pinfunction "1_1") (pintype "passive"))
      (node (ref "J226") (pin "1") (pinfunction "1_1") (pintype "passive"))
      (node (ref "J252") (pin "1") (pinfunction "1_1") (pintype "passive"))
      (node (ref "J278") (pin "1") (pinfunction "1_1") (pintype "passive"))
      (node (ref "J304") (pin "1") (pinfunction "1_1") (pintype "passive"))
      (node (ref "J330") (pin "1") (pinfunction "1_1") (pintype "passive"))
      (node (ref "J356") (pin "1") (pinfunction "1_1") (pintype "passive"))
      (node (ref "J382") (pin "1") (pinfunction "1_1") (pintype "passive"))
      (node (ref "J408") (pin "1") (pinfunction "1_1") (pintype "passive"))
      (node (ref "J44") (pin "1") (pinfunction "1_1") (pintype "passive"))
      (node (ref "J70") (pin "1") (pinfunction "1_1") (pintype "passive"))
      (node (ref "J96") (pin "1") (pinfunction "1_1") (pintype "passive"))
    )
    (net (code "484") (name "Q2") (class "Default")
      (node (ref "J123") (pin "1") (pinfunction "1_1") (pintype "passive"))
      (node (ref "J149") (pin "1") (pinfunction "1_1") (pintype "passive"))
      (node (ref "J175") (pin "1") (pinfunction "1_1") (pintype "passive"))
      (node (ref "J19") (pin "1") (pinfunction "1_1") (pintype "passive"))
      (node (ref "J201") (pin "1") (pinfunction "1_1") (pintype "passive"))
      (node (ref "J227") (pin "1") (pinfunction "1_1") (pintype "passive"))
      (node (ref "J253") (pin "1") (pinfunction "1_1") (pintype "passive"))
      (node (ref "J279") (pin "1") (pinfunction "1_1") (pintype "passive"))
      (node (ref "J305") (pin "1") (pinfunction "1_1") (pintype "passive"))
      (node (ref "J331") (pin "1") (pinfunction "1_1") (pintype "passive"))
      (node (ref "J357") (pin "1") (pinfunction "1_1") (pintype "passive"))
      (node (ref "J383") (pin "1") (pinfunction "1_1") (pintype "passive"))
      (node (ref "J409") (pin "1") (pinfunction "1_1") (pintype "passive"))
      (node (ref "J45") (pin "1") (pinfunction "1_1") (pintype "passive"))
      (node (ref "J71") (pin "1") (pinfunction "1_1") (pintype "passive"))
      (node (ref "J97") (pin "1") (pinfunction "1_1") (pintype "passive"))
    )
    (net (code "485") (name "Q3") (class "Default")
      (node (ref "J124") (pin "1") (pinfunction "1_1") (pintype "passive"))
      (node (ref "J150") (pin "1") (pinfunction "1_1") (pintype "passive"))
      (node (ref "J176") (pin "1") (pinfunction "1_1") (pintype "passive"))
      (node (ref "J20") (pin "1") (pinfunction "1_1") (pintype "passive"))
      (node (ref "J202") (pin "1") (pinfunction "1_1") (pintype "passive"))
      (node (ref "J228") (pin "1") (pinfunction "1_1") (pintype "passive"))
      (node (ref "J254") (pin "1") (pinfunction "1_1") (pintype "passive"))
      (node (ref "J280") (pin "1") (pinfunction "1_1") (pintype "passive"))
      (node (ref "J306") (pin "1") (pinfunction "1_1") (pintype "passive"))
      (node (ref "J332") (pin "1") (pinfunction "1_1") (pintype "passive"))
      (node (ref "J358") (pin "1") (pinfunction "1_1") (pintype "passive"))
      (node (ref "J384") (pin "1") (pinfunction "1_1") (pintype "passive"))
      (node (ref "J410") (pin "1") (pinfunction "1_1") (pintype "passive"))
      (node (ref "J46") (pin "1") (pinfunction "1_1") (pintype "passive"))
      (node (ref "J72") (pin "1") (pinfunction "1_1") (pintype "passive"))
      (node (ref "J98") (pin "1") (pinfunction "1_1") (pintype "passive"))
    )
    (net (code "486") (name "Q4") (class "Default")
      (node (ref "J125") (pin "1") (pinfunction "1_1") (pintype "passive"))
      (node (ref "J151") (pin "1") (pinfunction "1_1") (pintype "passive"))
      (node (ref "J177") (pin "1") (pinfunction "1_1") (pintype "passive"))
      (node (ref "J203") (pin "1") (pinfunction "1_1") (pintype "passive"))
      (node (ref "J21") (pin "1") (pinfunction "1_1") (pintype "passive"))
      (node (ref "J229") (pin "1") (pinfunction "1_1") (pintype "passive"))
      (node (ref "J255") (pin "1") (pinfunction "1_1") (pintype "passive"))
      (node (ref "J281") (pin "1") (pinfunction "1_1") (pintype "passive"))
      (node (ref "J307") (pin "1") (pinfunction "1_1") (pintype "passive"))
      (node (ref "J333") (pin "1") (pinfunction "1_1") (pintype "passive"))
      (node (ref "J359") (pin "1") (pinfunction "1_1") (pintype "passive"))
      (node (ref "J385") (pin "1") (pinfunction "1_1") (pintype "passive"))
      (node (ref "J411") (pin "1") (pinfunction "1_1") (pintype "passive"))
      (node (ref "J47") (pin "1") (pinfunction "1_1") (pintype "passive"))
      (node (ref "J73") (pin "1") (pinfunction "1_1") (pintype "passive"))
      (node (ref "J99") (pin "1") (pinfunction "1_1") (pintype "passive"))
    )
    (net (code "487") (name "Q5") (class "Default")
      (node (ref "J100") (pin "1") (pinfunction "1_1") (pintype "passive"))
      (node (ref "J126") (pin "1") (pinfunction "1_1") (pintype "passive"))
      (node (ref "J152") (pin "1") (pinfunction "1_1") (pintype "passive"))
      (node (ref "J178") (pin "1") (pinfunction "1_1") (pintype "passive"))
      (node (ref "J204") (pin "1") (pinfunction "1_1") (pintype "passive"))
      (node (ref "J22") (pin "1") (pinfunction "1_1") (pintype "passive"))
      (node (ref "J230") (pin "1") (pinfunction "1_1") (pintype "passive"))
      (node (ref "J256") (pin "1") (pinfunction "1_1") (pintype "passive"))
      (node (ref "J282") (pin "1") (pinfunction "1_1") (pintype "passive"))
      (node (ref "J308") (pin "1") (pinfunction "1_1") (pintype "passive"))
      (node (ref "J334") (pin "1") (pinfunction "1_1") (pintype "passive"))
      (node (ref "J360") (pin "1") (pinfunction "1_1") (pintype "passive"))
      (node (ref "J386") (pin "1") (pinfunction "1_1") (pintype "passive"))
      (node (ref "J412") (pin "1") (pinfunction "1_1") (pintype "passive"))
      (node (ref "J48") (pin "1") (pinfunction "1_1") (pintype "passive"))
      (node (ref "J74") (pin "1") (pinfunction "1_1") (pintype "passive"))
    )
    (net (code "488") (name "Q6") (class "Default")
      (node (ref "J101") (pin "1") (pinfunction "1_1") (pintype "passive"))
      (node (ref "J127") (pin "1") (pinfunction "1_1") (pintype "passive"))
      (node (ref "J153") (pin "1") (pinfunction "1_1") (pintype "passive"))
      (node (ref "J179") (pin "1") (pinfunction "1_1") (pintype "passive"))
      (node (ref "J205") (pin "1") (pinfunction "1_1") (pintype "passive"))
      (node (ref "J23") (pin "1") (pinfunction "1_1") (pintype "passive"))
      (node (ref "J231") (pin "1") (pinfunction "1_1") (pintype "passive"))
      (node (ref "J257") (pin "1") (pinfunction "1_1") (pintype "passive"))
      (node (ref "J283") (pin "1") (pinfunction "1_1") (pintype "passive"))
      (node (ref "J309") (pin "1") (pinfunction "1_1") (pintype "passive"))
      (node (ref "J335") (pin "1") (pinfunction "1_1") (pintype "passive"))
      (node (ref "J361") (pin "1") (pinfunction "1_1") (pintype "passive"))
      (node (ref "J387") (pin "1") (pinfunction "1_1") (pintype "passive"))
      (node (ref "J413") (pin "1") (pinfunction "1_1") (pintype "passive"))
      (node (ref "J49") (pin "1") (pinfunction "1_1") (pintype "passive"))
      (node (ref "J75") (pin "1") (pinfunction "1_1") (pintype "passive"))
    )
    (net (code "489") (name "Q7") (class "Default")
      (node (ref "J102") (pin "1") (pinfunction "1_1") (pintype "passive"))
      (node (ref "J128") (pin "1") (pinfunction "1_1") (pintype "passive"))
      (node (ref "J154") (pin "1") (pinfunction "1_1") (pintype "passive"))
      (node (ref "J180") (pin "1") (pinfunction "1_1") (pintype "passive"))
      (node (ref "J206") (pin "1") (pinfunction "1_1") (pintype "passive"))
      (node (ref "J232") (pin "1") (pinfunction "1_1") (pintype "passive"))
      (node (ref "J24") (pin "1") (pinfunction "1_1") (pintype "passive"))
      (node (ref "J258") (pin "1") (pinfunction "1_1") (pintype "passive"))
      (node (ref "J284") (pin "1") (pinfunction "1_1") (pintype "passive"))
      (node (ref "J310") (pin "1") (pinfunction "1_1") (pintype "passive"))
      (node (ref "J336") (pin "1") (pinfunction "1_1") (pintype "passive"))
      (node (ref "J362") (pin "1") (pinfunction "1_1") (pintype "passive"))
      (node (ref "J388") (pin "1") (pinfunction "1_1") (pintype "passive"))
      (node (ref "J414") (pin "1") (pinfunction "1_1") (pintype "passive"))
      (node (ref "J50") (pin "1") (pinfunction "1_1") (pintype "passive"))
      (node (ref "J76") (pin "1") (pinfunction "1_1") (pintype "passive"))
    )
    (net (code "490") (name "Q8") (class "Default")
      (node (ref "J103") (pin "1") (pinfunction "1_1") (pintype "passive"))
      (node (ref "J129") (pin "1") (pinfunction "1_1") (pintype "passive"))
      (node (ref "J155") (pin "1") (pinfunction "1_1") (pintype "passive"))
      (node (ref "J181") (pin "1") (pinfunction "1_1") (pintype "passive"))
      (node (ref "J207") (pin "1") (pinfunction "1_1") (pintype "passive"))
      (node (ref "J233") (pin "1") (pinfunction "1_1") (pintype "passive"))
      (node (ref "J25") (pin "1") (pinfunction "1_1") (pintype "passive"))
      (node (ref "J259") (pin "1") (pinfunction "1_1") (pintype "passive"))
      (node (ref "J285") (pin "1") (pinfunction "1_1") (pintype "passive"))
      (node (ref "J311") (pin "1") (pinfunction "1_1") (pintype "passive"))
      (node (ref "J337") (pin "1") (pinfunction "1_1") (pintype "passive"))
      (node (ref "J363") (pin "1") (pinfunction "1_1") (pintype "passive"))
      (node (ref "J389") (pin "1") (pinfunction "1_1") (pintype "passive"))
      (node (ref "J415") (pin "1") (pinfunction "1_1") (pintype "passive"))
      (node (ref "J51") (pin "1") (pinfunction "1_1") (pintype "passive"))
      (node (ref "J77") (pin "1") (pinfunction "1_1") (pintype "passive"))
    )
    (net (code "491") (name "Q9") (class "Default")
      (node (ref "J104") (pin "1") (pinfunction "1_1") (pintype "passive"))
      (node (ref "J130") (pin "1") (pinfunction "1_1") (pintype "passive"))
      (node (ref "J156") (pin "1") (pinfunction "1_1") (pintype "passive"))
      (node (ref "J182") (pin "1") (pinfunction "1_1") (pintype "passive"))
      (node (ref "J208") (pin "1") (pinfunction "1_1") (pintype "passive"))
      (node (ref "J234") (pin "1") (pinfunction "1_1") (pintype "passive"))
      (node (ref "J26") (pin "1") (pinfunction "1_1") (pintype "passive"))
      (node (ref "J260") (pin "1") (pinfunction "1_1") (pintype "passive"))
      (node (ref "J286") (pin "1") (pinfunction "1_1") (pintype "passive"))
      (node (ref "J312") (pin "1") (pinfunction "1_1") (pintype "passive"))
      (node (ref "J338") (pin "1") (pinfunction "1_1") (pintype "passive"))
      (node (ref "J364") (pin "1") (pinfunction "1_1") (pintype "passive"))
      (node (ref "J390") (pin "1") (pinfunction "1_1") (pintype "passive"))
      (node (ref "J416") (pin "1") (pinfunction "1_1") (pintype "passive"))
      (node (ref "J52") (pin "1") (pinfunction "1_1") (pintype "passive"))
      (node (ref "J78") (pin "1") (pinfunction "1_1") (pintype "passive"))
    )
    (net (code "492") (name "VCC") (class "Default")
      (node (ref "C1") (pin "2") (pinfunction "2_2") (pintype "passive"))
      (node (ref "C10") (pin "2") (pinfunction "2_2") (pintype "passive"))
      (node (ref "C11") (pin "2") (pinfunction "2_2") (pintype "passive"))
      (node (ref "C12") (pin "2") (pinfunction "2_2") (pintype "passive"))
      (node (ref "C13") (pin "2") (pinfunction "2_2") (pintype "passive"))
      (node (ref "C14") (pin "2") (pinfunction "2_2") (pintype "passive"))
      (node (ref "C15") (pin "2") (pinfunction "2_2") (pintype "passive"))
      (node (ref "C16") (pin "2") (pinfunction "2_2") (pintype "passive"))
      (node (ref "C2") (pin "2") (pinfunction "2_2") (pintype "passive"))
      (node (ref "C3") (pin "2") (pinfunction "2_2") (pintype "passive"))
      (node (ref "C4") (pin "2") (pinfunction "2_2") (pintype "passive"))
      (node (ref "C5") (pin "2") (pinfunction "2_2") (pintype "passive"))
      (node (ref "C6") (pin "2") (pinfunction "2_2") (pintype "passive"))
      (node (ref "C7") (pin "2") (pinfunction "2_2") (pintype "passive"))
      (node (ref "C8") (pin "2") (pinfunction "2_2") (pintype "passive"))
      (node (ref "C9") (pin "2") (pinfunction "2_2") (pintype "passive"))
      (node (ref "R1") (pin "1") (pinfunction "1_1") (pintype "passive"))
      (node (ref "R10") (pin "1") (pinfunction "1_1") (pintype "passive"))
      (node (ref "R11") (pin "1") (pinfunction "1_1") (pintype "passive"))
      (node (ref "R12") (pin "1") (pinfunction "1_1") (pintype "passive"))
      (node (ref "R13") (pin "1") (pinfunction "1_1") (pintype "passive"))
      (node (ref "R14") (pin "1") (pinfunction "1_1") (pintype "passive"))
      (node (ref "R15") (pin "1") (pinfunction "1_1") (pintype "passive"))
      (node (ref "R16") (pin "1") (pinfunction "1_1") (pintype "passive"))
      (node (ref "R2") (pin "1") (pinfunction "1_1") (pintype "passive"))
      (node (ref "R3") (pin "1") (pinfunction "1_1") (pintype "passive"))
      (node (ref "R4") (pin "1") (pinfunction "1_1") (pintype "passive"))
      (node (ref "R5") (pin "1") (pinfunction "1_1") (pintype "passive"))
      (node (ref "R6") (pin "1") (pinfunction "1_1") (pintype "passive"))
      (node (ref "R7") (pin "1") (pinfunction "1_1") (pintype "passive"))
      (node (ref "R8") (pin "1") (pinfunction "1_1") (pintype "passive"))
      (node (ref "R9") (pin "1") (pinfunction "1_1") (pintype "passive"))
      (node (ref "T100") (pin "3") (pinfunction "C_3") (pintype "passive"))
      (node (ref "T101") (pin "3") (pinfunction "C_3") (pintype "passive"))
      (node (ref "T102") (pin "3") (pinfunction "C_3") (pintype "passive"))
      (node (ref "T103") (pin "3") (pinfunction "C_3") (pintype "passive"))
      (node (ref "T104") (pin "3") (pinfunction "C_3") (pintype "passive"))
      (node (ref "T106") (pin "3") (pinfunction "C_3") (pintype "passive"))
      (node (ref "T122") (pin "3") (pinfunction "C_3") (pintype "passive"))
      (node (ref "T123") (pin "3") (pinfunction "C_3") (pintype "passive"))
      (node (ref "T124") (pin "3") (pinfunction "C_3") (pintype "passive"))
      (node (ref "T125") (pin "3") (pinfunction "C_3") (pintype "passive"))
      (node (ref "T126") (pin "3") (pinfunction "C_3") (pintype "passive"))
      (node (ref "T127") (pin "3") (pinfunction "C_3") (pintype "passive"))
      (node (ref "T128") (pin "3") (pinfunction "C_3") (pintype "passive"))
      (node (ref "T129") (pin "3") (pinfunction "C_3") (pintype "passive"))
      (node (ref "T130") (pin "3") (pinfunction "C_3") (pintype "passive"))
      (node (ref "T132") (pin "3") (pinfunction "C_3") (pintype "passive"))
      (node (ref "T148") (pin "3") (pinfunction "C_3") (pintype "passive"))
      (node (ref "T149") (pin "3") (pinfunction "C_3") (pintype "passive"))
      (node (ref "T150") (pin "3") (pinfunction "C_3") (pintype "passive"))
      (node (ref "T151") (pin "3") (pinfunction "C_3") (pintype "passive"))
      (node (ref "T152") (pin "3") (pinfunction "C_3") (pintype "passive"))
      (node (ref "T153") (pin "3") (pinfunction "C_3") (pintype "passive"))
      (node (ref "T154") (pin "3") (pinfunction "C_3") (pintype "passive"))
      (node (ref "T155") (pin "3") (pinfunction "C_3") (pintype "passive"))
      (node (ref "T156") (pin "3") (pinfunction "C_3") (pintype "passive"))
      (node (ref "T158") (pin "3") (pinfunction "C_3") (pintype "passive"))
      (node (ref "T17") (pin "3") (pinfunction "C_3") (pintype "passive"))
      (node (ref "T174") (pin "3") (pinfunction "C_3") (pintype "passive"))
      (node (ref "T175") (pin "3") (pinfunction "C_3") (pintype "passive"))
      (node (ref "T176") (pin "3") (pinfunction "C_3") (pintype "passive"))
      (node (ref "T177") (pin "3") (pinfunction "C_3") (pintype "passive"))
      (node (ref "T178") (pin "3") (pinfunction "C_3") (pintype "passive"))
      (node (ref "T179") (pin "3") (pinfunction "C_3") (pintype "passive"))
      (node (ref "T18") (pin "3") (pinfunction "C_3") (pintype "passive"))
      (node (ref "T180") (pin "3") (pinfunction "C_3") (pintype "passive"))
      (node (ref "T181") (pin "3") (pinfunction "C_3") (pintype "passive"))
      (node (ref "T182") (pin "3") (pinfunction "C_3") (pintype "passive"))
      (node (ref "T184") (pin "3") (pinfunction "C_3") (pintype "passive"))
      (node (ref "T19") (pin "3") (pinfunction "C_3") (pintype "passive"))
      (node (ref "T20") (pin "3") (pinfunction "C_3") (pintype "passive"))
      (node (ref "T200") (pin "3") (pinfunction "C_3") (pintype "passive"))
      (node (ref "T201") (pin "3") (pinfunction "C_3") (pintype "passive"))
      (node (ref "T202") (pin "3") (pinfunction "C_3") (pintype "passive"))
      (node (ref "T203") (pin "3") (pinfunction "C_3") (pintype "passive"))
      (node (ref "T204") (pin "3") (pinfunction "C_3") (pintype "passive"))
      (node (ref "T205") (pin "3") (pinfunction "C_3") (pintype "passive"))
      (node (ref "T206") (pin "3") (pinfunction "C_3") (pintype "passive"))
      (node (ref "T207") (pin "3") (pinfunction "C_3") (pintype "passive"))
      (node (ref "T208") (pin "3") (pinfunction "C_3") (pintype "passive"))
      (node (ref "T21") (pin "3") (pinfunction "C_3") (pintype "passive"))
      (node (ref "T210") (pin "3") (pinfunction "C_3") (pintype "passive"))
      (node (ref "T22") (pin "3") (pinfunction "C_3") (pintype "passive"))
      (node (ref "T226") (pin "3") (pinfunction "C_3") (pintype "passive"))
      (node (ref "T227") (pin "3") (pinfunction "C_3") (pintype "passive"))
      (node (ref "T228") (pin "3") (pinfunction "C_3") (pintype "passive"))
      (node (ref "T229") (pin "3") (pinfunction "C_3") (pintype "passive"))
      (node (ref "T23") (pin "3") (pinfunction "C_3") (pintype "passive"))
      (node (ref "T230") (pin "3") (pinfunction "C_3") (pintype "passive"))
      (node (ref "T231") (pin "3") (pinfunction "C_3") (pintype "passive"))
      (node (ref "T232") (pin "3") (pinfunction "C_3") (pintype "passive"))
      (node (ref "T233") (pin "3") (pinfunction "C_3") (pintype "passive"))
      (node (ref "T234") (pin "3") (pinfunction "C_3") (pintype "passive"))
      (node (ref "T236") (pin "3") (pinfunction "C_3") (pintype "passive"))
      (node (ref "T24") (pin "3") (pinfunction "C_3") (pintype "passive"))
      (node (ref "T25") (pin "3") (pinfunction "C_3") (pintype "passive"))
      (node (ref "T252") (pin "3") (pinfunction "C_3") (pintype "passive"))
      (node (ref "T253") (pin "3") (pinfunction "C_3") (pintype "passive"))
      (node (ref "T254") (pin "3") (pinfunction "C_3") (pintype "passive"))
      (node (ref "T255") (pin "3") (pinfunction "C_3") (pintype "passive"))
      (node (ref "T256") (pin "3") (pinfunction "C_3") (pintype "passive"))
      (node (ref "T257") (pin "3") (pinfunction "C_3") (pintype "passive"))
      (node (ref "T258") (pin "3") (pinfunction "C_3") (pintype "passive"))
      (node (ref "T259") (pin "3") (pinfunction "C_3") (pintype "passive"))
      (node (ref "T26") (pin "3") (pinfunction "C_3") (pintype "passive"))
      (node (ref "T260") (pin "3") (pinfunction "C_3") (pintype "passive"))
      (node (ref "T262") (pin "3") (pinfunction "C_3") (pintype "passive"))
      (node (ref "T278") (pin "3") (pinfunction "C_3") (pintype "passive"))
      (node (ref "T279") (pin "3") (pinfunction "C_3") (pintype "passive"))
      (node (ref "T28") (pin "3") (pinfunction "C_3") (pintype "passive"))
      (node (ref "T280") (pin "3") (pinfunction "C_3") (pintype "passive"))
      (node (ref "T281") (pin "3") (pinfunction "C_3") (pintype "passive"))
      (node (ref "T282") (pin "3") (pinfunction "C_3") (pintype "passive"))
      (node (ref "T283") (pin "3") (pinfunction "C_3") (pintype "passive"))
      (node (ref "T284") (pin "3") (pinfunction "C_3") (pintype "passive"))
      (node (ref "T285") (pin "3") (pinfunction "C_3") (pintype "passive"))
      (node (ref "T286") (pin "3") (pinfunction "C_3") (pintype "passive"))
      (node (ref "T288") (pin "3") (pinfunction "C_3") (pintype "passive"))
      (node (ref "T304") (pin "3") (pinfunction "C_3") (pintype "passive"))
      (node (ref "T305") (pin "3") (pinfunction "C_3") (pintype "passive"))
      (node (ref "T306") (pin "3") (pinfunction "C_3") (pintype "passive"))
      (node (ref "T307") (pin "3") (pinfunction "C_3") (pintype "passive"))
      (node (ref "T308") (pin "3") (pinfunction "C_3") (pintype "passive"))
      (node (ref "T309") (pin "3") (pinfunction "C_3") (pintype "passive"))
      (node (ref "T310") (pin "3") (pinfunction "C_3") (pintype "passive"))
      (node (ref "T311") (pin "3") (pinfunction "C_3") (pintype "passive"))
      (node (ref "T312") (pin "3") (pinfunction "C_3") (pintype "passive"))
      (node (ref "T314") (pin "3") (pinfunction "C_3") (pintype "passive"))
      (node (ref "T330") (pin "3") (pinfunction "C_3") (pintype "passive"))
      (node (ref "T331") (pin "3") (pinfunction "C_3") (pintype "passive"))
      (node (ref "T332") (pin "3") (pinfunction "C_3") (pintype "passive"))
      (node (ref "T333") (pin "3") (pinfunction "C_3") (pintype "passive"))
      (node (ref "T334") (pin "3") (pinfunction "C_3") (pintype "passive"))
      (node (ref "T335") (pin "3") (pinfunction "C_3") (pintype "passive"))
      (node (ref "T336") (pin "3") (pinfunction "C_3") (pintype "passive"))
      (node (ref "T337") (pin "3") (pinfunction "C_3") (pintype "passive"))
      (node (ref "T338") (pin "3") (pinfunction "C_3") (pintype "passive"))
      (node (ref "T340") (pin "3") (pinfunction "C_3") (pintype "passive"))
      (node (ref "T356") (pin "3") (pinfunction "C_3") (pintype "passive"))
      (node (ref "T357") (pin "3") (pinfunction "C_3") (pintype "passive"))
      (node (ref "T358") (pin "3") (pinfunction "C_3") (pintype "passive"))
      (node (ref "T359") (pin "3") (pinfunction "C_3") (pintype "passive"))
      (node (ref "T360") (pin "3") (pinfunction "C_3") (pintype "passive"))
      (node (ref "T361") (pin "3") (pinfunction "C_3") (pintype "passive"))
      (node (ref "T362") (pin "3") (pinfunction "C_3") (pintype "passive"))
      (node (ref "T363") (pin "3") (pinfunction "C_3") (pintype "passive"))
      (node (ref "T364") (pin "3") (pinfunction "C_3") (pintype "passive"))
      (node (ref "T366") (pin "3") (pinfunction "C_3") (pintype "passive"))
      (node (ref "T382") (pin "3") (pinfunction "C_3") (pintype "passive"))
      (node (ref "T383") (pin "3") (pinfunction "C_3") (pintype "passive"))
      (node (ref "T384") (pin "3") (pinfunction "C_3") (pintype "passive"))
      (node (ref "T385") (pin "3") (pinfunction "C_3") (pintype "passive"))
      (node (ref "T386") (pin "3") (pinfunction "C_3") (pintype "passive"))
      (node (ref "T387") (pin "3") (pinfunction "C_3") (pintype "passive"))
      (node (ref "T388") (pin "3") (pinfunction "C_3") (pintype "passive"))
      (node (ref "T389") (pin "3") (pinfunction "C_3") (pintype "passive"))
      (node (ref "T390") (pin "3") (pinfunction "C_3") (pintype "passive"))
      (node (ref "T392") (pin "3") (pinfunction "C_3") (pintype "passive"))
      (node (ref "T408") (pin "3") (pinfunction "C_3") (pintype "passive"))
      (node (ref "T409") (pin "3") (pinfunction "C_3") (pintype "passive"))
      (node (ref "T410") (pin "3") (pinfunction "C_3") (pintype "passive"))
      (node (ref "T411") (pin "3") (pinfunction "C_3") (pintype "passive"))
      (node (ref "T412") (pin "3") (pinfunction "C_3") (pintype "passive"))
      (node (ref "T413") (pin "3") (pinfunction "C_3") (pintype "passive"))
      (node (ref "T414") (pin "3") (pinfunction "C_3") (pintype "passive"))
      (node (ref "T415") (pin "3") (pinfunction "C_3") (pintype "passive"))
      (node (ref "T416") (pin "3") (pinfunction "C_3") (pintype "passive"))
      (node (ref "T44") (pin "3") (pinfunction "C_3") (pintype "passive"))
      (node (ref "T45") (pin "3") (pinfunction "C_3") (pintype "passive"))
      (node (ref "T46") (pin "3") (pinfunction "C_3") (pintype "passive"))
      (node (ref "T47") (pin "3") (pinfunction "C_3") (pintype "passive"))
      (node (ref "T48") (pin "3") (pinfunction "C_3") (pintype "passive"))
      (node (ref "T49") (pin "3") (pinfunction "C_3") (pintype "passive"))
      (node (ref "T50") (pin "3") (pinfunction "C_3") (pintype "passive"))
      (node (ref "T51") (pin "3") (pinfunction "C_3") (pintype "passive"))
      (node (ref "T52") (pin "3") (pinfunction "C_3") (pintype "passive"))
      (node (ref "T54") (pin "3") (pinfunction "C_3") (pintype "passive"))
      (node (ref "T70") (pin "3") (pinfunction "C_3") (pintype "passive"))
      (node (ref "T71") (pin "3") (pinfunction "C_3") (pintype "passive"))
      (node (ref "T72") (pin "3") (pinfunction "C_3") (pintype "passive"))
      (node (ref "T73") (pin "3") (pinfunction "C_3") (pintype "passive"))
      (node (ref "T74") (pin "3") (pinfunction "C_3") (pintype "passive"))
      (node (ref "T75") (pin "3") (pinfunction "C_3") (pintype "passive"))
      (node (ref "T76") (pin "3") (pinfunction "C_3") (pintype "passive"))
      (node (ref "T77") (pin "3") (pinfunction "C_3") (pintype "passive"))
      (node (ref "T78") (pin "3") (pinfunction "C_3") (pintype "passive"))
      (node (ref "T80") (pin "3") (pinfunction "C_3") (pintype "passive"))
      (node (ref "T96") (pin "3") (pinfunction "C_3") (pintype "passive"))
      (node (ref "T97") (pin "3") (pinfunction "C_3") (pintype "passive"))
      (node (ref "T98") (pin "3") (pinfunction "C_3") (pintype "passive"))
      (node (ref "T99") (pin "3") (pinfunction "C_3") (pintype "passive"))
    )
  )
)
